# J007017_RGB_IR.net
KiCad netlist of a schematic drawn in EAGLE
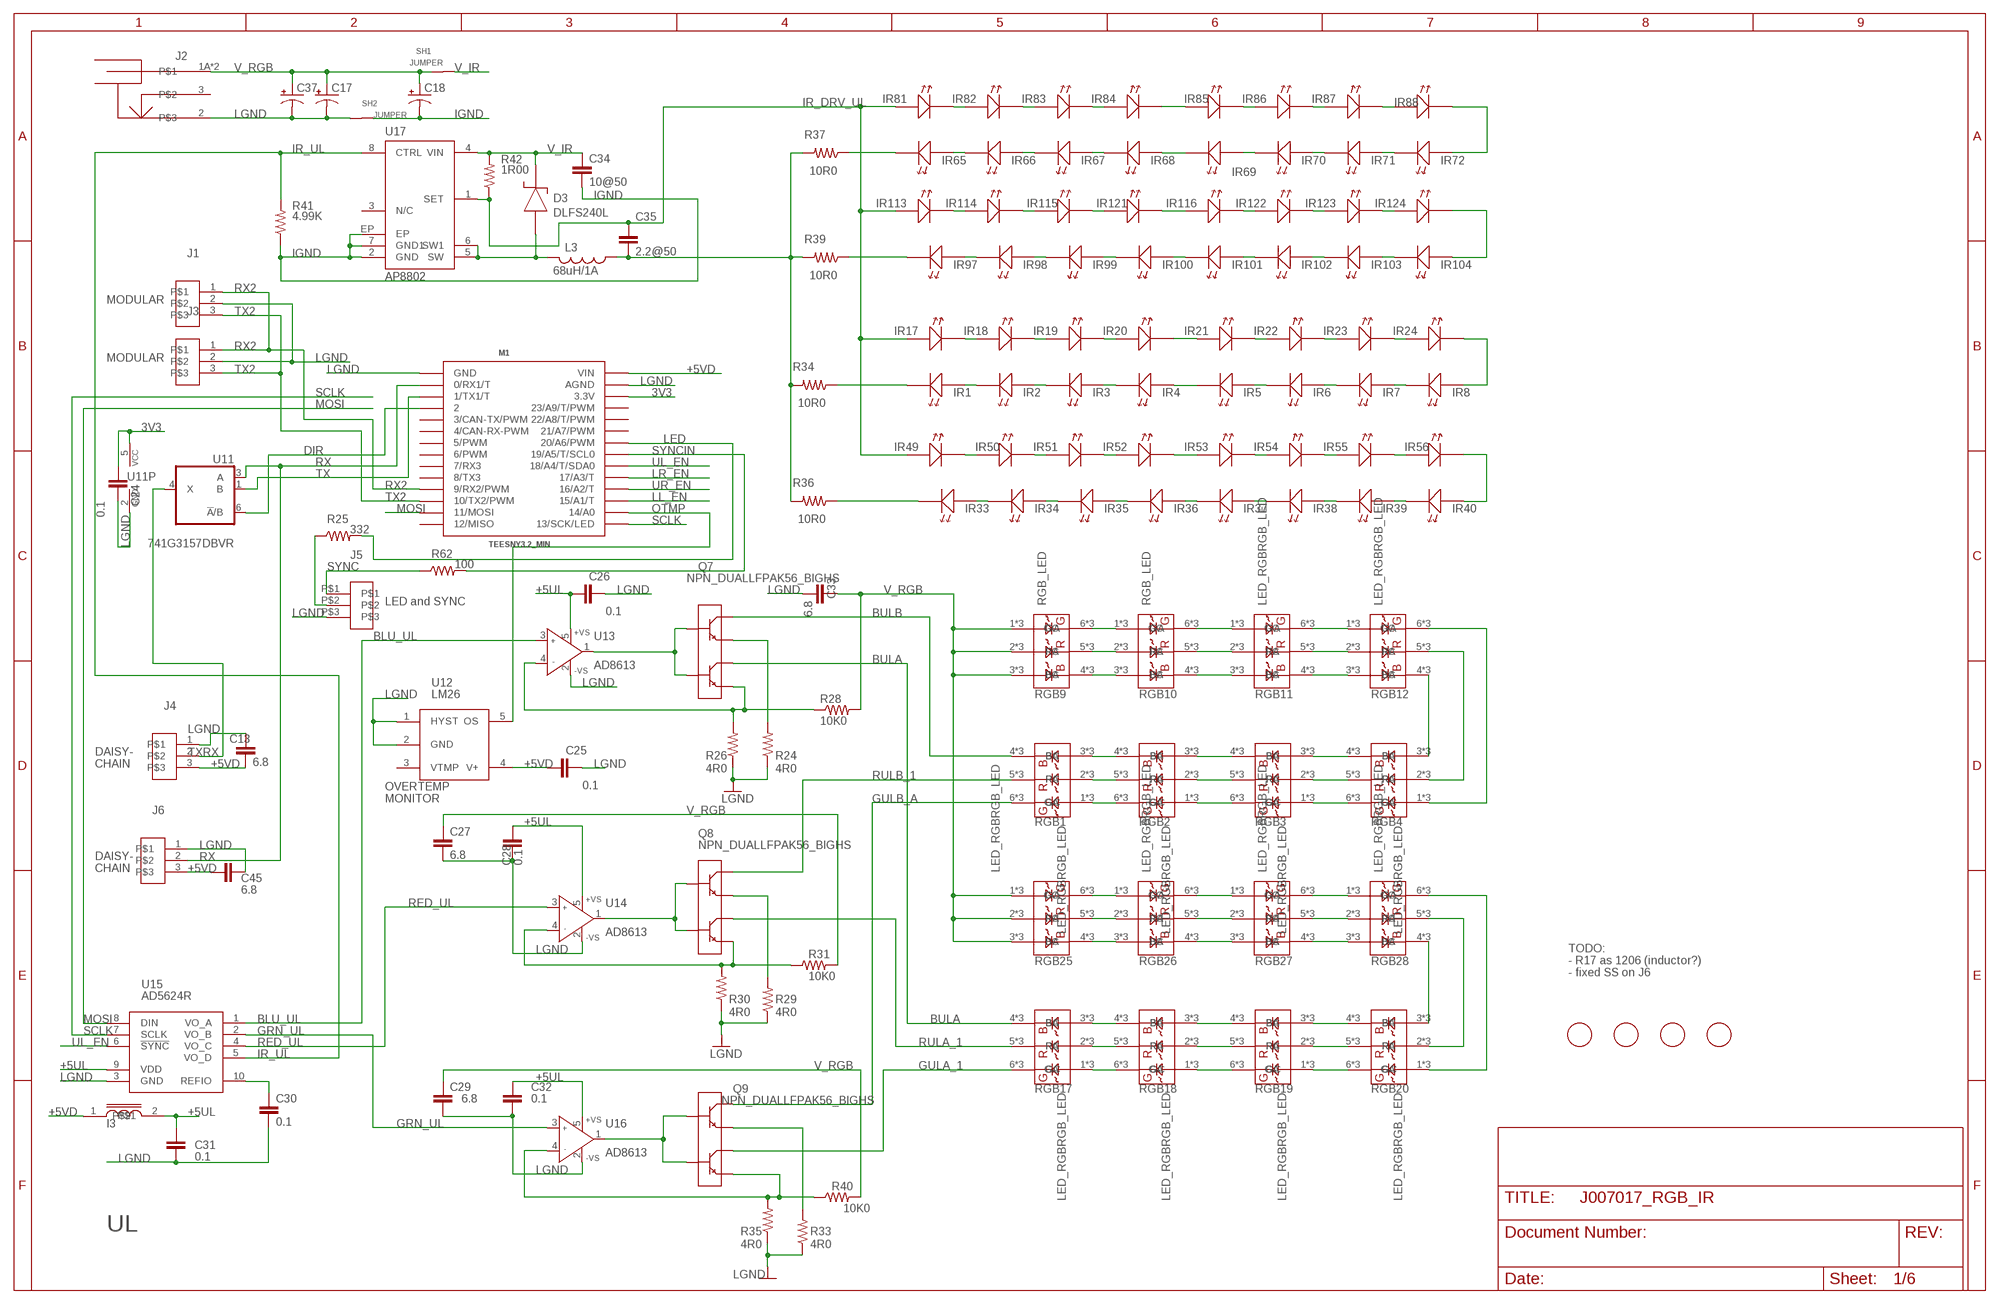
[diagram p0: schematic, sheet 1]
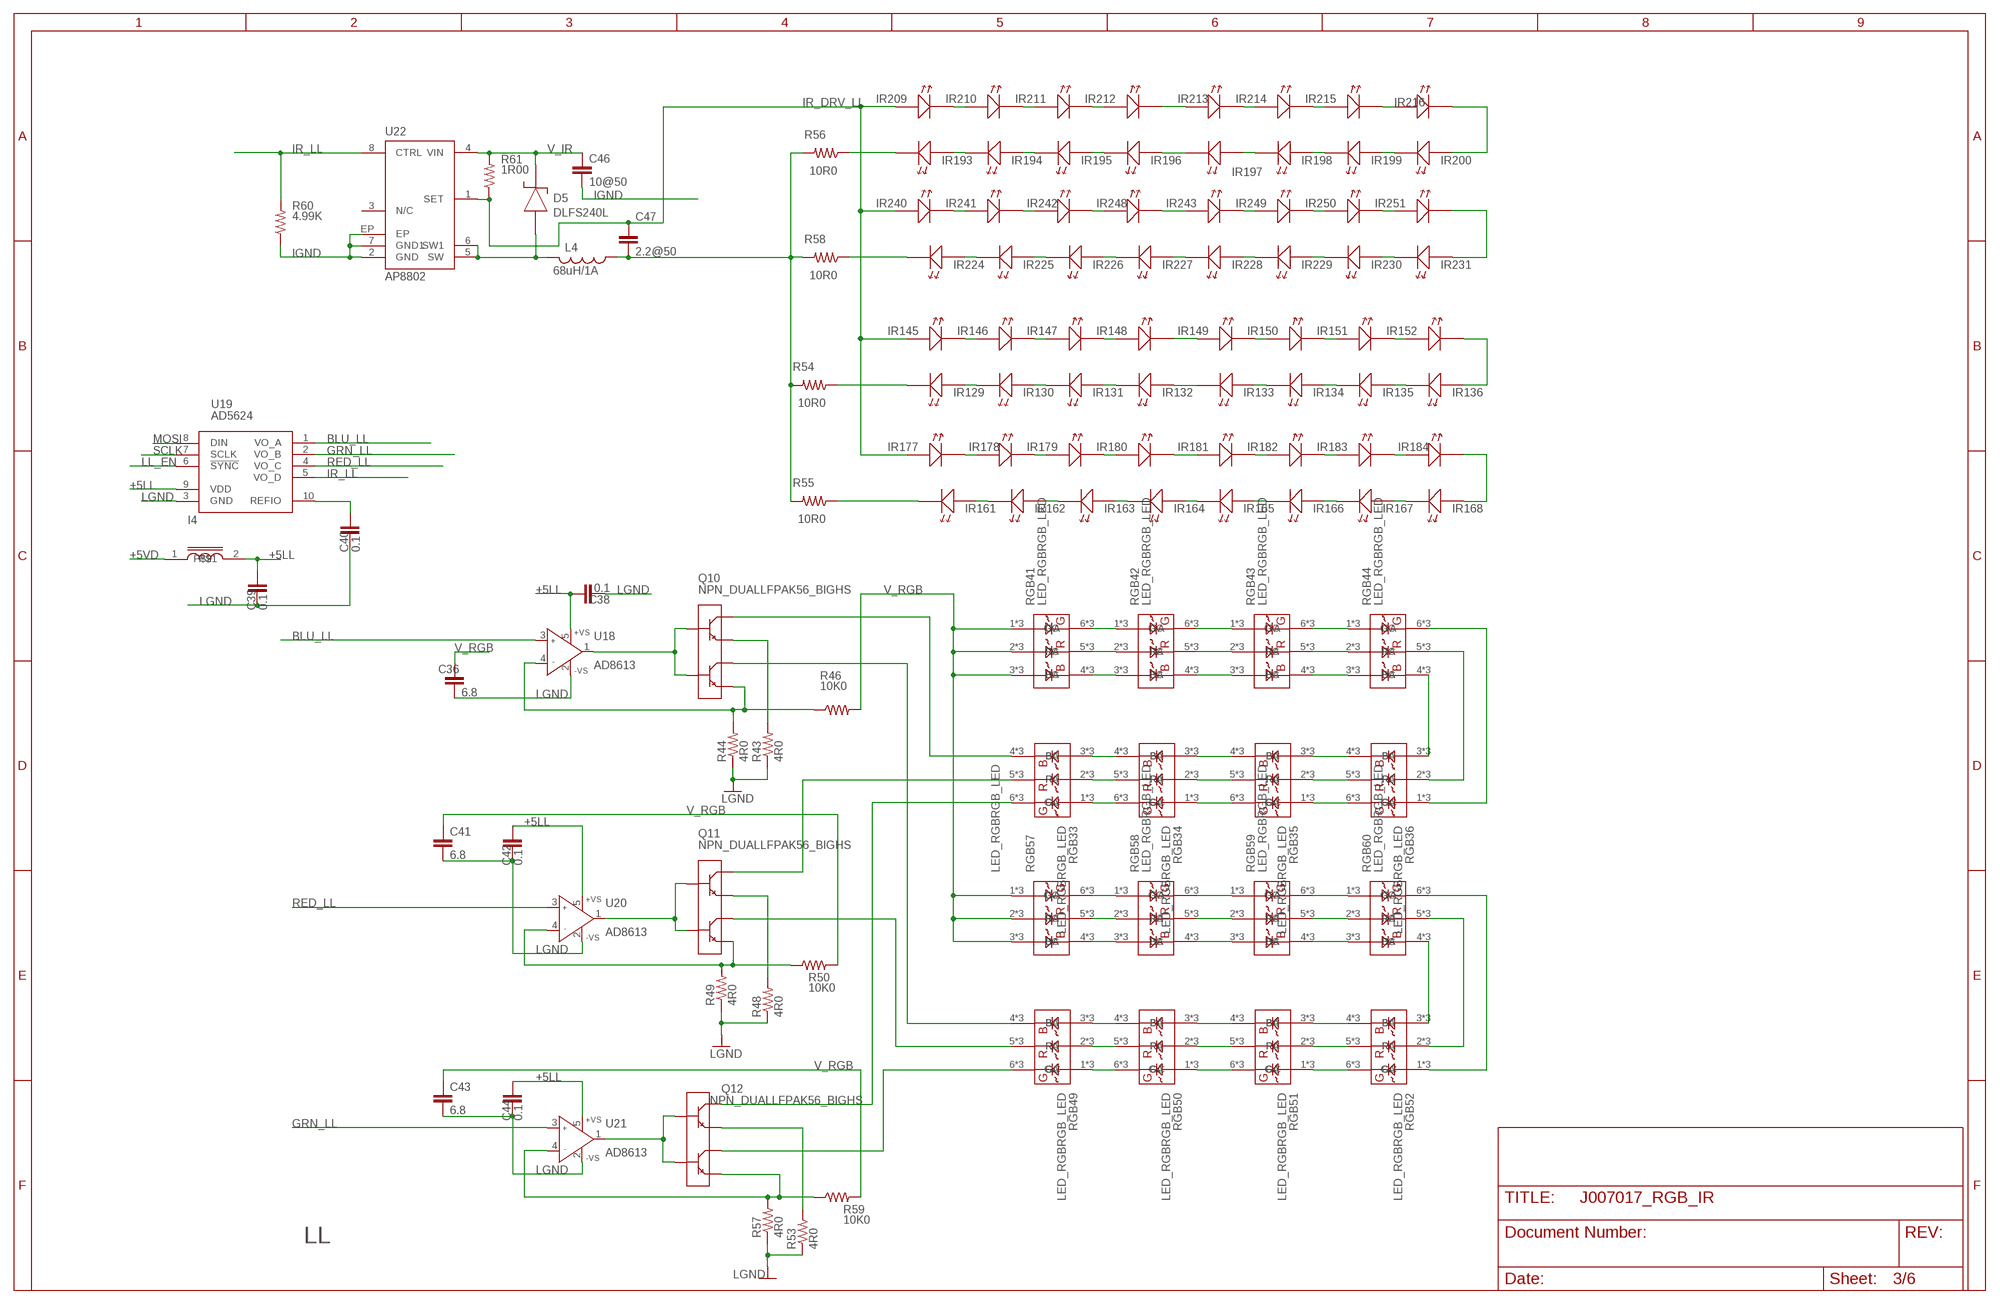
[diagram p1: schematic, sheet 3]
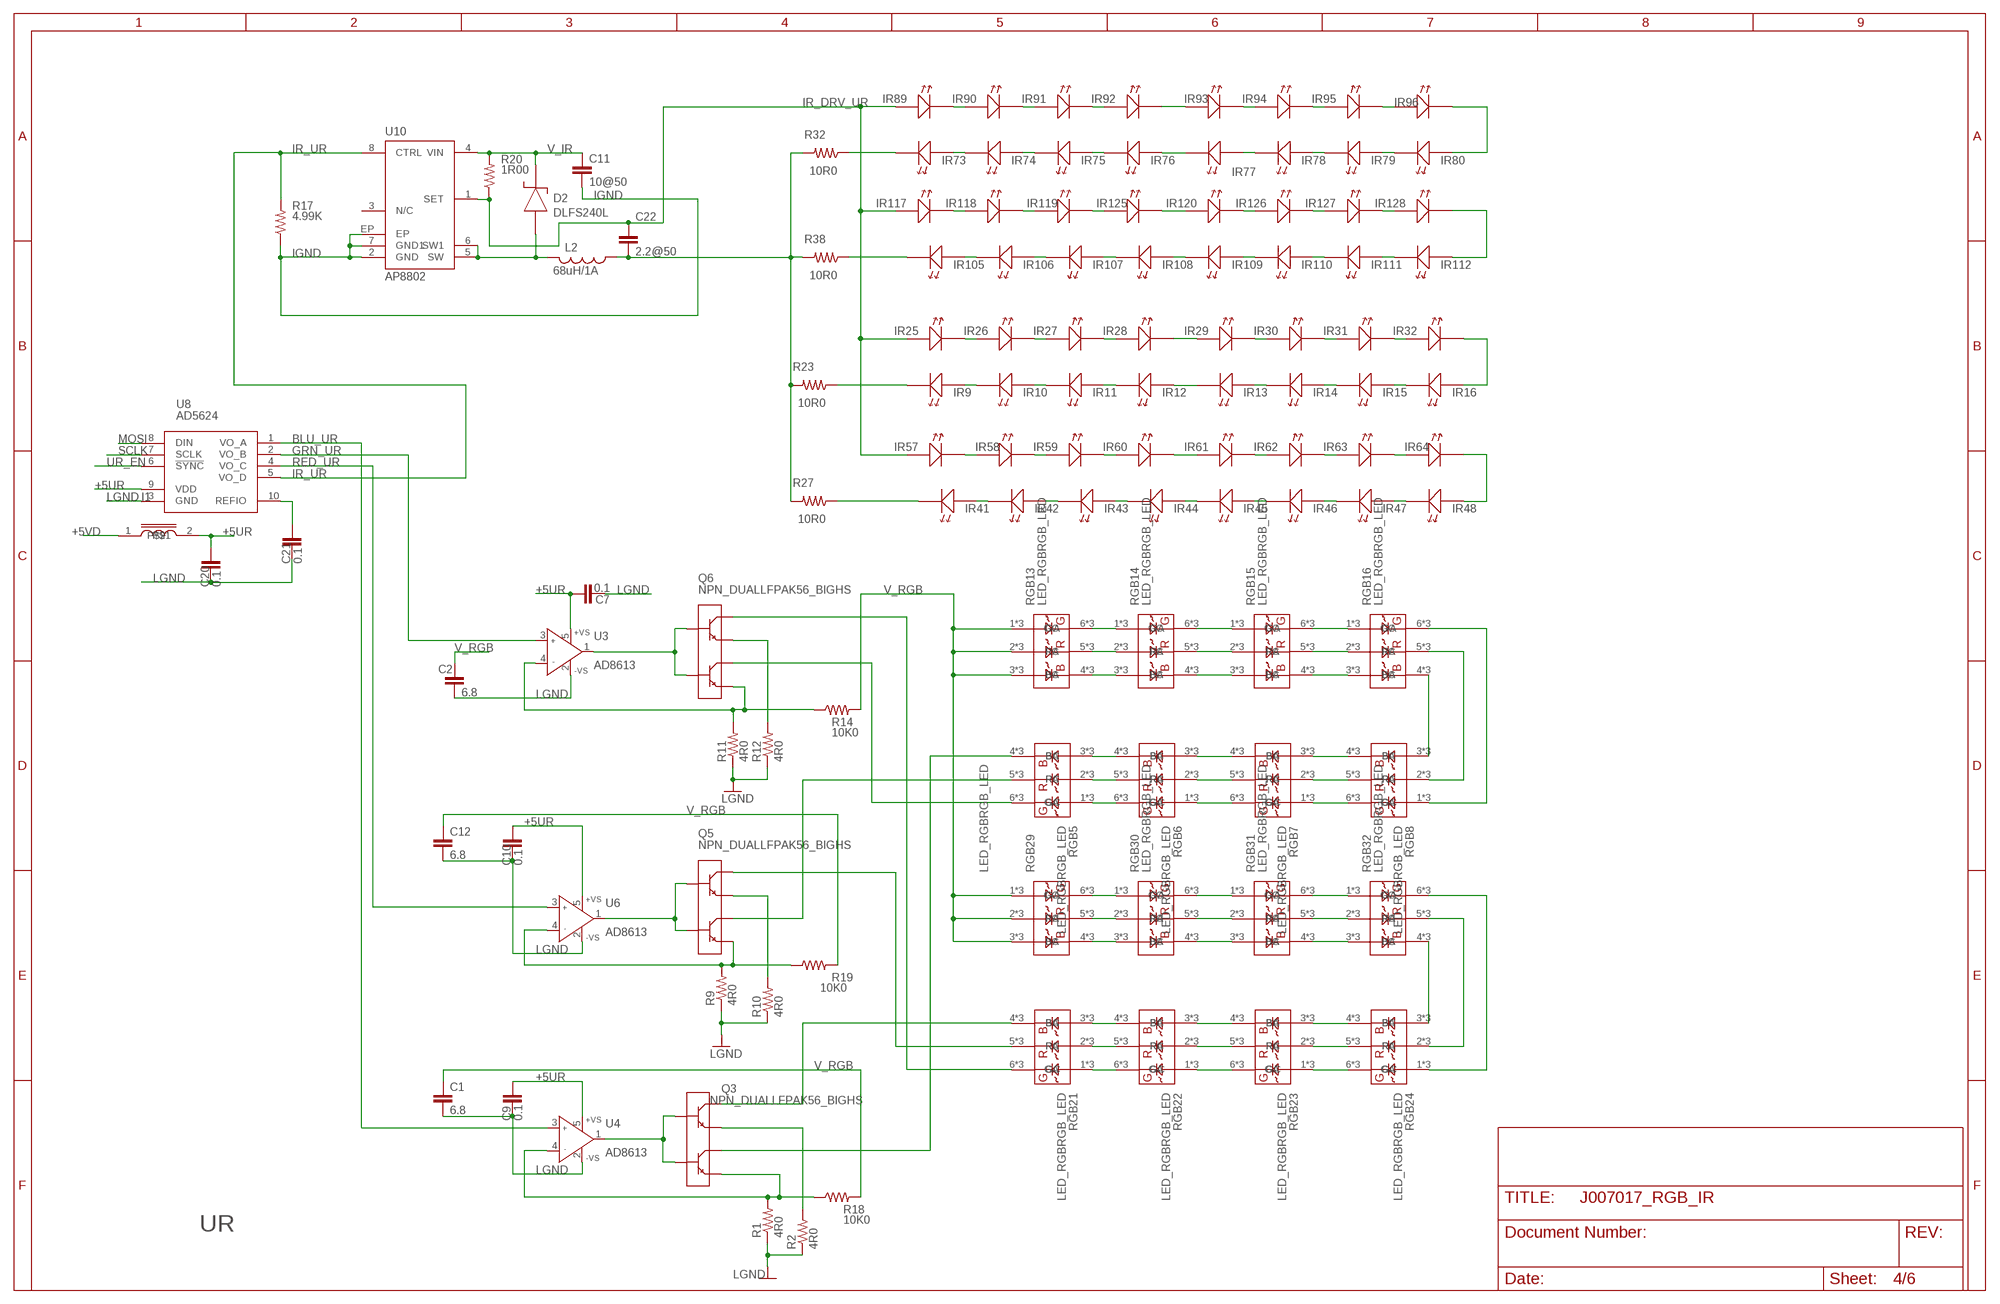
[diagram p2: schematic, sheet 4]
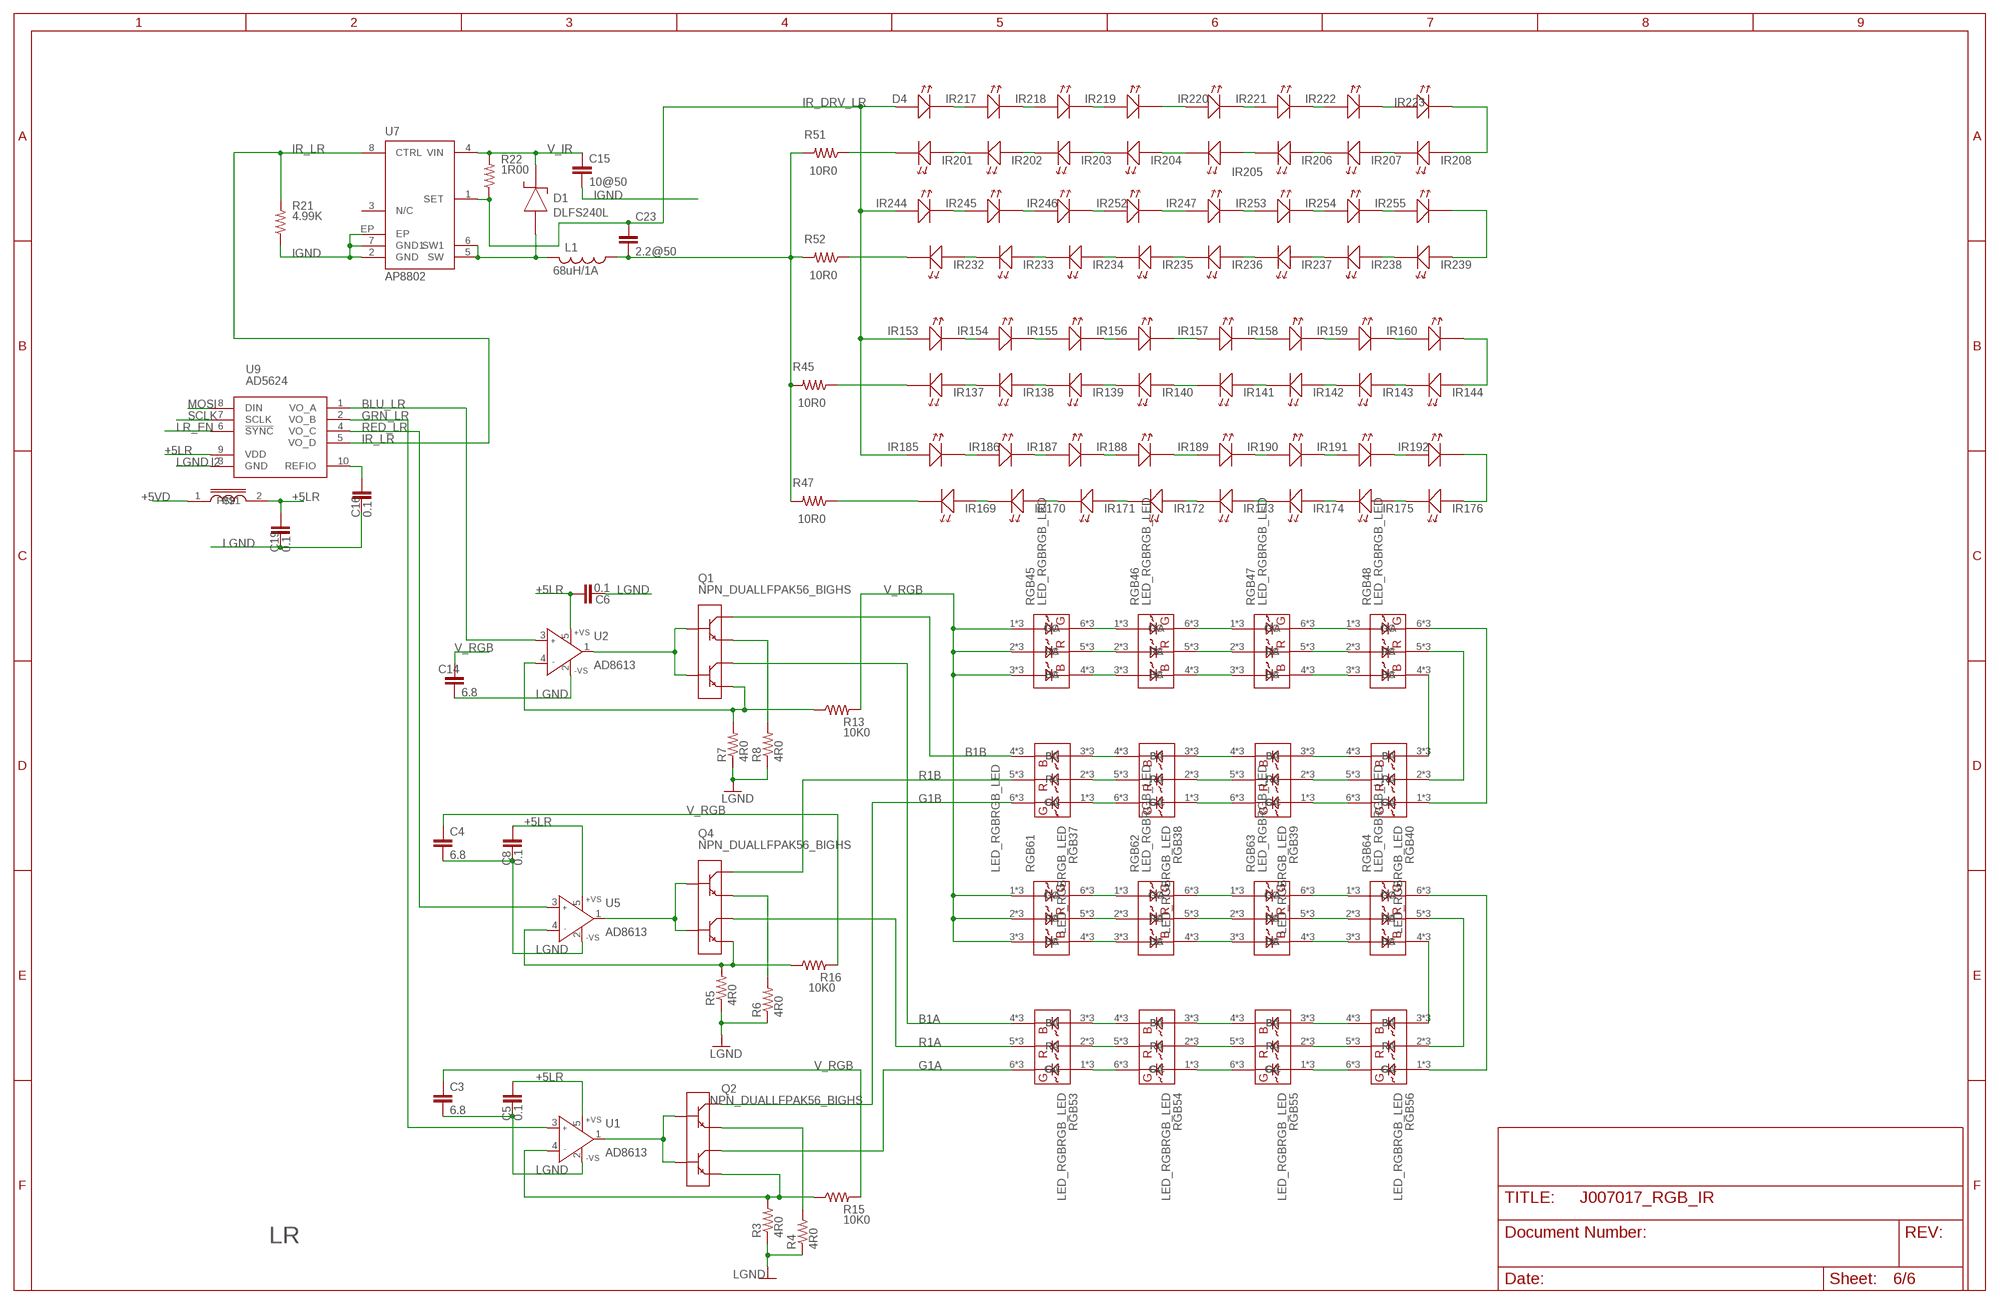
[diagram p3: schematic, sheet 6]

(export (version "E")
  (design (tool "Eeschema 10.0.6"))
  (components
    (comp (ref "C3")
      (value "6.8")
      (footprint "eagle-import:1210S")
      (libsource (lib "eagle-import") (part "CAPS1210S"))
    )
    (comp (ref "C4")
      (value "6.8")
      (footprint "eagle-import:1210S")
      (libsource (lib "eagle-import") (part "CAPS1210S"))
    )
    (comp (ref "C5")
      (value "0.1")
      (footprint "eagle-import:0603S")
      (libsource (lib "eagle-import") (part "CAPS0603S"))
    )
    (comp (ref "C6")
      (value "0.1")
      (footprint "eagle-import:0603S")
      (libsource (lib "eagle-import") (part "CAPS0603S"))
    )
    (comp (ref "C8")
      (value "0.1")
      (footprint "eagle-import:0603S")
      (libsource (lib "eagle-import") (part "CAPS0603S"))
    )
    (comp (ref "C14")
      (value "6.8")
      (footprint "eagle-import:1210S")
      (libsource (lib "eagle-import") (part "CAPS1210S"))
    )
    (comp (ref "C15")
      (value "10@50")
      (footprint "eagle-import:1210S")
      (libsource (lib "eagle-import") (part "CAPS1210S"))
    )
    (comp (ref "C16")
      (value "0.1")
      (footprint "eagle-import:0603S")
      (libsource (lib "eagle-import") (part "CAPS0603S"))
    )
    (comp (ref "C19")
      (value "0.1")
      (footprint "eagle-import:0603S")
      (libsource (lib "eagle-import") (part "CAPS0603S"))
    )
    (comp (ref "C23")
      (value "2.2@50")
      (footprint "eagle-import:1206S")
      (libsource (lib "eagle-import") (part "CAPS1206S"))
    )
    (comp (ref "D1")
      (value "DLFS240L")
      (footprint "eagle-import:PWRDI-123")
      (libsource (lib "eagle-import") (part "DIODE_SCHOTTKYPWRDI-123"))
    )
    (comp (ref "D4")
      (value "LEDLED_SFH4050_HEAT")
      (footprint "eagle-import:LED_SFH4050_HEAT")
      (libsource (lib "eagle-import") (part "LEDLED_SFH4050_HEAT"))
    )
    (comp (ref "I2")
      (value "INDUCTOR0805S")
      (footprint "eagle-import:0805S")
      (libsource (lib "eagle-import") (part "INDUCTOR0805S"))
    )
    (comp (ref "IR137")
      (value "LEDLED_SFH4050")
      (footprint "eagle-import:LED_SFH4050")
      (libsource (lib "eagle-import") (part "LEDLED_SFH4050"))
    )
    (comp (ref "IR138")
      (value "LEDLED_SFH4050_HEAT")
      (footprint "eagle-import:LED_SFH4050_HEAT")
      (libsource (lib "eagle-import") (part "LEDLED_SFH4050_HEAT"))
    )
    (comp (ref "IR139")
      (value "LEDLED_SFH4050_HEAT")
      (footprint "eagle-import:LED_SFH4050_HEAT")
      (libsource (lib "eagle-import") (part "LEDLED_SFH4050_HEAT"))
    )
    (comp (ref "IR140")
      (value "LEDLED_SFH4050_HEAT")
      (footprint "eagle-import:LED_SFH4050_HEAT")
      (libsource (lib "eagle-import") (part "LEDLED_SFH4050_HEAT"))
    )
    (comp (ref "IR141")
      (value "LEDLED_SFH4050_HEAT")
      (footprint "eagle-import:LED_SFH4050_HEAT")
      (libsource (lib "eagle-import") (part "LEDLED_SFH4050_HEAT"))
    )
    (comp (ref "IR142")
      (value "LEDLED_SFH4050_HEAT")
      (footprint "eagle-import:LED_SFH4050_HEAT")
      (libsource (lib "eagle-import") (part "LEDLED_SFH4050_HEAT"))
    )
    (comp (ref "IR143")
      (value "LEDLED_SFH4050_HEAT")
      (footprint "eagle-import:LED_SFH4050_HEAT")
      (libsource (lib "eagle-import") (part "LEDLED_SFH4050_HEAT"))
    )
    (comp (ref "IR144")
      (value "LEDLED_SFH4050_HEAT")
      (footprint "eagle-import:LED_SFH4050_HEAT")
      (libsource (lib "eagle-import") (part "LEDLED_SFH4050_HEAT"))
    )
    (comp (ref "IR153")
      (value "LEDLED_SFH4050_HEAT")
      (footprint "eagle-import:LED_SFH4050_HEAT")
      (libsource (lib "eagle-import") (part "LEDLED_SFH4050_HEAT"))
    )
    (comp (ref "IR154")
      (value "LEDLED_SFH4050_A")
      (footprint "eagle-import:LED_SFH4045_HEAT_A")
      (libsource (lib "eagle-import") (part "LEDLED_SFH4050_A"))
    )
    (comp (ref "IR155")
      (value "LEDLED_SFH4050_HEAT")
      (footprint "eagle-import:LED_SFH4050_HEAT")
      (libsource (lib "eagle-import") (part "LEDLED_SFH4050_HEAT"))
    )
    (comp (ref "IR156")
      (value "LEDLED_SFH4050_HEAT")
      (footprint "eagle-import:LED_SFH4050_HEAT")
      (libsource (lib "eagle-import") (part "LEDLED_SFH4050_HEAT"))
    )
    (comp (ref "IR157")
      (value "LEDLED_SFH4050_HEAT")
      (footprint "eagle-import:LED_SFH4050_HEAT")
      (libsource (lib "eagle-import") (part "LEDLED_SFH4050_HEAT"))
    )
    (comp (ref "IR158")
      (value "LEDLED_SFH4050_HEAT")
      (footprint "eagle-import:LED_SFH4050_HEAT")
      (libsource (lib "eagle-import") (part "LEDLED_SFH4050_HEAT"))
    )
    (comp (ref "IR159")
      (value "LEDLED_SFH4050_HEAT")
      (footprint "eagle-import:LED_SFH4050_HEAT")
      (libsource (lib "eagle-import") (part "LEDLED_SFH4050_HEAT"))
    )
    (comp (ref "IR160")
      (value "LEDLED_SFH4050_HEAT")
      (footprint "eagle-import:LED_SFH4050_HEAT")
      (libsource (lib "eagle-import") (part "LEDLED_SFH4050_HEAT"))
    )
    (comp (ref "IR169")
      (value "LEDLED_SFH4050_HEAT")
      (footprint "eagle-import:LED_SFH4050_HEAT")
      (libsource (lib "eagle-import") (part "LEDLED_SFH4050_HEAT"))
    )
    (comp (ref "IR170")
      (value "LEDLED_SFH4050_HEAT")
      (footprint "eagle-import:LED_SFH4050_HEAT")
      (libsource (lib "eagle-import") (part "LEDLED_SFH4050_HEAT"))
    )
    (comp (ref "IR171")
      (value "LEDLED_SFH4050_HEAT")
      (footprint "eagle-import:LED_SFH4050_HEAT")
      (libsource (lib "eagle-import") (part "LEDLED_SFH4050_HEAT"))
    )
    (comp (ref "IR172")
      (value "LEDLED_SFH4050_HEAT")
      (footprint "eagle-import:LED_SFH4050_HEAT")
      (libsource (lib "eagle-import") (part "LEDLED_SFH4050_HEAT"))
    )
    (comp (ref "IR173")
      (value "LEDLED_SFH4050_HEAT")
      (footprint "eagle-import:LED_SFH4050_HEAT")
      (libsource (lib "eagle-import") (part "LEDLED_SFH4050_HEAT"))
    )
    (comp (ref "IR174")
      (value "LEDLED_SFH4050_HEAT")
      (footprint "eagle-import:LED_SFH4050_HEAT")
      (libsource (lib "eagle-import") (part "LEDLED_SFH4050_HEAT"))
    )
    (comp (ref "IR175")
      (value "LEDLED_SFH4050_HEAT")
      (footprint "eagle-import:LED_SFH4050_HEAT")
      (libsource (lib "eagle-import") (part "LEDLED_SFH4050_HEAT"))
    )
    (comp (ref "IR176")
      (value "LEDLED_SFH4050_HEAT")
      (footprint "eagle-import:LED_SFH4050_HEAT")
      (libsource (lib "eagle-import") (part "LEDLED_SFH4050_HEAT"))
    )
    (comp (ref "IR185")
      (value "LEDLED_SFH4050_HEAT")
      (footprint "eagle-import:LED_SFH4050_HEAT")
      (libsource (lib "eagle-import") (part "LEDLED_SFH4050_HEAT"))
    )
    (comp (ref "IR186")
      (value "LEDLED_SFH4050_HEAT")
      (footprint "eagle-import:LED_SFH4050_HEAT")
      (libsource (lib "eagle-import") (part "LEDLED_SFH4050_HEAT"))
    )
    (comp (ref "IR187")
      (value "LEDLED_SFH4050_HEAT")
      (footprint "eagle-import:LED_SFH4050_HEAT")
      (libsource (lib "eagle-import") (part "LEDLED_SFH4050_HEAT"))
    )
    (comp (ref "IR188")
      (value "LEDLED_SFH4050_HEAT")
      (footprint "eagle-import:LED_SFH4050_HEAT")
      (libsource (lib "eagle-import") (part "LEDLED_SFH4050_HEAT"))
    )
    (comp (ref "IR189")
      (value "LEDLED_SFH4050_HEAT")
      (footprint "eagle-import:LED_SFH4050_HEAT")
      (libsource (lib "eagle-import") (part "LEDLED_SFH4050_HEAT"))
    )
    (comp (ref "IR190")
      (value "LEDLED_SFH4050_HEAT")
      (footprint "eagle-import:LED_SFH4050_HEAT")
      (libsource (lib "eagle-import") (part "LEDLED_SFH4050_HEAT"))
    )
    (comp (ref "IR191")
      (value "LEDLED_SFH4050_HEAT")
      (footprint "eagle-import:LED_SFH4050_HEAT")
      (libsource (lib "eagle-import") (part "LEDLED_SFH4050_HEAT"))
    )
    (comp (ref "IR192")
      (value "LEDLED_SFH4050_HEAT")
      (footprint "eagle-import:LED_SFH4050_HEAT")
      (libsource (lib "eagle-import") (part "LEDLED_SFH4050_HEAT"))
    )
    (comp (ref "IR201")
      (value "LEDLED_SFH4050_HEAT")
      (footprint "eagle-import:LED_SFH4050_HEAT")
      (libsource (lib "eagle-import") (part "LEDLED_SFH4050_HEAT"))
    )
    (comp (ref "IR202")
      (value "LEDLED_SFH4050_HEAT")
      (footprint "eagle-import:LED_SFH4050_HEAT")
      (libsource (lib "eagle-import") (part "LEDLED_SFH4050_HEAT"))
    )
    (comp (ref "IR203")
      (value "LEDLED_SFH4050_HEAT")
      (footprint "eagle-import:LED_SFH4050_HEAT")
      (libsource (lib "eagle-import") (part "LEDLED_SFH4050_HEAT"))
    )
    (comp (ref "IR204")
      (value "LEDLED_SFH4050_HEAT")
      (footprint "eagle-import:LED_SFH4050_HEAT")
      (libsource (lib "eagle-import") (part "LEDLED_SFH4050_HEAT"))
    )
    (comp (ref "IR205")
      (value "LEDLED_SFH4050_HEAT")
      (footprint "eagle-import:LED_SFH4050_HEAT")
      (libsource (lib "eagle-import") (part "LEDLED_SFH4050_HEAT"))
    )
    (comp (ref "IR206")
      (value "LEDLED_SFH4050_HEAT")
      (footprint "eagle-import:LED_SFH4050_HEAT")
      (libsource (lib "eagle-import") (part "LEDLED_SFH4050_HEAT"))
    )
    (comp (ref "IR207")
      (value "LEDLED_SFH4050_HEAT")
      (footprint "eagle-import:LED_SFH4050_HEAT")
      (libsource (lib "eagle-import") (part "LEDLED_SFH4050_HEAT"))
    )
    (comp (ref "IR208")
      (value "LEDLED_SFH4050_HEAT")
      (footprint "eagle-import:LED_SFH4050_HEAT")
      (libsource (lib "eagle-import") (part "LEDLED_SFH4050_HEAT"))
    )
    (comp (ref "IR217")
      (value "LEDLED_SFH4050_HEAT")
      (footprint "eagle-import:LED_SFH4050_HEAT")
      (libsource (lib "eagle-import") (part "LEDLED_SFH4050_HEAT"))
    )
    (comp (ref "IR218")
      (value "LEDLED_SFH4050_HEAT")
      (footprint "eagle-import:LED_SFH4050_HEAT")
      (libsource (lib "eagle-import") (part "LEDLED_SFH4050_HEAT"))
    )
    (comp (ref "IR219")
      (value "LEDLED_SFH4050_HEAT")
      (footprint "eagle-import:LED_SFH4050_HEAT")
      (libsource (lib "eagle-import") (part "LEDLED_SFH4050_HEAT"))
    )
    (comp (ref "IR220")
      (value "LEDLED_SFH4050_HEAT")
      (footprint "eagle-import:LED_SFH4050_HEAT")
      (libsource (lib "eagle-import") (part "LEDLED_SFH4050_HEAT"))
    )
    (comp (ref "IR221")
      (value "LEDLED_SFH4050_HEAT")
      (footprint "eagle-import:LED_SFH4050_HEAT")
      (libsource (lib "eagle-import") (part "LEDLED_SFH4050_HEAT"))
    )
    (comp (ref "IR222")
      (value "LEDLED_SFH4050_HEAT")
      (footprint "eagle-import:LED_SFH4050_HEAT")
      (libsource (lib "eagle-import") (part "LEDLED_SFH4050_HEAT"))
    )
    (comp (ref "IR223")
      (value "LEDLED_SFH4050_HEAT")
      (footprint "eagle-import:LED_SFH4050_HEAT")
      (libsource (lib "eagle-import") (part "LEDLED_SFH4050_HEAT"))
    )
    (comp (ref "IR232")
      (value "LEDLED_SFH4050_HEAT")
      (footprint "eagle-import:LED_SFH4050_HEAT")
      (libsource (lib "eagle-import") (part "LEDLED_SFH4050_HEAT"))
    )
    (comp (ref "IR233")
      (value "LEDLED_SFH4050_HEAT")
      (footprint "eagle-import:LED_SFH4050_HEAT")
      (libsource (lib "eagle-import") (part "LEDLED_SFH4050_HEAT"))
    )
    (comp (ref "IR234")
      (value "LEDLED_SFH4050_HEAT")
      (footprint "eagle-import:LED_SFH4050_HEAT")
      (libsource (lib "eagle-import") (part "LEDLED_SFH4050_HEAT"))
    )
    (comp (ref "IR235")
      (value "LEDLED_SFH4050_HEAT")
      (footprint "eagle-import:LED_SFH4050_HEAT")
      (libsource (lib "eagle-import") (part "LEDLED_SFH4050_HEAT"))
    )
    (comp (ref "IR236")
      (value "LEDLED_SFH4050_HEAT")
      (footprint "eagle-import:LED_SFH4050_HEAT")
      (libsource (lib "eagle-import") (part "LEDLED_SFH4050_HEAT"))
    )
    (comp (ref "IR237")
      (value "LEDLED_SFH4050_HEAT")
      (footprint "eagle-import:LED_SFH4050_HEAT")
      (libsource (lib "eagle-import") (part "LEDLED_SFH4050_HEAT"))
    )
    (comp (ref "IR238")
      (value "LEDLED_SFH4050_HEAT")
      (footprint "eagle-import:LED_SFH4050_HEAT")
      (libsource (lib "eagle-import") (part "LEDLED_SFH4050_HEAT"))
    )
    (comp (ref "IR239")
      (value "LEDLED_SFH4050_HEAT")
      (footprint "eagle-import:LED_SFH4050_HEAT")
      (libsource (lib "eagle-import") (part "LEDLED_SFH4050_HEAT"))
    )
    (comp (ref "IR244")
      (value "LEDLED_SFH4050_HEAT")
      (footprint "eagle-import:LED_SFH4050_HEAT")
      (libsource (lib "eagle-import") (part "LEDLED_SFH4050_HEAT"))
    )
    (comp (ref "IR245")
      (value "LEDLED_SFH4050_HEAT")
      (footprint "eagle-import:LED_SFH4050_HEAT")
      (libsource (lib "eagle-import") (part "LEDLED_SFH4050_HEAT"))
    )
    (comp (ref "IR246")
      (value "LEDLED_SFH4050_HEAT")
      (footprint "eagle-import:LED_SFH4050_HEAT")
      (libsource (lib "eagle-import") (part "LEDLED_SFH4050_HEAT"))
    )
    (comp (ref "IR247")
      (value "LEDLED_SFH4050_HEAT")
      (footprint "eagle-import:LED_SFH4050_HEAT")
      (libsource (lib "eagle-import") (part "LEDLED_SFH4050_HEAT"))
    )
    (comp (ref "IR252")
      (value "LEDLED_SFH4050_HEAT")
      (footprint "eagle-import:LED_SFH4050_HEAT")
      (libsource (lib "eagle-import") (part "LEDLED_SFH4050_HEAT"))
    )
    (comp (ref "IR253")
      (value "LEDLED_SFH4050_HEAT")
      (footprint "eagle-import:LED_SFH4050_HEAT")
      (libsource (lib "eagle-import") (part "LEDLED_SFH4050_HEAT"))
    )
    (comp (ref "IR254")
      (value "LEDLED_SFH4050_HEAT")
      (footprint "eagle-import:LED_SFH4050_HEAT")
      (libsource (lib "eagle-import") (part "LEDLED_SFH4050_HEAT"))
    )
    (comp (ref "IR255")
      (value "LEDLED_SFH4050")
      (footprint "eagle-import:LED_SFH4050")
      (libsource (lib "eagle-import") (part "LEDLED_SFH4050"))
    )
    (comp (ref "L1")
      (value "68uH/1A")
      (footprint "eagle-import:SRU8043")
      (libsource (lib "eagle-import") (part "INDUCTOR_SMSRU8043"))
    )
    (comp (ref "Q1")
      (value "NPN_DUALLFPAK56_BIGHS")
      (footprint "eagle-import:LFPAK56_HS2")
      (libsource (lib "eagle-import") (part "NPN_DUALLFPAK56_BIGHS"))
    )
    (comp (ref "Q2")
      (value "NPN_DUALLFPAK56_BIGHS")
      (footprint "eagle-import:LFPAK56_HS2")
      (libsource (lib "eagle-import") (part "NPN_DUALLFPAK56_BIGHS"))
    )
    (comp (ref "Q4")
      (value "NPN_DUALLFPAK56_BIGHS")
      (footprint "eagle-import:LFPAK56_HS2")
      (libsource (lib "eagle-import") (part "NPN_DUALLFPAK56_BIGHS"))
    )
    (comp (ref "R3")
      (value "4R0")
      (footprint "eagle-import:1812")
      (libsource (lib "eagle-import") (part "RESISTOR-POWER1812"))
    )
    (comp (ref "R4")
      (value "4R0")
      (footprint "eagle-import:1812")
      (libsource (lib "eagle-import") (part "RESISTOR-POWER1812"))
    )
    (comp (ref "R5")
      (value "4R0")
      (footprint "eagle-import:1812")
      (libsource (lib "eagle-import") (part "RESISTOR-POWER1812"))
    )
    (comp (ref "R6")
      (value "4R0")
      (footprint "eagle-import:1812")
      (libsource (lib "eagle-import") (part "RESISTOR-POWER1812"))
    )
    (comp (ref "R7")
      (value "4R0")
      (footprint "eagle-import:1812")
      (libsource (lib "eagle-import") (part "RESISTOR-POWER1812"))
    )
    (comp (ref "R8")
      (value "4R0")
      (footprint "eagle-import:1812")
      (libsource (lib "eagle-import") (part "RESISTOR-POWER1812"))
    )
    (comp (ref "R13")
      (value "10K0")
      (footprint "eagle-import:1206S")
      (libsource (lib "eagle-import") (part "RESISTOR_SM1206S"))
    )
    (comp (ref "R15")
      (value "10K0")
      (footprint "eagle-import:1206S")
      (libsource (lib "eagle-import") (part "RESISTOR_SM1206S"))
    )
    (comp (ref "R16")
      (value "10K0")
      (footprint "eagle-import:1206S")
      (libsource (lib "eagle-import") (part "RESISTOR_SM1206S"))
    )
    (comp (ref "R21")
      (value "4.99K")
      (footprint "eagle-import:0805S")
      (libsource (lib "eagle-import") (part "RESISTOR_SM0805S"))
    )
    (comp (ref "R22")
      (value "1R00")
      (footprint "eagle-import:1206S")
      (libsource (lib "eagle-import") (part "RESISTOR_SM1206S"))
    )
    (comp (ref "R45")
      (value "10R0")
      (footprint "eagle-import:1206S")
      (libsource (lib "eagle-import") (part "RESISTOR_SM1206S"))
    )
    (comp (ref "R47")
      (value "10R0")
      (footprint "eagle-import:1206S")
      (libsource (lib "eagle-import") (part "RESISTOR_SM1206S"))
    )
    (comp (ref "R51")
      (value "10R0")
      (footprint "eagle-import:1206S")
      (libsource (lib "eagle-import") (part "RESISTOR_SM1206S"))
    )
    (comp (ref "R52")
      (value "10R0")
      (footprint "eagle-import:1206S")
      (libsource (lib "eagle-import") (part "RESISTOR_SM1206S"))
    )
    (comp (ref "RGB37")
      (value "LED_RGBRGB_LED")
      (footprint "eagle-import:OVSPRGB_HS_FIXED")
      (libsource (lib "eagle-import") (part "LED_RGBRGB_LED"))
    )
    (comp (ref "RGB38")
      (value "LED_RGBRGB_LED")
      (footprint "eagle-import:OVSPRGB_HS_FIXED")
      (libsource (lib "eagle-import") (part "LED_RGBRGB_LED"))
    )
    (comp (ref "RGB39")
      (value "LED_RGBRGB_LED")
      (footprint "eagle-import:OVSPRGB_HS_FIXED")
      (libsource (lib "eagle-import") (part "LED_RGBRGB_LED"))
    )
    (comp (ref "RGB40")
      (value "LED_RGBRGB_LED")
      (footprint "eagle-import:OVSPRGB_HS_FIXED")
      (libsource (lib "eagle-import") (part "LED_RGBRGB_LED"))
    )
    (comp (ref "RGB45")
      (value "LED_RGBRGB_LED")
      (footprint "eagle-import:OVSPRGB_HS_FIXED")
      (libsource (lib "eagle-import") (part "LED_RGBRGB_LED"))
    )
    (comp (ref "RGB46")
      (value "LED_RGBRGB_LED")
      (footprint "eagle-import:OVSPRGB_HS_FIXED")
      (libsource (lib "eagle-import") (part "LED_RGBRGB_LED"))
    )
    (comp (ref "RGB47")
      (value "LED_RGBRGB_LED")
      (footprint "eagle-import:OVSPRGB_HS_FIXED")
      (libsource (lib "eagle-import") (part "LED_RGBRGB_LED"))
    )
    (comp (ref "RGB48")
      (value "LED_RGBRGB_LED")
      (footprint "eagle-import:OVSPRGB_HS_FIXED")
      (libsource (lib "eagle-import") (part "LED_RGBRGB_LED"))
    )
    (comp (ref "RGB53")
      (value "LED_RGBRGB_LED")
      (footprint "eagle-import:OVSPRGB_HS_FIXED")
      (libsource (lib "eagle-import") (part "LED_RGBRGB_LED"))
    )
    (comp (ref "RGB54")
      (value "LED_RGBRGB_LED")
      (footprint "eagle-import:OVSPRGB_HS_FIXED")
      (libsource (lib "eagle-import") (part "LED_RGBRGB_LED"))
    )
    (comp (ref "RGB55")
      (value "LED_RGBRGB_LED")
      (footprint "eagle-import:OVSPRGB_HS_FIXED")
      (libsource (lib "eagle-import") (part "LED_RGBRGB_LED"))
    )
    (comp (ref "RGB56")
      (value "LED_RGBRGB_LED")
      (footprint "eagle-import:OVSPRGB_HS_FIXED")
      (libsource (lib "eagle-import") (part "LED_RGBRGB_LED"))
    )
    (comp (ref "RGB61")
      (value "LED_RGBRGB_LED")
      (footprint "eagle-import:OVSPRGB_HS_FIXED")
      (libsource (lib "eagle-import") (part "LED_RGBRGB_LED"))
    )
    (comp (ref "RGB62")
      (value "LED_RGBRGB_LED")
      (footprint "eagle-import:OVSPRGB_HS_FIXED")
      (libsource (lib "eagle-import") (part "LED_RGBRGB_LED"))
    )
    (comp (ref "RGB63")
      (value "LED_RGBRGB_LED")
      (footprint "eagle-import:OVSPRGB_HS_FIXED")
      (libsource (lib "eagle-import") (part "LED_RGBRGB_LED"))
    )
    (comp (ref "RGB64")
      (value "LED_RGBRGB_LED")
      (footprint "eagle-import:OVSPRGB_HS_FIXED")
      (libsource (lib "eagle-import") (part "LED_RGBRGB_LED"))
    )
    (comp (ref "U1")
      (value "AD8613")
      (footprint "eagle-import:SOT23-5")
      (fields (field (name "MF") "ALTERA CORPORATION") (field (name "MPN") "AD8065ARTZ-REEL7"))
      (libsource (lib "eagle-import") (part "AD8065RT"))
    )
    (comp (ref "U2")
      (value "AD8613")
      (footprint "eagle-import:SOT23-5")
      (fields (field (name "MF") "ALTERA CORPORATION") (field (name "MPN") "AD8065ARTZ-REEL7"))
      (libsource (lib "eagle-import") (part "AD8065RT"))
    )
    (comp (ref "U5")
      (value "AD8613")
      (footprint "eagle-import:SOT23-5")
      (fields (field (name "MF") "ALTERA CORPORATION") (field (name "MPN") "AD8065ARTZ-REEL7"))
      (libsource (lib "eagle-import") (part "AD8065RT"))
    )
    (comp (ref "U7")
      (value "AP8802")
      (footprint "eagle-import:SOIC8-EP")
      (libsource (lib "eagle-import") (part "AP8802"))
    )
    (comp (ref "U9")
      (value "AD5624")
      (footprint "eagle-import:MSOP10")
      (libsource (lib "eagle-import") (part "AD56X4R"))
    )
    (comp (ref "$$U$1")
      (value "FIDUCIAL")
      (footprint "eagle-import:FIDUCIAL_1MM")
      (libsource (lib "eagle-import") (part "FIDUCIAL"))
    )
    (comp (ref "$$U$2")
      (value "FIDUCIAL")
      (footprint "eagle-import:FIDUCIAL_1MM")
      (libsource (lib "eagle-import") (part "FIDUCIAL"))
    )
    (comp (ref "$$U$3")
      (value "FIDUCIAL")
      (footprint "eagle-import:FIDUCIAL_1MM")
      (libsource (lib "eagle-import") (part "FIDUCIAL"))
    )
    (comp (ref "C13")
      (value "6.8")
      (footprint "eagle-import:1210S")
      (libsource (lib "eagle-import") (part "CAPS1210S"))
    )
    (comp (ref "C17")
      (value "CPOL-US153CLV-0810")
      (footprint "eagle-import:153CLV-0810")
      (libsource (lib "eagle-import") (part "CPOL-US153CLV-0810"))
    )
    (comp (ref "C18")
      (value "CPOL-US153CLV-0810")
      (footprint "eagle-import:153CLV-0810")
      (libsource (lib "eagle-import") (part "CPOL-US153CLV-0810"))
    )
    (comp (ref "C24")
      (value "0.1")
      (footprint "eagle-import:0603S")
      (libsource (lib "eagle-import") (part "CAPS0603S"))
    )
    (comp (ref "C25")
      (value "0.1")
      (footprint "eagle-import:0603S")
      (libsource (lib "eagle-import") (part "CAPS0603S"))
    )
    (comp (ref "C26")
      (value "0.1")
      (footprint "eagle-import:0603S")
      (libsource (lib "eagle-import") (part "CAPS0603S"))
    )
    (comp (ref "C27")
      (value "6.8")
      (footprint "eagle-import:1210S")
      (libsource (lib "eagle-import") (part "CAPS1210S"))
    )
    (comp (ref "C28")
      (value "0.1")
      (footprint "eagle-import:0603S")
      (libsource (lib "eagle-import") (part "CAPS0603S"))
    )
    (comp (ref "C29")
      (value "6.8")
      (footprint "eagle-import:1210S")
      (libsource (lib "eagle-import") (part "CAPS1210S"))
    )
    (comp (ref "C30")
      (value "0.1")
      (footprint "eagle-import:0603S")
      (libsource (lib "eagle-import") (part "CAPS0603S"))
    )
    (comp (ref "C31")
      (value "0.1")
      (footprint "eagle-import:0603S")
      (libsource (lib "eagle-import") (part "CAPS0603S"))
    )
    (comp (ref "C32")
      (value "0.1")
      (footprint "eagle-import:0603S")
      (libsource (lib "eagle-import") (part "CAPS0603S"))
    )
    (comp (ref "C33")
      (value "6.8")
      (footprint "eagle-import:1210S")
      (libsource (lib "eagle-import") (part "CAPS1210S"))
    )
    (comp (ref "C34")
      (value "10@50")
      (footprint "eagle-import:1210S")
      (libsource (lib "eagle-import") (part "CAPS1210S"))
    )
    (comp (ref "C35")
      (value "2.2@50")
      (footprint "eagle-import:1206S")
      (libsource (lib "eagle-import") (part "CAPS1206S"))
    )
    (comp (ref "C37")
      (value "CPOL-US153CLV-0810")
      (footprint "eagle-import:153CLV-0810")
      (libsource (lib "eagle-import") (part "CPOL-US153CLV-0810"))
    )
    (comp (ref "C45")
      (value "6.8")
      (footprint "eagle-import:1210S")
      (libsource (lib "eagle-import") (part "CAPS1210S"))
    )
    (comp (ref "D3")
      (value "DLFS240L")
      (footprint "eagle-import:PWRDI-123")
      (libsource (lib "eagle-import") (part "DIODE_SCHOTTKYPWRDI-123"))
    )
    (comp (ref "I3")
      (value "INDUCTOR0805S")
      (footprint "eagle-import:0805S")
      (libsource (lib "eagle-import") (part "INDUCTOR0805S"))
    )
    (comp (ref "IR1")
      (value "LEDLED_SFH4050_A")
      (footprint "eagle-import:LED_SFH4045_HEAT_A")
      (libsource (lib "eagle-import") (part "LEDLED_SFH4050_A"))
    )
    (comp (ref "IR2")
      (value "LEDLED_SFH4050_HEAT")
      (footprint "eagle-import:LED_SFH4050_HEAT")
      (libsource (lib "eagle-import") (part "LEDLED_SFH4050_HEAT"))
    )
    (comp (ref "IR3")
      (value "LEDLED_SFH4050_HEAT")
      (footprint "eagle-import:LED_SFH4050_HEAT")
      (libsource (lib "eagle-import") (part "LEDLED_SFH4050_HEAT"))
    )
    (comp (ref "IR4")
      (value "LEDLED_SFH4050_HEAT")
      (footprint "eagle-import:LED_SFH4050_HEAT")
      (libsource (lib "eagle-import") (part "LEDLED_SFH4050_HEAT"))
    )
    (comp (ref "IR5")
      (value "LEDLED_SFH4050_HEAT")
      (footprint "eagle-import:LED_SFH4050_HEAT")
      (libsource (lib "eagle-import") (part "LEDLED_SFH4050_HEAT"))
    )
    (comp (ref "IR6")
      (value "LEDLED_SFH4050_HEAT")
      (footprint "eagle-import:LED_SFH4050_HEAT")
      (libsource (lib "eagle-import") (part "LEDLED_SFH4050_HEAT"))
    )
    (comp (ref "IR7")
      (value "LEDLED_SFH4050_HEAT")
      (footprint "eagle-import:LED_SFH4050_HEAT")
      (libsource (lib "eagle-import") (part "LEDLED_SFH4050_HEAT"))
    )
    (comp (ref "IR8")
      (value "LEDLED_SFH4050_HEAT")
      (footprint "eagle-import:LED_SFH4050_HEAT")
      (libsource (lib "eagle-import") (part "LEDLED_SFH4050_HEAT"))
    )
    (comp (ref "IR17")
      (value "LEDLED_SFH4050_HEAT")
      (footprint "eagle-import:LED_SFH4050_HEAT")
      (libsource (lib "eagle-import") (part "LEDLED_SFH4050_HEAT"))
    )
    (comp (ref "IR18")
      (value "LEDLED_SFH4050_HEAT")
      (footprint "eagle-import:LED_SFH4050_HEAT")
      (libsource (lib "eagle-import") (part "LEDLED_SFH4050_HEAT"))
    )
    (comp (ref "IR19")
      (value "LEDLED_SFH4050_HEAT")
      (footprint "eagle-import:LED_SFH4050_HEAT")
      (libsource (lib "eagle-import") (part "LEDLED_SFH4050_HEAT"))
    )
    (comp (ref "IR20")
      (value "LEDLED_SFH4050_HEAT")
      (footprint "eagle-import:LED_SFH4050_HEAT")
      (libsource (lib "eagle-import") (part "LEDLED_SFH4050_HEAT"))
    )
    (comp (ref "IR21")
      (value "LEDLED_SFH4050_HEAT")
      (footprint "eagle-import:LED_SFH4050_HEAT")
      (libsource (lib "eagle-import") (part "LEDLED_SFH4050_HEAT"))
    )
    (comp (ref "IR22")
      (value "LEDLED_SFH4050_HEAT")
      (footprint "eagle-import:LED_SFH4050_HEAT")
      (libsource (lib "eagle-import") (part "LEDLED_SFH4050_HEAT"))
    )
    (comp (ref "IR23")
      (value "LEDLED_SFH4050_HEAT")
      (footprint "eagle-import:LED_SFH4050_HEAT")
      (libsource (lib "eagle-import") (part "LEDLED_SFH4050_HEAT"))
    )
    (comp (ref "IR24")
      (value "LEDLED_SFH4050_HEAT")
      (footprint "eagle-import:LED_SFH4050_HEAT")
      (libsource (lib "eagle-import") (part "LEDLED_SFH4050_HEAT"))
    )
    (comp (ref "IR33")
      (value "LEDLED_SFH4050_HEAT")
      (footprint "eagle-import:LED_SFH4050_HEAT")
      (libsource (lib "eagle-import") (part "LEDLED_SFH4050_HEAT"))
    )
    (comp (ref "IR34")
      (value "LEDLED_SFH4050_HEAT")
      (footprint "eagle-import:LED_SFH4050_HEAT")
      (libsource (lib "eagle-import") (part "LEDLED_SFH4050_HEAT"))
    )
    (comp (ref "IR35")
      (value "LEDLED_SFH4050_HEAT")
      (footprint "eagle-import:LED_SFH4050_HEAT")
      (libsource (lib "eagle-import") (part "LEDLED_SFH4050_HEAT"))
    )
    (comp (ref "IR36")
      (value "LEDLED_SFH4050_HEAT")
      (footprint "eagle-import:LED_SFH4050_HEAT")
      (libsource (lib "eagle-import") (part "LEDLED_SFH4050_HEAT"))
    )
    (comp (ref "IR37")
      (value "LEDLED_SFH4050_HEAT")
      (footprint "eagle-import:LED_SFH4050_HEAT")
      (libsource (lib "eagle-import") (part "LEDLED_SFH4050_HEAT"))
    )
    (comp (ref "IR38")
      (value "LEDLED_SFH4050_HEAT")
      (footprint "eagle-import:LED_SFH4050_HEAT")
      (libsource (lib "eagle-import") (part "LEDLED_SFH4050_HEAT"))
    )
    (comp (ref "IR39")
      (value "LEDLED_SFH4050_HEAT")
      (footprint "eagle-import:LED_SFH4050_HEAT")
      (libsource (lib "eagle-import") (part "LEDLED_SFH4050_HEAT"))
    )
    (comp (ref "IR40")
      (value "LEDLED_SFH4050_HEAT")
      (footprint "eagle-import:LED_SFH4050_HEAT")
      (libsource (lib "eagle-import") (part "LEDLED_SFH4050_HEAT"))
    )
    (comp (ref "IR49")
      (value "LEDLED_SFH4050_HEAT")
      (footprint "eagle-import:LED_SFH4050_HEAT")
      (libsource (lib "eagle-import") (part "LEDLED_SFH4050_HEAT"))
    )
    (comp (ref "IR50")
      (value "LEDLED_SFH4050_HEAT")
      (footprint "eagle-import:LED_SFH4050_HEAT")
      (libsource (lib "eagle-import") (part "LEDLED_SFH4050_HEAT"))
    )
    (comp (ref "IR51")
      (value "LEDLED_SFH4050_HEAT")
      (footprint "eagle-import:LED_SFH4050_HEAT")
      (libsource (lib "eagle-import") (part "LEDLED_SFH4050_HEAT"))
    )
    (comp (ref "IR52")
      (value "LEDLED_SFH4050_HEAT")
      (footprint "eagle-import:LED_SFH4050_HEAT")
      (libsource (lib "eagle-import") (part "LEDLED_SFH4050_HEAT"))
    )
    (comp (ref "IR53")
      (value "LEDLED_SFH4050_HEAT")
      (footprint "eagle-import:LED_SFH4050_HEAT")
      (libsource (lib "eagle-import") (part "LEDLED_SFH4050_HEAT"))
    )
    (comp (ref "IR54")
      (value "LEDLED_SFH4050_HEAT")
      (footprint "eagle-import:LED_SFH4050_HEAT")
      (libsource (lib "eagle-import") (part "LEDLED_SFH4050_HEAT"))
    )
    (comp (ref "IR55")
      (value "LEDLED_SFH4050_HEAT")
      (footprint "eagle-import:LED_SFH4050_HEAT")
      (libsource (lib "eagle-import") (part "LEDLED_SFH4050_HEAT"))
    )
    (comp (ref "IR56")
      (value "LEDLED_SFH4050_HEAT")
      (footprint "eagle-import:LED_SFH4050_HEAT")
      (libsource (lib "eagle-import") (part "LEDLED_SFH4050_HEAT"))
    )
    (comp (ref "IR65")
      (value "LEDLED_SFH4050_HEAT")
      (footprint "eagle-import:LED_SFH4050_HEAT")
      (libsource (lib "eagle-import") (part "LEDLED_SFH4050_HEAT"))
    )
    (comp (ref "IR66")
      (value "LEDLED_SFH4050_HEAT")
      (footprint "eagle-import:LED_SFH4050_HEAT")
      (libsource (lib "eagle-import") (part "LEDLED_SFH4050_HEAT"))
    )
    (comp (ref "IR67")
      (value "LEDLED_SFH4050_HEAT")
      (footprint "eagle-import:LED_SFH4050_HEAT")
      (libsource (lib "eagle-import") (part "LEDLED_SFH4050_HEAT"))
    )
    (comp (ref "IR68")
      (value "LEDLED_SFH4050_HEAT")
      (footprint "eagle-import:LED_SFH4050_HEAT")
      (libsource (lib "eagle-import") (part "LEDLED_SFH4050_HEAT"))
    )
    (comp (ref "IR69")
      (value "LEDLED_SFH4050_HEAT")
      (footprint "eagle-import:LED_SFH4050_HEAT")
      (libsource (lib "eagle-import") (part "LEDLED_SFH4050_HEAT"))
    )
    (comp (ref "IR70")
      (value "LEDLED_SFH4050_HEAT")
      (footprint "eagle-import:LED_SFH4050_HEAT")
      (libsource (lib "eagle-import") (part "LEDLED_SFH4050_HEAT"))
    )
    (comp (ref "IR71")
      (value "LEDLED_SFH4050_HEAT")
      (footprint "eagle-import:LED_SFH4050_HEAT")
      (libsource (lib "eagle-import") (part "LEDLED_SFH4050_HEAT"))
    )
    (comp (ref "IR72")
      (value "LEDLED_SFH4050_HEAT")
      (footprint "eagle-import:LED_SFH4050_HEAT")
      (libsource (lib "eagle-import") (part "LEDLED_SFH4050_HEAT"))
    )
    (comp (ref "IR81")
      (value "LEDLED_SFH4050_HEAT")
      (footprint "eagle-import:LED_SFH4050_HEAT")
      (libsource (lib "eagle-import") (part "LEDLED_SFH4050_HEAT"))
    )
    (comp (ref "IR82")
      (value "LEDLED_SFH4050_HEAT")
      (footprint "eagle-import:LED_SFH4050_HEAT")
      (libsource (lib "eagle-import") (part "LEDLED_SFH4050_HEAT"))
    )
    (comp (ref "IR83")
      (value "LEDLED_SFH4050_HEAT")
      (footprint "eagle-import:LED_SFH4050_HEAT")
      (libsource (lib "eagle-import") (part "LEDLED_SFH4050_HEAT"))
    )
    (comp (ref "IR84")
      (value "LEDLED_SFH4050_HEAT")
      (footprint "eagle-import:LED_SFH4050_HEAT")
      (libsource (lib "eagle-import") (part "LEDLED_SFH4050_HEAT"))
    )
    (comp (ref "IR85")
      (value "LEDLED_SFH4050_HEAT")
      (footprint "eagle-import:LED_SFH4050_HEAT")
      (libsource (lib "eagle-import") (part "LEDLED_SFH4050_HEAT"))
    )
    (comp (ref "IR86")
      (value "LEDLED_SFH4050_HEAT")
      (footprint "eagle-import:LED_SFH4050_HEAT")
      (libsource (lib "eagle-import") (part "LEDLED_SFH4050_HEAT"))
    )
    (comp (ref "IR87")
      (value "LEDLED_SFH4050_HEAT")
      (footprint "eagle-import:LED_SFH4050_HEAT")
      (libsource (lib "eagle-import") (part "LEDLED_SFH4050_HEAT"))
    )
    (comp (ref "IR88")
      (value "LEDLED_SFH4050_HEAT")
      (footprint "eagle-import:LED_SFH4050_HEAT")
      (libsource (lib "eagle-import") (part "LEDLED_SFH4050_HEAT"))
    )
    (comp (ref "IR97")
      (value "LEDLED_SFH4050_HEAT")
      (footprint "eagle-import:LED_SFH4050_HEAT")
      (libsource (lib "eagle-import") (part "LEDLED_SFH4050_HEAT"))
    )
    (comp (ref "IR98")
      (value "LEDLED_SFH4050_HEAT")
      (footprint "eagle-import:LED_SFH4050_HEAT")
      (libsource (lib "eagle-import") (part "LEDLED_SFH4050_HEAT"))
    )
    (comp (ref "IR99")
      (value "LEDLED_SFH4050_HEAT")
      (footprint "eagle-import:LED_SFH4050_HEAT")
      (libsource (lib "eagle-import") (part "LEDLED_SFH4050_HEAT"))
    )
    (comp (ref "IR100")
      (value "LEDLED_SFH4050_HEAT")
      (footprint "eagle-import:LED_SFH4050_HEAT")
      (libsource (lib "eagle-import") (part "LEDLED_SFH4050_HEAT"))
    )
    (comp (ref "IR101")
      (value "LEDLED_SFH4050_HEAT")
      (footprint "eagle-import:LED_SFH4050_HEAT")
      (libsource (lib "eagle-import") (part "LEDLED_SFH4050_HEAT"))
    )
    (comp (ref "IR102")
      (value "LEDLED_SFH4050_HEAT")
      (footprint "eagle-import:LED_SFH4050_HEAT")
      (libsource (lib "eagle-import") (part "LEDLED_SFH4050_HEAT"))
    )
    (comp (ref "IR103")
      (value "LEDLED_SFH4050_HEAT")
      (footprint "eagle-import:LED_SFH4050_HEAT")
      (libsource (lib "eagle-import") (part "LEDLED_SFH4050_HEAT"))
    )
    (comp (ref "IR104")
      (value "LEDLED_SFH4050_HEAT")
      (footprint "eagle-import:LED_SFH4050_HEAT")
      (libsource (lib "eagle-import") (part "LEDLED_SFH4050_HEAT"))
    )
    (comp (ref "IR113")
      (value "LEDLED_SFH4050_HEAT")
      (footprint "eagle-import:LED_SFH4050_HEAT")
      (libsource (lib "eagle-import") (part "LEDLED_SFH4050_HEAT"))
    )
    (comp (ref "IR114")
      (value "LEDLED_SFH4050_HEAT")
      (footprint "eagle-import:LED_SFH4050_HEAT")
      (libsource (lib "eagle-import") (part "LEDLED_SFH4050_HEAT"))
    )
    (comp (ref "IR115")
      (value "LEDLED_SFH4050_HEAT")
      (footprint "eagle-import:LED_SFH4050_HEAT")
      (libsource (lib "eagle-import") (part "LEDLED_SFH4050_HEAT"))
    )
    (comp (ref "IR116")
      (value "LEDLED_SFH4050_HEAT")
      (footprint "eagle-import:LED_SFH4050_HEAT")
      (libsource (lib "eagle-import") (part "LEDLED_SFH4050_HEAT"))
    )
    (comp (ref "IR121")
      (value "LEDLED_SFH4050_HEAT")
      (footprint "eagle-import:LED_SFH4050_HEAT")
      (libsource (lib "eagle-import") (part "LEDLED_SFH4050_HEAT"))
    )
    (comp (ref "IR122")
      (value "LEDLED_SFH4050_HEAT")
      (footprint "eagle-import:LED_SFH4050_HEAT")
      (libsource (lib "eagle-import") (part "LEDLED_SFH4050_HEAT"))
    )
    (comp (ref "IR123")
      (value "LEDLED_SFH4050_HEAT")
      (footprint "eagle-import:LED_SFH4050_HEAT")
      (libsource (lib "eagle-import") (part "LEDLED_SFH4050_HEAT"))
    )
    (comp (ref "IR124")
      (value "LEDLED_SFH4050")
      (footprint "eagle-import:LED_SFH4050")
      (libsource (lib "eagle-import") (part "LEDLED_SFH4050"))
    )
    (comp (ref "J1")
      (value "CON3AMP-3-SM-RA-X")
      (footprint "eagle-import:AMP-3-SM-RA-X")
      (libsource (lib "eagle-import") (part "CON3AMP-3-SM-RA-X"))
    )
    (comp (ref "J2")
      (value "POWER_JACK_SHUNTPJ-002")
      (footprint "eagle-import:PJ-002")
      (libsource (lib "eagle-import") (part "POWER_JACK_SHUNTPJ-002"))
    )
    (comp (ref "J3")
      (value "CON3AMP_3_SM")
      (footprint "eagle-import:AMP_3_SM")
      (libsource (lib "eagle-import") (part "CON3AMP_3_SM"))
    )
    (comp (ref "J4")
      (value "CON3TE-3-SM-V")
      (footprint "eagle-import:TE_3_SM-V")
      (libsource (lib "eagle-import") (part "STEVES_HOME_CON3TE-3-SM-V"))
    )
    (comp (ref "J5")
      (value "CON3DF13-3-V-SM")
      (footprint "eagle-import:DF13_3_V_SM")
      (libsource (lib "eagle-import") (part "CON3DF13-3-V-SM"))
    )
    (comp (ref "J6")
      (value "CON3TE-3-SM-V")
      (footprint "eagle-import:TE_3_SM-V")
      (libsource (lib "eagle-import") (part "STEVES_HOME_CON3TE-3-SM-V"))
    )
    (comp (ref "L3")
      (value "68uH/1A")
      (footprint "eagle-import:SRU8043")
      (libsource (lib "eagle-import") (part "INDUCTOR_SMSRU8043"))
    )
    (comp (ref "M1")
      (value "TEESNY3.2_MIN")
      (footprint "eagle-import:TEENSY3.2_MIN_SM")
      (libsource (lib "eagle-import") (part "TEESNY3.2_MIN"))
    )
    (comp (ref "Q7")
      (value "NPN_DUALLFPAK56_BIGHS")
      (footprint "eagle-import:LFPAK56_HS2")
      (libsource (lib "eagle-import") (part "NPN_DUALLFPAK56_BIGHS"))
    )
    (comp (ref "Q8")
      (value "NPN_DUALLFPAK56_BIGHS")
      (footprint "eagle-import:LFPAK56_HS2")
      (libsource (lib "eagle-import") (part "NPN_DUALLFPAK56_BIGHS"))
    )
    (comp (ref "Q9")
      (value "NPN_DUALLFPAK56_BIGHS")
      (footprint "eagle-import:LFPAK56_HS2")
      (libsource (lib "eagle-import") (part "NPN_DUALLFPAK56_BIGHS"))
    )
    (comp (ref "R24")
      (value "4R0")
      (footprint "eagle-import:1812")
      (libsource (lib "eagle-import") (part "RESISTOR-POWER1812"))
    )
    (comp (ref "R25")
      (value "332")
      (footprint "eagle-import:0805S")
      (libsource (lib "eagle-import") (part "RESISTOR_SM0805S"))
    )
    (comp (ref "R26")
      (value "4R0")
      (footprint "eagle-import:1812")
      (libsource (lib "eagle-import") (part "RESISTOR-POWER1812"))
    )
    (comp (ref "R28")
      (value "10K0")
      (footprint "eagle-import:1206S")
      (libsource (lib "eagle-import") (part "RESISTOR_SM1206S"))
    )
    (comp (ref "R29")
      (value "4R0")
      (footprint "eagle-import:1812")
      (libsource (lib "eagle-import") (part "RESISTOR-POWER1812"))
    )
    (comp (ref "R30")
      (value "4R0")
      (footprint "eagle-import:1812")
      (libsource (lib "eagle-import") (part "RESISTOR-POWER1812"))
    )
    (comp (ref "R31")
      (value "10K0")
      (footprint "eagle-import:1206S")
      (libsource (lib "eagle-import") (part "RESISTOR_SM1206S"))
    )
    (comp (ref "R33")
      (value "4R0")
      (footprint "eagle-import:1812")
      (libsource (lib "eagle-import") (part "RESISTOR-POWER1812"))
    )
    (comp (ref "R34")
      (value "10R0")
      (footprint "eagle-import:1206S")
      (libsource (lib "eagle-import") (part "RESISTOR_SM1206S"))
    )
    (comp (ref "R35")
      (value "4R0")
      (footprint "eagle-import:1812")
      (libsource (lib "eagle-import") (part "RESISTOR-POWER1812"))
    )
    (comp (ref "R36")
      (value "10R0")
      (footprint "eagle-import:1206S")
      (libsource (lib "eagle-import") (part "RESISTOR_SM1206S"))
    )
    (comp (ref "R37")
      (value "10R0")
      (footprint "eagle-import:1206S")
      (libsource (lib "eagle-import") (part "RESISTOR_SM1206S"))
    )
    (comp (ref "R39")
      (value "10R0")
      (footprint "eagle-import:1206S")
      (libsource (lib "eagle-import") (part "RESISTOR_SM1206S"))
    )
    (comp (ref "R40")
      (value "10K0")
      (footprint "eagle-import:1206S")
      (libsource (lib "eagle-import") (part "RESISTOR_SM1206S"))
    )
    (comp (ref "R41")
      (value "4.99K")
      (footprint "eagle-import:0805S")
      (libsource (lib "eagle-import") (part "RESISTOR_SM0805S"))
    )
    (comp (ref "R42")
      (value "1R00")
      (footprint "eagle-import:1206S")
      (libsource (lib "eagle-import") (part "RESISTOR_SM1206S"))
    )
    (comp (ref "R62")
      (value "100")
      (footprint "eagle-import:0805S")
      (libsource (lib "eagle-import") (part "RESISTOR_SM0805S"))
    )
    (comp (ref "RGB1")
      (value "LED_RGBRGB_LED")
      (footprint "eagle-import:OVSPRGB_HS_FIXED")
      (libsource (lib "eagle-import") (part "LED_RGBRGB_LED"))
    )
    (comp (ref "RGB2")
      (value "LED_RGBRGB_LED")
      (footprint "eagle-import:OVSPRGB_HS_FIXED")
      (libsource (lib "eagle-import") (part "LED_RGBRGB_LED"))
    )
    (comp (ref "RGB3")
      (value "LED_RGBRGB_LED")
      (footprint "eagle-import:OVSPRGB_HS_FIXED")
      (libsource (lib "eagle-import") (part "LED_RGBRGB_LED"))
    )
    (comp (ref "RGB4")
      (value "LED_RGBRGB_LED")
      (footprint "eagle-import:OVSPRGB_HS_FIXED")
      (libsource (lib "eagle-import") (part "LED_RGBRGB_LED"))
    )
    (comp (ref "RGB9")
      (value "RGB_LED")
      (footprint "eagle-import:OVSPRGB_HS_FIXED")
      (libsource (lib "eagle-import") (part "LED_RGBRGB_LED"))
    )
    (comp (ref "RGB10")
      (value "RGB_LED")
      (footprint "eagle-import:OVSPRGB_HS_FIXED")
      (libsource (lib "eagle-import") (part "LED_RGBRGB_LED"))
    )
    (comp (ref "RGB11")
      (value "LED_RGBRGB_LED")
      (footprint "eagle-import:OVSPRGB_HS_FIXED")
      (libsource (lib "eagle-import") (part "LED_RGBRGB_LED"))
    )
    (comp (ref "RGB12")
      (value "LED_RGBRGB_LED")
      (footprint "eagle-import:OVSPRGB_HS_FIXED")
      (libsource (lib "eagle-import") (part "LED_RGBRGB_LED"))
    )
    (comp (ref "RGB17")
      (value "LED_RGBRGB_LED")
      (footprint "eagle-import:OVSPRGB_HS_FIXED")
      (libsource (lib "eagle-import") (part "LED_RGBRGB_LED"))
    )
    (comp (ref "RGB18")
      (value "LED_RGBRGB_LED")
      (footprint "eagle-import:OVSPRGB_HS_FIXED")
      (libsource (lib "eagle-import") (part "LED_RGBRGB_LED"))
    )
    (comp (ref "RGB19")
      (value "LED_RGBRGB_LED")
      (footprint "eagle-import:OVSPRGB_HS_FIXED")
      (libsource (lib "eagle-import") (part "LED_RGBRGB_LED"))
    )
    (comp (ref "RGB20")
      (value "LED_RGBRGB_LED")
      (footprint "eagle-import:OVSPRGB_HS_FIXED")
      (libsource (lib "eagle-import") (part "LED_RGBRGB_LED"))
    )
    (comp (ref "RGB25")
      (value "LED_RGBRGB_LED")
      (footprint "eagle-import:OVSPRGB_HS_FIXED")
      (libsource (lib "eagle-import") (part "LED_RGBRGB_LED"))
    )
    (comp (ref "RGB26")
      (value "LED_RGBRGB_LED")
      (footprint "eagle-import:OVSPRGB_HS_FIXED")
      (libsource (lib "eagle-import") (part "LED_RGBRGB_LED"))
    )
    (comp (ref "RGB27")
      (value "LED_RGBRGB_LED")
      (footprint "eagle-import:OVSPRGB_HS_FIXED")
      (libsource (lib "eagle-import") (part "LED_RGBRGB_LED"))
    )
    (comp (ref "RGB28")
      (value "LED_RGBRGB_LED")
      (footprint "eagle-import:OVSPRGB_HS_FIXED")
      (libsource (lib "eagle-import") (part "LED_RGBRGB_LED"))
    )
    (comp (ref "SH1")
      (value "JUMPER")
      (footprint "eagle-import:JUMPER")
      (libsource (lib "eagle-import") (part "JUMPER"))
    )
    (comp (ref "SH2")
      (value "JUMPER")
      (footprint "eagle-import:JUMPER")
      (libsource (lib "eagle-import") (part "JUMPER"))
    )
    (comp (ref "U$2")
      (value "FIDUCIAL")
      (footprint "eagle-import:FIDUCIAL_1MM")
      (libsource (lib "eagle-import") (part "FIDUCIAL"))
    )
    (comp (ref "U11")
      (value "741G3157DBVR")
      (footprint "eagle-import:DBV_R-PDSO-G6")
      (libsource (lib "eagle-import") (part "741G3157DBVR"))
    )
    (comp (ref "U12")
      (value "LM26")
      (footprint "eagle-import:SOT23-5")
      (libsource (lib "eagle-import") (part "LM26"))
    )
    (comp (ref "U13")
      (value "AD8613")
      (footprint "eagle-import:SOT23-5")
      (fields (field (name "MF") "ALTERA CORPORATION") (field (name "MPN") "AD8065ARTZ-REEL7"))
      (libsource (lib "eagle-import") (part "AD8065RT"))
    )
    (comp (ref "U14")
      (value "AD8613")
      (footprint "eagle-import:SOT23-5")
      (fields (field (name "MF") "ALTERA CORPORATION") (field (name "MPN") "AD8065ARTZ-REEL7"))
      (libsource (lib "eagle-import") (part "AD8065RT"))
    )
    (comp (ref "U15")
      (value "AD5624R")
      (footprint "eagle-import:MSOP10")
      (libsource (lib "eagle-import") (part "AD56X4R"))
    )
    (comp (ref "U16")
      (value "AD8613")
      (footprint "eagle-import:SOT23-5")
      (fields (field (name "MF") "ALTERA CORPORATION") (field (name "MPN") "AD8065ARTZ-REEL7"))
      (libsource (lib "eagle-import") (part "AD8065RT"))
    )
    (comp (ref "U17")
      (value "AP8802")
      (footprint "eagle-import:SOIC8-EP")
      (libsource (lib "eagle-import") (part "AP8802"))
    )
    (comp (ref "C36")
      (value "6.8")
      (footprint "eagle-import:1210S")
      (libsource (lib "eagle-import") (part "CAPS1210S"))
    )
    (comp (ref "C38")
      (value "0.1")
      (footprint "eagle-import:0603S")
      (libsource (lib "eagle-import") (part "CAPS0603S"))
    )
    (comp (ref "C39")
      (value "0.1")
      (footprint "eagle-import:0603S")
      (libsource (lib "eagle-import") (part "CAPS0603S"))
    )
    (comp (ref "C40")
      (value "0.1")
      (footprint "eagle-import:0603S")
      (libsource (lib "eagle-import") (part "CAPS0603S"))
    )
    (comp (ref "C41")
      (value "6.8")
      (footprint "eagle-import:1210S")
      (libsource (lib "eagle-import") (part "CAPS1210S"))
    )
    (comp (ref "C42")
      (value "0.1")
      (footprint "eagle-import:0603S")
      (libsource (lib "eagle-import") (part "CAPS0603S"))
    )
    (comp (ref "C43")
      (value "6.8")
      (footprint "eagle-import:1210S")
      (libsource (lib "eagle-import") (part "CAPS1210S"))
    )
    (comp (ref "C44")
      (value "0.1")
      (footprint "eagle-import:0603S")
      (libsource (lib "eagle-import") (part "CAPS0603S"))
    )
    (comp (ref "C46")
      (value "10@50")
      (footprint "eagle-import:1210S")
      (libsource (lib "eagle-import") (part "CAPS1210S"))
    )
    (comp (ref "C47")
      (value "2.2@50")
      (footprint "eagle-import:1206S")
      (libsource (lib "eagle-import") (part "CAPS1206S"))
    )
    (comp (ref "D5")
      (value "DLFS240L")
      (footprint "eagle-import:PWRDI-123")
      (libsource (lib "eagle-import") (part "DIODE_SCHOTTKYPWRDI-123"))
    )
    (comp (ref "I4")
      (value "INDUCTOR0805S")
      (footprint "eagle-import:0805S")
      (libsource (lib "eagle-import") (part "INDUCTOR0805S"))
    )
    (comp (ref "IR129")
      (value "LEDLED_SFH4050_A")
      (footprint "eagle-import:LED_SFH4045_HEAT_A")
      (libsource (lib "eagle-import") (part "LEDLED_SFH4050_A"))
    )
    (comp (ref "IR130")
      (value "LEDLED_SFH4050_HEAT")
      (footprint "eagle-import:LED_SFH4050_HEAT")
      (libsource (lib "eagle-import") (part "LEDLED_SFH4050_HEAT"))
    )
    (comp (ref "IR131")
      (value "LEDLED_SFH4050_HEAT")
      (footprint "eagle-import:LED_SFH4050_HEAT")
      (libsource (lib "eagle-import") (part "LEDLED_SFH4050_HEAT"))
    )
    (comp (ref "IR132")
      (value "LEDLED_SFH4050_HEAT")
      (footprint "eagle-import:LED_SFH4050_HEAT")
      (libsource (lib "eagle-import") (part "LEDLED_SFH4050_HEAT"))
    )
    (comp (ref "IR133")
      (value "LEDLED_SFH4050_HEAT")
      (footprint "eagle-import:LED_SFH4050_HEAT")
      (libsource (lib "eagle-import") (part "LEDLED_SFH4050_HEAT"))
    )
    (comp (ref "IR134")
      (value "LEDLED_SFH4050_HEAT")
      (footprint "eagle-import:LED_SFH4050_HEAT")
      (libsource (lib "eagle-import") (part "LEDLED_SFH4050_HEAT"))
    )
    (comp (ref "IR135")
      (value "LEDLED_SFH4050_HEAT")
      (footprint "eagle-import:LED_SFH4050_HEAT")
      (libsource (lib "eagle-import") (part "LEDLED_SFH4050_HEAT"))
    )
    (comp (ref "IR136")
      (value "LEDLED_SFH4050")
      (footprint "eagle-import:LED_SFH4050")
      (libsource (lib "eagle-import") (part "LEDLED_SFH4050"))
    )
    (comp (ref "IR145")
      (value "LEDLED_SFH4050_HEAT")
      (footprint "eagle-import:LED_SFH4050_HEAT")
      (libsource (lib "eagle-import") (part "LEDLED_SFH4050_HEAT"))
    )
    (comp (ref "IR146")
      (value "LEDLED_SFH4050_HEAT")
      (footprint "eagle-import:LED_SFH4050_HEAT")
      (libsource (lib "eagle-import") (part "LEDLED_SFH4050_HEAT"))
    )
    (comp (ref "IR147")
      (value "LEDLED_SFH4050_HEAT")
      (footprint "eagle-import:LED_SFH4050_HEAT")
      (libsource (lib "eagle-import") (part "LEDLED_SFH4050_HEAT"))
    )
    (comp (ref "IR148")
      (value "LEDLED_SFH4050_HEAT")
      (footprint "eagle-import:LED_SFH4050_HEAT")
      (libsource (lib "eagle-import") (part "LEDLED_SFH4050_HEAT"))
    )
    (comp (ref "IR149")
      (value "LEDLED_SFH4050_HEAT")
      (footprint "eagle-import:LED_SFH4050_HEAT")
      (libsource (lib "eagle-import") (part "LEDLED_SFH4050_HEAT"))
    )
    (comp (ref "IR150")
      (value "LEDLED_SFH4050_HEAT")
      (footprint "eagle-import:LED_SFH4050_HEAT")
      (libsource (lib "eagle-import") (part "LEDLED_SFH4050_HEAT"))
    )
    (comp (ref "IR151")
      (value "LEDLED_SFH4050_HEAT")
      (footprint "eagle-import:LED_SFH4050_HEAT")
      (libsource (lib "eagle-import") (part "LEDLED_SFH4050_HEAT"))
    )
    (comp (ref "IR152")
      (value "LEDLED_SFH4050_HEAT")
      (footprint "eagle-import:LED_SFH4050_HEAT")
      (libsource (lib "eagle-import") (part "LEDLED_SFH4050_HEAT"))
    )
    (comp (ref "IR161")
      (value "LEDLED_SFH4050_HEAT")
      (footprint "eagle-import:LED_SFH4050_HEAT")
      (libsource (lib "eagle-import") (part "LEDLED_SFH4050_HEAT"))
    )
    (comp (ref "IR162")
      (value "LEDLED_SFH4050_HEAT")
      (footprint "eagle-import:LED_SFH4050_HEAT")
      (libsource (lib "eagle-import") (part "LEDLED_SFH4050_HEAT"))
    )
    (comp (ref "IR163")
      (value "LEDLED_SFH4050_HEAT")
      (footprint "eagle-import:LED_SFH4050_HEAT")
      (libsource (lib "eagle-import") (part "LEDLED_SFH4050_HEAT"))
    )
    (comp (ref "IR164")
      (value "LEDLED_SFH4050_HEAT")
      (footprint "eagle-import:LED_SFH4050_HEAT")
      (libsource (lib "eagle-import") (part "LEDLED_SFH4050_HEAT"))
    )
    (comp (ref "IR165")
      (value "LEDLED_SFH4050_HEAT")
      (footprint "eagle-import:LED_SFH4050_HEAT")
      (libsource (lib "eagle-import") (part "LEDLED_SFH4050_HEAT"))
    )
    (comp (ref "IR166")
      (value "LEDLED_SFH4050_HEAT")
      (footprint "eagle-import:LED_SFH4050_HEAT")
      (libsource (lib "eagle-import") (part "LEDLED_SFH4050_HEAT"))
    )
    (comp (ref "IR167")
      (value "LEDLED_SFH4050_HEAT")
      (footprint "eagle-import:LED_SFH4050_HEAT")
      (libsource (lib "eagle-import") (part "LEDLED_SFH4050_HEAT"))
    )
    (comp (ref "IR168")
      (value "LEDLED_SFH4050_HEAT")
      (footprint "eagle-import:LED_SFH4050_HEAT")
      (libsource (lib "eagle-import") (part "LEDLED_SFH4050_HEAT"))
    )
    (comp (ref "IR177")
      (value "LEDLED_SFH4050_HEAT")
      (footprint "eagle-import:LED_SFH4050_HEAT")
      (libsource (lib "eagle-import") (part "LEDLED_SFH4050_HEAT"))
    )
    (comp (ref "IR178")
      (value "LEDLED_SFH4050_HEAT")
      (footprint "eagle-import:LED_SFH4050_HEAT")
      (libsource (lib "eagle-import") (part "LEDLED_SFH4050_HEAT"))
    )
    (comp (ref "IR179")
      (value "LEDLED_SFH4050_HEAT")
      (footprint "eagle-import:LED_SFH4050_HEAT")
      (libsource (lib "eagle-import") (part "LEDLED_SFH4050_HEAT"))
    )
    (comp (ref "IR180")
      (value "LEDLED_SFH4050_HEAT")
      (footprint "eagle-import:LED_SFH4050_HEAT")
      (libsource (lib "eagle-import") (part "LEDLED_SFH4050_HEAT"))
    )
    (comp (ref "IR181")
      (value "LEDLED_SFH4050_HEAT")
      (footprint "eagle-import:LED_SFH4050_HEAT")
      (libsource (lib "eagle-import") (part "LEDLED_SFH4050_HEAT"))
    )
    (comp (ref "IR182")
      (value "LEDLED_SFH4050_HEAT")
      (footprint "eagle-import:LED_SFH4050_HEAT")
      (libsource (lib "eagle-import") (part "LEDLED_SFH4050_HEAT"))
    )
    (comp (ref "IR183")
      (value "LEDLED_SFH4050_HEAT")
      (footprint "eagle-import:LED_SFH4050_HEAT")
      (libsource (lib "eagle-import") (part "LEDLED_SFH4050_HEAT"))
    )
    (comp (ref "IR184")
      (value "LEDLED_SFH4050_HEAT")
      (footprint "eagle-import:LED_SFH4050_HEAT")
      (libsource (lib "eagle-import") (part "LEDLED_SFH4050_HEAT"))
    )
    (comp (ref "IR193")
      (value "LEDLED_SFH4050_HEAT")
      (footprint "eagle-import:LED_SFH4050_HEAT")
      (libsource (lib "eagle-import") (part "LEDLED_SFH4050_HEAT"))
    )
    (comp (ref "IR194")
      (value "LEDLED_SFH4050_HEAT")
      (footprint "eagle-import:LED_SFH4050_HEAT")
      (libsource (lib "eagle-import") (part "LEDLED_SFH4050_HEAT"))
    )
    (comp (ref "IR195")
      (value "LEDLED_SFH4050_HEAT")
      (footprint "eagle-import:LED_SFH4050_HEAT")
      (libsource (lib "eagle-import") (part "LEDLED_SFH4050_HEAT"))
    )
    (comp (ref "IR196")
      (value "LEDLED_SFH4050_HEAT")
      (footprint "eagle-import:LED_SFH4050_HEAT")
      (libsource (lib "eagle-import") (part "LEDLED_SFH4050_HEAT"))
    )
    (comp (ref "IR197")
      (value "LEDLED_SFH4050_HEAT")
      (footprint "eagle-import:LED_SFH4050_HEAT")
      (libsource (lib "eagle-import") (part "LEDLED_SFH4050_HEAT"))
    )
    (comp (ref "IR198")
      (value "LEDLED_SFH4050_HEAT")
      (footprint "eagle-import:LED_SFH4050_HEAT")
      (libsource (lib "eagle-import") (part "LEDLED_SFH4050_HEAT"))
    )
    (comp (ref "IR199")
      (value "LEDLED_SFH4050_HEAT")
      (footprint "eagle-import:LED_SFH4050_HEAT")
      (libsource (lib "eagle-import") (part "LEDLED_SFH4050_HEAT"))
    )
    (comp (ref "IR200")
      (value "LEDLED_SFH4050_HEAT")
      (footprint "eagle-import:LED_SFH4050_HEAT")
      (libsource (lib "eagle-import") (part "LEDLED_SFH4050_HEAT"))
    )
    (comp (ref "IR209")
      (value "LEDLED_SFH4050_HEAT")
      (footprint "eagle-import:LED_SFH4050_HEAT")
      (libsource (lib "eagle-import") (part "LEDLED_SFH4050_HEAT"))
    )
    (comp (ref "IR210")
      (value "LEDLED_SFH4050_HEAT")
      (footprint "eagle-import:LED_SFH4050_HEAT")
      (libsource (lib "eagle-import") (part "LEDLED_SFH4050_HEAT"))
    )
    (comp (ref "IR211")
      (value "LEDLED_SFH4050_HEAT")
      (footprint "eagle-import:LED_SFH4050_HEAT")
      (libsource (lib "eagle-import") (part "LEDLED_SFH4050_HEAT"))
    )
    (comp (ref "IR212")
      (value "LEDLED_SFH4050_HEAT")
      (footprint "eagle-import:LED_SFH4050_HEAT")
      (libsource (lib "eagle-import") (part "LEDLED_SFH4050_HEAT"))
    )
    (comp (ref "IR213")
      (value "LEDLED_SFH4050_HEAT")
      (footprint "eagle-import:LED_SFH4050_HEAT")
      (libsource (lib "eagle-import") (part "LEDLED_SFH4050_HEAT"))
    )
    (comp (ref "IR214")
      (value "LEDLED_SFH4050_HEAT")
      (footprint "eagle-import:LED_SFH4050_HEAT")
      (libsource (lib "eagle-import") (part "LEDLED_SFH4050_HEAT"))
    )
    (comp (ref "IR215")
      (value "LEDLED_SFH4050_HEAT")
      (footprint "eagle-import:LED_SFH4050_HEAT")
      (libsource (lib "eagle-import") (part "LEDLED_SFH4050_HEAT"))
    )
    (comp (ref "IR216")
      (value "LEDLED_SFH4050_HEAT")
      (footprint "eagle-import:LED_SFH4050_HEAT")
      (libsource (lib "eagle-import") (part "LEDLED_SFH4050_HEAT"))
    )
    (comp (ref "IR224")
      (value "LEDLED_SFH4050_HEAT")
      (footprint "eagle-import:LED_SFH4050_HEAT")
      (libsource (lib "eagle-import") (part "LEDLED_SFH4050_HEAT"))
    )
    (comp (ref "IR225")
      (value "LEDLED_SFH4050_HEAT")
      (footprint "eagle-import:LED_SFH4050_HEAT")
      (libsource (lib "eagle-import") (part "LEDLED_SFH4050_HEAT"))
    )
    (comp (ref "IR226")
      (value "LEDLED_SFH4050_HEAT")
      (footprint "eagle-import:LED_SFH4050_HEAT")
      (libsource (lib "eagle-import") (part "LEDLED_SFH4050_HEAT"))
    )
    (comp (ref "IR227")
      (value "LEDLED_SFH4050_HEAT")
      (footprint "eagle-import:LED_SFH4050_HEAT")
      (libsource (lib "eagle-import") (part "LEDLED_SFH4050_HEAT"))
    )
    (comp (ref "IR228")
      (value "LEDLED_SFH4050_HEAT")
      (footprint "eagle-import:LED_SFH4050_HEAT")
      (libsource (lib "eagle-import") (part "LEDLED_SFH4050_HEAT"))
    )
    (comp (ref "IR229")
      (value "LEDLED_SFH4050_HEAT")
      (footprint "eagle-import:LED_SFH4050_HEAT")
      (libsource (lib "eagle-import") (part "LEDLED_SFH4050_HEAT"))
    )
    (comp (ref "IR230")
      (value "LEDLED_SFH4050_HEAT")
      (footprint "eagle-import:LED_SFH4050_HEAT")
      (libsource (lib "eagle-import") (part "LEDLED_SFH4050_HEAT"))
    )
    (comp (ref "IR231")
      (value "LEDLED_SFH4050_HEAT")
      (footprint "eagle-import:LED_SFH4050_HEAT")
      (libsource (lib "eagle-import") (part "LEDLED_SFH4050_HEAT"))
    )
    (comp (ref "IR240")
      (value "LEDLED_SFH4050_HEAT")
      (footprint "eagle-import:LED_SFH4050_HEAT")
      (libsource (lib "eagle-import") (part "LEDLED_SFH4050_HEAT"))
    )
    (comp (ref "IR241")
      (value "LEDLED_SFH4050_HEAT")
      (footprint "eagle-import:LED_SFH4050_HEAT")
      (libsource (lib "eagle-import") (part "LEDLED_SFH4050_HEAT"))
    )
    (comp (ref "IR242")
      (value "LEDLED_SFH4050_HEAT")
      (footprint "eagle-import:LED_SFH4050_HEAT")
      (libsource (lib "eagle-import") (part "LEDLED_SFH4050_HEAT"))
    )
    (comp (ref "IR243")
      (value "LEDLED_SFH4050_HEAT")
      (footprint "eagle-import:LED_SFH4050_HEAT")
      (libsource (lib "eagle-import") (part "LEDLED_SFH4050_HEAT"))
    )
    (comp (ref "IR248")
      (value "LEDLED_SFH4050_HEAT")
      (footprint "eagle-import:LED_SFH4050_HEAT")
      (libsource (lib "eagle-import") (part "LEDLED_SFH4050_HEAT"))
    )
    (comp (ref "IR249")
      (value "LEDLED_SFH4050_HEAT")
      (footprint "eagle-import:LED_SFH4050_HEAT")
      (libsource (lib "eagle-import") (part "LEDLED_SFH4050_HEAT"))
    )
    (comp (ref "IR250")
      (value "LEDLED_SFH4050_HEAT")
      (footprint "eagle-import:LED_SFH4050_HEAT")
      (libsource (lib "eagle-import") (part "LEDLED_SFH4050_HEAT"))
    )
    (comp (ref "IR251")
      (value "LEDLED_SFH4050")
      (footprint "eagle-import:LED_SFH4050")
      (libsource (lib "eagle-import") (part "LEDLED_SFH4050"))
    )
    (comp (ref "L4")
      (value "68uH/1A")
      (footprint "eagle-import:SRU8043")
      (libsource (lib "eagle-import") (part "INDUCTOR_SMSRU8043"))
    )
    (comp (ref "Q10")
      (value "NPN_DUALLFPAK56_BIGHS")
      (footprint "eagle-import:LFPAK56_HS2")
      (libsource (lib "eagle-import") (part "NPN_DUALLFPAK56_BIGHS"))
    )
    (comp (ref "Q11")
      (value "NPN_DUALLFPAK56_BIGHS")
      (footprint "eagle-import:LFPAK56_HS2")
      (libsource (lib "eagle-import") (part "NPN_DUALLFPAK56_BIGHS"))
    )
    (comp (ref "Q12")
      (value "NPN_DUALLFPAK56_BIGHS")
      (footprint "eagle-import:LFPAK56_HS2")
      (libsource (lib "eagle-import") (part "NPN_DUALLFPAK56_BIGHS"))
    )
    (comp (ref "R43")
      (value "4R0")
      (footprint "eagle-import:1812")
      (libsource (lib "eagle-import") (part "RESISTOR-POWER1812"))
    )
    (comp (ref "R44")
      (value "4R0")
      (footprint "eagle-import:1812")
      (libsource (lib "eagle-import") (part "RESISTOR-POWER1812"))
    )
    (comp (ref "R46")
      (value "10K0")
      (footprint "eagle-import:1206S")
      (libsource (lib "eagle-import") (part "RESISTOR_SM1206S"))
    )
    (comp (ref "R48")
      (value "4R0")
      (footprint "eagle-import:1812")
      (libsource (lib "eagle-import") (part "RESISTOR-POWER1812"))
    )
    (comp (ref "R49")
      (value "4R0")
      (footprint "eagle-import:1812")
      (libsource (lib "eagle-import") (part "RESISTOR-POWER1812"))
    )
    (comp (ref "R50")
      (value "10K0")
      (footprint "eagle-import:1206S")
      (libsource (lib "eagle-import") (part "RESISTOR_SM1206S"))
    )
    (comp (ref "R53")
      (value "4R0")
      (footprint "eagle-import:1812")
      (libsource (lib "eagle-import") (part "RESISTOR-POWER1812"))
    )
    (comp (ref "R54")
      (value "10R0")
      (footprint "eagle-import:1206S")
      (libsource (lib "eagle-import") (part "RESISTOR_SM1206S"))
    )
    (comp (ref "R55")
      (value "10R0")
      (footprint "eagle-import:1206S")
      (libsource (lib "eagle-import") (part "RESISTOR_SM1206S"))
    )
    (comp (ref "R56")
      (value "10R0")
      (footprint "eagle-import:1206S")
      (libsource (lib "eagle-import") (part "RESISTOR_SM1206S"))
    )
    (comp (ref "R57")
      (value "4R0")
      (footprint "eagle-import:1812")
      (libsource (lib "eagle-import") (part "RESISTOR-POWER1812"))
    )
    (comp (ref "R58")
      (value "10R0")
      (footprint "eagle-import:1206S")
      (libsource (lib "eagle-import") (part "RESISTOR_SM1206S"))
    )
    (comp (ref "R59")
      (value "10K0")
      (footprint "eagle-import:1206S")
      (libsource (lib "eagle-import") (part "RESISTOR_SM1206S"))
    )
    (comp (ref "R60")
      (value "4.99K")
      (footprint "eagle-import:0805S")
      (libsource (lib "eagle-import") (part "RESISTOR_SM0805S"))
    )
    (comp (ref "R61")
      (value "1R00")
      (footprint "eagle-import:1206S")
      (libsource (lib "eagle-import") (part "RESISTOR_SM1206S"))
    )
    (comp (ref "RGB33")
      (value "LED_RGBRGB_LED")
      (footprint "eagle-import:OVSPRGB_HS_FIXED")
      (libsource (lib "eagle-import") (part "LED_RGBRGB_LED"))
    )
    (comp (ref "RGB34")
      (value "LED_RGBRGB_LED")
      (footprint "eagle-import:OVSPRGB_HS_FIXED")
      (libsource (lib "eagle-import") (part "LED_RGBRGB_LED"))
    )
    (comp (ref "RGB35")
      (value "LED_RGBRGB_LED")
      (footprint "eagle-import:OVSPRGB_HS_FIXED")
      (libsource (lib "eagle-import") (part "LED_RGBRGB_LED"))
    )
    (comp (ref "RGB36")
      (value "LED_RGBRGB_LED")
      (footprint "eagle-import:OVSPRGB_HS_FIXED")
      (libsource (lib "eagle-import") (part "LED_RGBRGB_LED"))
    )
    (comp (ref "RGB41")
      (value "LED_RGBRGB_LED")
      (footprint "eagle-import:OVSPRGB_HS_FIXED")
      (libsource (lib "eagle-import") (part "LED_RGBRGB_LED"))
    )
    (comp (ref "RGB42")
      (value "LED_RGBRGB_LED")
      (footprint "eagle-import:OVSPRGB_HS_FIXED")
      (libsource (lib "eagle-import") (part "LED_RGBRGB_LED"))
    )
    (comp (ref "RGB43")
      (value "LED_RGBRGB_LED")
      (footprint "eagle-import:OVSPRGB_HS_FIXED")
      (libsource (lib "eagle-import") (part "LED_RGBRGB_LED"))
    )
    (comp (ref "RGB44")
      (value "LED_RGBRGB_LED")
      (footprint "eagle-import:OVSPRGB_HS_FIXED")
      (libsource (lib "eagle-import") (part "LED_RGBRGB_LED"))
    )
    (comp (ref "RGB49")
      (value "LED_RGBRGB_LED")
      (footprint "eagle-import:OVSPRGB_HS_FIXED")
      (libsource (lib "eagle-import") (part "LED_RGBRGB_LED"))
    )
    (comp (ref "RGB50")
      (value "LED_RGBRGB_LED")
      (footprint "eagle-import:OVSPRGB_HS_FIXED")
      (libsource (lib "eagle-import") (part "LED_RGBRGB_LED"))
    )
    (comp (ref "RGB51")
      (value "LED_RGBRGB_LED")
      (footprint "eagle-import:OVSPRGB_HS_FIXED")
      (libsource (lib "eagle-import") (part "LED_RGBRGB_LED"))
    )
    (comp (ref "RGB52")
      (value "LED_RGBRGB_LED")
      (footprint "eagle-import:OVSPRGB_HS_FIXED")
      (libsource (lib "eagle-import") (part "LED_RGBRGB_LED"))
    )
    (comp (ref "RGB57")
      (value "LED_RGBRGB_LED")
      (footprint "eagle-import:OVSPRGB_HS_FIXED")
      (libsource (lib "eagle-import") (part "LED_RGBRGB_LED"))
    )
    (comp (ref "RGB58")
      (value "LED_RGBRGB_LED")
      (footprint "eagle-import:OVSPRGB_HS_FIXED")
      (libsource (lib "eagle-import") (part "LED_RGBRGB_LED"))
    )
    (comp (ref "RGB59")
      (value "LED_RGBRGB_LED")
      (footprint "eagle-import:OVSPRGB_HS_FIXED")
      (libsource (lib "eagle-import") (part "LED_RGBRGB_LED"))
    )
    (comp (ref "RGB60")
      (value "LED_RGBRGB_LED")
      (footprint "eagle-import:OVSPRGB_HS_FIXED")
      (libsource (lib "eagle-import") (part "LED_RGBRGB_LED"))
    )
    (comp (ref "U18")
      (value "AD8613")
      (footprint "eagle-import:SOT23-5")
      (fields (field (name "MF") "ALTERA CORPORATION") (field (name "MPN") "AD8065ARTZ-REEL7"))
      (libsource (lib "eagle-import") (part "AD8065RT"))
    )
    (comp (ref "U19")
      (value "AD5624")
      (footprint "eagle-import:MSOP10")
      (libsource (lib "eagle-import") (part "AD56X4R"))
    )
    (comp (ref "U20")
      (value "AD8613")
      (footprint "eagle-import:SOT23-5")
      (fields (field (name "MF") "ALTERA CORPORATION") (field (name "MPN") "AD8065ARTZ-REEL7"))
      (libsource (lib "eagle-import") (part "AD8065RT"))
    )
    (comp (ref "U21")
      (value "AD8613")
      (footprint "eagle-import:SOT23-5")
      (fields (field (name "MF") "ALTERA CORPORATION") (field (name "MPN") "AD8065ARTZ-REEL7"))
      (libsource (lib "eagle-import") (part "AD8065RT"))
    )
    (comp (ref "U22")
      (value "AP8802")
      (footprint "eagle-import:SOIC8-EP")
      (libsource (lib "eagle-import") (part "AP8802"))
    )
    (comp (ref "C1")
      (value "6.8")
      (footprint "eagle-import:1210S")
      (libsource (lib "eagle-import") (part "CAPS1210S"))
    )
    (comp (ref "C2")
      (value "6.8")
      (footprint "eagle-import:1210S")
      (libsource (lib "eagle-import") (part "CAPS1210S"))
    )
    (comp (ref "C7")
      (value "0.1")
      (footprint "eagle-import:0603S")
      (libsource (lib "eagle-import") (part "CAPS0603S"))
    )
    (comp (ref "C9")
      (value "0.1")
      (footprint "eagle-import:0603S")
      (libsource (lib "eagle-import") (part "CAPS0603S"))
    )
    (comp (ref "C10")
      (value "0.1")
      (footprint "eagle-import:0603S")
      (libsource (lib "eagle-import") (part "CAPS0603S"))
    )
    (comp (ref "C11")
      (value "10@50")
      (footprint "eagle-import:1210S")
      (libsource (lib "eagle-import") (part "CAPS1210S"))
    )
    (comp (ref "C12")
      (value "6.8")
      (footprint "eagle-import:1210S")
      (libsource (lib "eagle-import") (part "CAPS1210S"))
    )
    (comp (ref "C20")
      (value "0.1")
      (footprint "eagle-import:0603S")
      (libsource (lib "eagle-import") (part "CAPS0603S"))
    )
    (comp (ref "C21")
      (value "0.1")
      (footprint "eagle-import:0603S")
      (libsource (lib "eagle-import") (part "CAPS0603S"))
    )
    (comp (ref "C22")
      (value "2.2@50")
      (footprint "eagle-import:1206S")
      (libsource (lib "eagle-import") (part "CAPS1206S"))
    )
    (comp (ref "D2")
      (value "DLFS240L")
      (footprint "eagle-import:PWRDI-123")
      (libsource (lib "eagle-import") (part "DIODE_SCHOTTKYPWRDI-123"))
    )
    (comp (ref "I1")
      (value "INDUCTOR0805S")
      (footprint "eagle-import:0805S")
      (libsource (lib "eagle-import") (part "INDUCTOR0805S"))
    )
    (comp (ref "IR9")
      (value "LEDLED_SFH4050_HEAT")
      (footprint "eagle-import:LED_SFH4050_HEAT")
      (libsource (lib "eagle-import") (part "LEDLED_SFH4050_HEAT"))
    )
    (comp (ref "IR10")
      (value "LEDLED_SFH4050_HEAT")
      (footprint "eagle-import:LED_SFH4050_HEAT")
      (libsource (lib "eagle-import") (part "LEDLED_SFH4050_HEAT"))
    )
    (comp (ref "IR11")
      (value "LEDLED_SFH4050_HEAT")
      (footprint "eagle-import:LED_SFH4050_HEAT")
      (libsource (lib "eagle-import") (part "LEDLED_SFH4050_HEAT"))
    )
    (comp (ref "IR12")
      (value "LEDLED_SFH4050_HEAT")
      (footprint "eagle-import:LED_SFH4050_HEAT")
      (libsource (lib "eagle-import") (part "LEDLED_SFH4050_HEAT"))
    )
    (comp (ref "IR13")
      (value "LEDLED_SFH4050_HEAT")
      (footprint "eagle-import:LED_SFH4050_HEAT")
      (libsource (lib "eagle-import") (part "LEDLED_SFH4050_HEAT"))
    )
    (comp (ref "IR14")
      (value "LEDLED_SFH4050_HEAT")
      (footprint "eagle-import:LED_SFH4050_HEAT")
      (libsource (lib "eagle-import") (part "LEDLED_SFH4050_HEAT"))
    )
    (comp (ref "IR15")
      (value "LEDLED_SFH4050_HEAT")
      (footprint "eagle-import:LED_SFH4050_HEAT")
      (libsource (lib "eagle-import") (part "LEDLED_SFH4050_HEAT"))
    )
    (comp (ref "IR16")
      (value "LEDLED_SFH4050_HEAT")
      (footprint "eagle-import:LED_SFH4050_HEAT")
      (libsource (lib "eagle-import") (part "LEDLED_SFH4050_HEAT"))
    )
    (comp (ref "IR25")
      (value "LEDLED_SFH4050_HEAT")
      (footprint "eagle-import:LED_SFH4050_HEAT")
      (libsource (lib "eagle-import") (part "LEDLED_SFH4050_HEAT"))
    )
    (comp (ref "IR26")
      (value "LEDLED_SFH4050_HEAT")
      (footprint "eagle-import:LED_SFH4050_HEAT")
      (libsource (lib "eagle-import") (part "LEDLED_SFH4050_HEAT"))
    )
    (comp (ref "IR27")
      (value "LEDLED_SFH4050_HEAT")
      (footprint "eagle-import:LED_SFH4050_HEAT")
      (libsource (lib "eagle-import") (part "LEDLED_SFH4050_HEAT"))
    )
    (comp (ref "IR28")
      (value "LEDLED_SFH4050_HEAT")
      (footprint "eagle-import:LED_SFH4050_HEAT")
      (libsource (lib "eagle-import") (part "LEDLED_SFH4050_HEAT"))
    )
    (comp (ref "IR29")
      (value "LEDLED_SFH4050_HEAT")
      (footprint "eagle-import:LED_SFH4050_HEAT")
      (libsource (lib "eagle-import") (part "LEDLED_SFH4050_HEAT"))
    )
    (comp (ref "IR30")
      (value "LEDLED_SFH4050_HEAT")
      (footprint "eagle-import:LED_SFH4050_HEAT")
      (libsource (lib "eagle-import") (part "LEDLED_SFH4050_HEAT"))
    )
    (comp (ref "IR31")
      (value "LEDLED_SFH4050_HEAT")
      (footprint "eagle-import:LED_SFH4050_HEAT")
      (libsource (lib "eagle-import") (part "LEDLED_SFH4050_HEAT"))
    )
    (comp (ref "IR32")
      (value "LEDLED_SFH4050_HEAT")
      (footprint "eagle-import:LED_SFH4050_HEAT")
      (libsource (lib "eagle-import") (part "LEDLED_SFH4050_HEAT"))
    )
    (comp (ref "IR41")
      (value "LEDLED_SFH4050_HEAT")
      (footprint "eagle-import:LED_SFH4050_HEAT")
      (libsource (lib "eagle-import") (part "LEDLED_SFH4050_HEAT"))
    )
    (comp (ref "IR42")
      (value "LEDLED_SFH4050_HEAT")
      (footprint "eagle-import:LED_SFH4050_HEAT")
      (libsource (lib "eagle-import") (part "LEDLED_SFH4050_HEAT"))
    )
    (comp (ref "IR43")
      (value "LEDLED_SFH4050_HEAT")
      (footprint "eagle-import:LED_SFH4050_HEAT")
      (libsource (lib "eagle-import") (part "LEDLED_SFH4050_HEAT"))
    )
    (comp (ref "IR44")
      (value "LEDLED_SFH4050_HEAT")
      (footprint "eagle-import:LED_SFH4050_HEAT")
      (libsource (lib "eagle-import") (part "LEDLED_SFH4050_HEAT"))
    )
    (comp (ref "IR45")
      (value "LEDLED_SFH4050_HEAT")
      (footprint "eagle-import:LED_SFH4050_HEAT")
      (libsource (lib "eagle-import") (part "LEDLED_SFH4050_HEAT"))
    )
    (comp (ref "IR46")
      (value "LEDLED_SFH4050_HEAT")
      (footprint "eagle-import:LED_SFH4050_HEAT")
      (libsource (lib "eagle-import") (part "LEDLED_SFH4050_HEAT"))
    )
    (comp (ref "IR47")
      (value "LEDLED_SFH4050_HEAT")
      (footprint "eagle-import:LED_SFH4050_HEAT")
      (libsource (lib "eagle-import") (part "LEDLED_SFH4050_HEAT"))
    )
    (comp (ref "IR48")
      (value "LEDLED_SFH4050_HEAT")
      (footprint "eagle-import:LED_SFH4050_HEAT")
      (libsource (lib "eagle-import") (part "LEDLED_SFH4050_HEAT"))
    )
    (comp (ref "IR57")
      (value "LEDLED_SFH4050_HEAT")
      (footprint "eagle-import:LED_SFH4050_HEAT")
      (libsource (lib "eagle-import") (part "LEDLED_SFH4050_HEAT"))
    )
    (comp (ref "IR58")
      (value "LEDLED_SFH4050_HEAT")
      (footprint "eagle-import:LED_SFH4050_HEAT")
      (libsource (lib "eagle-import") (part "LEDLED_SFH4050_HEAT"))
    )
    (comp (ref "IR59")
      (value "LEDLED_SFH4050_HEAT")
      (footprint "eagle-import:LED_SFH4050_HEAT")
      (libsource (lib "eagle-import") (part "LEDLED_SFH4050_HEAT"))
    )
    (comp (ref "IR60")
      (value "LEDLED_SFH4050_HEAT")
      (footprint "eagle-import:LED_SFH4050_HEAT")
      (libsource (lib "eagle-import") (part "LEDLED_SFH4050_HEAT"))
    )
    (comp (ref "IR61")
      (value "LEDLED_SFH4050_HEAT")
      (footprint "eagle-import:LED_SFH4050_HEAT")
      (libsource (lib "eagle-import") (part "LEDLED_SFH4050_HEAT"))
    )
    (comp (ref "IR62")
      (value "LEDLED_SFH4050_HEAT")
      (footprint "eagle-import:LED_SFH4050_HEAT")
      (libsource (lib "eagle-import") (part "LEDLED_SFH4050_HEAT"))
    )
    (comp (ref "IR63")
      (value "LEDLED_SFH4050_HEAT")
      (footprint "eagle-import:LED_SFH4050_HEAT")
      (libsource (lib "eagle-import") (part "LEDLED_SFH4050_HEAT"))
    )
    (comp (ref "IR64")
      (value "LEDLED_SFH4050_HEAT")
      (footprint "eagle-import:LED_SFH4050_HEAT")
      (libsource (lib "eagle-import") (part "LEDLED_SFH4050_HEAT"))
    )
    (comp (ref "IR73")
      (value "LEDLED_SFH4050_HEAT")
      (footprint "eagle-import:LED_SFH4050_HEAT")
      (libsource (lib "eagle-import") (part "LEDLED_SFH4050_HEAT"))
    )
    (comp (ref "IR74")
      (value "LEDLED_SFH4050_HEAT")
      (footprint "eagle-import:LED_SFH4050_HEAT")
      (libsource (lib "eagle-import") (part "LEDLED_SFH4050_HEAT"))
    )
    (comp (ref "IR75")
      (value "LEDLED_SFH4050_HEAT")
      (footprint "eagle-import:LED_SFH4050_HEAT")
      (libsource (lib "eagle-import") (part "LEDLED_SFH4050_HEAT"))
    )
    (comp (ref "IR76")
      (value "LEDLED_SFH4050_HEAT")
      (footprint "eagle-import:LED_SFH4050_HEAT")
      (libsource (lib "eagle-import") (part "LEDLED_SFH4050_HEAT"))
    )
    (comp (ref "IR77")
      (value "LEDLED_SFH4050_HEAT")
      (footprint "eagle-import:LED_SFH4050_HEAT")
      (libsource (lib "eagle-import") (part "LEDLED_SFH4050_HEAT"))
    )
    (comp (ref "IR78")
      (value "LEDLED_SFH4050_HEAT")
      (footprint "eagle-import:LED_SFH4050_HEAT")
      (libsource (lib "eagle-import") (part "LEDLED_SFH4050_HEAT"))
    )
    (comp (ref "IR79")
      (value "LEDLED_SFH4050_HEAT")
      (footprint "eagle-import:LED_SFH4050_HEAT")
      (libsource (lib "eagle-import") (part "LEDLED_SFH4050_HEAT"))
    )
    (comp (ref "IR80")
      (value "LEDLED_SFH4050_HEAT")
      (footprint "eagle-import:LED_SFH4050_HEAT")
      (libsource (lib "eagle-import") (part "LEDLED_SFH4050_HEAT"))
    )
    (comp (ref "IR89")
      (value "LEDLED_SFH4050_HEAT")
      (footprint "eagle-import:LED_SFH4050_HEAT")
      (libsource (lib "eagle-import") (part "LEDLED_SFH4050_HEAT"))
    )
    (comp (ref "IR90")
      (value "LEDLED_SFH4050_HEAT")
      (footprint "eagle-import:LED_SFH4050_HEAT")
      (libsource (lib "eagle-import") (part "LEDLED_SFH4050_HEAT"))
    )
    (comp (ref "IR91")
      (value "LEDLED_SFH4050_HEAT")
      (footprint "eagle-import:LED_SFH4050_HEAT")
      (libsource (lib "eagle-import") (part "LEDLED_SFH4050_HEAT"))
    )
    (comp (ref "IR92")
      (value "LEDLED_SFH4050_HEAT")
      (footprint "eagle-import:LED_SFH4050_HEAT")
      (libsource (lib "eagle-import") (part "LEDLED_SFH4050_HEAT"))
    )
    (comp (ref "IR93")
      (value "LEDLED_SFH4050_HEAT")
      (footprint "eagle-import:LED_SFH4050_HEAT")
      (libsource (lib "eagle-import") (part "LEDLED_SFH4050_HEAT"))
    )
    (comp (ref "IR94")
      (value "LEDLED_SFH4050_HEAT")
      (footprint "eagle-import:LED_SFH4050_HEAT")
      (libsource (lib "eagle-import") (part "LEDLED_SFH4050_HEAT"))
    )
    (comp (ref "IR95")
      (value "LEDLED_SFH4050_HEAT")
      (footprint "eagle-import:LED_SFH4050_HEAT")
      (libsource (lib "eagle-import") (part "LEDLED_SFH4050_HEAT"))
    )
    (comp (ref "IR96")
      (value "LEDLED_SFH4050_HEAT")
      (footprint "eagle-import:LED_SFH4050_HEAT")
      (libsource (lib "eagle-import") (part "LEDLED_SFH4050_HEAT"))
    )
    (comp (ref "IR105")
      (value "LEDLED_SFH4050_HEAT")
      (footprint "eagle-import:LED_SFH4050_HEAT")
      (libsource (lib "eagle-import") (part "LEDLED_SFH4050_HEAT"))
    )
    (comp (ref "IR106")
      (value "LEDLED_SFH4050_C")
      (footprint "eagle-import:LED_SFH4050_HEAT_C")
      (libsource (lib "eagle-import") (part "LEDLED_SFH4050_C"))
    )
    (comp (ref "IR107")
      (value "LEDLED_SFH4050_HEAT")
      (footprint "eagle-import:LED_SFH4050_HEAT")
      (libsource (lib "eagle-import") (part "LEDLED_SFH4050_HEAT"))
    )
    (comp (ref "IR108")
      (value "LEDLED_SFH4050_HEAT")
      (footprint "eagle-import:LED_SFH4050_HEAT")
      (libsource (lib "eagle-import") (part "LEDLED_SFH4050_HEAT"))
    )
    (comp (ref "IR109")
      (value "LEDLED_SFH4050_HEAT")
      (footprint "eagle-import:LED_SFH4050_HEAT")
      (libsource (lib "eagle-import") (part "LEDLED_SFH4050_HEAT"))
    )
    (comp (ref "IR110")
      (value "LEDLED_SFH4050_HEAT")
      (footprint "eagle-import:LED_SFH4050_HEAT")
      (libsource (lib "eagle-import") (part "LEDLED_SFH4050_HEAT"))
    )
    (comp (ref "IR111")
      (value "LEDLED_SFH4050_HEAT")
      (footprint "eagle-import:LED_SFH4050_HEAT")
      (libsource (lib "eagle-import") (part "LEDLED_SFH4050_HEAT"))
    )
    (comp (ref "IR112")
      (value "LEDLED_SFH4050_HEAT")
      (footprint "eagle-import:LED_SFH4050_HEAT")
      (libsource (lib "eagle-import") (part "LEDLED_SFH4050_HEAT"))
    )
    (comp (ref "IR117")
      (value "LEDLED_SFH4050")
      (footprint "eagle-import:LED_SFH4050")
      (libsource (lib "eagle-import") (part "LEDLED_SFH4050"))
    )
    (comp (ref "IR118")
      (value "LEDLED_SFH4050_HEAT")
      (footprint "eagle-import:LED_SFH4050_HEAT")
      (libsource (lib "eagle-import") (part "LEDLED_SFH4050_HEAT"))
    )
    (comp (ref "IR119")
      (value "LEDLED_SFH4050_HEAT")
      (footprint "eagle-import:LED_SFH4050_HEAT")
      (libsource (lib "eagle-import") (part "LEDLED_SFH4050_HEAT"))
    )
    (comp (ref "IR120")
      (value "LEDLED_SFH4050_HEAT")
      (footprint "eagle-import:LED_SFH4050_HEAT")
      (libsource (lib "eagle-import") (part "LEDLED_SFH4050_HEAT"))
    )
    (comp (ref "IR125")
      (value "LEDLED_SFH4050_HEAT")
      (footprint "eagle-import:LED_SFH4050_HEAT")
      (libsource (lib "eagle-import") (part "LEDLED_SFH4050_HEAT"))
    )
    (comp (ref "IR126")
      (value "LEDLED_SFH4050_HEAT")
      (footprint "eagle-import:LED_SFH4050_HEAT")
      (libsource (lib "eagle-import") (part "LEDLED_SFH4050_HEAT"))
    )
    (comp (ref "IR127")
      (value "LEDLED_SFH4050_HEAT")
      (footprint "eagle-import:LED_SFH4050_HEAT")
      (libsource (lib "eagle-import") (part "LEDLED_SFH4050_HEAT"))
    )
    (comp (ref "IR128")
      (value "LEDLED_SFH4050")
      (footprint "eagle-import:LED_SFH4050")
      (libsource (lib "eagle-import") (part "LEDLED_SFH4050"))
    )
    (comp (ref "L2")
      (value "68uH/1A")
      (footprint "eagle-import:SRU8043")
      (libsource (lib "eagle-import") (part "INDUCTOR_SMSRU8043"))
    )
    (comp (ref "Q3")
      (value "NPN_DUALLFPAK56_BIGHS")
      (footprint "eagle-import:LFPAK56_HS2")
      (libsource (lib "eagle-import") (part "NPN_DUALLFPAK56_BIGHS"))
    )
    (comp (ref "Q5")
      (value "NPN_DUALLFPAK56_BIGHS")
      (footprint "eagle-import:LFPAK56_HS2")
      (libsource (lib "eagle-import") (part "NPN_DUALLFPAK56_BIGHS"))
    )
    (comp (ref "Q6")
      (value "NPN_DUALLFPAK56_BIGHS")
      (footprint "eagle-import:LFPAK56_HS2")
      (libsource (lib "eagle-import") (part "NPN_DUALLFPAK56_BIGHS"))
    )
    (comp (ref "R1")
      (value "4R0")
      (footprint "eagle-import:1812")
      (libsource (lib "eagle-import") (part "RESISTOR-POWER1812"))
    )
    (comp (ref "R2")
      (value "4R0")
      (footprint "eagle-import:1812")
      (libsource (lib "eagle-import") (part "RESISTOR-POWER1812"))
    )
    (comp (ref "R9")
      (value "4R0")
      (footprint "eagle-import:1812")
      (libsource (lib "eagle-import") (part "RESISTOR-POWER1812"))
    )
    (comp (ref "R10")
      (value "4R0")
      (footprint "eagle-import:1812")
      (libsource (lib "eagle-import") (part "RESISTOR-POWER1812"))
    )
    (comp (ref "R11")
      (value "4R0")
      (footprint "eagle-import:1812")
      (libsource (lib "eagle-import") (part "RESISTOR-POWER1812"))
    )
    (comp (ref "R12")
      (value "4R0")
      (footprint "eagle-import:1812")
      (libsource (lib "eagle-import") (part "RESISTOR-POWER1812"))
    )
    (comp (ref "R14")
      (value "10K0")
      (footprint "eagle-import:1206S")
      (libsource (lib "eagle-import") (part "RESISTOR_SM1206S"))
    )
    (comp (ref "R17")
      (value "4.99K")
      (footprint "eagle-import:0805S")
      (libsource (lib "eagle-import") (part "RESISTOR_SM0805S"))
    )
    (comp (ref "R18")
      (value "10K0")
      (footprint "eagle-import:1206S")
      (libsource (lib "eagle-import") (part "RESISTOR_SM1206S"))
    )
    (comp (ref "R19")
      (value "10K0")
      (footprint "eagle-import:1206S")
      (libsource (lib "eagle-import") (part "RESISTOR_SM1206S"))
    )
    (comp (ref "R20")
      (value "1R00")
      (footprint "eagle-import:1206S")
      (libsource (lib "eagle-import") (part "RESISTOR_SM1206S"))
    )
    (comp (ref "R23")
      (value "10R0")
      (footprint "eagle-import:1206S")
      (libsource (lib "eagle-import") (part "RESISTOR_SM1206S"))
    )
    (comp (ref "R27")
      (value "10R0")
      (footprint "eagle-import:1206S")
      (libsource (lib "eagle-import") (part "RESISTOR_SM1206S"))
    )
    (comp (ref "R32")
      (value "10R0")
      (footprint "eagle-import:1206S")
      (libsource (lib "eagle-import") (part "RESISTOR_SM1206S"))
    )
    (comp (ref "R38")
      (value "10R0")
      (footprint "eagle-import:1206S")
      (libsource (lib "eagle-import") (part "RESISTOR_SM1206S"))
    )
    (comp (ref "RGB5")
      (value "LED_RGBRGB_LED")
      (footprint "eagle-import:OVSPRGB_HS_FIXED")
      (libsource (lib "eagle-import") (part "LED_RGBRGB_LED"))
    )
    (comp (ref "RGB6")
      (value "LED_RGBRGB_LED")
      (footprint "eagle-import:OVSPRGB_HS_FIXED")
      (libsource (lib "eagle-import") (part "LED_RGBRGB_LED"))
    )
    (comp (ref "RGB7")
      (value "LED_RGBRGB_LED")
      (footprint "eagle-import:OVSPRGB_HS_FIXED")
      (libsource (lib "eagle-import") (part "LED_RGBRGB_LED"))
    )
    (comp (ref "RGB8")
      (value "LED_RGBRGB_LED")
      (footprint "eagle-import:OVSPRGB_HS_FIXED")
      (libsource (lib "eagle-import") (part "LED_RGBRGB_LED"))
    )
    (comp (ref "RGB13")
      (value "LED_RGBRGB_LED")
      (footprint "eagle-import:OVSPRGB_HS_FIXED")
      (libsource (lib "eagle-import") (part "LED_RGBRGB_LED"))
    )
    (comp (ref "RGB14")
      (value "LED_RGBRGB_LED")
      (footprint "eagle-import:OVSPRGB_HS_FIXED")
      (libsource (lib "eagle-import") (part "LED_RGBRGB_LED"))
    )
    (comp (ref "RGB15")
      (value "LED_RGBRGB_LED")
      (footprint "eagle-import:OVSPRGB_HS_FIXED")
      (libsource (lib "eagle-import") (part "LED_RGBRGB_LED"))
    )
    (comp (ref "RGB16")
      (value "LED_RGBRGB_LED")
      (footprint "eagle-import:OVSPRGB_HS_FIXED")
      (libsource (lib "eagle-import") (part "LED_RGBRGB_LED"))
    )
    (comp (ref "RGB21")
      (value "LED_RGBRGB_LED")
      (footprint "eagle-import:OVSPRGB_HS_FIXED")
      (libsource (lib "eagle-import") (part "LED_RGBRGB_LED"))
    )
    (comp (ref "RGB22")
      (value "LED_RGBRGB_LED")
      (footprint "eagle-import:OVSPRGB_HS_FIXED")
      (libsource (lib "eagle-import") (part "LED_RGBRGB_LED"))
    )
    (comp (ref "RGB23")
      (value "LED_RGBRGB_LED")
      (footprint "eagle-import:OVSPRGB_HS_FIXED")
      (libsource (lib "eagle-import") (part "LED_RGBRGB_LED"))
    )
    (comp (ref "RGB24")
      (value "LED_RGBRGB_LED")
      (footprint "eagle-import:OVSPRGB_HS_FIXED")
      (libsource (lib "eagle-import") (part "LED_RGBRGB_LED"))
    )
    (comp (ref "RGB29")
      (value "LED_RGBRGB_LED")
      (footprint "eagle-import:OVSPRGB_HS_FIXED")
      (libsource (lib "eagle-import") (part "LED_RGBRGB_LED"))
    )
    (comp (ref "RGB30")
      (value "LED_RGBRGB_LED")
      (footprint "eagle-import:OVSPRGB_HS_FIXED")
      (libsource (lib "eagle-import") (part "LED_RGBRGB_LED"))
    )
    (comp (ref "RGB31")
      (value "LED_RGBRGB_LED")
      (footprint "eagle-import:OVSPRGB_HS_FIXED")
      (libsource (lib "eagle-import") (part "LED_RGBRGB_LED"))
    )
    (comp (ref "RGB32")
      (value "LED_RGBRGB_LED")
      (footprint "eagle-import:OVSPRGB_HS_FIXED")
      (libsource (lib "eagle-import") (part "LED_RGBRGB_LED"))
    )
    (comp (ref "U3")
      (value "AD8613")
      (footprint "eagle-import:SOT23-5")
      (fields (field (name "MF") "ALTERA CORPORATION") (field (name "MPN") "AD8065ARTZ-REEL7"))
      (libsource (lib "eagle-import") (part "AD8065RT"))
    )
    (comp (ref "U4")
      (value "AD8613")
      (footprint "eagle-import:SOT23-5")
      (fields (field (name "MF") "ALTERA CORPORATION") (field (name "MPN") "AD8065ARTZ-REEL7"))
      (libsource (lib "eagle-import") (part "AD8065RT"))
    )
    (comp (ref "U6")
      (value "AD8613")
      (footprint "eagle-import:SOT23-5")
      (fields (field (name "MF") "ALTERA CORPORATION") (field (name "MPN") "AD8065ARTZ-REEL7"))
      (libsource (lib "eagle-import") (part "AD8065RT"))
    )
    (comp (ref "U8")
      (value "AD5624")
      (footprint "eagle-import:MSOP10")
      (libsource (lib "eagle-import") (part "AD56X4R"))
    )
    (comp (ref "U10")
      (value "AP8802")
      (footprint "eagle-import:SOIC8-EP")
      (libsource (lib "eagle-import") (part "AP8802"))
    )
  )
  (nets
    (net (code "1") (name "+5LL") (class "Default")
      (node (ref "C38") (pin "1") (pinfunction "1_1") (pintype "passive"))
      (node (ref "C39") (pin "1") (pinfunction "1_1") (pintype "passive"))
      (node (ref "C42") (pin "1") (pinfunction "1_1") (pintype "passive"))
      (node (ref "C44") (pin "1") (pinfunction "1_1") (pintype "passive"))
      (node (ref "I4") (pin "2") (pinfunction "P$2_2") (pintype "bidirectional"))
      (node (ref "U18") (pin "5") (pinfunction "+VS_5") (pintype "input"))
      (node (ref "U19") (pin "9") (pinfunction "VDD_9") (pintype "bidirectional"))
      (node (ref "U20") (pin "5") (pinfunction "+VS_5") (pintype "input"))
      (node (ref "U21") (pin "5") (pinfunction "+VS_5") (pintype "input"))
    )
    (net (code "2") (name "+5LR") (class "Default")
      (node (ref "C19") (pin "1") (pinfunction "1_1") (pintype "passive"))
      (node (ref "C5") (pin "1") (pinfunction "1_1") (pintype "passive"))
      (node (ref "C6") (pin "1") (pinfunction "1_1") (pintype "passive"))
      (node (ref "C8") (pin "1") (pinfunction "1_1") (pintype "passive"))
      (node (ref "I2") (pin "2") (pinfunction "P$2_2") (pintype "bidirectional"))
      (node (ref "U1") (pin "5") (pinfunction "+VS_5") (pintype "input"))
      (node (ref "U2") (pin "5") (pinfunction "+VS_5") (pintype "input"))
      (node (ref "U5") (pin "5") (pinfunction "+VS_5") (pintype "input"))
      (node (ref "U9") (pin "9") (pinfunction "VDD_9") (pintype "bidirectional"))
    )
    (net (code "3") (name "+5UL") (class "Default")
      (node (ref "C26") (pin "1") (pinfunction "1_1") (pintype "passive"))
      (node (ref "C28") (pin "1") (pinfunction "1_1") (pintype "passive"))
      (node (ref "C31") (pin "1") (pinfunction "1_1") (pintype "passive"))
      (node (ref "C32") (pin "1") (pinfunction "1_1") (pintype "passive"))
      (node (ref "I3") (pin "2") (pinfunction "P$2_2") (pintype "bidirectional"))
      (node (ref "U13") (pin "5") (pinfunction "+VS_5") (pintype "input"))
      (node (ref "U14") (pin "5") (pinfunction "+VS_5") (pintype "input"))
      (node (ref "U15") (pin "9") (pinfunction "VDD_9") (pintype "bidirectional"))
      (node (ref "U16") (pin "5") (pinfunction "+VS_5") (pintype "input"))
    )
    (net (code "4") (name "+5UR") (class "Default")
      (node (ref "C10") (pin "1") (pinfunction "1_1") (pintype "passive"))
      (node (ref "C20") (pin "1") (pinfunction "1_1") (pintype "passive"))
      (node (ref "C7") (pin "1") (pinfunction "1_1") (pintype "passive"))
      (node (ref "C9") (pin "1") (pinfunction "1_1") (pintype "passive"))
      (node (ref "I1") (pin "2") (pinfunction "P$2_2") (pintype "bidirectional"))
      (node (ref "U3") (pin "5") (pinfunction "+VS_5") (pintype "input"))
      (node (ref "U4") (pin "5") (pinfunction "+VS_5") (pintype "input"))
      (node (ref "U6") (pin "5") (pinfunction "+VS_5") (pintype "input"))
      (node (ref "U8") (pin "9") (pinfunction "VDD_9") (pintype "bidirectional"))
    )
    (net (code "5") (name "+5VD") (class "Default")
      (node (ref "C13") (pin "2") (pinfunction "2_2") (pintype "passive"))
      (node (ref "C25") (pin "1") (pinfunction "1_1") (pintype "passive"))
      (node (ref "C45") (pin "1") (pinfunction "1_1") (pintype "passive"))
      (node (ref "I1") (pin "1") (pinfunction "P$1_1") (pintype "bidirectional"))
      (node (ref "I2") (pin "1") (pinfunction "P$1_1") (pintype "bidirectional"))
      (node (ref "I3") (pin "1") (pinfunction "P$1_1") (pintype "bidirectional"))
      (node (ref "I4") (pin "1") (pinfunction "P$1_1") (pintype "bidirectional"))
      (node (ref "J4") (pin "3") (pinfunction "P$3_3") (pintype "bidirectional"))
      (node (ref "J6") (pin "3") (pinfunction "P$3_3") (pintype "bidirectional"))
      (node (ref "M1") (pin "28") (pinfunction "VIN_28") (pintype "power_in"))
      (node (ref "U12") (pin "4") (pinfunction "V+_4") (pintype "bidirectional"))
    )
    (net (code "6") (name "3V3") (class "Default")
      (node (ref "C24") (pin "1") (pinfunction "1_1") (pintype "passive"))
      (node (ref "M1") (pin "26") (pinfunction "3.3V_26") (pintype "power_in"))
      (node (ref "U11") (pin "5") (pinfunction "VCC_5") (pintype "power_in"))
    )
    (net (code "7") (name "B1A") (class "Default")
      (node (ref "Q1") (pin "5") (pinfunction "C2_5") (pintype "bidirectional"))
      (node (ref "Q1") (pin "56") (pinfunction "C2_56") (pintype "bidirectional"))
      (node (ref "Q1") (pin "56A") (pinfunction "C2_56A") (pintype "bidirectional"))
      (node (ref "Q1") (pin "56B") (pinfunction "C2_56B") (pintype "bidirectional"))
      (node (ref "Q1") (pin "5A") (pinfunction "C2_5A") (pintype "bidirectional"))
      (node (ref "Q1") (pin "5A1") (pinfunction "C2_5A1") (pintype "bidirectional"))
      (node (ref "Q1") (pin "5B") (pinfunction "C2_5B") (pintype "bidirectional"))
      (node (ref "Q1") (pin "5C") (pinfunction "C2_5C") (pintype "bidirectional"))
      (node (ref "Q1") (pin "5C1") (pinfunction "C2_5C1") (pintype "bidirectional"))
      (node (ref "Q1") (pin "5C2") (pinfunction "C2_5C2") (pintype "bidirectional"))
      (node (ref "Q1") (pin "6") (pinfunction "C2_6") (pintype "bidirectional"))
      (node (ref "RGB53") (pin "4") (pinfunction "BC_4") (pintype "bidirectional"))
      (node (ref "RGB53") (pin "4A") (pinfunction "BC_4A") (pintype "bidirectional"))
      (node (ref "RGB53") (pin "4B") (pinfunction "BC_4B") (pintype "bidirectional"))
    )
    (net (code "8") (name "B1B") (class "Default")
      (node (ref "Q1") (pin "7") (pinfunction "C1_7") (pintype "bidirectional"))
      (node (ref "Q1") (pin "78") (pinfunction "C1_78") (pintype "bidirectional"))
      (node (ref "Q1") (pin "78A") (pinfunction "C1_78A") (pintype "bidirectional"))
      (node (ref "Q1") (pin "78B") (pinfunction "C1_78B") (pintype "bidirectional"))
      (node (ref "Q1") (pin "8") (pinfunction "C1_8") (pintype "bidirectional"))
      (node (ref "Q1") (pin "8A") (pinfunction "C1_8A") (pintype "bidirectional"))
      (node (ref "Q1") (pin "8B") (pinfunction "C1_8B") (pintype "bidirectional"))
      (node (ref "Q1") (pin "8C") (pinfunction "C1_8C") (pintype "bidirectional"))
      (node (ref "Q1") (pin "8C1") (pinfunction "C1_8C1") (pintype "bidirectional"))
      (node (ref "Q1") (pin "8C2") (pinfunction "C1_8C2") (pintype "bidirectional"))
      (node (ref "Q1") (pin "8C3") (pinfunction "C1_8C3") (pintype "bidirectional"))
      (node (ref "RGB37") (pin "4") (pinfunction "BC_4") (pintype "bidirectional"))
      (node (ref "RGB37") (pin "4A") (pinfunction "BC_4A") (pintype "bidirectional"))
      (node (ref "RGB37") (pin "4B") (pinfunction "BC_4B") (pintype "bidirectional"))
    )
    (net (code "9") (name "BLU_LL") (class "Default")
      (node (ref "U18") (pin "3") (pinfunction "IN+_3") (pintype "input"))
      (node (ref "U19") (pin "1") (pinfunction "VO_A_1") (pintype "bidirectional"))
    )
    (net (code "10") (name "BLU_LR") (class "Default")
      (node (ref "U2") (pin "3") (pinfunction "IN+_3") (pintype "input"))
      (node (ref "U9") (pin "1") (pinfunction "VO_A_1") (pintype "bidirectional"))
    )
    (net (code "11") (name "BLU_UL") (class "Default")
      (node (ref "U13") (pin "3") (pinfunction "IN+_3") (pintype "input"))
      (node (ref "U15") (pin "1") (pinfunction "VO_A_1") (pintype "bidirectional"))
    )
    (net (code "12") (name "BLU_UR") (class "Default")
      (node (ref "U4") (pin "3") (pinfunction "IN+_3") (pintype "input"))
      (node (ref "U8") (pin "1") (pinfunction "VO_A_1") (pintype "bidirectional"))
    )
    (net (code "13") (name "BULA") (class "Default")
      (node (ref "Q7") (pin "5") (pinfunction "C2_5") (pintype "bidirectional"))
      (node (ref "Q7") (pin "56") (pinfunction "C2_56") (pintype "bidirectional"))
      (node (ref "Q7") (pin "56A") (pinfunction "C2_56A") (pintype "bidirectional"))
      (node (ref "Q7") (pin "56B") (pinfunction "C2_56B") (pintype "bidirectional"))
      (node (ref "Q7") (pin "5A") (pinfunction "C2_5A") (pintype "bidirectional"))
      (node (ref "Q7") (pin "5A1") (pinfunction "C2_5A1") (pintype "bidirectional"))
      (node (ref "Q7") (pin "5B") (pinfunction "C2_5B") (pintype "bidirectional"))
      (node (ref "Q7") (pin "5C") (pinfunction "C2_5C") (pintype "bidirectional"))
      (node (ref "Q7") (pin "5C1") (pinfunction "C2_5C1") (pintype "bidirectional"))
      (node (ref "Q7") (pin "5C2") (pinfunction "C2_5C2") (pintype "bidirectional"))
      (node (ref "Q7") (pin "6") (pinfunction "C2_6") (pintype "bidirectional"))
      (node (ref "RGB17") (pin "4") (pinfunction "BC_4") (pintype "bidirectional"))
      (node (ref "RGB17") (pin "4A") (pinfunction "BC_4A") (pintype "bidirectional"))
      (node (ref "RGB17") (pin "4B") (pinfunction "BC_4B") (pintype "bidirectional"))
    )
    (net (code "14") (name "BULB") (class "Default")
      (node (ref "Q7") (pin "7") (pinfunction "C1_7") (pintype "bidirectional"))
      (node (ref "Q7") (pin "78") (pinfunction "C1_78") (pintype "bidirectional"))
      (node (ref "Q7") (pin "78A") (pinfunction "C1_78A") (pintype "bidirectional"))
      (node (ref "Q7") (pin "78B") (pinfunction "C1_78B") (pintype "bidirectional"))
      (node (ref "Q7") (pin "8") (pinfunction "C1_8") (pintype "bidirectional"))
      (node (ref "Q7") (pin "8A") (pinfunction "C1_8A") (pintype "bidirectional"))
      (node (ref "Q7") (pin "8B") (pinfunction "C1_8B") (pintype "bidirectional"))
      (node (ref "Q7") (pin "8C") (pinfunction "C1_8C") (pintype "bidirectional"))
      (node (ref "Q7") (pin "8C1") (pinfunction "C1_8C1") (pintype "bidirectional"))
      (node (ref "Q7") (pin "8C2") (pinfunction "C1_8C2") (pintype "bidirectional"))
      (node (ref "Q7") (pin "8C3") (pinfunction "C1_8C3") (pintype "bidirectional"))
      (node (ref "RGB1") (pin "4") (pinfunction "BC_4") (pintype "bidirectional"))
      (node (ref "RGB1") (pin "4A") (pinfunction "BC_4A") (pintype "bidirectional"))
      (node (ref "RGB1") (pin "4B") (pinfunction "BC_4B") (pintype "bidirectional"))
    )
    (net (code "15") (name "DIR") (class "Default")
      (node (ref "M1") (pin "4") (pinfunction "2_4") (pintype "bidirectional"))
      (node (ref "U11") (pin "6") (pinfunction "~{A}/B_6") (pintype "input"))
    )
    (net (code "16") (name "G1A") (class "Default")
      (node (ref "Q2") (pin "5") (pinfunction "C2_5") (pintype "bidirectional"))
      (node (ref "Q2") (pin "56") (pinfunction "C2_56") (pintype "bidirectional"))
      (node (ref "Q2") (pin "56A") (pinfunction "C2_56A") (pintype "bidirectional"))
      (node (ref "Q2") (pin "56B") (pinfunction "C2_56B") (pintype "bidirectional"))
      (node (ref "Q2") (pin "5A") (pinfunction "C2_5A") (pintype "bidirectional"))
      (node (ref "Q2") (pin "5A1") (pinfunction "C2_5A1") (pintype "bidirectional"))
      (node (ref "Q2") (pin "5B") (pinfunction "C2_5B") (pintype "bidirectional"))
      (node (ref "Q2") (pin "5C") (pinfunction "C2_5C") (pintype "bidirectional"))
      (node (ref "Q2") (pin "5C1") (pinfunction "C2_5C1") (pintype "bidirectional"))
      (node (ref "Q2") (pin "5C2") (pinfunction "C2_5C2") (pintype "bidirectional"))
      (node (ref "Q2") (pin "6") (pinfunction "C2_6") (pintype "bidirectional"))
      (node (ref "RGB53") (pin "6") (pinfunction "GC_6") (pintype "bidirectional"))
      (node (ref "RGB53") (pin "6A") (pinfunction "GC_6A") (pintype "bidirectional"))
      (node (ref "RGB53") (pin "6B") (pinfunction "GC_6B") (pintype "bidirectional"))
    )
    (net (code "17") (name "G1B") (class "Default")
      (node (ref "Q2") (pin "7") (pinfunction "C1_7") (pintype "bidirectional"))
      (node (ref "Q2") (pin "78") (pinfunction "C1_78") (pintype "bidirectional"))
      (node (ref "Q2") (pin "78A") (pinfunction "C1_78A") (pintype "bidirectional"))
      (node (ref "Q2") (pin "78B") (pinfunction "C1_78B") (pintype "bidirectional"))
      (node (ref "Q2") (pin "8") (pinfunction "C1_8") (pintype "bidirectional"))
      (node (ref "Q2") (pin "8A") (pinfunction "C1_8A") (pintype "bidirectional"))
      (node (ref "Q2") (pin "8B") (pinfunction "C1_8B") (pintype "bidirectional"))
      (node (ref "Q2") (pin "8C") (pinfunction "C1_8C") (pintype "bidirectional"))
      (node (ref "Q2") (pin "8C1") (pinfunction "C1_8C1") (pintype "bidirectional"))
      (node (ref "Q2") (pin "8C2") (pinfunction "C1_8C2") (pintype "bidirectional"))
      (node (ref "Q2") (pin "8C3") (pinfunction "C1_8C3") (pintype "bidirectional"))
      (node (ref "RGB37") (pin "6") (pinfunction "GC_6") (pintype "bidirectional"))
      (node (ref "RGB37") (pin "6A") (pinfunction "GC_6A") (pintype "bidirectional"))
      (node (ref "RGB37") (pin "6B") (pinfunction "GC_6B") (pintype "bidirectional"))
    )
    (net (code "18") (name "GRN_LL") (class "Default")
      (node (ref "U19") (pin "2") (pinfunction "VO_B_2") (pintype "bidirectional"))
      (node (ref "U21") (pin "3") (pinfunction "IN+_3") (pintype "input"))
    )
    (net (code "19") (name "GRN_LR") (class "Default")
      (node (ref "U1") (pin "3") (pinfunction "IN+_3") (pintype "input"))
      (node (ref "U9") (pin "2") (pinfunction "VO_B_2") (pintype "bidirectional"))
    )
    (net (code "20") (name "GRN_UL") (class "Default")
      (node (ref "U15") (pin "2") (pinfunction "VO_B_2") (pintype "bidirectional"))
      (node (ref "U16") (pin "3") (pinfunction "IN+_3") (pintype "input"))
    )
    (net (code "21") (name "GRN_UR") (class "Default")
      (node (ref "U3") (pin "3") (pinfunction "IN+_3") (pintype "input"))
      (node (ref "U8") (pin "2") (pinfunction "VO_B_2") (pintype "bidirectional"))
    )
    (net (code "22") (name "GULA_1") (class "Default")
      (node (ref "Q9") (pin "5") (pinfunction "C2_5") (pintype "bidirectional"))
      (node (ref "Q9") (pin "56") (pinfunction "C2_56") (pintype "bidirectional"))
      (node (ref "Q9") (pin "56A") (pinfunction "C2_56A") (pintype "bidirectional"))
      (node (ref "Q9") (pin "56B") (pinfunction "C2_56B") (pintype "bidirectional"))
      (node (ref "Q9") (pin "5A") (pinfunction "C2_5A") (pintype "bidirectional"))
      (node (ref "Q9") (pin "5A1") (pinfunction "C2_5A1") (pintype "bidirectional"))
      (node (ref "Q9") (pin "5B") (pinfunction "C2_5B") (pintype "bidirectional"))
      (node (ref "Q9") (pin "5C") (pinfunction "C2_5C") (pintype "bidirectional"))
      (node (ref "Q9") (pin "5C1") (pinfunction "C2_5C1") (pintype "bidirectional"))
      (node (ref "Q9") (pin "5C2") (pinfunction "C2_5C2") (pintype "bidirectional"))
      (node (ref "Q9") (pin "6") (pinfunction "C2_6") (pintype "bidirectional"))
      (node (ref "RGB17") (pin "6") (pinfunction "GC_6") (pintype "bidirectional"))
      (node (ref "RGB17") (pin "6A") (pinfunction "GC_6A") (pintype "bidirectional"))
      (node (ref "RGB17") (pin "6B") (pinfunction "GC_6B") (pintype "bidirectional"))
    )
    (net (code "23") (name "GULB_A") (class "Default")
      (node (ref "Q9") (pin "7") (pinfunction "C1_7") (pintype "bidirectional"))
      (node (ref "Q9") (pin "78") (pinfunction "C1_78") (pintype "bidirectional"))
      (node (ref "Q9") (pin "78A") (pinfunction "C1_78A") (pintype "bidirectional"))
      (node (ref "Q9") (pin "78B") (pinfunction "C1_78B") (pintype "bidirectional"))
      (node (ref "Q9") (pin "8") (pinfunction "C1_8") (pintype "bidirectional"))
      (node (ref "Q9") (pin "8A") (pinfunction "C1_8A") (pintype "bidirectional"))
      (node (ref "Q9") (pin "8B") (pinfunction "C1_8B") (pintype "bidirectional"))
      (node (ref "Q9") (pin "8C") (pinfunction "C1_8C") (pintype "bidirectional"))
      (node (ref "Q9") (pin "8C1") (pinfunction "C1_8C1") (pintype "bidirectional"))
      (node (ref "Q9") (pin "8C2") (pinfunction "C1_8C2") (pintype "bidirectional"))
      (node (ref "Q9") (pin "8C3") (pinfunction "C1_8C3") (pintype "bidirectional"))
      (node (ref "RGB1") (pin "6") (pinfunction "GC_6") (pintype "bidirectional"))
      (node (ref "RGB1") (pin "6A") (pinfunction "GC_6A") (pintype "bidirectional"))
      (node (ref "RGB1") (pin "6B") (pinfunction "GC_6B") (pintype "bidirectional"))
    )
    (net (code "24") (name "IGND") (class "Default")
      (node (ref "C11") (pin "2") (pinfunction "2_2") (pintype "passive"))
      (node (ref "C15") (pin "2") (pinfunction "2_2") (pintype "passive"))
      (node (ref "C18") (pin "-") (pinfunction "-_-") (pintype "passive"))
      (node (ref "C34") (pin "2") (pinfunction "2_2") (pintype "passive"))
      (node (ref "C46") (pin "2") (pinfunction "2_2") (pintype "passive"))
      (node (ref "R17") (pin "1") (pinfunction "1_1") (pintype "passive"))
      (node (ref "R21") (pin "1") (pinfunction "1_1") (pintype "passive"))
      (node (ref "R41") (pin "1") (pinfunction "1_1") (pintype "passive"))
      (node (ref "R60") (pin "1") (pinfunction "1_1") (pintype "passive"))
      (node (ref "SH2") (pin "2") (pinfunction "2_2") (pintype "bidirectional"))
      (node (ref "U10") (pin "2") (pinfunction "GND_2") (pintype "bidirectional"))
      (node (ref "U10") (pin "7") (pinfunction "GND1_7") (pintype "bidirectional"))
      (node (ref "U10") (pin "EP") (pinfunction "EP_EP") (pintype "bidirectional"))
      (node (ref "U17") (pin "2") (pinfunction "GND_2") (pintype "bidirectional"))
      (node (ref "U17") (pin "7") (pinfunction "GND1_7") (pintype "bidirectional"))
      (node (ref "U17") (pin "EP") (pinfunction "EP_EP") (pintype "bidirectional"))
      (node (ref "U22") (pin "2") (pinfunction "GND_2") (pintype "bidirectional"))
      (node (ref "U22") (pin "7") (pinfunction "GND1_7") (pintype "bidirectional"))
      (node (ref "U22") (pin "EP") (pinfunction "EP_EP") (pintype "bidirectional"))
      (node (ref "U7") (pin "2") (pinfunction "GND_2") (pintype "bidirectional"))
      (node (ref "U7") (pin "7") (pinfunction "GND1_7") (pintype "bidirectional"))
      (node (ref "U7") (pin "EP") (pinfunction "EP_EP") (pintype "bidirectional"))
    )
    (net (code "25") (name "IR_DRV_LL") (class "Default")
      (node (ref "C47") (pin "1") (pinfunction "1_1") (pintype "passive"))
      (node (ref "IR145") (pin "A") (pinfunction "A_A") (pintype "bidirectional"))
      (node (ref "IR145") (pin "A1") (pinfunction "A_A1") (pintype "bidirectional"))
      (node (ref "IR177") (pin "A") (pinfunction "A_A") (pintype "bidirectional"))
      (node (ref "IR177") (pin "A1") (pinfunction "A_A1") (pintype "bidirectional"))
      (node (ref "IR209") (pin "A") (pinfunction "A_A") (pintype "bidirectional"))
      (node (ref "IR209") (pin "A1") (pinfunction "A_A1") (pintype "bidirectional"))
      (node (ref "IR240") (pin "A") (pinfunction "A_A") (pintype "bidirectional"))
      (node (ref "IR240") (pin "A1") (pinfunction "A_A1") (pintype "bidirectional"))
      (node (ref "R61") (pin "1") (pinfunction "1_1") (pintype "passive"))
      (node (ref "U22") (pin "1") (pinfunction "SET_1") (pintype "bidirectional"))
    )
    (net (code "26") (name "IR_DRV_LR") (class "Default")
      (node (ref "C23") (pin "1") (pinfunction "1_1") (pintype "passive"))
      (node (ref "D4") (pin "A") (pinfunction "A_A") (pintype "bidirectional"))
      (node (ref "D4") (pin "A1") (pinfunction "A_A1") (pintype "bidirectional"))
      (node (ref "IR153") (pin "A") (pinfunction "A_A") (pintype "bidirectional"))
      (node (ref "IR153") (pin "A1") (pinfunction "A_A1") (pintype "bidirectional"))
      (node (ref "IR185") (pin "A") (pinfunction "A_A") (pintype "bidirectional"))
      (node (ref "IR185") (pin "A1") (pinfunction "A_A1") (pintype "bidirectional"))
      (node (ref "IR244") (pin "A") (pinfunction "A_A") (pintype "bidirectional"))
      (node (ref "IR244") (pin "A1") (pinfunction "A_A1") (pintype "bidirectional"))
      (node (ref "R22") (pin "1") (pinfunction "1_1") (pintype "passive"))
      (node (ref "U7") (pin "1") (pinfunction "SET_1") (pintype "bidirectional"))
    )
    (net (code "27") (name "IR_DRV_UL") (class "Default")
      (node (ref "C35") (pin "1") (pinfunction "1_1") (pintype "passive"))
      (node (ref "IR113") (pin "A") (pinfunction "A_A") (pintype "bidirectional"))
      (node (ref "IR113") (pin "A1") (pinfunction "A_A1") (pintype "bidirectional"))
      (node (ref "IR17") (pin "A") (pinfunction "A_A") (pintype "bidirectional"))
      (node (ref "IR17") (pin "A1") (pinfunction "A_A1") (pintype "bidirectional"))
      (node (ref "IR49") (pin "A") (pinfunction "A_A") (pintype "bidirectional"))
      (node (ref "IR49") (pin "A1") (pinfunction "A_A1") (pintype "bidirectional"))
      (node (ref "IR81") (pin "A") (pinfunction "A_A") (pintype "bidirectional"))
      (node (ref "IR81") (pin "A1") (pinfunction "A_A1") (pintype "bidirectional"))
      (node (ref "R42") (pin "1") (pinfunction "1_1") (pintype "passive"))
      (node (ref "U17") (pin "1") (pinfunction "SET_1") (pintype "bidirectional"))
    )
    (net (code "28") (name "IR_DRV_UR") (class "Default")
      (node (ref "C22") (pin "1") (pinfunction "1_1") (pintype "passive"))
      (node (ref "IR117") (pin "A") (pinfunction "A_A") (pintype "bidirectional"))
      (node (ref "IR25") (pin "A") (pinfunction "A_A") (pintype "bidirectional"))
      (node (ref "IR25") (pin "A1") (pinfunction "A_A1") (pintype "bidirectional"))
      (node (ref "IR57") (pin "A") (pinfunction "A_A") (pintype "bidirectional"))
      (node (ref "IR57") (pin "A1") (pinfunction "A_A1") (pintype "bidirectional"))
      (node (ref "IR89") (pin "A") (pinfunction "A_A") (pintype "bidirectional"))
      (node (ref "IR89") (pin "A1") (pinfunction "A_A1") (pintype "bidirectional"))
      (node (ref "R20") (pin "1") (pinfunction "1_1") (pintype "passive"))
      (node (ref "U10") (pin "1") (pinfunction "SET_1") (pintype "bidirectional"))
    )
    (net (code "29") (name "IR_LL") (class "Default")
      (node (ref "R60") (pin "2") (pinfunction "2_2") (pintype "passive"))
      (node (ref "U19") (pin "5") (pinfunction "VO_D_5") (pintype "bidirectional"))
      (node (ref "U22") (pin "8") (pinfunction "CTRL_8") (pintype "bidirectional"))
    )
    (net (code "30") (name "IR_LR") (class "Default")
      (node (ref "R21") (pin "2") (pinfunction "2_2") (pintype "passive"))
      (node (ref "U7") (pin "8") (pinfunction "CTRL_8") (pintype "bidirectional"))
      (node (ref "U9") (pin "5") (pinfunction "VO_D_5") (pintype "bidirectional"))
    )
    (net (code "31") (name "IR_UL") (class "Default")
      (node (ref "R41") (pin "2") (pinfunction "2_2") (pintype "passive"))
      (node (ref "U15") (pin "5") (pinfunction "VO_D_5") (pintype "bidirectional"))
      (node (ref "U17") (pin "8") (pinfunction "CTRL_8") (pintype "bidirectional"))
    )
    (net (code "32") (name "IR_UR") (class "Default")
      (node (ref "R17") (pin "2") (pinfunction "2_2") (pintype "passive"))
      (node (ref "U10") (pin "8") (pinfunction "CTRL_8") (pintype "bidirectional"))
      (node (ref "U8") (pin "5") (pinfunction "VO_D_5") (pintype "bidirectional"))
    )
    (net (code "33") (name "LED") (class "Default")
      (node (ref "M1") (pin "22") (pinfunction "20/A6/PWM_22") (pintype "bidirectional"))
      (node (ref "R25") (pin "2") (pinfunction "2_2") (pintype "passive"))
    )
    (net (code "34") (name "LGND") (class "Default")
      (node (ref "C1") (pin "2") (pinfunction "2_2") (pintype "passive"))
      (node (ref "C10") (pin "2") (pinfunction "2_2") (pintype "passive"))
      (node (ref "C12") (pin "2") (pinfunction "2_2") (pintype "passive"))
      (node (ref "C13") (pin "1") (pinfunction "1_1") (pintype "passive"))
      (node (ref "C14") (pin "2") (pinfunction "2_2") (pintype "passive"))
      (node (ref "C16") (pin "2") (pinfunction "2_2") (pintype "passive"))
      (node (ref "C17") (pin "-") (pinfunction "-_-") (pintype "passive"))
      (node (ref "C19") (pin "2") (pinfunction "2_2") (pintype "passive"))
      (node (ref "C2") (pin "2") (pinfunction "2_2") (pintype "passive"))
      (node (ref "C20") (pin "2") (pinfunction "2_2") (pintype "passive"))
      (node (ref "C21") (pin "2") (pinfunction "2_2") (pintype "passive"))
      (node (ref "C24") (pin "2") (pinfunction "2_2") (pintype "passive"))
      (node (ref "C25") (pin "2") (pinfunction "2_2") (pintype "passive"))
      (node (ref "C26") (pin "2") (pinfunction "2_2") (pintype "passive"))
      (node (ref "C27") (pin "2") (pinfunction "2_2") (pintype "passive"))
      (node (ref "C28") (pin "2") (pinfunction "2_2") (pintype "passive"))
      (node (ref "C29") (pin "2") (pinfunction "2_2") (pintype "passive"))
      (node (ref "C3") (pin "2") (pinfunction "2_2") (pintype "passive"))
      (node (ref "C30") (pin "2") (pinfunction "2_2") (pintype "passive"))
      (node (ref "C31") (pin "2") (pinfunction "2_2") (pintype "passive"))
      (node (ref "C32") (pin "2") (pinfunction "2_2") (pintype "passive"))
      (node (ref "C33") (pin "2") (pinfunction "2_2") (pintype "passive"))
      (node (ref "C36") (pin "2") (pinfunction "2_2") (pintype "passive"))
      (node (ref "C37") (pin "-") (pinfunction "-_-") (pintype "passive"))
      (node (ref "C38") (pin "2") (pinfunction "2_2") (pintype "passive"))
      (node (ref "C39") (pin "2") (pinfunction "2_2") (pintype "passive"))
      (node (ref "C4") (pin "2") (pinfunction "2_2") (pintype "passive"))
      (node (ref "C40") (pin "2") (pinfunction "2_2") (pintype "passive"))
      (node (ref "C41") (pin "2") (pinfunction "2_2") (pintype "passive"))
      (node (ref "C42") (pin "2") (pinfunction "2_2") (pintype "passive"))
      (node (ref "C43") (pin "2") (pinfunction "2_2") (pintype "passive"))
      (node (ref "C44") (pin "2") (pinfunction "2_2") (pintype "passive"))
      (node (ref "C45") (pin "2") (pinfunction "2_2") (pintype "passive"))
      (node (ref "C5") (pin "2") (pinfunction "2_2") (pintype "passive"))
      (node (ref "C6") (pin "2") (pinfunction "2_2") (pintype "passive"))
      (node (ref "C7") (pin "2") (pinfunction "2_2") (pintype "passive"))
      (node (ref "C8") (pin "2") (pinfunction "2_2") (pintype "passive"))
      (node (ref "C9") (pin "2") (pinfunction "2_2") (pintype "passive"))
      (node (ref "J1") (pin "2") (pinfunction "P$2_2") (pintype "bidirectional"))
      (node (ref "J2") (pin "2") (pinfunction "P$3_2") (pintype "bidirectional"))
      (node (ref "J3") (pin "2") (pinfunction "P$2_2") (pintype "bidirectional"))
      (node (ref "J4") (pin "1") (pinfunction "P$1_1") (pintype "bidirectional"))
      (node (ref "J5") (pin "P$3") (pinfunction "P$3_P$3") (pintype "bidirectional"))
      (node (ref "J6") (pin "1") (pinfunction "P$1_1") (pintype "bidirectional"))
      (node (ref "M1") (pin "1") (pinfunction "GND_1") (pintype "power_in"))
      (node (ref "M1") (pin "27") (pinfunction "AGND_27") (pintype "power_in"))
      (node (ref "R1") (pin "1") (pinfunction "1_1") (pintype "passive"))
      (node (ref "R10") (pin "1") (pinfunction "1_1") (pintype "passive"))
      (node (ref "R11") (pin "1") (pinfunction "1_1") (pintype "passive"))
      (node (ref "R12") (pin "1") (pinfunction "1_1") (pintype "passive"))
      (node (ref "R2") (pin "1") (pinfunction "1_1") (pintype "passive"))
      (node (ref "R24") (pin "1") (pinfunction "1_1") (pintype "passive"))
      (node (ref "R26") (pin "1") (pinfunction "1_1") (pintype "passive"))
      (node (ref "R29") (pin "1") (pinfunction "1_1") (pintype "passive"))
      (node (ref "R3") (pin "1") (pinfunction "1_1") (pintype "passive"))
      (node (ref "R30") (pin "1") (pinfunction "1_1") (pintype "passive"))
      (node (ref "R33") (pin "1") (pinfunction "1_1") (pintype "passive"))
      (node (ref "R35") (pin "1") (pinfunction "1_1") (pintype "passive"))
      (node (ref "R4") (pin "1") (pinfunction "1_1") (pintype "passive"))
      (node (ref "R43") (pin "1") (pinfunction "1_1") (pintype "passive"))
      (node (ref "R44") (pin "1") (pinfunction "1_1") (pintype "passive"))
      (node (ref "R48") (pin "1") (pinfunction "1_1") (pintype "passive"))
      (node (ref "R49") (pin "1") (pinfunction "1_1") (pintype "passive"))
      (node (ref "R5") (pin "1") (pinfunction "1_1") (pintype "passive"))
      (node (ref "R53") (pin "1") (pinfunction "1_1") (pintype "passive"))
      (node (ref "R57") (pin "1") (pinfunction "1_1") (pintype "passive"))
      (node (ref "R6") (pin "1") (pinfunction "1_1") (pintype "passive"))
      (node (ref "R7") (pin "1") (pinfunction "1_1") (pintype "passive"))
      (node (ref "R8") (pin "1") (pinfunction "1_1") (pintype "passive"))
      (node (ref "R9") (pin "1") (pinfunction "1_1") (pintype "passive"))
      (node (ref "SH2") (pin "1") (pinfunction "1_1") (pintype "bidirectional"))
      (node (ref "U1") (pin "2") (pinfunction "-VS_2") (pintype "input"))
      (node (ref "U11") (pin "2") (pinfunction "GND_2") (pintype "power_in"))
      (node (ref "U12") (pin "1") (pinfunction "HYST_1") (pintype "bidirectional"))
      (node (ref "U12") (pin "2") (pinfunction "GND_2") (pintype "bidirectional"))
      (node (ref "U13") (pin "2") (pinfunction "-VS_2") (pintype "input"))
      (node (ref "U14") (pin "2") (pinfunction "-VS_2") (pintype "input"))
      (node (ref "U15") (pin "3") (pinfunction "GND_3") (pintype "bidirectional"))
      (node (ref "U16") (pin "2") (pinfunction "-VS_2") (pintype "input"))
      (node (ref "U18") (pin "2") (pinfunction "-VS_2") (pintype "input"))
      (node (ref "U19") (pin "3") (pinfunction "GND_3") (pintype "bidirectional"))
      (node (ref "U2") (pin "2") (pinfunction "-VS_2") (pintype "input"))
      (node (ref "U20") (pin "2") (pinfunction "-VS_2") (pintype "input"))
      (node (ref "U21") (pin "2") (pinfunction "-VS_2") (pintype "input"))
      (node (ref "U3") (pin "2") (pinfunction "-VS_2") (pintype "input"))
      (node (ref "U4") (pin "2") (pinfunction "-VS_2") (pintype "input"))
      (node (ref "U5") (pin "2") (pinfunction "-VS_2") (pintype "input"))
      (node (ref "U6") (pin "2") (pinfunction "-VS_2") (pintype "input"))
      (node (ref "U8") (pin "3") (pinfunction "GND_3") (pintype "bidirectional"))
      (node (ref "U9") (pin "3") (pinfunction "GND_3") (pintype "bidirectional"))
    )
    (net (code "35") (name "LL_EN") (class "Default")
      (node (ref "M1") (pin "17") (pinfunction "15/A1/T_17") (pintype "bidirectional"))
      (node (ref "U19") (pin "6") (pinfunction "~{SYNC}_6") (pintype "bidirectional"))
    )
    (net (code "36") (name "LR_EN") (class "Default")
      (node (ref "M1") (pin "19") (pinfunction "17/A3/T_19") (pintype "bidirectional"))
      (node (ref "U9") (pin "6") (pinfunction "~{SYNC}_6") (pintype "bidirectional"))
    )
    (net (code "37") (name "MOSI") (class "Default")
      (node (ref "M1") (pin "13") (pinfunction "11/MOSI_13") (pintype "bidirectional"))
      (node (ref "U15") (pin "8") (pinfunction "DIN_8") (pintype "bidirectional"))
      (node (ref "U19") (pin "8") (pinfunction "DIN_8") (pintype "bidirectional"))
      (node (ref "U8") (pin "8") (pinfunction "DIN_8") (pintype "bidirectional"))
      (node (ref "U9") (pin "8") (pinfunction "DIN_8") (pintype "bidirectional"))
    )
    (net (code "38") (name "Net-(C22-Pad2)") (class "Default")
      (node (ref "C22") (pin "2") (pinfunction "2_2") (pintype "passive"))
      (node (ref "L2") (pin "1") (pinfunction "1_1") (pintype "passive"))
      (node (ref "R23") (pin "2") (pinfunction "2_2") (pintype "passive"))
      (node (ref "R27") (pin "2") (pinfunction "2_2") (pintype "passive"))
      (node (ref "R32") (pin "2") (pinfunction "2_2") (pintype "passive"))
      (node (ref "R38") (pin "2") (pinfunction "2_2") (pintype "passive"))
    )
    (net (code "39") (name "Net-(C23-Pad2)") (class "Default")
      (node (ref "C23") (pin "2") (pinfunction "2_2") (pintype "passive"))
      (node (ref "L1") (pin "1") (pinfunction "1_1") (pintype "passive"))
      (node (ref "R45") (pin "2") (pinfunction "2_2") (pintype "passive"))
      (node (ref "R47") (pin "2") (pinfunction "2_2") (pintype "passive"))
      (node (ref "R51") (pin "2") (pinfunction "2_2") (pintype "passive"))
      (node (ref "R52") (pin "2") (pinfunction "2_2") (pintype "passive"))
    )
    (net (code "40") (name "Net-(C35-Pad2)") (class "Default")
      (node (ref "C35") (pin "2") (pinfunction "2_2") (pintype "passive"))
      (node (ref "L3") (pin "1") (pinfunction "1_1") (pintype "passive"))
      (node (ref "R34") (pin "2") (pinfunction "2_2") (pintype "passive"))
      (node (ref "R36") (pin "2") (pinfunction "2_2") (pintype "passive"))
      (node (ref "R37") (pin "2") (pinfunction "2_2") (pintype "passive"))
      (node (ref "R39") (pin "2") (pinfunction "2_2") (pintype "passive"))
    )
    (net (code "41") (name "Net-(C47-Pad2)") (class "Default")
      (node (ref "C47") (pin "2") (pinfunction "2_2") (pintype "passive"))
      (node (ref "L4") (pin "1") (pinfunction "1_1") (pintype "passive"))
      (node (ref "R54") (pin "2") (pinfunction "2_2") (pintype "passive"))
      (node (ref "R55") (pin "2") (pinfunction "2_2") (pintype "passive"))
      (node (ref "R56") (pin "2") (pinfunction "2_2") (pintype "passive"))
      (node (ref "R58") (pin "2") (pinfunction "2_2") (pintype "passive"))
    )
    (net (code "42") (name "Net-(D4-K-PadC)") (class "Default")
      (node (ref "D4") (pin "C") (pinfunction "K_C") (pintype "bidirectional"))
      (node (ref "D4") (pin "C1") (pinfunction "K_C1") (pintype "bidirectional"))
      (node (ref "IR217") (pin "A") (pinfunction "A_A") (pintype "bidirectional"))
      (node (ref "IR217") (pin "A1") (pinfunction "A_A1") (pintype "bidirectional"))
    )
    (net (code "43") (name "Net-(IR1-A-PadA1)") (class "Default")
      (node (ref "IR1") (pin "A") (pinfunction "A_A") (pintype "bidirectional"))
      (node (ref "IR1") (pin "A1") (pinfunction "A_A1") (pintype "bidirectional"))
      (node (ref "IR2") (pin "C") (pinfunction "K_C") (pintype "bidirectional"))
      (node (ref "IR2") (pin "C1") (pinfunction "K_C1") (pintype "bidirectional"))
    )
    (net (code "44") (name "Net-(IR1-K)") (class "Default")
      (node (ref "IR1") (pin "C") (pinfunction "K_C") (pintype "bidirectional"))
      (node (ref "R34") (pin "1") (pinfunction "1_1") (pintype "passive"))
    )
    (net (code "45") (name "Net-(IR2-A-PadA1)") (class "Default")
      (node (ref "IR2") (pin "A") (pinfunction "A_A") (pintype "bidirectional"))
      (node (ref "IR2") (pin "A1") (pinfunction "A_A1") (pintype "bidirectional"))
      (node (ref "IR3") (pin "C") (pinfunction "K_C") (pintype "bidirectional"))
      (node (ref "IR3") (pin "C1") (pinfunction "K_C1") (pintype "bidirectional"))
    )
    (net (code "46") (name "Net-(IR3-A-PadA1)") (class "Default")
      (node (ref "IR3") (pin "A") (pinfunction "A_A") (pintype "bidirectional"))
      (node (ref "IR3") (pin "A1") (pinfunction "A_A1") (pintype "bidirectional"))
      (node (ref "IR4") (pin "C") (pinfunction "K_C") (pintype "bidirectional"))
      (node (ref "IR4") (pin "C1") (pinfunction "K_C1") (pintype "bidirectional"))
    )
    (net (code "47") (name "Net-(IR4-A-PadA1)") (class "Default")
      (node (ref "IR4") (pin "A") (pinfunction "A_A") (pintype "bidirectional"))
      (node (ref "IR4") (pin "A1") (pinfunction "A_A1") (pintype "bidirectional"))
      (node (ref "IR5") (pin "C") (pinfunction "K_C") (pintype "bidirectional"))
      (node (ref "IR5") (pin "C1") (pinfunction "K_C1") (pintype "bidirectional"))
    )
    (net (code "48") (name "Net-(IR5-A-PadA1)") (class "Default")
      (node (ref "IR5") (pin "A") (pinfunction "A_A") (pintype "bidirectional"))
      (node (ref "IR5") (pin "A1") (pinfunction "A_A1") (pintype "bidirectional"))
      (node (ref "IR6") (pin "C") (pinfunction "K_C") (pintype "bidirectional"))
      (node (ref "IR6") (pin "C1") (pinfunction "K_C1") (pintype "bidirectional"))
    )
    (net (code "49") (name "Net-(IR6-A-PadA1)") (class "Default")
      (node (ref "IR6") (pin "A") (pinfunction "A_A") (pintype "bidirectional"))
      (node (ref "IR6") (pin "A1") (pinfunction "A_A1") (pintype "bidirectional"))
      (node (ref "IR7") (pin "C") (pinfunction "K_C") (pintype "bidirectional"))
      (node (ref "IR7") (pin "C1") (pinfunction "K_C1") (pintype "bidirectional"))
    )
    (net (code "50") (name "Net-(IR7-A-PadA1)") (class "Default")
      (node (ref "IR7") (pin "A") (pinfunction "A_A") (pintype "bidirectional"))
      (node (ref "IR7") (pin "A1") (pinfunction "A_A1") (pintype "bidirectional"))
      (node (ref "IR8") (pin "C") (pinfunction "K_C") (pintype "bidirectional"))
      (node (ref "IR8") (pin "C1") (pinfunction "K_C1") (pintype "bidirectional"))
    )
    (net (code "51") (name "Net-(IR9-K-PadC)") (class "Default")
      (node (ref "IR9") (pin "C") (pinfunction "K_C") (pintype "bidirectional"))
      (node (ref "IR9") (pin "C1") (pinfunction "K_C1") (pintype "bidirectional"))
      (node (ref "R23") (pin "1") (pinfunction "1_1") (pintype "passive"))
    )
    (net (code "52") (name "Net-(IR10-A-PadA1)") (class "Default")
      (node (ref "IR10") (pin "A") (pinfunction "A_A") (pintype "bidirectional"))
      (node (ref "IR10") (pin "A1") (pinfunction "A_A1") (pintype "bidirectional"))
      (node (ref "IR11") (pin "C") (pinfunction "K_C") (pintype "bidirectional"))
      (node (ref "IR11") (pin "C1") (pinfunction "K_C1") (pintype "bidirectional"))
    )
    (net (code "53") (name "Net-(IR10-K-PadC)") (class "Default")
      (node (ref "IR10") (pin "C") (pinfunction "K_C") (pintype "bidirectional"))
      (node (ref "IR10") (pin "C1") (pinfunction "K_C1") (pintype "bidirectional"))
      (node (ref "IR9") (pin "A") (pinfunction "A_A") (pintype "bidirectional"))
      (node (ref "IR9") (pin "A1") (pinfunction "A_A1") (pintype "bidirectional"))
    )
    (net (code "54") (name "Net-(IR11-A-PadA1)") (class "Default")
      (node (ref "IR11") (pin "A") (pinfunction "A_A") (pintype "bidirectional"))
      (node (ref "IR11") (pin "A1") (pinfunction "A_A1") (pintype "bidirectional"))
      (node (ref "IR12") (pin "C") (pinfunction "K_C") (pintype "bidirectional"))
      (node (ref "IR12") (pin "C1") (pinfunction "K_C1") (pintype "bidirectional"))
    )
    (net (code "55") (name "Net-(IR12-A-PadA1)") (class "Default")
      (node (ref "IR12") (pin "A") (pinfunction "A_A") (pintype "bidirectional"))
      (node (ref "IR12") (pin "A1") (pinfunction "A_A1") (pintype "bidirectional"))
      (node (ref "IR13") (pin "C") (pinfunction "K_C") (pintype "bidirectional"))
      (node (ref "IR13") (pin "C1") (pinfunction "K_C1") (pintype "bidirectional"))
    )
    (net (code "56") (name "Net-(IR13-A-PadA1)") (class "Default")
      (node (ref "IR13") (pin "A") (pinfunction "A_A") (pintype "bidirectional"))
      (node (ref "IR13") (pin "A1") (pinfunction "A_A1") (pintype "bidirectional"))
      (node (ref "IR14") (pin "C") (pinfunction "K_C") (pintype "bidirectional"))
      (node (ref "IR14") (pin "C1") (pinfunction "K_C1") (pintype "bidirectional"))
    )
    (net (code "57") (name "Net-(IR14-A-PadA1)") (class "Default")
      (node (ref "IR14") (pin "A") (pinfunction "A_A") (pintype "bidirectional"))
      (node (ref "IR14") (pin "A1") (pinfunction "A_A1") (pintype "bidirectional"))
      (node (ref "IR15") (pin "C") (pinfunction "K_C") (pintype "bidirectional"))
      (node (ref "IR15") (pin "C1") (pinfunction "K_C1") (pintype "bidirectional"))
    )
    (net (code "58") (name "Net-(IR15-A-PadA1)") (class "Default")
      (node (ref "IR15") (pin "A") (pinfunction "A_A") (pintype "bidirectional"))
      (node (ref "IR15") (pin "A1") (pinfunction "A_A1") (pintype "bidirectional"))
      (node (ref "IR16") (pin "C") (pinfunction "K_C") (pintype "bidirectional"))
      (node (ref "IR16") (pin "C1") (pinfunction "K_C1") (pintype "bidirectional"))
    )
    (net (code "59") (name "Net-(IR16-A-PadA1)") (class "Default")
      (node (ref "IR16") (pin "A") (pinfunction "A_A") (pintype "bidirectional"))
      (node (ref "IR16") (pin "A1") (pinfunction "A_A1") (pintype "bidirectional"))
      (node (ref "IR32") (pin "C") (pinfunction "K_C") (pintype "bidirectional"))
      (node (ref "IR32") (pin "C1") (pinfunction "K_C1") (pintype "bidirectional"))
    )
    (net (code "60") (name "Net-(IR17-K-PadC)") (class "Default")
      (node (ref "IR17") (pin "C") (pinfunction "K_C") (pintype "bidirectional"))
      (node (ref "IR17") (pin "C1") (pinfunction "K_C1") (pintype "bidirectional"))
      (node (ref "IR18") (pin "A") (pinfunction "A_A") (pintype "bidirectional"))
      (node (ref "IR18") (pin "A1") (pinfunction "A_A1") (pintype "bidirectional"))
    )
    (net (code "61") (name "Net-(IR18-K-PadC)") (class "Default")
      (node (ref "IR18") (pin "C") (pinfunction "K_C") (pintype "bidirectional"))
      (node (ref "IR18") (pin "C1") (pinfunction "K_C1") (pintype "bidirectional"))
      (node (ref "IR19") (pin "A") (pinfunction "A_A") (pintype "bidirectional"))
      (node (ref "IR19") (pin "A1") (pinfunction "A_A1") (pintype "bidirectional"))
    )
    (net (code "62") (name "Net-(IR19-K-PadC)") (class "Default")
      (node (ref "IR19") (pin "C") (pinfunction "K_C") (pintype "bidirectional"))
      (node (ref "IR19") (pin "C1") (pinfunction "K_C1") (pintype "bidirectional"))
      (node (ref "IR20") (pin "A") (pinfunction "A_A") (pintype "bidirectional"))
      (node (ref "IR20") (pin "A1") (pinfunction "A_A1") (pintype "bidirectional"))
    )
    (net (code "63") (name "Net-(IR20-K-PadC)") (class "Default")
      (node (ref "IR20") (pin "C") (pinfunction "K_C") (pintype "bidirectional"))
      (node (ref "IR20") (pin "C1") (pinfunction "K_C1") (pintype "bidirectional"))
      (node (ref "IR21") (pin "A") (pinfunction "A_A") (pintype "bidirectional"))
      (node (ref "IR21") (pin "A1") (pinfunction "A_A1") (pintype "bidirectional"))
    )
    (net (code "64") (name "Net-(IR21-K-PadC)") (class "Default")
      (node (ref "IR21") (pin "C") (pinfunction "K_C") (pintype "bidirectional"))
      (node (ref "IR21") (pin "C1") (pinfunction "K_C1") (pintype "bidirectional"))
      (node (ref "IR22") (pin "A") (pinfunction "A_A") (pintype "bidirectional"))
      (node (ref "IR22") (pin "A1") (pinfunction "A_A1") (pintype "bidirectional"))
    )
    (net (code "65") (name "Net-(IR22-K-PadC)") (class "Default")
      (node (ref "IR22") (pin "C") (pinfunction "K_C") (pintype "bidirectional"))
      (node (ref "IR22") (pin "C1") (pinfunction "K_C1") (pintype "bidirectional"))
      (node (ref "IR23") (pin "A") (pinfunction "A_A") (pintype "bidirectional"))
      (node (ref "IR23") (pin "A1") (pinfunction "A_A1") (pintype "bidirectional"))
    )
    (net (code "66") (name "Net-(IR23-K-PadC)") (class "Default")
      (node (ref "IR23") (pin "C") (pinfunction "K_C") (pintype "bidirectional"))
      (node (ref "IR23") (pin "C1") (pinfunction "K_C1") (pintype "bidirectional"))
      (node (ref "IR24") (pin "A") (pinfunction "A_A") (pintype "bidirectional"))
      (node (ref "IR24") (pin "A1") (pinfunction "A_A1") (pintype "bidirectional"))
    )
    (net (code "67") (name "Net-(IR24-K-PadC)") (class "Default")
      (node (ref "IR24") (pin "C") (pinfunction "K_C") (pintype "bidirectional"))
      (node (ref "IR24") (pin "C1") (pinfunction "K_C1") (pintype "bidirectional"))
      (node (ref "IR8") (pin "A") (pinfunction "A_A") (pintype "bidirectional"))
      (node (ref "IR8") (pin "A1") (pinfunction "A_A1") (pintype "bidirectional"))
    )
    (net (code "68") (name "Net-(IR25-K-PadC)") (class "Default")
      (node (ref "IR25") (pin "C") (pinfunction "K_C") (pintype "bidirectional"))
      (node (ref "IR25") (pin "C1") (pinfunction "K_C1") (pintype "bidirectional"))
      (node (ref "IR26") (pin "A") (pinfunction "A_A") (pintype "bidirectional"))
      (node (ref "IR26") (pin "A1") (pinfunction "A_A1") (pintype "bidirectional"))
    )
    (net (code "69") (name "Net-(IR26-K-PadC)") (class "Default")
      (node (ref "IR26") (pin "C") (pinfunction "K_C") (pintype "bidirectional"))
      (node (ref "IR26") (pin "C1") (pinfunction "K_C1") (pintype "bidirectional"))
      (node (ref "IR27") (pin "A") (pinfunction "A_A") (pintype "bidirectional"))
      (node (ref "IR27") (pin "A1") (pinfunction "A_A1") (pintype "bidirectional"))
    )
    (net (code "70") (name "Net-(IR27-K-PadC)") (class "Default")
      (node (ref "IR27") (pin "C") (pinfunction "K_C") (pintype "bidirectional"))
      (node (ref "IR27") (pin "C1") (pinfunction "K_C1") (pintype "bidirectional"))
      (node (ref "IR28") (pin "A") (pinfunction "A_A") (pintype "bidirectional"))
      (node (ref "IR28") (pin "A1") (pinfunction "A_A1") (pintype "bidirectional"))
    )
    (net (code "71") (name "Net-(IR28-K-PadC)") (class "Default")
      (node (ref "IR28") (pin "C") (pinfunction "K_C") (pintype "bidirectional"))
      (node (ref "IR28") (pin "C1") (pinfunction "K_C1") (pintype "bidirectional"))
      (node (ref "IR29") (pin "A") (pinfunction "A_A") (pintype "bidirectional"))
      (node (ref "IR29") (pin "A1") (pinfunction "A_A1") (pintype "bidirectional"))
    )
    (net (code "72") (name "Net-(IR29-K-PadC)") (class "Default")
      (node (ref "IR29") (pin "C") (pinfunction "K_C") (pintype "bidirectional"))
      (node (ref "IR29") (pin "C1") (pinfunction "K_C1") (pintype "bidirectional"))
      (node (ref "IR30") (pin "A") (pinfunction "A_A") (pintype "bidirectional"))
      (node (ref "IR30") (pin "A1") (pinfunction "A_A1") (pintype "bidirectional"))
    )
    (net (code "73") (name "Net-(IR30-K-PadC)") (class "Default")
      (node (ref "IR30") (pin "C") (pinfunction "K_C") (pintype "bidirectional"))
      (node (ref "IR30") (pin "C1") (pinfunction "K_C1") (pintype "bidirectional"))
      (node (ref "IR31") (pin "A") (pinfunction "A_A") (pintype "bidirectional"))
      (node (ref "IR31") (pin "A1") (pinfunction "A_A1") (pintype "bidirectional"))
    )
    (net (code "74") (name "Net-(IR31-K-PadC)") (class "Default")
      (node (ref "IR31") (pin "C") (pinfunction "K_C") (pintype "bidirectional"))
      (node (ref "IR31") (pin "C1") (pinfunction "K_C1") (pintype "bidirectional"))
      (node (ref "IR32") (pin "A") (pinfunction "A_A") (pintype "bidirectional"))
      (node (ref "IR32") (pin "A1") (pinfunction "A_A1") (pintype "bidirectional"))
    )
    (net (code "75") (name "Net-(IR33-A-PadA1)") (class "Default")
      (node (ref "IR33") (pin "A") (pinfunction "A_A") (pintype "bidirectional"))
      (node (ref "IR33") (pin "A1") (pinfunction "A_A1") (pintype "bidirectional"))
      (node (ref "IR34") (pin "C") (pinfunction "K_C") (pintype "bidirectional"))
      (node (ref "IR34") (pin "C1") (pinfunction "K_C1") (pintype "bidirectional"))
    )
    (net (code "76") (name "Net-(IR33-K-PadC)") (class "Default")
      (node (ref "IR33") (pin "C") (pinfunction "K_C") (pintype "bidirectional"))
      (node (ref "IR33") (pin "C1") (pinfunction "K_C1") (pintype "bidirectional"))
      (node (ref "R36") (pin "1") (pinfunction "1_1") (pintype "passive"))
    )
    (net (code "77") (name "Net-(IR34-A-PadA1)") (class "Default")
      (node (ref "IR34") (pin "A") (pinfunction "A_A") (pintype "bidirectional"))
      (node (ref "IR34") (pin "A1") (pinfunction "A_A1") (pintype "bidirectional"))
      (node (ref "IR35") (pin "C") (pinfunction "K_C") (pintype "bidirectional"))
      (node (ref "IR35") (pin "C1") (pinfunction "K_C1") (pintype "bidirectional"))
    )
    (net (code "78") (name "Net-(IR35-A-PadA1)") (class "Default")
      (node (ref "IR35") (pin "A") (pinfunction "A_A") (pintype "bidirectional"))
      (node (ref "IR35") (pin "A1") (pinfunction "A_A1") (pintype "bidirectional"))
      (node (ref "IR36") (pin "C") (pinfunction "K_C") (pintype "bidirectional"))
      (node (ref "IR36") (pin "C1") (pinfunction "K_C1") (pintype "bidirectional"))
    )
    (net (code "79") (name "Net-(IR36-A-PadA1)") (class "Default")
      (node (ref "IR36") (pin "A") (pinfunction "A_A") (pintype "bidirectional"))
      (node (ref "IR36") (pin "A1") (pinfunction "A_A1") (pintype "bidirectional"))
      (node (ref "IR37") (pin "C") (pinfunction "K_C") (pintype "bidirectional"))
      (node (ref "IR37") (pin "C1") (pinfunction "K_C1") (pintype "bidirectional"))
    )
    (net (code "80") (name "Net-(IR37-A-PadA1)") (class "Default")
      (node (ref "IR37") (pin "A") (pinfunction "A_A") (pintype "bidirectional"))
      (node (ref "IR37") (pin "A1") (pinfunction "A_A1") (pintype "bidirectional"))
      (node (ref "IR38") (pin "C") (pinfunction "K_C") (pintype "bidirectional"))
      (node (ref "IR38") (pin "C1") (pinfunction "K_C1") (pintype "bidirectional"))
    )
    (net (code "81") (name "Net-(IR38-A-PadA1)") (class "Default")
      (node (ref "IR38") (pin "A") (pinfunction "A_A") (pintype "bidirectional"))
      (node (ref "IR38") (pin "A1") (pinfunction "A_A1") (pintype "bidirectional"))
      (node (ref "IR39") (pin "C") (pinfunction "K_C") (pintype "bidirectional"))
      (node (ref "IR39") (pin "C1") (pinfunction "K_C1") (pintype "bidirectional"))
    )
    (net (code "82") (name "Net-(IR39-A-PadA1)") (class "Default")
      (node (ref "IR39") (pin "A") (pinfunction "A_A") (pintype "bidirectional"))
      (node (ref "IR39") (pin "A1") (pinfunction "A_A1") (pintype "bidirectional"))
      (node (ref "IR40") (pin "C") (pinfunction "K_C") (pintype "bidirectional"))
      (node (ref "IR40") (pin "C1") (pinfunction "K_C1") (pintype "bidirectional"))
    )
    (net (code "83") (name "Net-(IR40-A-PadA1)") (class "Default")
      (node (ref "IR40") (pin "A") (pinfunction "A_A") (pintype "bidirectional"))
      (node (ref "IR40") (pin "A1") (pinfunction "A_A1") (pintype "bidirectional"))
      (node (ref "IR56") (pin "C") (pinfunction "K_C") (pintype "bidirectional"))
      (node (ref "IR56") (pin "C1") (pinfunction "K_C1") (pintype "bidirectional"))
    )
    (net (code "84") (name "Net-(IR41-A-PadA1)") (class "Default")
      (node (ref "IR41") (pin "A") (pinfunction "A_A") (pintype "bidirectional"))
      (node (ref "IR41") (pin "A1") (pinfunction "A_A1") (pintype "bidirectional"))
      (node (ref "IR42") (pin "C") (pinfunction "K_C") (pintype "bidirectional"))
      (node (ref "IR42") (pin "C1") (pinfunction "K_C1") (pintype "bidirectional"))
    )
    (net (code "85") (name "Net-(IR41-K-PadC)") (class "Default")
      (node (ref "IR41") (pin "C") (pinfunction "K_C") (pintype "bidirectional"))
      (node (ref "IR41") (pin "C1") (pinfunction "K_C1") (pintype "bidirectional"))
      (node (ref "R27") (pin "1") (pinfunction "1_1") (pintype "passive"))
    )
    (net (code "86") (name "Net-(IR42-A-PadA1)") (class "Default")
      (node (ref "IR42") (pin "A") (pinfunction "A_A") (pintype "bidirectional"))
      (node (ref "IR42") (pin "A1") (pinfunction "A_A1") (pintype "bidirectional"))
      (node (ref "IR43") (pin "C") (pinfunction "K_C") (pintype "bidirectional"))
      (node (ref "IR43") (pin "C1") (pinfunction "K_C1") (pintype "bidirectional"))
    )
    (net (code "87") (name "Net-(IR43-A-PadA1)") (class "Default")
      (node (ref "IR43") (pin "A") (pinfunction "A_A") (pintype "bidirectional"))
      (node (ref "IR43") (pin "A1") (pinfunction "A_A1") (pintype "bidirectional"))
      (node (ref "IR44") (pin "C") (pinfunction "K_C") (pintype "bidirectional"))
      (node (ref "IR44") (pin "C1") (pinfunction "K_C1") (pintype "bidirectional"))
    )
    (net (code "88") (name "Net-(IR44-A-PadA1)") (class "Default")
      (node (ref "IR44") (pin "A") (pinfunction "A_A") (pintype "bidirectional"))
      (node (ref "IR44") (pin "A1") (pinfunction "A_A1") (pintype "bidirectional"))
      (node (ref "IR45") (pin "C") (pinfunction "K_C") (pintype "bidirectional"))
      (node (ref "IR45") (pin "C1") (pinfunction "K_C1") (pintype "bidirectional"))
    )
    (net (code "89") (name "Net-(IR45-A-PadA1)") (class "Default")
      (node (ref "IR45") (pin "A") (pinfunction "A_A") (pintype "bidirectional"))
      (node (ref "IR45") (pin "A1") (pinfunction "A_A1") (pintype "bidirectional"))
      (node (ref "IR46") (pin "C") (pinfunction "K_C") (pintype "bidirectional"))
      (node (ref "IR46") (pin "C1") (pinfunction "K_C1") (pintype "bidirectional"))
    )
    (net (code "90") (name "Net-(IR46-A-PadA1)") (class "Default")
      (node (ref "IR46") (pin "A") (pinfunction "A_A") (pintype "bidirectional"))
      (node (ref "IR46") (pin "A1") (pinfunction "A_A1") (pintype "bidirectional"))
      (node (ref "IR47") (pin "C") (pinfunction "K_C") (pintype "bidirectional"))
      (node (ref "IR47") (pin "C1") (pinfunction "K_C1") (pintype "bidirectional"))
    )
    (net (code "91") (name "Net-(IR47-A-PadA1)") (class "Default")
      (node (ref "IR47") (pin "A") (pinfunction "A_A") (pintype "bidirectional"))
      (node (ref "IR47") (pin "A1") (pinfunction "A_A1") (pintype "bidirectional"))
      (node (ref "IR48") (pin "C") (pinfunction "K_C") (pintype "bidirectional"))
      (node (ref "IR48") (pin "C1") (pinfunction "K_C1") (pintype "bidirectional"))
    )
    (net (code "92") (name "Net-(IR48-A-PadA1)") (class "Default")
      (node (ref "IR48") (pin "A") (pinfunction "A_A") (pintype "bidirectional"))
      (node (ref "IR48") (pin "A1") (pinfunction "A_A1") (pintype "bidirectional"))
      (node (ref "IR64") (pin "C") (pinfunction "K_C") (pintype "bidirectional"))
      (node (ref "IR64") (pin "C1") (pinfunction "K_C1") (pintype "bidirectional"))
    )
    (net (code "93") (name "Net-(IR49-K-PadC)") (class "Default")
      (node (ref "IR49") (pin "C") (pinfunction "K_C") (pintype "bidirectional"))
      (node (ref "IR49") (pin "C1") (pinfunction "K_C1") (pintype "bidirectional"))
      (node (ref "IR50") (pin "A") (pinfunction "A_A") (pintype "bidirectional"))
      (node (ref "IR50") (pin "A1") (pinfunction "A_A1") (pintype "bidirectional"))
    )
    (net (code "94") (name "Net-(IR50-K-PadC)") (class "Default")
      (node (ref "IR50") (pin "C") (pinfunction "K_C") (pintype "bidirectional"))
      (node (ref "IR50") (pin "C1") (pinfunction "K_C1") (pintype "bidirectional"))
      (node (ref "IR51") (pin "A") (pinfunction "A_A") (pintype "bidirectional"))
      (node (ref "IR51") (pin "A1") (pinfunction "A_A1") (pintype "bidirectional"))
    )
    (net (code "95") (name "Net-(IR51-K-PadC)") (class "Default")
      (node (ref "IR51") (pin "C") (pinfunction "K_C") (pintype "bidirectional"))
      (node (ref "IR51") (pin "C1") (pinfunction "K_C1") (pintype "bidirectional"))
      (node (ref "IR52") (pin "A") (pinfunction "A_A") (pintype "bidirectional"))
      (node (ref "IR52") (pin "A1") (pinfunction "A_A1") (pintype "bidirectional"))
    )
    (net (code "96") (name "Net-(IR52-K-PadC)") (class "Default")
      (node (ref "IR52") (pin "C") (pinfunction "K_C") (pintype "bidirectional"))
      (node (ref "IR52") (pin "C1") (pinfunction "K_C1") (pintype "bidirectional"))
      (node (ref "IR53") (pin "A") (pinfunction "A_A") (pintype "bidirectional"))
      (node (ref "IR53") (pin "A1") (pinfunction "A_A1") (pintype "bidirectional"))
    )
    (net (code "97") (name "Net-(IR53-K-PadC)") (class "Default")
      (node (ref "IR53") (pin "C") (pinfunction "K_C") (pintype "bidirectional"))
      (node (ref "IR53") (pin "C1") (pinfunction "K_C1") (pintype "bidirectional"))
      (node (ref "IR54") (pin "A") (pinfunction "A_A") (pintype "bidirectional"))
      (node (ref "IR54") (pin "A1") (pinfunction "A_A1") (pintype "bidirectional"))
    )
    (net (code "98") (name "Net-(IR54-K-PadC)") (class "Default")
      (node (ref "IR54") (pin "C") (pinfunction "K_C") (pintype "bidirectional"))
      (node (ref "IR54") (pin "C1") (pinfunction "K_C1") (pintype "bidirectional"))
      (node (ref "IR55") (pin "A") (pinfunction "A_A") (pintype "bidirectional"))
      (node (ref "IR55") (pin "A1") (pinfunction "A_A1") (pintype "bidirectional"))
    )
    (net (code "99") (name "Net-(IR55-K-PadC)") (class "Default")
      (node (ref "IR55") (pin "C") (pinfunction "K_C") (pintype "bidirectional"))
      (node (ref "IR55") (pin "C1") (pinfunction "K_C1") (pintype "bidirectional"))
      (node (ref "IR56") (pin "A") (pinfunction "A_A") (pintype "bidirectional"))
      (node (ref "IR56") (pin "A1") (pinfunction "A_A1") (pintype "bidirectional"))
    )
    (net (code "100") (name "Net-(IR57-K-PadC)") (class "Default")
      (node (ref "IR57") (pin "C") (pinfunction "K_C") (pintype "bidirectional"))
      (node (ref "IR57") (pin "C1") (pinfunction "K_C1") (pintype "bidirectional"))
      (node (ref "IR58") (pin "A") (pinfunction "A_A") (pintype "bidirectional"))
      (node (ref "IR58") (pin "A1") (pinfunction "A_A1") (pintype "bidirectional"))
    )
    (net (code "101") (name "Net-(IR58-K-PadC)") (class "Default")
      (node (ref "IR58") (pin "C") (pinfunction "K_C") (pintype "bidirectional"))
      (node (ref "IR58") (pin "C1") (pinfunction "K_C1") (pintype "bidirectional"))
      (node (ref "IR59") (pin "A") (pinfunction "A_A") (pintype "bidirectional"))
      (node (ref "IR59") (pin "A1") (pinfunction "A_A1") (pintype "bidirectional"))
    )
    (net (code "102") (name "Net-(IR59-K-PadC)") (class "Default")
      (node (ref "IR59") (pin "C") (pinfunction "K_C") (pintype "bidirectional"))
      (node (ref "IR59") (pin "C1") (pinfunction "K_C1") (pintype "bidirectional"))
      (node (ref "IR60") (pin "A") (pinfunction "A_A") (pintype "bidirectional"))
      (node (ref "IR60") (pin "A1") (pinfunction "A_A1") (pintype "bidirectional"))
    )
    (net (code "103") (name "Net-(IR60-K-PadC)") (class "Default")
      (node (ref "IR60") (pin "C") (pinfunction "K_C") (pintype "bidirectional"))
      (node (ref "IR60") (pin "C1") (pinfunction "K_C1") (pintype "bidirectional"))
      (node (ref "IR61") (pin "A") (pinfunction "A_A") (pintype "bidirectional"))
      (node (ref "IR61") (pin "A1") (pinfunction "A_A1") (pintype "bidirectional"))
    )
    (net (code "104") (name "Net-(IR61-K-PadC)") (class "Default")
      (node (ref "IR61") (pin "C") (pinfunction "K_C") (pintype "bidirectional"))
      (node (ref "IR61") (pin "C1") (pinfunction "K_C1") (pintype "bidirectional"))
      (node (ref "IR62") (pin "A") (pinfunction "A_A") (pintype "bidirectional"))
      (node (ref "IR62") (pin "A1") (pinfunction "A_A1") (pintype "bidirectional"))
    )
    (net (code "105") (name "Net-(IR62-K-PadC)") (class "Default")
      (node (ref "IR62") (pin "C") (pinfunction "K_C") (pintype "bidirectional"))
      (node (ref "IR62") (pin "C1") (pinfunction "K_C1") (pintype "bidirectional"))
      (node (ref "IR63") (pin "A") (pinfunction "A_A") (pintype "bidirectional"))
      (node (ref "IR63") (pin "A1") (pinfunction "A_A1") (pintype "bidirectional"))
    )
    (net (code "106") (name "Net-(IR63-K-PadC)") (class "Default")
      (node (ref "IR63") (pin "C") (pinfunction "K_C") (pintype "bidirectional"))
      (node (ref "IR63") (pin "C1") (pinfunction "K_C1") (pintype "bidirectional"))
      (node (ref "IR64") (pin "A") (pinfunction "A_A") (pintype "bidirectional"))
      (node (ref "IR64") (pin "A1") (pinfunction "A_A1") (pintype "bidirectional"))
    )
    (net (code "107") (name "Net-(IR65-A-PadA1)") (class "Default")
      (node (ref "IR65") (pin "A") (pinfunction "A_A") (pintype "bidirectional"))
      (node (ref "IR65") (pin "A1") (pinfunction "A_A1") (pintype "bidirectional"))
      (node (ref "IR66") (pin "C") (pinfunction "K_C") (pintype "bidirectional"))
      (node (ref "IR66") (pin "C1") (pinfunction "K_C1") (pintype "bidirectional"))
    )
    (net (code "108") (name "Net-(IR65-K-PadC)") (class "Default")
      (node (ref "IR65") (pin "C") (pinfunction "K_C") (pintype "bidirectional"))
      (node (ref "IR65") (pin "C1") (pinfunction "K_C1") (pintype "bidirectional"))
      (node (ref "R37") (pin "1") (pinfunction "1_1") (pintype "passive"))
    )
    (net (code "109") (name "Net-(IR66-A-PadA1)") (class "Default")
      (node (ref "IR66") (pin "A") (pinfunction "A_A") (pintype "bidirectional"))
      (node (ref "IR66") (pin "A1") (pinfunction "A_A1") (pintype "bidirectional"))
      (node (ref "IR67") (pin "C") (pinfunction "K_C") (pintype "bidirectional"))
      (node (ref "IR67") (pin "C1") (pinfunction "K_C1") (pintype "bidirectional"))
    )
    (net (code "110") (name "Net-(IR67-A-PadA1)") (class "Default")
      (node (ref "IR67") (pin "A") (pinfunction "A_A") (pintype "bidirectional"))
      (node (ref "IR67") (pin "A1") (pinfunction "A_A1") (pintype "bidirectional"))
      (node (ref "IR68") (pin "C") (pinfunction "K_C") (pintype "bidirectional"))
      (node (ref "IR68") (pin "C1") (pinfunction "K_C1") (pintype "bidirectional"))
    )
    (net (code "111") (name "Net-(IR68-A-PadA1)") (class "Default")
      (node (ref "IR68") (pin "A") (pinfunction "A_A") (pintype "bidirectional"))
      (node (ref "IR68") (pin "A1") (pinfunction "A_A1") (pintype "bidirectional"))
      (node (ref "IR69") (pin "C") (pinfunction "K_C") (pintype "bidirectional"))
      (node (ref "IR69") (pin "C1") (pinfunction "K_C1") (pintype "bidirectional"))
    )
    (net (code "112") (name "Net-(IR69-A-PadA1)") (class "Default")
      (node (ref "IR69") (pin "A") (pinfunction "A_A") (pintype "bidirectional"))
      (node (ref "IR69") (pin "A1") (pinfunction "A_A1") (pintype "bidirectional"))
      (node (ref "IR70") (pin "C") (pinfunction "K_C") (pintype "bidirectional"))
      (node (ref "IR70") (pin "C1") (pinfunction "K_C1") (pintype "bidirectional"))
    )
    (net (code "113") (name "Net-(IR70-A-PadA1)") (class "Default")
      (node (ref "IR70") (pin "A") (pinfunction "A_A") (pintype "bidirectional"))
      (node (ref "IR70") (pin "A1") (pinfunction "A_A1") (pintype "bidirectional"))
      (node (ref "IR71") (pin "C") (pinfunction "K_C") (pintype "bidirectional"))
      (node (ref "IR71") (pin "C1") (pinfunction "K_C1") (pintype "bidirectional"))
    )
    (net (code "114") (name "Net-(IR71-A-PadA1)") (class "Default")
      (node (ref "IR71") (pin "A") (pinfunction "A_A") (pintype "bidirectional"))
      (node (ref "IR71") (pin "A1") (pinfunction "A_A1") (pintype "bidirectional"))
      (node (ref "IR72") (pin "C") (pinfunction "K_C") (pintype "bidirectional"))
      (node (ref "IR72") (pin "C1") (pinfunction "K_C1") (pintype "bidirectional"))
    )
    (net (code "115") (name "Net-(IR72-A-PadA1)") (class "Default")
      (node (ref "IR72") (pin "A") (pinfunction "A_A") (pintype "bidirectional"))
      (node (ref "IR72") (pin "A1") (pinfunction "A_A1") (pintype "bidirectional"))
      (node (ref "IR88") (pin "C") (pinfunction "K_C") (pintype "bidirectional"))
      (node (ref "IR88") (pin "C1") (pinfunction "K_C1") (pintype "bidirectional"))
    )
    (net (code "116") (name "Net-(IR73-A-PadA1)") (class "Default")
      (node (ref "IR73") (pin "A") (pinfunction "A_A") (pintype "bidirectional"))
      (node (ref "IR73") (pin "A1") (pinfunction "A_A1") (pintype "bidirectional"))
      (node (ref "IR74") (pin "C") (pinfunction "K_C") (pintype "bidirectional"))
      (node (ref "IR74") (pin "C1") (pinfunction "K_C1") (pintype "bidirectional"))
    )
    (net (code "117") (name "Net-(IR73-K-PadC)") (class "Default")
      (node (ref "IR73") (pin "C") (pinfunction "K_C") (pintype "bidirectional"))
      (node (ref "IR73") (pin "C1") (pinfunction "K_C1") (pintype "bidirectional"))
      (node (ref "R32") (pin "1") (pinfunction "1_1") (pintype "passive"))
    )
    (net (code "118") (name "Net-(IR74-A-PadA1)") (class "Default")
      (node (ref "IR74") (pin "A") (pinfunction "A_A") (pintype "bidirectional"))
      (node (ref "IR74") (pin "A1") (pinfunction "A_A1") (pintype "bidirectional"))
      (node (ref "IR75") (pin "C") (pinfunction "K_C") (pintype "bidirectional"))
      (node (ref "IR75") (pin "C1") (pinfunction "K_C1") (pintype "bidirectional"))
    )
    (net (code "119") (name "Net-(IR75-A-PadA1)") (class "Default")
      (node (ref "IR75") (pin "A") (pinfunction "A_A") (pintype "bidirectional"))
      (node (ref "IR75") (pin "A1") (pinfunction "A_A1") (pintype "bidirectional"))
      (node (ref "IR76") (pin "C") (pinfunction "K_C") (pintype "bidirectional"))
      (node (ref "IR76") (pin "C1") (pinfunction "K_C1") (pintype "bidirectional"))
    )
    (net (code "120") (name "Net-(IR76-A-PadA1)") (class "Default")
      (node (ref "IR76") (pin "A") (pinfunction "A_A") (pintype "bidirectional"))
      (node (ref "IR76") (pin "A1") (pinfunction "A_A1") (pintype "bidirectional"))
      (node (ref "IR77") (pin "C") (pinfunction "K_C") (pintype "bidirectional"))
      (node (ref "IR77") (pin "C1") (pinfunction "K_C1") (pintype "bidirectional"))
    )
    (net (code "121") (name "Net-(IR77-A-PadA1)") (class "Default")
      (node (ref "IR77") (pin "A") (pinfunction "A_A") (pintype "bidirectional"))
      (node (ref "IR77") (pin "A1") (pinfunction "A_A1") (pintype "bidirectional"))
      (node (ref "IR78") (pin "C") (pinfunction "K_C") (pintype "bidirectional"))
      (node (ref "IR78") (pin "C1") (pinfunction "K_C1") (pintype "bidirectional"))
    )
    (net (code "122") (name "Net-(IR78-A-PadA1)") (class "Default")
      (node (ref "IR78") (pin "A") (pinfunction "A_A") (pintype "bidirectional"))
      (node (ref "IR78") (pin "A1") (pinfunction "A_A1") (pintype "bidirectional"))
      (node (ref "IR79") (pin "C") (pinfunction "K_C") (pintype "bidirectional"))
      (node (ref "IR79") (pin "C1") (pinfunction "K_C1") (pintype "bidirectional"))
    )
    (net (code "123") (name "Net-(IR79-A-PadA1)") (class "Default")
      (node (ref "IR79") (pin "A") (pinfunction "A_A") (pintype "bidirectional"))
      (node (ref "IR79") (pin "A1") (pinfunction "A_A1") (pintype "bidirectional"))
      (node (ref "IR80") (pin "C") (pinfunction "K_C") (pintype "bidirectional"))
      (node (ref "IR80") (pin "C1") (pinfunction "K_C1") (pintype "bidirectional"))
    )
    (net (code "124") (name "Net-(IR80-A-PadA1)") (class "Default")
      (node (ref "IR80") (pin "A") (pinfunction "A_A") (pintype "bidirectional"))
      (node (ref "IR80") (pin "A1") (pinfunction "A_A1") (pintype "bidirectional"))
      (node (ref "IR96") (pin "C") (pinfunction "K_C") (pintype "bidirectional"))
      (node (ref "IR96") (pin "C1") (pinfunction "K_C1") (pintype "bidirectional"))
    )
    (net (code "125") (name "Net-(IR81-K-PadC)") (class "Default")
      (node (ref "IR81") (pin "C") (pinfunction "K_C") (pintype "bidirectional"))
      (node (ref "IR81") (pin "C1") (pinfunction "K_C1") (pintype "bidirectional"))
      (node (ref "IR82") (pin "A") (pinfunction "A_A") (pintype "bidirectional"))
      (node (ref "IR82") (pin "A1") (pinfunction "A_A1") (pintype "bidirectional"))
    )
    (net (code "126") (name "Net-(IR82-K-PadC)") (class "Default")
      (node (ref "IR82") (pin "C") (pinfunction "K_C") (pintype "bidirectional"))
      (node (ref "IR82") (pin "C1") (pinfunction "K_C1") (pintype "bidirectional"))
      (node (ref "IR83") (pin "A") (pinfunction "A_A") (pintype "bidirectional"))
      (node (ref "IR83") (pin "A1") (pinfunction "A_A1") (pintype "bidirectional"))
    )
    (net (code "127") (name "Net-(IR83-K-PadC)") (class "Default")
      (node (ref "IR83") (pin "C") (pinfunction "K_C") (pintype "bidirectional"))
      (node (ref "IR83") (pin "C1") (pinfunction "K_C1") (pintype "bidirectional"))
      (node (ref "IR84") (pin "A") (pinfunction "A_A") (pintype "bidirectional"))
      (node (ref "IR84") (pin "A1") (pinfunction "A_A1") (pintype "bidirectional"))
    )
    (net (code "128") (name "Net-(IR84-K-PadC)") (class "Default")
      (node (ref "IR84") (pin "C") (pinfunction "K_C") (pintype "bidirectional"))
      (node (ref "IR84") (pin "C1") (pinfunction "K_C1") (pintype "bidirectional"))
      (node (ref "IR85") (pin "A") (pinfunction "A_A") (pintype "bidirectional"))
      (node (ref "IR85") (pin "A1") (pinfunction "A_A1") (pintype "bidirectional"))
    )
    (net (code "129") (name "Net-(IR85-K-PadC)") (class "Default")
      (node (ref "IR85") (pin "C") (pinfunction "K_C") (pintype "bidirectional"))
      (node (ref "IR85") (pin "C1") (pinfunction "K_C1") (pintype "bidirectional"))
      (node (ref "IR86") (pin "A") (pinfunction "A_A") (pintype "bidirectional"))
      (node (ref "IR86") (pin "A1") (pinfunction "A_A1") (pintype "bidirectional"))
    )
    (net (code "130") (name "Net-(IR86-K-PadC)") (class "Default")
      (node (ref "IR86") (pin "C") (pinfunction "K_C") (pintype "bidirectional"))
      (node (ref "IR86") (pin "C1") (pinfunction "K_C1") (pintype "bidirectional"))
      (node (ref "IR87") (pin "A") (pinfunction "A_A") (pintype "bidirectional"))
      (node (ref "IR87") (pin "A1") (pinfunction "A_A1") (pintype "bidirectional"))
    )
    (net (code "131") (name "Net-(IR87-K-PadC)") (class "Default")
      (node (ref "IR87") (pin "C") (pinfunction "K_C") (pintype "bidirectional"))
      (node (ref "IR87") (pin "C1") (pinfunction "K_C1") (pintype "bidirectional"))
      (node (ref "IR88") (pin "A") (pinfunction "A_A") (pintype "bidirectional"))
      (node (ref "IR88") (pin "A1") (pinfunction "A_A1") (pintype "bidirectional"))
    )
    (net (code "132") (name "Net-(IR89-K-PadC)") (class "Default")
      (node (ref "IR89") (pin "C") (pinfunction "K_C") (pintype "bidirectional"))
      (node (ref "IR89") (pin "C1") (pinfunction "K_C1") (pintype "bidirectional"))
      (node (ref "IR90") (pin "A") (pinfunction "A_A") (pintype "bidirectional"))
      (node (ref "IR90") (pin "A1") (pinfunction "A_A1") (pintype "bidirectional"))
    )
    (net (code "133") (name "Net-(IR90-K-PadC)") (class "Default")
      (node (ref "IR90") (pin "C") (pinfunction "K_C") (pintype "bidirectional"))
      (node (ref "IR90") (pin "C1") (pinfunction "K_C1") (pintype "bidirectional"))
      (node (ref "IR91") (pin "A") (pinfunction "A_A") (pintype "bidirectional"))
      (node (ref "IR91") (pin "A1") (pinfunction "A_A1") (pintype "bidirectional"))
    )
    (net (code "134") (name "Net-(IR91-K-PadC)") (class "Default")
      (node (ref "IR91") (pin "C") (pinfunction "K_C") (pintype "bidirectional"))
      (node (ref "IR91") (pin "C1") (pinfunction "K_C1") (pintype "bidirectional"))
      (node (ref "IR92") (pin "A") (pinfunction "A_A") (pintype "bidirectional"))
      (node (ref "IR92") (pin "A1") (pinfunction "A_A1") (pintype "bidirectional"))
    )
    (net (code "135") (name "Net-(IR92-K-PadC)") (class "Default")
      (node (ref "IR92") (pin "C") (pinfunction "K_C") (pintype "bidirectional"))
      (node (ref "IR92") (pin "C1") (pinfunction "K_C1") (pintype "bidirectional"))
      (node (ref "IR93") (pin "A") (pinfunction "A_A") (pintype "bidirectional"))
      (node (ref "IR93") (pin "A1") (pinfunction "A_A1") (pintype "bidirectional"))
    )
    (net (code "136") (name "Net-(IR93-K-PadC)") (class "Default")
      (node (ref "IR93") (pin "C") (pinfunction "K_C") (pintype "bidirectional"))
      (node (ref "IR93") (pin "C1") (pinfunction "K_C1") (pintype "bidirectional"))
      (node (ref "IR94") (pin "A") (pinfunction "A_A") (pintype "bidirectional"))
      (node (ref "IR94") (pin "A1") (pinfunction "A_A1") (pintype "bidirectional"))
    )
    (net (code "137") (name "Net-(IR94-K-PadC)") (class "Default")
      (node (ref "IR94") (pin "C") (pinfunction "K_C") (pintype "bidirectional"))
      (node (ref "IR94") (pin "C1") (pinfunction "K_C1") (pintype "bidirectional"))
      (node (ref "IR95") (pin "A") (pinfunction "A_A") (pintype "bidirectional"))
      (node (ref "IR95") (pin "A1") (pinfunction "A_A1") (pintype "bidirectional"))
    )
    (net (code "138") (name "Net-(IR95-K-PadC)") (class "Default")
      (node (ref "IR95") (pin "C") (pinfunction "K_C") (pintype "bidirectional"))
      (node (ref "IR95") (pin "C1") (pinfunction "K_C1") (pintype "bidirectional"))
      (node (ref "IR96") (pin "A") (pinfunction "A_A") (pintype "bidirectional"))
      (node (ref "IR96") (pin "A1") (pinfunction "A_A1") (pintype "bidirectional"))
    )
    (net (code "139") (name "Net-(IR97-A-PadA1)") (class "Default")
      (node (ref "IR97") (pin "A") (pinfunction "A_A") (pintype "bidirectional"))
      (node (ref "IR97") (pin "A1") (pinfunction "A_A1") (pintype "bidirectional"))
      (node (ref "IR98") (pin "C") (pinfunction "K_C") (pintype "bidirectional"))
      (node (ref "IR98") (pin "C1") (pinfunction "K_C1") (pintype "bidirectional"))
    )
    (net (code "140") (name "Net-(IR97-K-PadC)") (class "Default")
      (node (ref "IR97") (pin "C") (pinfunction "K_C") (pintype "bidirectional"))
      (node (ref "IR97") (pin "C1") (pinfunction "K_C1") (pintype "bidirectional"))
      (node (ref "R39") (pin "1") (pinfunction "1_1") (pintype "passive"))
    )
    (net (code "141") (name "Net-(IR98-A-PadA1)") (class "Default")
      (node (ref "IR98") (pin "A") (pinfunction "A_A") (pintype "bidirectional"))
      (node (ref "IR98") (pin "A1") (pinfunction "A_A1") (pintype "bidirectional"))
      (node (ref "IR99") (pin "C") (pinfunction "K_C") (pintype "bidirectional"))
      (node (ref "IR99") (pin "C1") (pinfunction "K_C1") (pintype "bidirectional"))
    )
    (net (code "142") (name "Net-(IR100-A-PadA1)") (class "Default")
      (node (ref "IR100") (pin "A") (pinfunction "A_A") (pintype "bidirectional"))
      (node (ref "IR100") (pin "A1") (pinfunction "A_A1") (pintype "bidirectional"))
      (node (ref "IR101") (pin "C") (pinfunction "K_C") (pintype "bidirectional"))
      (node (ref "IR101") (pin "C1") (pinfunction "K_C1") (pintype "bidirectional"))
    )
    (net (code "143") (name "Net-(IR100-K-PadC)") (class "Default")
      (node (ref "IR100") (pin "C") (pinfunction "K_C") (pintype "bidirectional"))
      (node (ref "IR100") (pin "C1") (pinfunction "K_C1") (pintype "bidirectional"))
      (node (ref "IR99") (pin "A") (pinfunction "A_A") (pintype "bidirectional"))
      (node (ref "IR99") (pin "A1") (pinfunction "A_A1") (pintype "bidirectional"))
    )
    (net (code "144") (name "Net-(IR101-A-PadA1)") (class "Default")
      (node (ref "IR101") (pin "A") (pinfunction "A_A") (pintype "bidirectional"))
      (node (ref "IR101") (pin "A1") (pinfunction "A_A1") (pintype "bidirectional"))
      (node (ref "IR102") (pin "C") (pinfunction "K_C") (pintype "bidirectional"))
      (node (ref "IR102") (pin "C1") (pinfunction "K_C1") (pintype "bidirectional"))
    )
    (net (code "145") (name "Net-(IR102-A-PadA1)") (class "Default")
      (node (ref "IR102") (pin "A") (pinfunction "A_A") (pintype "bidirectional"))
      (node (ref "IR102") (pin "A1") (pinfunction "A_A1") (pintype "bidirectional"))
      (node (ref "IR103") (pin "C") (pinfunction "K_C") (pintype "bidirectional"))
      (node (ref "IR103") (pin "C1") (pinfunction "K_C1") (pintype "bidirectional"))
    )
    (net (code "146") (name "Net-(IR103-A-PadA1)") (class "Default")
      (node (ref "IR103") (pin "A") (pinfunction "A_A") (pintype "bidirectional"))
      (node (ref "IR103") (pin "A1") (pinfunction "A_A1") (pintype "bidirectional"))
      (node (ref "IR104") (pin "C") (pinfunction "K_C") (pintype "bidirectional"))
      (node (ref "IR104") (pin "C1") (pinfunction "K_C1") (pintype "bidirectional"))
    )
    (net (code "147") (name "Net-(IR105-A-PadA1)") (class "Default")
      (node (ref "IR105") (pin "A") (pinfunction "A_A") (pintype "bidirectional"))
      (node (ref "IR105") (pin "A1") (pinfunction "A_A1") (pintype "bidirectional"))
      (node (ref "IR106") (pin "C") (pinfunction "K_C") (pintype "bidirectional"))
      (node (ref "IR106") (pin "C1") (pinfunction "K_C1") (pintype "bidirectional"))
    )
    (net (code "148") (name "Net-(IR105-K-PadC)") (class "Default")
      (node (ref "IR105") (pin "C") (pinfunction "K_C") (pintype "bidirectional"))
      (node (ref "IR105") (pin "C1") (pinfunction "K_C1") (pintype "bidirectional"))
      (node (ref "R38") (pin "1") (pinfunction "1_1") (pintype "passive"))
    )
    (net (code "149") (name "Net-(IR106-PadA)") (class "Default")
      (node (ref "IR106") (pin "A") (pinfunction "A_A") (pintype "bidirectional"))
      (node (ref "IR107") (pin "C") (pinfunction "K_C") (pintype "bidirectional"))
      (node (ref "IR107") (pin "C1") (pinfunction "K_C1") (pintype "bidirectional"))
    )
    (net (code "150") (name "Net-(IR107-A-PadA1)") (class "Default")
      (node (ref "IR107") (pin "A") (pinfunction "A_A") (pintype "bidirectional"))
      (node (ref "IR107") (pin "A1") (pinfunction "A_A1") (pintype "bidirectional"))
      (node (ref "IR108") (pin "C") (pinfunction "K_C") (pintype "bidirectional"))
      (node (ref "IR108") (pin "C1") (pinfunction "K_C1") (pintype "bidirectional"))
    )
    (net (code "151") (name "Net-(IR108-A-PadA1)") (class "Default")
      (node (ref "IR108") (pin "A") (pinfunction "A_A") (pintype "bidirectional"))
      (node (ref "IR108") (pin "A1") (pinfunction "A_A1") (pintype "bidirectional"))
      (node (ref "IR109") (pin "C") (pinfunction "K_C") (pintype "bidirectional"))
      (node (ref "IR109") (pin "C1") (pinfunction "K_C1") (pintype "bidirectional"))
    )
    (net (code "152") (name "Net-(IR109-A-PadA1)") (class "Default")
      (node (ref "IR109") (pin "A") (pinfunction "A_A") (pintype "bidirectional"))
      (node (ref "IR109") (pin "A1") (pinfunction "A_A1") (pintype "bidirectional"))
      (node (ref "IR110") (pin "C") (pinfunction "K_C") (pintype "bidirectional"))
      (node (ref "IR110") (pin "C1") (pinfunction "K_C1") (pintype "bidirectional"))
    )
    (net (code "153") (name "Net-(IR110-A-PadA1)") (class "Default")
      (node (ref "IR110") (pin "A") (pinfunction "A_A") (pintype "bidirectional"))
      (node (ref "IR110") (pin "A1") (pinfunction "A_A1") (pintype "bidirectional"))
      (node (ref "IR111") (pin "C") (pinfunction "K_C") (pintype "bidirectional"))
      (node (ref "IR111") (pin "C1") (pinfunction "K_C1") (pintype "bidirectional"))
    )
    (net (code "154") (name "Net-(IR111-A-PadA1)") (class "Default")
      (node (ref "IR111") (pin "A") (pinfunction "A_A") (pintype "bidirectional"))
      (node (ref "IR111") (pin "A1") (pinfunction "A_A1") (pintype "bidirectional"))
      (node (ref "IR112") (pin "C") (pinfunction "K_C") (pintype "bidirectional"))
      (node (ref "IR112") (pin "C1") (pinfunction "K_C1") (pintype "bidirectional"))
    )
    (net (code "155") (name "Net-(IR113-K-PadC)") (class "Default")
      (node (ref "IR113") (pin "C") (pinfunction "K_C") (pintype "bidirectional"))
      (node (ref "IR113") (pin "C1") (pinfunction "K_C1") (pintype "bidirectional"))
      (node (ref "IR114") (pin "A") (pinfunction "A_A") (pintype "bidirectional"))
      (node (ref "IR114") (pin "A1") (pinfunction "A_A1") (pintype "bidirectional"))
    )
    (net (code "156") (name "Net-(IR114-K-PadC)") (class "Default")
      (node (ref "IR114") (pin "C") (pinfunction "K_C") (pintype "bidirectional"))
      (node (ref "IR114") (pin "C1") (pinfunction "K_C1") (pintype "bidirectional"))
      (node (ref "IR115") (pin "A") (pinfunction "A_A") (pintype "bidirectional"))
      (node (ref "IR115") (pin "A1") (pinfunction "A_A1") (pintype "bidirectional"))
    )
    (net (code "157") (name "Net-(IR115-K-PadC)") (class "Default")
      (node (ref "IR115") (pin "C") (pinfunction "K_C") (pintype "bidirectional"))
      (node (ref "IR115") (pin "C1") (pinfunction "K_C1") (pintype "bidirectional"))
      (node (ref "IR121") (pin "A") (pinfunction "A_A") (pintype "bidirectional"))
      (node (ref "IR121") (pin "A1") (pinfunction "A_A1") (pintype "bidirectional"))
    )
    (net (code "158") (name "Net-(IR116-A-PadA1)") (class "Default")
      (node (ref "IR116") (pin "A") (pinfunction "A_A") (pintype "bidirectional"))
      (node (ref "IR116") (pin "A1") (pinfunction "A_A1") (pintype "bidirectional"))
      (node (ref "IR121") (pin "C") (pinfunction "K_C") (pintype "bidirectional"))
      (node (ref "IR121") (pin "C1") (pinfunction "K_C1") (pintype "bidirectional"))
    )
    (net (code "159") (name "Net-(IR116-K-PadC)") (class "Default")
      (node (ref "IR116") (pin "C") (pinfunction "K_C") (pintype "bidirectional"))
      (node (ref "IR116") (pin "C1") (pinfunction "K_C1") (pintype "bidirectional"))
      (node (ref "IR122") (pin "A") (pinfunction "A_A") (pintype "bidirectional"))
      (node (ref "IR122") (pin "A1") (pinfunction "A_A1") (pintype "bidirectional"))
    )
    (net (code "160") (name "Net-(IR117-K)") (class "Default")
      (node (ref "IR117") (pin "C") (pinfunction "K_C") (pintype "bidirectional"))
      (node (ref "IR118") (pin "A") (pinfunction "A_A") (pintype "bidirectional"))
      (node (ref "IR118") (pin "A1") (pinfunction "A_A1") (pintype "bidirectional"))
    )
    (net (code "161") (name "Net-(IR118-K-PadC)") (class "Default")
      (node (ref "IR118") (pin "C") (pinfunction "K_C") (pintype "bidirectional"))
      (node (ref "IR118") (pin "C1") (pinfunction "K_C1") (pintype "bidirectional"))
      (node (ref "IR119") (pin "A") (pinfunction "A_A") (pintype "bidirectional"))
      (node (ref "IR119") (pin "A1") (pinfunction "A_A1") (pintype "bidirectional"))
    )
    (net (code "162") (name "Net-(IR119-K-PadC)") (class "Default")
      (node (ref "IR119") (pin "C") (pinfunction "K_C") (pintype "bidirectional"))
      (node (ref "IR119") (pin "C1") (pinfunction "K_C1") (pintype "bidirectional"))
      (node (ref "IR125") (pin "A") (pinfunction "A_A") (pintype "bidirectional"))
      (node (ref "IR125") (pin "A1") (pinfunction "A_A1") (pintype "bidirectional"))
    )
    (net (code "163") (name "Net-(IR120-A-PadA1)") (class "Default")
      (node (ref "IR120") (pin "A") (pinfunction "A_A") (pintype "bidirectional"))
      (node (ref "IR120") (pin "A1") (pinfunction "A_A1") (pintype "bidirectional"))
      (node (ref "IR125") (pin "C") (pinfunction "K_C") (pintype "bidirectional"))
      (node (ref "IR125") (pin "C1") (pinfunction "K_C1") (pintype "bidirectional"))
    )
    (net (code "164") (name "Net-(IR120-K-PadC)") (class "Default")
      (node (ref "IR120") (pin "C") (pinfunction "K_C") (pintype "bidirectional"))
      (node (ref "IR120") (pin "C1") (pinfunction "K_C1") (pintype "bidirectional"))
      (node (ref "IR126") (pin "A") (pinfunction "A_A") (pintype "bidirectional"))
      (node (ref "IR126") (pin "A1") (pinfunction "A_A1") (pintype "bidirectional"))
    )
    (net (code "165") (name "Net-(IR122-K-PadC)") (class "Default")
      (node (ref "IR122") (pin "C") (pinfunction "K_C") (pintype "bidirectional"))
      (node (ref "IR122") (pin "C1") (pinfunction "K_C1") (pintype "bidirectional"))
      (node (ref "IR123") (pin "A") (pinfunction "A_A") (pintype "bidirectional"))
      (node (ref "IR123") (pin "A1") (pinfunction "A_A1") (pintype "bidirectional"))
    )
    (net (code "166") (name "Net-(IR123-K-PadC)") (class "Default")
      (node (ref "IR123") (pin "C") (pinfunction "K_C") (pintype "bidirectional"))
      (node (ref "IR123") (pin "C1") (pinfunction "K_C1") (pintype "bidirectional"))
      (node (ref "IR124") (pin "A") (pinfunction "A_A") (pintype "bidirectional"))
    )
    (net (code "167") (name "Net-(IR124-K)") (class "Default")
      (node (ref "IR104") (pin "A") (pinfunction "A_A") (pintype "bidirectional"))
      (node (ref "IR104") (pin "A1") (pinfunction "A_A1") (pintype "bidirectional"))
      (node (ref "IR124") (pin "C") (pinfunction "K_C") (pintype "bidirectional"))
    )
    (net (code "168") (name "Net-(IR126-K-PadC)") (class "Default")
      (node (ref "IR126") (pin "C") (pinfunction "K_C") (pintype "bidirectional"))
      (node (ref "IR126") (pin "C1") (pinfunction "K_C1") (pintype "bidirectional"))
      (node (ref "IR127") (pin "A") (pinfunction "A_A") (pintype "bidirectional"))
      (node (ref "IR127") (pin "A1") (pinfunction "A_A1") (pintype "bidirectional"))
    )
    (net (code "169") (name "Net-(IR127-K-PadC)") (class "Default")
      (node (ref "IR127") (pin "C") (pinfunction "K_C") (pintype "bidirectional"))
      (node (ref "IR127") (pin "C1") (pinfunction "K_C1") (pintype "bidirectional"))
      (node (ref "IR128") (pin "A") (pinfunction "A_A") (pintype "bidirectional"))
    )
    (net (code "170") (name "Net-(IR128-K)") (class "Default")
      (node (ref "IR112") (pin "A") (pinfunction "A_A") (pintype "bidirectional"))
      (node (ref "IR112") (pin "A1") (pinfunction "A_A1") (pintype "bidirectional"))
      (node (ref "IR128") (pin "C") (pinfunction "K_C") (pintype "bidirectional"))
    )
    (net (code "171") (name "Net-(IR129-A-PadA1)") (class "Default")
      (node (ref "IR129") (pin "A") (pinfunction "A_A") (pintype "bidirectional"))
      (node (ref "IR129") (pin "A1") (pinfunction "A_A1") (pintype "bidirectional"))
      (node (ref "IR130") (pin "C") (pinfunction "K_C") (pintype "bidirectional"))
      (node (ref "IR130") (pin "C1") (pinfunction "K_C1") (pintype "bidirectional"))
    )
    (net (code "172") (name "Net-(IR129-K)") (class "Default")
      (node (ref "IR129") (pin "C") (pinfunction "K_C") (pintype "bidirectional"))
      (node (ref "R54") (pin "1") (pinfunction "1_1") (pintype "passive"))
    )
    (net (code "173") (name "Net-(IR130-A-PadA1)") (class "Default")
      (node (ref "IR130") (pin "A") (pinfunction "A_A") (pintype "bidirectional"))
      (node (ref "IR130") (pin "A1") (pinfunction "A_A1") (pintype "bidirectional"))
      (node (ref "IR131") (pin "C") (pinfunction "K_C") (pintype "bidirectional"))
      (node (ref "IR131") (pin "C1") (pinfunction "K_C1") (pintype "bidirectional"))
    )
    (net (code "174") (name "Net-(IR131-A-PadA1)") (class "Default")
      (node (ref "IR131") (pin "A") (pinfunction "A_A") (pintype "bidirectional"))
      (node (ref "IR131") (pin "A1") (pinfunction "A_A1") (pintype "bidirectional"))
      (node (ref "IR132") (pin "C") (pinfunction "K_C") (pintype "bidirectional"))
      (node (ref "IR132") (pin "C1") (pinfunction "K_C1") (pintype "bidirectional"))
    )
    (net (code "175") (name "Net-(IR132-A-PadA1)") (class "Default")
      (node (ref "IR132") (pin "A") (pinfunction "A_A") (pintype "bidirectional"))
      (node (ref "IR132") (pin "A1") (pinfunction "A_A1") (pintype "bidirectional"))
      (node (ref "IR133") (pin "C") (pinfunction "K_C") (pintype "bidirectional"))
      (node (ref "IR133") (pin "C1") (pinfunction "K_C1") (pintype "bidirectional"))
    )
    (net (code "176") (name "Net-(IR133-A-PadA1)") (class "Default")
      (node (ref "IR133") (pin "A") (pinfunction "A_A") (pintype "bidirectional"))
      (node (ref "IR133") (pin "A1") (pinfunction "A_A1") (pintype "bidirectional"))
      (node (ref "IR134") (pin "C") (pinfunction "K_C") (pintype "bidirectional"))
      (node (ref "IR134") (pin "C1") (pinfunction "K_C1") (pintype "bidirectional"))
    )
    (net (code "177") (name "Net-(IR134-A-PadA1)") (class "Default")
      (node (ref "IR134") (pin "A") (pinfunction "A_A") (pintype "bidirectional"))
      (node (ref "IR134") (pin "A1") (pinfunction "A_A1") (pintype "bidirectional"))
      (node (ref "IR135") (pin "C") (pinfunction "K_C") (pintype "bidirectional"))
      (node (ref "IR135") (pin "C1") (pinfunction "K_C1") (pintype "bidirectional"))
    )
    (net (code "178") (name "Net-(IR136-K)") (class "Default")
      (node (ref "IR135") (pin "A") (pinfunction "A_A") (pintype "bidirectional"))
      (node (ref "IR135") (pin "A1") (pinfunction "A_A1") (pintype "bidirectional"))
      (node (ref "IR136") (pin "C") (pinfunction "K_C") (pintype "bidirectional"))
    )
    (net (code "179") (name "Net-(IR136-PadA)") (class "Default")
      (node (ref "IR136") (pin "A") (pinfunction "A_A") (pintype "bidirectional"))
      (node (ref "IR152") (pin "C") (pinfunction "K_C") (pintype "bidirectional"))
      (node (ref "IR152") (pin "C1") (pinfunction "K_C1") (pintype "bidirectional"))
    )
    (net (code "180") (name "Net-(IR137-K)") (class "Default")
      (node (ref "IR137") (pin "C") (pinfunction "K_C") (pintype "bidirectional"))
      (node (ref "R45") (pin "1") (pinfunction "1_1") (pintype "passive"))
    )
    (net (code "181") (name "Net-(IR137-PadA)") (class "Default")
      (node (ref "IR137") (pin "A") (pinfunction "A_A") (pintype "bidirectional"))
      (node (ref "IR138") (pin "C") (pinfunction "K_C") (pintype "bidirectional"))
      (node (ref "IR138") (pin "C1") (pinfunction "K_C1") (pintype "bidirectional"))
    )
    (net (code "182") (name "Net-(IR138-A-PadA1)") (class "Default")
      (node (ref "IR138") (pin "A") (pinfunction "A_A") (pintype "bidirectional"))
      (node (ref "IR138") (pin "A1") (pinfunction "A_A1") (pintype "bidirectional"))
      (node (ref "IR139") (pin "C") (pinfunction "K_C") (pintype "bidirectional"))
      (node (ref "IR139") (pin "C1") (pinfunction "K_C1") (pintype "bidirectional"))
    )
    (net (code "183") (name "Net-(IR139-A-PadA1)") (class "Default")
      (node (ref "IR139") (pin "A") (pinfunction "A_A") (pintype "bidirectional"))
      (node (ref "IR139") (pin "A1") (pinfunction "A_A1") (pintype "bidirectional"))
      (node (ref "IR140") (pin "C") (pinfunction "K_C") (pintype "bidirectional"))
      (node (ref "IR140") (pin "C1") (pinfunction "K_C1") (pintype "bidirectional"))
    )
    (net (code "184") (name "Net-(IR140-A-PadA1)") (class "Default")
      (node (ref "IR140") (pin "A") (pinfunction "A_A") (pintype "bidirectional"))
      (node (ref "IR140") (pin "A1") (pinfunction "A_A1") (pintype "bidirectional"))
      (node (ref "IR141") (pin "C") (pinfunction "K_C") (pintype "bidirectional"))
      (node (ref "IR141") (pin "C1") (pinfunction "K_C1") (pintype "bidirectional"))
    )
    (net (code "185") (name "Net-(IR141-A-PadA1)") (class "Default")
      (node (ref "IR141") (pin "A") (pinfunction "A_A") (pintype "bidirectional"))
      (node (ref "IR141") (pin "A1") (pinfunction "A_A1") (pintype "bidirectional"))
      (node (ref "IR142") (pin "C") (pinfunction "K_C") (pintype "bidirectional"))
      (node (ref "IR142") (pin "C1") (pinfunction "K_C1") (pintype "bidirectional"))
    )
    (net (code "186") (name "Net-(IR142-A-PadA1)") (class "Default")
      (node (ref "IR142") (pin "A") (pinfunction "A_A") (pintype "bidirectional"))
      (node (ref "IR142") (pin "A1") (pinfunction "A_A1") (pintype "bidirectional"))
      (node (ref "IR143") (pin "C") (pinfunction "K_C") (pintype "bidirectional"))
      (node (ref "IR143") (pin "C1") (pinfunction "K_C1") (pintype "bidirectional"))
    )
    (net (code "187") (name "Net-(IR143-A-PadA1)") (class "Default")
      (node (ref "IR143") (pin "A") (pinfunction "A_A") (pintype "bidirectional"))
      (node (ref "IR143") (pin "A1") (pinfunction "A_A1") (pintype "bidirectional"))
      (node (ref "IR144") (pin "C") (pinfunction "K_C") (pintype "bidirectional"))
      (node (ref "IR144") (pin "C1") (pinfunction "K_C1") (pintype "bidirectional"))
    )
    (net (code "188") (name "Net-(IR144-A-PadA1)") (class "Default")
      (node (ref "IR144") (pin "A") (pinfunction "A_A") (pintype "bidirectional"))
      (node (ref "IR144") (pin "A1") (pinfunction "A_A1") (pintype "bidirectional"))
      (node (ref "IR160") (pin "C") (pinfunction "K_C") (pintype "bidirectional"))
      (node (ref "IR160") (pin "C1") (pinfunction "K_C1") (pintype "bidirectional"))
    )
    (net (code "189") (name "Net-(IR145-K-PadC)") (class "Default")
      (node (ref "IR145") (pin "C") (pinfunction "K_C") (pintype "bidirectional"))
      (node (ref "IR145") (pin "C1") (pinfunction "K_C1") (pintype "bidirectional"))
      (node (ref "IR146") (pin "A") (pinfunction "A_A") (pintype "bidirectional"))
      (node (ref "IR146") (pin "A1") (pinfunction "A_A1") (pintype "bidirectional"))
    )
    (net (code "190") (name "Net-(IR146-K-PadC)") (class "Default")
      (node (ref "IR146") (pin "C") (pinfunction "K_C") (pintype "bidirectional"))
      (node (ref "IR146") (pin "C1") (pinfunction "K_C1") (pintype "bidirectional"))
      (node (ref "IR147") (pin "A") (pinfunction "A_A") (pintype "bidirectional"))
      (node (ref "IR147") (pin "A1") (pinfunction "A_A1") (pintype "bidirectional"))
    )
    (net (code "191") (name "Net-(IR147-K-PadC)") (class "Default")
      (node (ref "IR147") (pin "C") (pinfunction "K_C") (pintype "bidirectional"))
      (node (ref "IR147") (pin "C1") (pinfunction "K_C1") (pintype "bidirectional"))
      (node (ref "IR148") (pin "A") (pinfunction "A_A") (pintype "bidirectional"))
      (node (ref "IR148") (pin "A1") (pinfunction "A_A1") (pintype "bidirectional"))
    )
    (net (code "192") (name "Net-(IR148-K-PadC)") (class "Default")
      (node (ref "IR148") (pin "C") (pinfunction "K_C") (pintype "bidirectional"))
      (node (ref "IR148") (pin "C1") (pinfunction "K_C1") (pintype "bidirectional"))
      (node (ref "IR149") (pin "A") (pinfunction "A_A") (pintype "bidirectional"))
      (node (ref "IR149") (pin "A1") (pinfunction "A_A1") (pintype "bidirectional"))
    )
    (net (code "193") (name "Net-(IR149-K-PadC)") (class "Default")
      (node (ref "IR149") (pin "C") (pinfunction "K_C") (pintype "bidirectional"))
      (node (ref "IR149") (pin "C1") (pinfunction "K_C1") (pintype "bidirectional"))
      (node (ref "IR150") (pin "A") (pinfunction "A_A") (pintype "bidirectional"))
      (node (ref "IR150") (pin "A1") (pinfunction "A_A1") (pintype "bidirectional"))
    )
    (net (code "194") (name "Net-(IR150-K-PadC)") (class "Default")
      (node (ref "IR150") (pin "C") (pinfunction "K_C") (pintype "bidirectional"))
      (node (ref "IR150") (pin "C1") (pinfunction "K_C1") (pintype "bidirectional"))
      (node (ref "IR151") (pin "A") (pinfunction "A_A") (pintype "bidirectional"))
      (node (ref "IR151") (pin "A1") (pinfunction "A_A1") (pintype "bidirectional"))
    )
    (net (code "195") (name "Net-(IR151-K-PadC)") (class "Default")
      (node (ref "IR151") (pin "C") (pinfunction "K_C") (pintype "bidirectional"))
      (node (ref "IR151") (pin "C1") (pinfunction "K_C1") (pintype "bidirectional"))
      (node (ref "IR152") (pin "A") (pinfunction "A_A") (pintype "bidirectional"))
      (node (ref "IR152") (pin "A1") (pinfunction "A_A1") (pintype "bidirectional"))
    )
    (net (code "196") (name "Net-(IR153-K-PadC)") (class "Default")
      (node (ref "IR153") (pin "C") (pinfunction "K_C") (pintype "bidirectional"))
      (node (ref "IR153") (pin "C1") (pinfunction "K_C1") (pintype "bidirectional"))
      (node (ref "IR154") (pin "A") (pinfunction "A_A") (pintype "bidirectional"))
      (node (ref "IR154") (pin "A1") (pinfunction "A_A1") (pintype "bidirectional"))
    )
    (net (code "197") (name "Net-(IR154-K)") (class "Default")
      (node (ref "IR154") (pin "C") (pinfunction "K_C") (pintype "bidirectional"))
      (node (ref "IR155") (pin "A") (pinfunction "A_A") (pintype "bidirectional"))
      (node (ref "IR155") (pin "A1") (pinfunction "A_A1") (pintype "bidirectional"))
    )
    (net (code "198") (name "Net-(IR155-K-PadC)") (class "Default")
      (node (ref "IR155") (pin "C") (pinfunction "K_C") (pintype "bidirectional"))
      (node (ref "IR155") (pin "C1") (pinfunction "K_C1") (pintype "bidirectional"))
      (node (ref "IR156") (pin "A") (pinfunction "A_A") (pintype "bidirectional"))
      (node (ref "IR156") (pin "A1") (pinfunction "A_A1") (pintype "bidirectional"))
    )
    (net (code "199") (name "Net-(IR156-K-PadC)") (class "Default")
      (node (ref "IR156") (pin "C") (pinfunction "K_C") (pintype "bidirectional"))
      (node (ref "IR156") (pin "C1") (pinfunction "K_C1") (pintype "bidirectional"))
      (node (ref "IR157") (pin "A") (pinfunction "A_A") (pintype "bidirectional"))
      (node (ref "IR157") (pin "A1") (pinfunction "A_A1") (pintype "bidirectional"))
    )
    (net (code "200") (name "Net-(IR157-K-PadC)") (class "Default")
      (node (ref "IR157") (pin "C") (pinfunction "K_C") (pintype "bidirectional"))
      (node (ref "IR157") (pin "C1") (pinfunction "K_C1") (pintype "bidirectional"))
      (node (ref "IR158") (pin "A") (pinfunction "A_A") (pintype "bidirectional"))
      (node (ref "IR158") (pin "A1") (pinfunction "A_A1") (pintype "bidirectional"))
    )
    (net (code "201") (name "Net-(IR158-K-PadC)") (class "Default")
      (node (ref "IR158") (pin "C") (pinfunction "K_C") (pintype "bidirectional"))
      (node (ref "IR158") (pin "C1") (pinfunction "K_C1") (pintype "bidirectional"))
      (node (ref "IR159") (pin "A") (pinfunction "A_A") (pintype "bidirectional"))
      (node (ref "IR159") (pin "A1") (pinfunction "A_A1") (pintype "bidirectional"))
    )
    (net (code "202") (name "Net-(IR159-K-PadC)") (class "Default")
      (node (ref "IR159") (pin "C") (pinfunction "K_C") (pintype "bidirectional"))
      (node (ref "IR159") (pin "C1") (pinfunction "K_C1") (pintype "bidirectional"))
      (node (ref "IR160") (pin "A") (pinfunction "A_A") (pintype "bidirectional"))
      (node (ref "IR160") (pin "A1") (pinfunction "A_A1") (pintype "bidirectional"))
    )
    (net (code "203") (name "Net-(IR161-A-PadA1)") (class "Default")
      (node (ref "IR161") (pin "A") (pinfunction "A_A") (pintype "bidirectional"))
      (node (ref "IR161") (pin "A1") (pinfunction "A_A1") (pintype "bidirectional"))
      (node (ref "IR162") (pin "C") (pinfunction "K_C") (pintype "bidirectional"))
      (node (ref "IR162") (pin "C1") (pinfunction "K_C1") (pintype "bidirectional"))
    )
    (net (code "204") (name "Net-(IR161-K-PadC)") (class "Default")
      (node (ref "IR161") (pin "C") (pinfunction "K_C") (pintype "bidirectional"))
      (node (ref "IR161") (pin "C1") (pinfunction "K_C1") (pintype "bidirectional"))
      (node (ref "R55") (pin "1") (pinfunction "1_1") (pintype "passive"))
    )
    (net (code "205") (name "Net-(IR162-A-PadA1)") (class "Default")
      (node (ref "IR162") (pin "A") (pinfunction "A_A") (pintype "bidirectional"))
      (node (ref "IR162") (pin "A1") (pinfunction "A_A1") (pintype "bidirectional"))
      (node (ref "IR163") (pin "C") (pinfunction "K_C") (pintype "bidirectional"))
      (node (ref "IR163") (pin "C1") (pinfunction "K_C1") (pintype "bidirectional"))
    )
    (net (code "206") (name "Net-(IR163-A-PadA1)") (class "Default")
      (node (ref "IR163") (pin "A") (pinfunction "A_A") (pintype "bidirectional"))
      (node (ref "IR163") (pin "A1") (pinfunction "A_A1") (pintype "bidirectional"))
      (node (ref "IR164") (pin "C") (pinfunction "K_C") (pintype "bidirectional"))
      (node (ref "IR164") (pin "C1") (pinfunction "K_C1") (pintype "bidirectional"))
    )
    (net (code "207") (name "Net-(IR164-A-PadA1)") (class "Default")
      (node (ref "IR164") (pin "A") (pinfunction "A_A") (pintype "bidirectional"))
      (node (ref "IR164") (pin "A1") (pinfunction "A_A1") (pintype "bidirectional"))
      (node (ref "IR165") (pin "C") (pinfunction "K_C") (pintype "bidirectional"))
      (node (ref "IR165") (pin "C1") (pinfunction "K_C1") (pintype "bidirectional"))
    )
    (net (code "208") (name "Net-(IR165-A-PadA1)") (class "Default")
      (node (ref "IR165") (pin "A") (pinfunction "A_A") (pintype "bidirectional"))
      (node (ref "IR165") (pin "A1") (pinfunction "A_A1") (pintype "bidirectional"))
      (node (ref "IR166") (pin "C") (pinfunction "K_C") (pintype "bidirectional"))
      (node (ref "IR166") (pin "C1") (pinfunction "K_C1") (pintype "bidirectional"))
    )
    (net (code "209") (name "Net-(IR166-A-PadA1)") (class "Default")
      (node (ref "IR166") (pin "A") (pinfunction "A_A") (pintype "bidirectional"))
      (node (ref "IR166") (pin "A1") (pinfunction "A_A1") (pintype "bidirectional"))
      (node (ref "IR167") (pin "C") (pinfunction "K_C") (pintype "bidirectional"))
      (node (ref "IR167") (pin "C1") (pinfunction "K_C1") (pintype "bidirectional"))
    )
    (net (code "210") (name "Net-(IR167-A-PadA1)") (class "Default")
      (node (ref "IR167") (pin "A") (pinfunction "A_A") (pintype "bidirectional"))
      (node (ref "IR167") (pin "A1") (pinfunction "A_A1") (pintype "bidirectional"))
      (node (ref "IR168") (pin "C") (pinfunction "K_C") (pintype "bidirectional"))
      (node (ref "IR168") (pin "C1") (pinfunction "K_C1") (pintype "bidirectional"))
    )
    (net (code "211") (name "Net-(IR168-A-PadA1)") (class "Default")
      (node (ref "IR168") (pin "A") (pinfunction "A_A") (pintype "bidirectional"))
      (node (ref "IR168") (pin "A1") (pinfunction "A_A1") (pintype "bidirectional"))
      (node (ref "IR184") (pin "C") (pinfunction "K_C") (pintype "bidirectional"))
      (node (ref "IR184") (pin "C1") (pinfunction "K_C1") (pintype "bidirectional"))
    )
    (net (code "212") (name "Net-(IR169-A-PadA1)") (class "Default")
      (node (ref "IR169") (pin "A") (pinfunction "A_A") (pintype "bidirectional"))
      (node (ref "IR169") (pin "A1") (pinfunction "A_A1") (pintype "bidirectional"))
      (node (ref "IR170") (pin "C") (pinfunction "K_C") (pintype "bidirectional"))
      (node (ref "IR170") (pin "C1") (pinfunction "K_C1") (pintype "bidirectional"))
    )
    (net (code "213") (name "Net-(IR169-K-PadC)") (class "Default")
      (node (ref "IR169") (pin "C") (pinfunction "K_C") (pintype "bidirectional"))
      (node (ref "IR169") (pin "C1") (pinfunction "K_C1") (pintype "bidirectional"))
      (node (ref "R47") (pin "1") (pinfunction "1_1") (pintype "passive"))
    )
    (net (code "214") (name "Net-(IR170-A-PadA1)") (class "Default")
      (node (ref "IR170") (pin "A") (pinfunction "A_A") (pintype "bidirectional"))
      (node (ref "IR170") (pin "A1") (pinfunction "A_A1") (pintype "bidirectional"))
      (node (ref "IR171") (pin "C") (pinfunction "K_C") (pintype "bidirectional"))
      (node (ref "IR171") (pin "C1") (pinfunction "K_C1") (pintype "bidirectional"))
    )
    (net (code "215") (name "Net-(IR171-A-PadA1)") (class "Default")
      (node (ref "IR171") (pin "A") (pinfunction "A_A") (pintype "bidirectional"))
      (node (ref "IR171") (pin "A1") (pinfunction "A_A1") (pintype "bidirectional"))
      (node (ref "IR172") (pin "C") (pinfunction "K_C") (pintype "bidirectional"))
      (node (ref "IR172") (pin "C1") (pinfunction "K_C1") (pintype "bidirectional"))
    )
    (net (code "216") (name "Net-(IR172-A-PadA1)") (class "Default")
      (node (ref "IR172") (pin "A") (pinfunction "A_A") (pintype "bidirectional"))
      (node (ref "IR172") (pin "A1") (pinfunction "A_A1") (pintype "bidirectional"))
      (node (ref "IR173") (pin "C") (pinfunction "K_C") (pintype "bidirectional"))
      (node (ref "IR173") (pin "C1") (pinfunction "K_C1") (pintype "bidirectional"))
    )
    (net (code "217") (name "Net-(IR173-A-PadA1)") (class "Default")
      (node (ref "IR173") (pin "A") (pinfunction "A_A") (pintype "bidirectional"))
      (node (ref "IR173") (pin "A1") (pinfunction "A_A1") (pintype "bidirectional"))
      (node (ref "IR174") (pin "C") (pinfunction "K_C") (pintype "bidirectional"))
      (node (ref "IR174") (pin "C1") (pinfunction "K_C1") (pintype "bidirectional"))
    )
    (net (code "218") (name "Net-(IR174-A-PadA1)") (class "Default")
      (node (ref "IR174") (pin "A") (pinfunction "A_A") (pintype "bidirectional"))
      (node (ref "IR174") (pin "A1") (pinfunction "A_A1") (pintype "bidirectional"))
      (node (ref "IR175") (pin "C") (pinfunction "K_C") (pintype "bidirectional"))
      (node (ref "IR175") (pin "C1") (pinfunction "K_C1") (pintype "bidirectional"))
    )
    (net (code "219") (name "Net-(IR175-A-PadA1)") (class "Default")
      (node (ref "IR175") (pin "A") (pinfunction "A_A") (pintype "bidirectional"))
      (node (ref "IR175") (pin "A1") (pinfunction "A_A1") (pintype "bidirectional"))
      (node (ref "IR176") (pin "C") (pinfunction "K_C") (pintype "bidirectional"))
      (node (ref "IR176") (pin "C1") (pinfunction "K_C1") (pintype "bidirectional"))
    )
    (net (code "220") (name "Net-(IR176-A-PadA1)") (class "Default")
      (node (ref "IR176") (pin "A") (pinfunction "A_A") (pintype "bidirectional"))
      (node (ref "IR176") (pin "A1") (pinfunction "A_A1") (pintype "bidirectional"))
      (node (ref "IR192") (pin "C") (pinfunction "K_C") (pintype "bidirectional"))
      (node (ref "IR192") (pin "C1") (pinfunction "K_C1") (pintype "bidirectional"))
    )
    (net (code "221") (name "Net-(IR177-K-PadC)") (class "Default")
      (node (ref "IR177") (pin "C") (pinfunction "K_C") (pintype "bidirectional"))
      (node (ref "IR177") (pin "C1") (pinfunction "K_C1") (pintype "bidirectional"))
      (node (ref "IR178") (pin "A") (pinfunction "A_A") (pintype "bidirectional"))
      (node (ref "IR178") (pin "A1") (pinfunction "A_A1") (pintype "bidirectional"))
    )
    (net (code "222") (name "Net-(IR178-K-PadC)") (class "Default")
      (node (ref "IR178") (pin "C") (pinfunction "K_C") (pintype "bidirectional"))
      (node (ref "IR178") (pin "C1") (pinfunction "K_C1") (pintype "bidirectional"))
      (node (ref "IR179") (pin "A") (pinfunction "A_A") (pintype "bidirectional"))
      (node (ref "IR179") (pin "A1") (pinfunction "A_A1") (pintype "bidirectional"))
    )
    (net (code "223") (name "Net-(IR179-K-PadC)") (class "Default")
      (node (ref "IR179") (pin "C") (pinfunction "K_C") (pintype "bidirectional"))
      (node (ref "IR179") (pin "C1") (pinfunction "K_C1") (pintype "bidirectional"))
      (node (ref "IR180") (pin "A") (pinfunction "A_A") (pintype "bidirectional"))
      (node (ref "IR180") (pin "A1") (pinfunction "A_A1") (pintype "bidirectional"))
    )
    (net (code "224") (name "Net-(IR180-K-PadC)") (class "Default")
      (node (ref "IR180") (pin "C") (pinfunction "K_C") (pintype "bidirectional"))
      (node (ref "IR180") (pin "C1") (pinfunction "K_C1") (pintype "bidirectional"))
      (node (ref "IR181") (pin "A") (pinfunction "A_A") (pintype "bidirectional"))
      (node (ref "IR181") (pin "A1") (pinfunction "A_A1") (pintype "bidirectional"))
    )
    (net (code "225") (name "Net-(IR181-K-PadC)") (class "Default")
      (node (ref "IR181") (pin "C") (pinfunction "K_C") (pintype "bidirectional"))
      (node (ref "IR181") (pin "C1") (pinfunction "K_C1") (pintype "bidirectional"))
      (node (ref "IR182") (pin "A") (pinfunction "A_A") (pintype "bidirectional"))
      (node (ref "IR182") (pin "A1") (pinfunction "A_A1") (pintype "bidirectional"))
    )
    (net (code "226") (name "Net-(IR182-K-PadC)") (class "Default")
      (node (ref "IR182") (pin "C") (pinfunction "K_C") (pintype "bidirectional"))
      (node (ref "IR182") (pin "C1") (pinfunction "K_C1") (pintype "bidirectional"))
      (node (ref "IR183") (pin "A") (pinfunction "A_A") (pintype "bidirectional"))
      (node (ref "IR183") (pin "A1") (pinfunction "A_A1") (pintype "bidirectional"))
    )
    (net (code "227") (name "Net-(IR183-K-PadC)") (class "Default")
      (node (ref "IR183") (pin "C") (pinfunction "K_C") (pintype "bidirectional"))
      (node (ref "IR183") (pin "C1") (pinfunction "K_C1") (pintype "bidirectional"))
      (node (ref "IR184") (pin "A") (pinfunction "A_A") (pintype "bidirectional"))
      (node (ref "IR184") (pin "A1") (pinfunction "A_A1") (pintype "bidirectional"))
    )
    (net (code "228") (name "Net-(IR185-K-PadC)") (class "Default")
      (node (ref "IR185") (pin "C") (pinfunction "K_C") (pintype "bidirectional"))
      (node (ref "IR185") (pin "C1") (pinfunction "K_C1") (pintype "bidirectional"))
      (node (ref "IR186") (pin "A") (pinfunction "A_A") (pintype "bidirectional"))
      (node (ref "IR186") (pin "A1") (pinfunction "A_A1") (pintype "bidirectional"))
    )
    (net (code "229") (name "Net-(IR186-K-PadC)") (class "Default")
      (node (ref "IR186") (pin "C") (pinfunction "K_C") (pintype "bidirectional"))
      (node (ref "IR186") (pin "C1") (pinfunction "K_C1") (pintype "bidirectional"))
      (node (ref "IR187") (pin "A") (pinfunction "A_A") (pintype "bidirectional"))
      (node (ref "IR187") (pin "A1") (pinfunction "A_A1") (pintype "bidirectional"))
    )
    (net (code "230") (name "Net-(IR187-K-PadC)") (class "Default")
      (node (ref "IR187") (pin "C") (pinfunction "K_C") (pintype "bidirectional"))
      (node (ref "IR187") (pin "C1") (pinfunction "K_C1") (pintype "bidirectional"))
      (node (ref "IR188") (pin "A") (pinfunction "A_A") (pintype "bidirectional"))
      (node (ref "IR188") (pin "A1") (pinfunction "A_A1") (pintype "bidirectional"))
    )
    (net (code "231") (name "Net-(IR188-K-PadC)") (class "Default")
      (node (ref "IR188") (pin "C") (pinfunction "K_C") (pintype "bidirectional"))
      (node (ref "IR188") (pin "C1") (pinfunction "K_C1") (pintype "bidirectional"))
      (node (ref "IR189") (pin "A") (pinfunction "A_A") (pintype "bidirectional"))
      (node (ref "IR189") (pin "A1") (pinfunction "A_A1") (pintype "bidirectional"))
    )
    (net (code "232") (name "Net-(IR189-K-PadC)") (class "Default")
      (node (ref "IR189") (pin "C") (pinfunction "K_C") (pintype "bidirectional"))
      (node (ref "IR189") (pin "C1") (pinfunction "K_C1") (pintype "bidirectional"))
      (node (ref "IR190") (pin "A") (pinfunction "A_A") (pintype "bidirectional"))
      (node (ref "IR190") (pin "A1") (pinfunction "A_A1") (pintype "bidirectional"))
    )
    (net (code "233") (name "Net-(IR190-K-PadC)") (class "Default")
      (node (ref "IR190") (pin "C") (pinfunction "K_C") (pintype "bidirectional"))
      (node (ref "IR190") (pin "C1") (pinfunction "K_C1") (pintype "bidirectional"))
      (node (ref "IR191") (pin "A") (pinfunction "A_A") (pintype "bidirectional"))
      (node (ref "IR191") (pin "A1") (pinfunction "A_A1") (pintype "bidirectional"))
    )
    (net (code "234") (name "Net-(IR191-K-PadC)") (class "Default")
      (node (ref "IR191") (pin "C") (pinfunction "K_C") (pintype "bidirectional"))
      (node (ref "IR191") (pin "C1") (pinfunction "K_C1") (pintype "bidirectional"))
      (node (ref "IR192") (pin "A") (pinfunction "A_A") (pintype "bidirectional"))
      (node (ref "IR192") (pin "A1") (pinfunction "A_A1") (pintype "bidirectional"))
    )
    (net (code "235") (name "Net-(IR193-A-PadA1)") (class "Default")
      (node (ref "IR193") (pin "A") (pinfunction "A_A") (pintype "bidirectional"))
      (node (ref "IR193") (pin "A1") (pinfunction "A_A1") (pintype "bidirectional"))
      (node (ref "IR194") (pin "C") (pinfunction "K_C") (pintype "bidirectional"))
      (node (ref "IR194") (pin "C1") (pinfunction "K_C1") (pintype "bidirectional"))
    )
    (net (code "236") (name "Net-(IR193-K-PadC)") (class "Default")
      (node (ref "IR193") (pin "C") (pinfunction "K_C") (pintype "bidirectional"))
      (node (ref "IR193") (pin "C1") (pinfunction "K_C1") (pintype "bidirectional"))
      (node (ref "R56") (pin "1") (pinfunction "1_1") (pintype "passive"))
    )
    (net (code "237") (name "Net-(IR194-A-PadA1)") (class "Default")
      (node (ref "IR194") (pin "A") (pinfunction "A_A") (pintype "bidirectional"))
      (node (ref "IR194") (pin "A1") (pinfunction "A_A1") (pintype "bidirectional"))
      (node (ref "IR195") (pin "C") (pinfunction "K_C") (pintype "bidirectional"))
      (node (ref "IR195") (pin "C1") (pinfunction "K_C1") (pintype "bidirectional"))
    )
    (net (code "238") (name "Net-(IR195-A-PadA1)") (class "Default")
      (node (ref "IR195") (pin "A") (pinfunction "A_A") (pintype "bidirectional"))
      (node (ref "IR195") (pin "A1") (pinfunction "A_A1") (pintype "bidirectional"))
      (node (ref "IR196") (pin "C") (pinfunction "K_C") (pintype "bidirectional"))
      (node (ref "IR196") (pin "C1") (pinfunction "K_C1") (pintype "bidirectional"))
    )
    (net (code "239") (name "Net-(IR196-A-PadA1)") (class "Default")
      (node (ref "IR196") (pin "A") (pinfunction "A_A") (pintype "bidirectional"))
      (node (ref "IR196") (pin "A1") (pinfunction "A_A1") (pintype "bidirectional"))
      (node (ref "IR197") (pin "C") (pinfunction "K_C") (pintype "bidirectional"))
      (node (ref "IR197") (pin "C1") (pinfunction "K_C1") (pintype "bidirectional"))
    )
    (net (code "240") (name "Net-(IR197-A-PadA1)") (class "Default")
      (node (ref "IR197") (pin "A") (pinfunction "A_A") (pintype "bidirectional"))
      (node (ref "IR197") (pin "A1") (pinfunction "A_A1") (pintype "bidirectional"))
      (node (ref "IR198") (pin "C") (pinfunction "K_C") (pintype "bidirectional"))
      (node (ref "IR198") (pin "C1") (pinfunction "K_C1") (pintype "bidirectional"))
    )
    (net (code "241") (name "Net-(IR198-A-PadA1)") (class "Default")
      (node (ref "IR198") (pin "A") (pinfunction "A_A") (pintype "bidirectional"))
      (node (ref "IR198") (pin "A1") (pinfunction "A_A1") (pintype "bidirectional"))
      (node (ref "IR199") (pin "C") (pinfunction "K_C") (pintype "bidirectional"))
      (node (ref "IR199") (pin "C1") (pinfunction "K_C1") (pintype "bidirectional"))
    )
    (net (code "242") (name "Net-(IR199-A-PadA1)") (class "Default")
      (node (ref "IR199") (pin "A") (pinfunction "A_A") (pintype "bidirectional"))
      (node (ref "IR199") (pin "A1") (pinfunction "A_A1") (pintype "bidirectional"))
      (node (ref "IR200") (pin "C") (pinfunction "K_C") (pintype "bidirectional"))
      (node (ref "IR200") (pin "C1") (pinfunction "K_C1") (pintype "bidirectional"))
    )
    (net (code "243") (name "Net-(IR200-A-PadA1)") (class "Default")
      (node (ref "IR200") (pin "A") (pinfunction "A_A") (pintype "bidirectional"))
      (node (ref "IR200") (pin "A1") (pinfunction "A_A1") (pintype "bidirectional"))
      (node (ref "IR216") (pin "C") (pinfunction "K_C") (pintype "bidirectional"))
      (node (ref "IR216") (pin "C1") (pinfunction "K_C1") (pintype "bidirectional"))
    )
    (net (code "244") (name "Net-(IR201-A-PadA1)") (class "Default")
      (node (ref "IR201") (pin "A") (pinfunction "A_A") (pintype "bidirectional"))
      (node (ref "IR201") (pin "A1") (pinfunction "A_A1") (pintype "bidirectional"))
      (node (ref "IR202") (pin "C") (pinfunction "K_C") (pintype "bidirectional"))
      (node (ref "IR202") (pin "C1") (pinfunction "K_C1") (pintype "bidirectional"))
    )
    (net (code "245") (name "Net-(IR201-K-PadC)") (class "Default")
      (node (ref "IR201") (pin "C") (pinfunction "K_C") (pintype "bidirectional"))
      (node (ref "IR201") (pin "C1") (pinfunction "K_C1") (pintype "bidirectional"))
      (node (ref "R51") (pin "1") (pinfunction "1_1") (pintype "passive"))
    )
    (net (code "246") (name "Net-(IR202-A-PadA1)") (class "Default")
      (node (ref "IR202") (pin "A") (pinfunction "A_A") (pintype "bidirectional"))
      (node (ref "IR202") (pin "A1") (pinfunction "A_A1") (pintype "bidirectional"))
      (node (ref "IR203") (pin "C") (pinfunction "K_C") (pintype "bidirectional"))
      (node (ref "IR203") (pin "C1") (pinfunction "K_C1") (pintype "bidirectional"))
    )
    (net (code "247") (name "Net-(IR203-A-PadA1)") (class "Default")
      (node (ref "IR203") (pin "A") (pinfunction "A_A") (pintype "bidirectional"))
      (node (ref "IR203") (pin "A1") (pinfunction "A_A1") (pintype "bidirectional"))
      (node (ref "IR204") (pin "C") (pinfunction "K_C") (pintype "bidirectional"))
      (node (ref "IR204") (pin "C1") (pinfunction "K_C1") (pintype "bidirectional"))
    )
    (net (code "248") (name "Net-(IR204-A-PadA1)") (class "Default")
      (node (ref "IR204") (pin "A") (pinfunction "A_A") (pintype "bidirectional"))
      (node (ref "IR204") (pin "A1") (pinfunction "A_A1") (pintype "bidirectional"))
      (node (ref "IR205") (pin "C") (pinfunction "K_C") (pintype "bidirectional"))
      (node (ref "IR205") (pin "C1") (pinfunction "K_C1") (pintype "bidirectional"))
    )
    (net (code "249") (name "Net-(IR205-A-PadA1)") (class "Default")
      (node (ref "IR205") (pin "A") (pinfunction "A_A") (pintype "bidirectional"))
      (node (ref "IR205") (pin "A1") (pinfunction "A_A1") (pintype "bidirectional"))
      (node (ref "IR206") (pin "C") (pinfunction "K_C") (pintype "bidirectional"))
      (node (ref "IR206") (pin "C1") (pinfunction "K_C1") (pintype "bidirectional"))
    )
    (net (code "250") (name "Net-(IR206-A-PadA1)") (class "Default")
      (node (ref "IR206") (pin "A") (pinfunction "A_A") (pintype "bidirectional"))
      (node (ref "IR206") (pin "A1") (pinfunction "A_A1") (pintype "bidirectional"))
      (node (ref "IR207") (pin "C") (pinfunction "K_C") (pintype "bidirectional"))
      (node (ref "IR207") (pin "C1") (pinfunction "K_C1") (pintype "bidirectional"))
    )
    (net (code "251") (name "Net-(IR207-A-PadA1)") (class "Default")
      (node (ref "IR207") (pin "A") (pinfunction "A_A") (pintype "bidirectional"))
      (node (ref "IR207") (pin "A1") (pinfunction "A_A1") (pintype "bidirectional"))
      (node (ref "IR208") (pin "C") (pinfunction "K_C") (pintype "bidirectional"))
      (node (ref "IR208") (pin "C1") (pinfunction "K_C1") (pintype "bidirectional"))
    )
    (net (code "252") (name "Net-(IR208-A-PadA1)") (class "Default")
      (node (ref "IR208") (pin "A") (pinfunction "A_A") (pintype "bidirectional"))
      (node (ref "IR208") (pin "A1") (pinfunction "A_A1") (pintype "bidirectional"))
      (node (ref "IR223") (pin "C") (pinfunction "K_C") (pintype "bidirectional"))
      (node (ref "IR223") (pin "C1") (pinfunction "K_C1") (pintype "bidirectional"))
    )
    (net (code "253") (name "Net-(IR209-K-PadC)") (class "Default")
      (node (ref "IR209") (pin "C") (pinfunction "K_C") (pintype "bidirectional"))
      (node (ref "IR209") (pin "C1") (pinfunction "K_C1") (pintype "bidirectional"))
      (node (ref "IR210") (pin "A") (pinfunction "A_A") (pintype "bidirectional"))
      (node (ref "IR210") (pin "A1") (pinfunction "A_A1") (pintype "bidirectional"))
    )
    (net (code "254") (name "Net-(IR210-K-PadC)") (class "Default")
      (node (ref "IR210") (pin "C") (pinfunction "K_C") (pintype "bidirectional"))
      (node (ref "IR210") (pin "C1") (pinfunction "K_C1") (pintype "bidirectional"))
      (node (ref "IR211") (pin "A") (pinfunction "A_A") (pintype "bidirectional"))
      (node (ref "IR211") (pin "A1") (pinfunction "A_A1") (pintype "bidirectional"))
    )
    (net (code "255") (name "Net-(IR211-K-PadC)") (class "Default")
      (node (ref "IR211") (pin "C") (pinfunction "K_C") (pintype "bidirectional"))
      (node (ref "IR211") (pin "C1") (pinfunction "K_C1") (pintype "bidirectional"))
      (node (ref "IR212") (pin "A") (pinfunction "A_A") (pintype "bidirectional"))
      (node (ref "IR212") (pin "A1") (pinfunction "A_A1") (pintype "bidirectional"))
    )
    (net (code "256") (name "Net-(IR212-K-PadC)") (class "Default")
      (node (ref "IR212") (pin "C") (pinfunction "K_C") (pintype "bidirectional"))
      (node (ref "IR212") (pin "C1") (pinfunction "K_C1") (pintype "bidirectional"))
      (node (ref "IR213") (pin "A") (pinfunction "A_A") (pintype "bidirectional"))
      (node (ref "IR213") (pin "A1") (pinfunction "A_A1") (pintype "bidirectional"))
    )
    (net (code "257") (name "Net-(IR213-K-PadC)") (class "Default")
      (node (ref "IR213") (pin "C") (pinfunction "K_C") (pintype "bidirectional"))
      (node (ref "IR213") (pin "C1") (pinfunction "K_C1") (pintype "bidirectional"))
      (node (ref "IR214") (pin "A") (pinfunction "A_A") (pintype "bidirectional"))
      (node (ref "IR214") (pin "A1") (pinfunction "A_A1") (pintype "bidirectional"))
    )
    (net (code "258") (name "Net-(IR214-K-PadC)") (class "Default")
      (node (ref "IR214") (pin "C") (pinfunction "K_C") (pintype "bidirectional"))
      (node (ref "IR214") (pin "C1") (pinfunction "K_C1") (pintype "bidirectional"))
      (node (ref "IR215") (pin "A") (pinfunction "A_A") (pintype "bidirectional"))
      (node (ref "IR215") (pin "A1") (pinfunction "A_A1") (pintype "bidirectional"))
    )
    (net (code "259") (name "Net-(IR215-K-PadC)") (class "Default")
      (node (ref "IR215") (pin "C") (pinfunction "K_C") (pintype "bidirectional"))
      (node (ref "IR215") (pin "C1") (pinfunction "K_C1") (pintype "bidirectional"))
      (node (ref "IR216") (pin "A") (pinfunction "A_A") (pintype "bidirectional"))
      (node (ref "IR216") (pin "A1") (pinfunction "A_A1") (pintype "bidirectional"))
    )
    (net (code "260") (name "Net-(IR217-K-PadC)") (class "Default")
      (node (ref "IR217") (pin "C") (pinfunction "K_C") (pintype "bidirectional"))
      (node (ref "IR217") (pin "C1") (pinfunction "K_C1") (pintype "bidirectional"))
      (node (ref "IR218") (pin "A") (pinfunction "A_A") (pintype "bidirectional"))
      (node (ref "IR218") (pin "A1") (pinfunction "A_A1") (pintype "bidirectional"))
    )
    (net (code "261") (name "Net-(IR218-K-PadC)") (class "Default")
      (node (ref "IR218") (pin "C") (pinfunction "K_C") (pintype "bidirectional"))
      (node (ref "IR218") (pin "C1") (pinfunction "K_C1") (pintype "bidirectional"))
      (node (ref "IR219") (pin "A") (pinfunction "A_A") (pintype "bidirectional"))
      (node (ref "IR219") (pin "A1") (pinfunction "A_A1") (pintype "bidirectional"))
    )
    (net (code "262") (name "Net-(IR219-K-PadC)") (class "Default")
      (node (ref "IR219") (pin "C") (pinfunction "K_C") (pintype "bidirectional"))
      (node (ref "IR219") (pin "C1") (pinfunction "K_C1") (pintype "bidirectional"))
      (node (ref "IR220") (pin "A") (pinfunction "A_A") (pintype "bidirectional"))
      (node (ref "IR220") (pin "A1") (pinfunction "A_A1") (pintype "bidirectional"))
    )
    (net (code "263") (name "Net-(IR220-K-PadC)") (class "Default")
      (node (ref "IR220") (pin "C") (pinfunction "K_C") (pintype "bidirectional"))
      (node (ref "IR220") (pin "C1") (pinfunction "K_C1") (pintype "bidirectional"))
      (node (ref "IR221") (pin "A") (pinfunction "A_A") (pintype "bidirectional"))
      (node (ref "IR221") (pin "A1") (pinfunction "A_A1") (pintype "bidirectional"))
    )
    (net (code "264") (name "Net-(IR221-K-PadC)") (class "Default")
      (node (ref "IR221") (pin "C") (pinfunction "K_C") (pintype "bidirectional"))
      (node (ref "IR221") (pin "C1") (pinfunction "K_C1") (pintype "bidirectional"))
      (node (ref "IR222") (pin "A") (pinfunction "A_A") (pintype "bidirectional"))
      (node (ref "IR222") (pin "A1") (pinfunction "A_A1") (pintype "bidirectional"))
    )
    (net (code "265") (name "Net-(IR222-K-PadC)") (class "Default")
      (node (ref "IR222") (pin "C") (pinfunction "K_C") (pintype "bidirectional"))
      (node (ref "IR222") (pin "C1") (pinfunction "K_C1") (pintype "bidirectional"))
      (node (ref "IR223") (pin "A") (pinfunction "A_A") (pintype "bidirectional"))
      (node (ref "IR223") (pin "A1") (pinfunction "A_A1") (pintype "bidirectional"))
    )
    (net (code "266") (name "Net-(IR224-A-PadA1)") (class "Default")
      (node (ref "IR224") (pin "A") (pinfunction "A_A") (pintype "bidirectional"))
      (node (ref "IR224") (pin "A1") (pinfunction "A_A1") (pintype "bidirectional"))
      (node (ref "IR225") (pin "C") (pinfunction "K_C") (pintype "bidirectional"))
      (node (ref "IR225") (pin "C1") (pinfunction "K_C1") (pintype "bidirectional"))
    )
    (net (code "267") (name "Net-(IR224-K-PadC)") (class "Default")
      (node (ref "IR224") (pin "C") (pinfunction "K_C") (pintype "bidirectional"))
      (node (ref "IR224") (pin "C1") (pinfunction "K_C1") (pintype "bidirectional"))
      (node (ref "R58") (pin "1") (pinfunction "1_1") (pintype "passive"))
    )
    (net (code "268") (name "Net-(IR225-A-PadA1)") (class "Default")
      (node (ref "IR225") (pin "A") (pinfunction "A_A") (pintype "bidirectional"))
      (node (ref "IR225") (pin "A1") (pinfunction "A_A1") (pintype "bidirectional"))
      (node (ref "IR226") (pin "C") (pinfunction "K_C") (pintype "bidirectional"))
      (node (ref "IR226") (pin "C1") (pinfunction "K_C1") (pintype "bidirectional"))
    )
    (net (code "269") (name "Net-(IR226-A-PadA1)") (class "Default")
      (node (ref "IR226") (pin "A") (pinfunction "A_A") (pintype "bidirectional"))
      (node (ref "IR226") (pin "A1") (pinfunction "A_A1") (pintype "bidirectional"))
      (node (ref "IR227") (pin "C") (pinfunction "K_C") (pintype "bidirectional"))
      (node (ref "IR227") (pin "C1") (pinfunction "K_C1") (pintype "bidirectional"))
    )
    (net (code "270") (name "Net-(IR227-A-PadA1)") (class "Default")
      (node (ref "IR227") (pin "A") (pinfunction "A_A") (pintype "bidirectional"))
      (node (ref "IR227") (pin "A1") (pinfunction "A_A1") (pintype "bidirectional"))
      (node (ref "IR228") (pin "C") (pinfunction "K_C") (pintype "bidirectional"))
      (node (ref "IR228") (pin "C1") (pinfunction "K_C1") (pintype "bidirectional"))
    )
    (net (code "271") (name "Net-(IR228-A-PadA1)") (class "Default")
      (node (ref "IR228") (pin "A") (pinfunction "A_A") (pintype "bidirectional"))
      (node (ref "IR228") (pin "A1") (pinfunction "A_A1") (pintype "bidirectional"))
      (node (ref "IR229") (pin "C") (pinfunction "K_C") (pintype "bidirectional"))
      (node (ref "IR229") (pin "C1") (pinfunction "K_C1") (pintype "bidirectional"))
    )
    (net (code "272") (name "Net-(IR229-A-PadA1)") (class "Default")
      (node (ref "IR229") (pin "A") (pinfunction "A_A") (pintype "bidirectional"))
      (node (ref "IR229") (pin "A1") (pinfunction "A_A1") (pintype "bidirectional"))
      (node (ref "IR230") (pin "C") (pinfunction "K_C") (pintype "bidirectional"))
      (node (ref "IR230") (pin "C1") (pinfunction "K_C1") (pintype "bidirectional"))
    )
    (net (code "273") (name "Net-(IR230-A-PadA1)") (class "Default")
      (node (ref "IR230") (pin "A") (pinfunction "A_A") (pintype "bidirectional"))
      (node (ref "IR230") (pin "A1") (pinfunction "A_A1") (pintype "bidirectional"))
      (node (ref "IR231") (pin "C") (pinfunction "K_C") (pintype "bidirectional"))
      (node (ref "IR231") (pin "C1") (pinfunction "K_C1") (pintype "bidirectional"))
    )
    (net (code "274") (name "Net-(IR232-A-PadA1)") (class "Default")
      (node (ref "IR232") (pin "A") (pinfunction "A_A") (pintype "bidirectional"))
      (node (ref "IR232") (pin "A1") (pinfunction "A_A1") (pintype "bidirectional"))
      (node (ref "IR233") (pin "C") (pinfunction "K_C") (pintype "bidirectional"))
      (node (ref "IR233") (pin "C1") (pinfunction "K_C1") (pintype "bidirectional"))
    )
    (net (code "275") (name "Net-(IR232-K-PadC)") (class "Default")
      (node (ref "IR232") (pin "C") (pinfunction "K_C") (pintype "bidirectional"))
      (node (ref "IR232") (pin "C1") (pinfunction "K_C1") (pintype "bidirectional"))
      (node (ref "R52") (pin "1") (pinfunction "1_1") (pintype "passive"))
    )
    (net (code "276") (name "Net-(IR233-A-PadA1)") (class "Default")
      (node (ref "IR233") (pin "A") (pinfunction "A_A") (pintype "bidirectional"))
      (node (ref "IR233") (pin "A1") (pinfunction "A_A1") (pintype "bidirectional"))
      (node (ref "IR234") (pin "C") (pinfunction "K_C") (pintype "bidirectional"))
      (node (ref "IR234") (pin "C1") (pinfunction "K_C1") (pintype "bidirectional"))
    )
    (net (code "277") (name "Net-(IR234-A-PadA1)") (class "Default")
      (node (ref "IR234") (pin "A") (pinfunction "A_A") (pintype "bidirectional"))
      (node (ref "IR234") (pin "A1") (pinfunction "A_A1") (pintype "bidirectional"))
      (node (ref "IR235") (pin "C") (pinfunction "K_C") (pintype "bidirectional"))
      (node (ref "IR235") (pin "C1") (pinfunction "K_C1") (pintype "bidirectional"))
    )
    (net (code "278") (name "Net-(IR235-A-PadA1)") (class "Default")
      (node (ref "IR235") (pin "A") (pinfunction "A_A") (pintype "bidirectional"))
      (node (ref "IR235") (pin "A1") (pinfunction "A_A1") (pintype "bidirectional"))
      (node (ref "IR236") (pin "C") (pinfunction "K_C") (pintype "bidirectional"))
      (node (ref "IR236") (pin "C1") (pinfunction "K_C1") (pintype "bidirectional"))
    )
    (net (code "279") (name "Net-(IR236-A-PadA1)") (class "Default")
      (node (ref "IR236") (pin "A") (pinfunction "A_A") (pintype "bidirectional"))
      (node (ref "IR236") (pin "A1") (pinfunction "A_A1") (pintype "bidirectional"))
      (node (ref "IR237") (pin "C") (pinfunction "K_C") (pintype "bidirectional"))
      (node (ref "IR237") (pin "C1") (pinfunction "K_C1") (pintype "bidirectional"))
    )
    (net (code "280") (name "Net-(IR237-A-PadA1)") (class "Default")
      (node (ref "IR237") (pin "A") (pinfunction "A_A") (pintype "bidirectional"))
      (node (ref "IR237") (pin "A1") (pinfunction "A_A1") (pintype "bidirectional"))
      (node (ref "IR238") (pin "C") (pinfunction "K_C") (pintype "bidirectional"))
      (node (ref "IR238") (pin "C1") (pinfunction "K_C1") (pintype "bidirectional"))
    )
    (net (code "281") (name "Net-(IR238-A-PadA1)") (class "Default")
      (node (ref "IR238") (pin "A") (pinfunction "A_A") (pintype "bidirectional"))
      (node (ref "IR238") (pin "A1") (pinfunction "A_A1") (pintype "bidirectional"))
      (node (ref "IR239") (pin "C") (pinfunction "K_C") (pintype "bidirectional"))
      (node (ref "IR239") (pin "C1") (pinfunction "K_C1") (pintype "bidirectional"))
    )
    (net (code "282") (name "Net-(IR240-K-PadC)") (class "Default")
      (node (ref "IR240") (pin "C") (pinfunction "K_C") (pintype "bidirectional"))
      (node (ref "IR240") (pin "C1") (pinfunction "K_C1") (pintype "bidirectional"))
      (node (ref "IR241") (pin "A") (pinfunction "A_A") (pintype "bidirectional"))
      (node (ref "IR241") (pin "A1") (pinfunction "A_A1") (pintype "bidirectional"))
    )
    (net (code "283") (name "Net-(IR241-K-PadC)") (class "Default")
      (node (ref "IR241") (pin "C") (pinfunction "K_C") (pintype "bidirectional"))
      (node (ref "IR241") (pin "C1") (pinfunction "K_C1") (pintype "bidirectional"))
      (node (ref "IR242") (pin "A") (pinfunction "A_A") (pintype "bidirectional"))
      (node (ref "IR242") (pin "A1") (pinfunction "A_A1") (pintype "bidirectional"))
    )
    (net (code "284") (name "Net-(IR242-K-PadC)") (class "Default")
      (node (ref "IR242") (pin "C") (pinfunction "K_C") (pintype "bidirectional"))
      (node (ref "IR242") (pin "C1") (pinfunction "K_C1") (pintype "bidirectional"))
      (node (ref "IR248") (pin "A") (pinfunction "A_A") (pintype "bidirectional"))
      (node (ref "IR248") (pin "A1") (pinfunction "A_A1") (pintype "bidirectional"))
    )
    (net (code "285") (name "Net-(IR243-A-PadA1)") (class "Default")
      (node (ref "IR243") (pin "A") (pinfunction "A_A") (pintype "bidirectional"))
      (node (ref "IR243") (pin "A1") (pinfunction "A_A1") (pintype "bidirectional"))
      (node (ref "IR248") (pin "C") (pinfunction "K_C") (pintype "bidirectional"))
      (node (ref "IR248") (pin "C1") (pinfunction "K_C1") (pintype "bidirectional"))
    )
    (net (code "286") (name "Net-(IR243-K-PadC)") (class "Default")
      (node (ref "IR243") (pin "C") (pinfunction "K_C") (pintype "bidirectional"))
      (node (ref "IR243") (pin "C1") (pinfunction "K_C1") (pintype "bidirectional"))
      (node (ref "IR249") (pin "A") (pinfunction "A_A") (pintype "bidirectional"))
      (node (ref "IR249") (pin "A1") (pinfunction "A_A1") (pintype "bidirectional"))
    )
    (net (code "287") (name "Net-(IR244-K-PadC)") (class "Default")
      (node (ref "IR244") (pin "C") (pinfunction "K_C") (pintype "bidirectional"))
      (node (ref "IR244") (pin "C1") (pinfunction "K_C1") (pintype "bidirectional"))
      (node (ref "IR245") (pin "A") (pinfunction "A_A") (pintype "bidirectional"))
      (node (ref "IR245") (pin "A1") (pinfunction "A_A1") (pintype "bidirectional"))
    )
    (net (code "288") (name "Net-(IR245-K-PadC)") (class "Default")
      (node (ref "IR245") (pin "C") (pinfunction "K_C") (pintype "bidirectional"))
      (node (ref "IR245") (pin "C1") (pinfunction "K_C1") (pintype "bidirectional"))
      (node (ref "IR246") (pin "A") (pinfunction "A_A") (pintype "bidirectional"))
      (node (ref "IR246") (pin "A1") (pinfunction "A_A1") (pintype "bidirectional"))
    )
    (net (code "289") (name "Net-(IR246-K-PadC)") (class "Default")
      (node (ref "IR246") (pin "C") (pinfunction "K_C") (pintype "bidirectional"))
      (node (ref "IR246") (pin "C1") (pinfunction "K_C1") (pintype "bidirectional"))
      (node (ref "IR252") (pin "A") (pinfunction "A_A") (pintype "bidirectional"))
      (node (ref "IR252") (pin "A1") (pinfunction "A_A1") (pintype "bidirectional"))
    )
    (net (code "290") (name "Net-(IR247-A-PadA1)") (class "Default")
      (node (ref "IR247") (pin "A") (pinfunction "A_A") (pintype "bidirectional"))
      (node (ref "IR247") (pin "A1") (pinfunction "A_A1") (pintype "bidirectional"))
      (node (ref "IR252") (pin "C") (pinfunction "K_C") (pintype "bidirectional"))
      (node (ref "IR252") (pin "C1") (pinfunction "K_C1") (pintype "bidirectional"))
    )
    (net (code "291") (name "Net-(IR247-K-PadC)") (class "Default")
      (node (ref "IR247") (pin "C") (pinfunction "K_C") (pintype "bidirectional"))
      (node (ref "IR247") (pin "C1") (pinfunction "K_C1") (pintype "bidirectional"))
      (node (ref "IR253") (pin "A") (pinfunction "A_A") (pintype "bidirectional"))
      (node (ref "IR253") (pin "A1") (pinfunction "A_A1") (pintype "bidirectional"))
    )
    (net (code "292") (name "Net-(IR249-K-PadC)") (class "Default")
      (node (ref "IR249") (pin "C") (pinfunction "K_C") (pintype "bidirectional"))
      (node (ref "IR249") (pin "C1") (pinfunction "K_C1") (pintype "bidirectional"))
      (node (ref "IR250") (pin "A") (pinfunction "A_A") (pintype "bidirectional"))
      (node (ref "IR250") (pin "A1") (pinfunction "A_A1") (pintype "bidirectional"))
    )
    (net (code "293") (name "Net-(IR250-K-PadC)") (class "Default")
      (node (ref "IR250") (pin "C") (pinfunction "K_C") (pintype "bidirectional"))
      (node (ref "IR250") (pin "C1") (pinfunction "K_C1") (pintype "bidirectional"))
      (node (ref "IR251") (pin "A") (pinfunction "A_A") (pintype "bidirectional"))
    )
    (net (code "294") (name "Net-(IR251-K)") (class "Default")
      (node (ref "IR231") (pin "A") (pinfunction "A_A") (pintype "bidirectional"))
      (node (ref "IR231") (pin "A1") (pinfunction "A_A1") (pintype "bidirectional"))
      (node (ref "IR251") (pin "C") (pinfunction "K_C") (pintype "bidirectional"))
    )
    (net (code "295") (name "Net-(IR253-K-PadC)") (class "Default")
      (node (ref "IR253") (pin "C") (pinfunction "K_C") (pintype "bidirectional"))
      (node (ref "IR253") (pin "C1") (pinfunction "K_C1") (pintype "bidirectional"))
      (node (ref "IR254") (pin "A") (pinfunction "A_A") (pintype "bidirectional"))
      (node (ref "IR254") (pin "A1") (pinfunction "A_A1") (pintype "bidirectional"))
    )
    (net (code "296") (name "Net-(IR254-K-PadC)") (class "Default")
      (node (ref "IR254") (pin "C") (pinfunction "K_C") (pintype "bidirectional"))
      (node (ref "IR254") (pin "C1") (pinfunction "K_C1") (pintype "bidirectional"))
      (node (ref "IR255") (pin "A") (pinfunction "A_A") (pintype "bidirectional"))
    )
    (net (code "297") (name "Net-(IR255-K)") (class "Default")
      (node (ref "IR239") (pin "A") (pinfunction "A_A") (pintype "bidirectional"))
      (node (ref "IR239") (pin "A1") (pinfunction "A_A1") (pintype "bidirectional"))
      (node (ref "IR255") (pin "C") (pinfunction "K_C") (pintype "bidirectional"))
    )
    (net (code "298") (name "Net-(J5-PadP$2)") (class "Default")
      (node (ref "J5") (pin "P$2") (pinfunction "P$2_P$2") (pintype "bidirectional"))
      (node (ref "R25") (pin "1") (pinfunction "1_1") (pintype "passive"))
    )
    (net (code "299") (name "Net-(Q1-B1)") (class "Default")
      (node (ref "Q1") (pin "2") (pinfunction "B1_2") (pintype "bidirectional"))
      (node (ref "Q1") (pin "4") (pinfunction "B2_4") (pintype "bidirectional"))
      (node (ref "U2") (pin "1") (pinfunction "OUT_1") (pintype "output"))
    )
    (net (code "300") (name "Net-(Q1-E1)") (class "Default")
      (node (ref "Q1") (pin "1") (pinfunction "E1_1") (pintype "bidirectional"))
      (node (ref "R8") (pin "2") (pinfunction "2_2") (pintype "passive"))
    )
    (net (code "301") (name "Net-(Q1-E2)") (class "Default")
      (node (ref "Q1") (pin "3") (pinfunction "E2_3") (pintype "bidirectional"))
      (node (ref "R13") (pin "1") (pinfunction "1_1") (pintype "passive"))
      (node (ref "R7") (pin "2") (pinfunction "2_2") (pintype "passive"))
      (node (ref "U2") (pin "4") (pinfunction "IN-_4") (pintype "input"))
    )
    (net (code "302") (name "Net-(Q2-B1)") (class "Default")
      (node (ref "Q2") (pin "2") (pinfunction "B1_2") (pintype "bidirectional"))
      (node (ref "Q2") (pin "4") (pinfunction "B2_4") (pintype "bidirectional"))
      (node (ref "U1") (pin "1") (pinfunction "OUT_1") (pintype "output"))
    )
    (net (code "303") (name "Net-(Q2-E1)") (class "Default")
      (node (ref "Q2") (pin "1") (pinfunction "E1_1") (pintype "bidirectional"))
      (node (ref "R4") (pin "2") (pinfunction "2_2") (pintype "passive"))
    )
    (net (code "304") (name "Net-(Q2-E2)") (class "Default")
      (node (ref "Q2") (pin "3") (pinfunction "E2_3") (pintype "bidirectional"))
      (node (ref "R15") (pin "1") (pinfunction "1_1") (pintype "passive"))
      (node (ref "R3") (pin "2") (pinfunction "2_2") (pintype "passive"))
      (node (ref "U1") (pin "4") (pinfunction "IN-_4") (pintype "input"))
    )
    (net (code "305") (name "Net-(Q3-B1)") (class "Default")
      (node (ref "Q3") (pin "2") (pinfunction "B1_2") (pintype "bidirectional"))
      (node (ref "Q3") (pin "4") (pinfunction "B2_4") (pintype "bidirectional"))
      (node (ref "U4") (pin "1") (pinfunction "OUT_1") (pintype "output"))
    )
    (net (code "306") (name "Net-(Q3-C1-Pad7)") (class "Default")
      (node (ref "Q3") (pin "7") (pinfunction "C1_7") (pintype "bidirectional"))
      (node (ref "Q3") (pin "78") (pinfunction "C1_78") (pintype "bidirectional"))
      (node (ref "Q3") (pin "78A") (pinfunction "C1_78A") (pintype "bidirectional"))
      (node (ref "Q3") (pin "78B") (pinfunction "C1_78B") (pintype "bidirectional"))
      (node (ref "Q3") (pin "8") (pinfunction "C1_8") (pintype "bidirectional"))
      (node (ref "Q3") (pin "8A") (pinfunction "C1_8A") (pintype "bidirectional"))
      (node (ref "Q3") (pin "8B") (pinfunction "C1_8B") (pintype "bidirectional"))
      (node (ref "Q3") (pin "8C") (pinfunction "C1_8C") (pintype "bidirectional"))
      (node (ref "Q3") (pin "8C1") (pinfunction "C1_8C1") (pintype "bidirectional"))
      (node (ref "Q3") (pin "8C2") (pinfunction "C1_8C2") (pintype "bidirectional"))
      (node (ref "Q3") (pin "8C3") (pinfunction "C1_8C3") (pintype "bidirectional"))
      (node (ref "RGB21") (pin "4") (pinfunction "BC_4") (pintype "bidirectional"))
      (node (ref "RGB21") (pin "4A") (pinfunction "BC_4A") (pintype "bidirectional"))
      (node (ref "RGB21") (pin "4B") (pinfunction "BC_4B") (pintype "bidirectional"))
    )
    (net (code "307") (name "Net-(Q3-C2-Pad5)") (class "Default")
      (node (ref "Q3") (pin "5") (pinfunction "C2_5") (pintype "bidirectional"))
      (node (ref "Q3") (pin "56") (pinfunction "C2_56") (pintype "bidirectional"))
      (node (ref "Q3") (pin "56A") (pinfunction "C2_56A") (pintype "bidirectional"))
      (node (ref "Q3") (pin "56B") (pinfunction "C2_56B") (pintype "bidirectional"))
      (node (ref "Q3") (pin "5A") (pinfunction "C2_5A") (pintype "bidirectional"))
      (node (ref "Q3") (pin "5A1") (pinfunction "C2_5A1") (pintype "bidirectional"))
      (node (ref "Q3") (pin "5B") (pinfunction "C2_5B") (pintype "bidirectional"))
      (node (ref "Q3") (pin "5C") (pinfunction "C2_5C") (pintype "bidirectional"))
      (node (ref "Q3") (pin "5C1") (pinfunction "C2_5C1") (pintype "bidirectional"))
      (node (ref "Q3") (pin "5C2") (pinfunction "C2_5C2") (pintype "bidirectional"))
      (node (ref "Q3") (pin "6") (pinfunction "C2_6") (pintype "bidirectional"))
      (node (ref "RGB5") (pin "4") (pinfunction "BC_4") (pintype "bidirectional"))
      (node (ref "RGB5") (pin "4A") (pinfunction "BC_4A") (pintype "bidirectional"))
      (node (ref "RGB5") (pin "4B") (pinfunction "BC_4B") (pintype "bidirectional"))
    )
    (net (code "308") (name "Net-(Q3-E1)") (class "Default")
      (node (ref "Q3") (pin "1") (pinfunction "E1_1") (pintype "bidirectional"))
      (node (ref "R2") (pin "2") (pinfunction "2_2") (pintype "passive"))
    )
    (net (code "309") (name "Net-(Q3-E2)") (class "Default")
      (node (ref "Q3") (pin "3") (pinfunction "E2_3") (pintype "bidirectional"))
      (node (ref "R1") (pin "2") (pinfunction "2_2") (pintype "passive"))
      (node (ref "R18") (pin "1") (pinfunction "1_1") (pintype "passive"))
      (node (ref "U4") (pin "4") (pinfunction "IN-_4") (pintype "input"))
    )
    (net (code "310") (name "Net-(Q4-B1)") (class "Default")
      (node (ref "Q4") (pin "2") (pinfunction "B1_2") (pintype "bidirectional"))
      (node (ref "Q4") (pin "4") (pinfunction "B2_4") (pintype "bidirectional"))
      (node (ref "U5") (pin "1") (pinfunction "OUT_1") (pintype "output"))
    )
    (net (code "311") (name "Net-(Q4-E1)") (class "Default")
      (node (ref "Q4") (pin "1") (pinfunction "E1_1") (pintype "bidirectional"))
      (node (ref "R6") (pin "2") (pinfunction "2_2") (pintype "passive"))
    )
    (net (code "312") (name "Net-(Q4-E2)") (class "Default")
      (node (ref "Q4") (pin "3") (pinfunction "E2_3") (pintype "bidirectional"))
      (node (ref "R16") (pin "1") (pinfunction "1_1") (pintype "passive"))
      (node (ref "R5") (pin "2") (pinfunction "2_2") (pintype "passive"))
      (node (ref "U5") (pin "4") (pinfunction "IN-_4") (pintype "input"))
    )
    (net (code "313") (name "Net-(Q5-B1)") (class "Default")
      (node (ref "Q5") (pin "2") (pinfunction "B1_2") (pintype "bidirectional"))
      (node (ref "Q5") (pin "4") (pinfunction "B2_4") (pintype "bidirectional"))
      (node (ref "U6") (pin "1") (pinfunction "OUT_1") (pintype "output"))
    )
    (net (code "314") (name "Net-(Q5-C1-Pad7)") (class "Default")
      (node (ref "Q5") (pin "7") (pinfunction "C1_7") (pintype "bidirectional"))
      (node (ref "Q5") (pin "78") (pinfunction "C1_78") (pintype "bidirectional"))
      (node (ref "Q5") (pin "78A") (pinfunction "C1_78A") (pintype "bidirectional"))
      (node (ref "Q5") (pin "78B") (pinfunction "C1_78B") (pintype "bidirectional"))
      (node (ref "Q5") (pin "8") (pinfunction "C1_8") (pintype "bidirectional"))
      (node (ref "Q5") (pin "8A") (pinfunction "C1_8A") (pintype "bidirectional"))
      (node (ref "Q5") (pin "8B") (pinfunction "C1_8B") (pintype "bidirectional"))
      (node (ref "Q5") (pin "8C") (pinfunction "C1_8C") (pintype "bidirectional"))
      (node (ref "Q5") (pin "8C1") (pinfunction "C1_8C1") (pintype "bidirectional"))
      (node (ref "Q5") (pin "8C2") (pinfunction "C1_8C2") (pintype "bidirectional"))
      (node (ref "Q5") (pin "8C3") (pinfunction "C1_8C3") (pintype "bidirectional"))
      (node (ref "RGB21") (pin "5") (pinfunction "RC_5") (pintype "bidirectional"))
      (node (ref "RGB21") (pin "5A") (pinfunction "RC_5A") (pintype "bidirectional"))
      (node (ref "RGB21") (pin "5B") (pinfunction "RC_5B") (pintype "bidirectional"))
    )
    (net (code "315") (name "Net-(Q5-C2-Pad5)") (class "Default")
      (node (ref "Q5") (pin "5") (pinfunction "C2_5") (pintype "bidirectional"))
      (node (ref "Q5") (pin "56") (pinfunction "C2_56") (pintype "bidirectional"))
      (node (ref "Q5") (pin "56A") (pinfunction "C2_56A") (pintype "bidirectional"))
      (node (ref "Q5") (pin "56B") (pinfunction "C2_56B") (pintype "bidirectional"))
      (node (ref "Q5") (pin "5A") (pinfunction "C2_5A") (pintype "bidirectional"))
      (node (ref "Q5") (pin "5A1") (pinfunction "C2_5A1") (pintype "bidirectional"))
      (node (ref "Q5") (pin "5B") (pinfunction "C2_5B") (pintype "bidirectional"))
      (node (ref "Q5") (pin "5C") (pinfunction "C2_5C") (pintype "bidirectional"))
      (node (ref "Q5") (pin "5C1") (pinfunction "C2_5C1") (pintype "bidirectional"))
      (node (ref "Q5") (pin "5C2") (pinfunction "C2_5C2") (pintype "bidirectional"))
      (node (ref "Q5") (pin "6") (pinfunction "C2_6") (pintype "bidirectional"))
      (node (ref "RGB5") (pin "5") (pinfunction "RC_5") (pintype "bidirectional"))
      (node (ref "RGB5") (pin "5A") (pinfunction "RC_5A") (pintype "bidirectional"))
      (node (ref "RGB5") (pin "5B") (pinfunction "RC_5B") (pintype "bidirectional"))
    )
    (net (code "316") (name "Net-(Q5-E1)") (class "Default")
      (node (ref "Q5") (pin "1") (pinfunction "E1_1") (pintype "bidirectional"))
      (node (ref "R10") (pin "2") (pinfunction "2_2") (pintype "passive"))
    )
    (net (code "317") (name "Net-(Q5-E2)") (class "Default")
      (node (ref "Q5") (pin "3") (pinfunction "E2_3") (pintype "bidirectional"))
      (node (ref "R19") (pin "1") (pinfunction "1_1") (pintype "passive"))
      (node (ref "R9") (pin "2") (pinfunction "2_2") (pintype "passive"))
      (node (ref "U6") (pin "4") (pinfunction "IN-_4") (pintype "input"))
    )
    (net (code "318") (name "Net-(Q6-B1)") (class "Default")
      (node (ref "Q6") (pin "2") (pinfunction "B1_2") (pintype "bidirectional"))
      (node (ref "Q6") (pin "4") (pinfunction "B2_4") (pintype "bidirectional"))
      (node (ref "U3") (pin "1") (pinfunction "OUT_1") (pintype "output"))
    )
    (net (code "319") (name "Net-(Q6-C1-Pad7)") (class "Default")
      (node (ref "Q6") (pin "7") (pinfunction "C1_7") (pintype "bidirectional"))
      (node (ref "Q6") (pin "78") (pinfunction "C1_78") (pintype "bidirectional"))
      (node (ref "Q6") (pin "78A") (pinfunction "C1_78A") (pintype "bidirectional"))
      (node (ref "Q6") (pin "78B") (pinfunction "C1_78B") (pintype "bidirectional"))
      (node (ref "Q6") (pin "8") (pinfunction "C1_8") (pintype "bidirectional"))
      (node (ref "Q6") (pin "8A") (pinfunction "C1_8A") (pintype "bidirectional"))
      (node (ref "Q6") (pin "8B") (pinfunction "C1_8B") (pintype "bidirectional"))
      (node (ref "Q6") (pin "8C") (pinfunction "C1_8C") (pintype "bidirectional"))
      (node (ref "Q6") (pin "8C1") (pinfunction "C1_8C1") (pintype "bidirectional"))
      (node (ref "Q6") (pin "8C2") (pinfunction "C1_8C2") (pintype "bidirectional"))
      (node (ref "Q6") (pin "8C3") (pinfunction "C1_8C3") (pintype "bidirectional"))
      (node (ref "RGB21") (pin "6") (pinfunction "GC_6") (pintype "bidirectional"))
      (node (ref "RGB21") (pin "6A") (pinfunction "GC_6A") (pintype "bidirectional"))
      (node (ref "RGB21") (pin "6B") (pinfunction "GC_6B") (pintype "bidirectional"))
    )
    (net (code "320") (name "Net-(Q6-C2-Pad5)") (class "Default")
      (node (ref "Q6") (pin "5") (pinfunction "C2_5") (pintype "bidirectional"))
      (node (ref "Q6") (pin "56") (pinfunction "C2_56") (pintype "bidirectional"))
      (node (ref "Q6") (pin "56A") (pinfunction "C2_56A") (pintype "bidirectional"))
      (node (ref "Q6") (pin "56B") (pinfunction "C2_56B") (pintype "bidirectional"))
      (node (ref "Q6") (pin "5A") (pinfunction "C2_5A") (pintype "bidirectional"))
      (node (ref "Q6") (pin "5A1") (pinfunction "C2_5A1") (pintype "bidirectional"))
      (node (ref "Q6") (pin "5B") (pinfunction "C2_5B") (pintype "bidirectional"))
      (node (ref "Q6") (pin "5C") (pinfunction "C2_5C") (pintype "bidirectional"))
      (node (ref "Q6") (pin "5C1") (pinfunction "C2_5C1") (pintype "bidirectional"))
      (node (ref "Q6") (pin "5C2") (pinfunction "C2_5C2") (pintype "bidirectional"))
      (node (ref "Q6") (pin "6") (pinfunction "C2_6") (pintype "bidirectional"))
      (node (ref "RGB5") (pin "6") (pinfunction "GC_6") (pintype "bidirectional"))
      (node (ref "RGB5") (pin "6A") (pinfunction "GC_6A") (pintype "bidirectional"))
      (node (ref "RGB5") (pin "6B") (pinfunction "GC_6B") (pintype "bidirectional"))
    )
    (net (code "321") (name "Net-(Q6-E1)") (class "Default")
      (node (ref "Q6") (pin "1") (pinfunction "E1_1") (pintype "bidirectional"))
      (node (ref "R12") (pin "2") (pinfunction "2_2") (pintype "passive"))
    )
    (net (code "322") (name "Net-(Q6-E2)") (class "Default")
      (node (ref "Q6") (pin "3") (pinfunction "E2_3") (pintype "bidirectional"))
      (node (ref "R11") (pin "2") (pinfunction "2_2") (pintype "passive"))
      (node (ref "R14") (pin "1") (pinfunction "1_1") (pintype "passive"))
      (node (ref "U3") (pin "4") (pinfunction "IN-_4") (pintype "input"))
    )
    (net (code "323") (name "Net-(Q7-B1)") (class "Default")
      (node (ref "Q7") (pin "2") (pinfunction "B1_2") (pintype "bidirectional"))
      (node (ref "Q7") (pin "4") (pinfunction "B2_4") (pintype "bidirectional"))
      (node (ref "U13") (pin "1") (pinfunction "OUT_1") (pintype "output"))
    )
    (net (code "324") (name "Net-(Q7-E1)") (class "Default")
      (node (ref "Q7") (pin "1") (pinfunction "E1_1") (pintype "bidirectional"))
      (node (ref "R24") (pin "2") (pinfunction "2_2") (pintype "passive"))
    )
    (net (code "325") (name "Net-(Q7-E2)") (class "Default")
      (node (ref "Q7") (pin "3") (pinfunction "E2_3") (pintype "bidirectional"))
      (node (ref "R26") (pin "2") (pinfunction "2_2") (pintype "passive"))
      (node (ref "R28") (pin "1") (pinfunction "1_1") (pintype "passive"))
      (node (ref "U13") (pin "4") (pinfunction "IN-_4") (pintype "input"))
    )
    (net (code "326") (name "Net-(Q8-B1)") (class "Default")
      (node (ref "Q8") (pin "2") (pinfunction "B1_2") (pintype "bidirectional"))
      (node (ref "Q8") (pin "4") (pinfunction "B2_4") (pintype "bidirectional"))
      (node (ref "U14") (pin "1") (pinfunction "OUT_1") (pintype "output"))
    )
    (net (code "327") (name "Net-(Q8-E1)") (class "Default")
      (node (ref "Q8") (pin "1") (pinfunction "E1_1") (pintype "bidirectional"))
      (node (ref "R29") (pin "2") (pinfunction "2_2") (pintype "passive"))
    )
    (net (code "328") (name "Net-(Q8-E2)") (class "Default")
      (node (ref "Q8") (pin "3") (pinfunction "E2_3") (pintype "bidirectional"))
      (node (ref "R30") (pin "2") (pinfunction "2_2") (pintype "passive"))
      (node (ref "R31") (pin "1") (pinfunction "1_1") (pintype "passive"))
      (node (ref "U14") (pin "4") (pinfunction "IN-_4") (pintype "input"))
    )
    (net (code "329") (name "Net-(Q9-B1)") (class "Default")
      (node (ref "Q9") (pin "2") (pinfunction "B1_2") (pintype "bidirectional"))
      (node (ref "Q9") (pin "4") (pinfunction "B2_4") (pintype "bidirectional"))
      (node (ref "U16") (pin "1") (pinfunction "OUT_1") (pintype "output"))
    )
    (net (code "330") (name "Net-(Q9-E1)") (class "Default")
      (node (ref "Q9") (pin "1") (pinfunction "E1_1") (pintype "bidirectional"))
      (node (ref "R33") (pin "2") (pinfunction "2_2") (pintype "passive"))
    )
    (net (code "331") (name "Net-(Q9-E2)") (class "Default")
      (node (ref "Q9") (pin "3") (pinfunction "E2_3") (pintype "bidirectional"))
      (node (ref "R35") (pin "2") (pinfunction "2_2") (pintype "passive"))
      (node (ref "R40") (pin "1") (pinfunction "1_1") (pintype "passive"))
      (node (ref "U16") (pin "4") (pinfunction "IN-_4") (pintype "input"))
    )
    (net (code "332") (name "Net-(Q10-B1)") (class "Default")
      (node (ref "Q10") (pin "2") (pinfunction "B1_2") (pintype "bidirectional"))
      (node (ref "Q10") (pin "4") (pinfunction "B2_4") (pintype "bidirectional"))
      (node (ref "U18") (pin "1") (pinfunction "OUT_1") (pintype "output"))
    )
    (net (code "333") (name "Net-(Q10-C1-Pad7)") (class "Default")
      (node (ref "Q10") (pin "7") (pinfunction "C1_7") (pintype "bidirectional"))
      (node (ref "Q10") (pin "78") (pinfunction "C1_78") (pintype "bidirectional"))
      (node (ref "Q10") (pin "78A") (pinfunction "C1_78A") (pintype "bidirectional"))
      (node (ref "Q10") (pin "78B") (pinfunction "C1_78B") (pintype "bidirectional"))
      (node (ref "Q10") (pin "8") (pinfunction "C1_8") (pintype "bidirectional"))
      (node (ref "Q10") (pin "8A") (pinfunction "C1_8A") (pintype "bidirectional"))
      (node (ref "Q10") (pin "8B") (pinfunction "C1_8B") (pintype "bidirectional"))
      (node (ref "Q10") (pin "8C") (pinfunction "C1_8C") (pintype "bidirectional"))
      (node (ref "Q10") (pin "8C1") (pinfunction "C1_8C1") (pintype "bidirectional"))
      (node (ref "Q10") (pin "8C2") (pinfunction "C1_8C2") (pintype "bidirectional"))
      (node (ref "Q10") (pin "8C3") (pinfunction "C1_8C3") (pintype "bidirectional"))
      (node (ref "RGB33") (pin "4") (pinfunction "BC_4") (pintype "bidirectional"))
      (node (ref "RGB33") (pin "4A") (pinfunction "BC_4A") (pintype "bidirectional"))
      (node (ref "RGB33") (pin "4B") (pinfunction "BC_4B") (pintype "bidirectional"))
    )
    (net (code "334") (name "Net-(Q10-C2-Pad5)") (class "Default")
      (node (ref "Q10") (pin "5") (pinfunction "C2_5") (pintype "bidirectional"))
      (node (ref "Q10") (pin "56") (pinfunction "C2_56") (pintype "bidirectional"))
      (node (ref "Q10") (pin "56A") (pinfunction "C2_56A") (pintype "bidirectional"))
      (node (ref "Q10") (pin "56B") (pinfunction "C2_56B") (pintype "bidirectional"))
      (node (ref "Q10") (pin "5A") (pinfunction "C2_5A") (pintype "bidirectional"))
      (node (ref "Q10") (pin "5A1") (pinfunction "C2_5A1") (pintype "bidirectional"))
      (node (ref "Q10") (pin "5B") (pinfunction "C2_5B") (pintype "bidirectional"))
      (node (ref "Q10") (pin "5C") (pinfunction "C2_5C") (pintype "bidirectional"))
      (node (ref "Q10") (pin "5C1") (pinfunction "C2_5C1") (pintype "bidirectional"))
      (node (ref "Q10") (pin "5C2") (pinfunction "C2_5C2") (pintype "bidirectional"))
      (node (ref "Q10") (pin "6") (pinfunction "C2_6") (pintype "bidirectional"))
      (node (ref "RGB49") (pin "4") (pinfunction "BC_4") (pintype "bidirectional"))
      (node (ref "RGB49") (pin "4A") (pinfunction "BC_4A") (pintype "bidirectional"))
      (node (ref "RGB49") (pin "4B") (pinfunction "BC_4B") (pintype "bidirectional"))
    )
    (net (code "335") (name "Net-(Q10-E1)") (class "Default")
      (node (ref "Q10") (pin "1") (pinfunction "E1_1") (pintype "bidirectional"))
      (node (ref "R43") (pin "2") (pinfunction "2_2") (pintype "passive"))
    )
    (net (code "336") (name "Net-(Q10-E2)") (class "Default")
      (node (ref "Q10") (pin "3") (pinfunction "E2_3") (pintype "bidirectional"))
      (node (ref "R44") (pin "2") (pinfunction "2_2") (pintype "passive"))
      (node (ref "R46") (pin "1") (pinfunction "1_1") (pintype "passive"))
      (node (ref "U18") (pin "4") (pinfunction "IN-_4") (pintype "input"))
    )
    (net (code "337") (name "Net-(Q11-B1)") (class "Default")
      (node (ref "Q11") (pin "2") (pinfunction "B1_2") (pintype "bidirectional"))
      (node (ref "Q11") (pin "4") (pinfunction "B2_4") (pintype "bidirectional"))
      (node (ref "U20") (pin "1") (pinfunction "OUT_1") (pintype "output"))
    )
    (net (code "338") (name "Net-(Q11-C1-Pad7)") (class "Default")
      (node (ref "Q11") (pin "7") (pinfunction "C1_7") (pintype "bidirectional"))
      (node (ref "Q11") (pin "78") (pinfunction "C1_78") (pintype "bidirectional"))
      (node (ref "Q11") (pin "78A") (pinfunction "C1_78A") (pintype "bidirectional"))
      (node (ref "Q11") (pin "78B") (pinfunction "C1_78B") (pintype "bidirectional"))
      (node (ref "Q11") (pin "8") (pinfunction "C1_8") (pintype "bidirectional"))
      (node (ref "Q11") (pin "8A") (pinfunction "C1_8A") (pintype "bidirectional"))
      (node (ref "Q11") (pin "8B") (pinfunction "C1_8B") (pintype "bidirectional"))
      (node (ref "Q11") (pin "8C") (pinfunction "C1_8C") (pintype "bidirectional"))
      (node (ref "Q11") (pin "8C1") (pinfunction "C1_8C1") (pintype "bidirectional"))
      (node (ref "Q11") (pin "8C2") (pinfunction "C1_8C2") (pintype "bidirectional"))
      (node (ref "Q11") (pin "8C3") (pinfunction "C1_8C3") (pintype "bidirectional"))
      (node (ref "RGB33") (pin "5") (pinfunction "RC_5") (pintype "bidirectional"))
      (node (ref "RGB33") (pin "5A") (pinfunction "RC_5A") (pintype "bidirectional"))
      (node (ref "RGB33") (pin "5B") (pinfunction "RC_5B") (pintype "bidirectional"))
    )
    (net (code "339") (name "Net-(Q11-C2-Pad5)") (class "Default")
      (node (ref "Q11") (pin "5") (pinfunction "C2_5") (pintype "bidirectional"))
      (node (ref "Q11") (pin "56") (pinfunction "C2_56") (pintype "bidirectional"))
      (node (ref "Q11") (pin "56A") (pinfunction "C2_56A") (pintype "bidirectional"))
      (node (ref "Q11") (pin "56B") (pinfunction "C2_56B") (pintype "bidirectional"))
      (node (ref "Q11") (pin "5A") (pinfunction "C2_5A") (pintype "bidirectional"))
      (node (ref "Q11") (pin "5A1") (pinfunction "C2_5A1") (pintype "bidirectional"))
      (node (ref "Q11") (pin "5B") (pinfunction "C2_5B") (pintype "bidirectional"))
      (node (ref "Q11") (pin "5C") (pinfunction "C2_5C") (pintype "bidirectional"))
      (node (ref "Q11") (pin "5C1") (pinfunction "C2_5C1") (pintype "bidirectional"))
      (node (ref "Q11") (pin "5C2") (pinfunction "C2_5C2") (pintype "bidirectional"))
      (node (ref "Q11") (pin "6") (pinfunction "C2_6") (pintype "bidirectional"))
      (node (ref "RGB49") (pin "5") (pinfunction "RC_5") (pintype "bidirectional"))
      (node (ref "RGB49") (pin "5A") (pinfunction "RC_5A") (pintype "bidirectional"))
      (node (ref "RGB49") (pin "5B") (pinfunction "RC_5B") (pintype "bidirectional"))
    )
    (net (code "340") (name "Net-(Q11-E1)") (class "Default")
      (node (ref "Q11") (pin "1") (pinfunction "E1_1") (pintype "bidirectional"))
      (node (ref "R48") (pin "2") (pinfunction "2_2") (pintype "passive"))
    )
    (net (code "341") (name "Net-(Q11-E2)") (class "Default")
      (node (ref "Q11") (pin "3") (pinfunction "E2_3") (pintype "bidirectional"))
      (node (ref "R49") (pin "2") (pinfunction "2_2") (pintype "passive"))
      (node (ref "R50") (pin "1") (pinfunction "1_1") (pintype "passive"))
      (node (ref "U20") (pin "4") (pinfunction "IN-_4") (pintype "input"))
    )
    (net (code "342") (name "Net-(Q12-B1)") (class "Default")
      (node (ref "Q12") (pin "2") (pinfunction "B1_2") (pintype "bidirectional"))
      (node (ref "Q12") (pin "4") (pinfunction "B2_4") (pintype "bidirectional"))
      (node (ref "U21") (pin "1") (pinfunction "OUT_1") (pintype "output"))
    )
    (net (code "343") (name "Net-(Q12-C1-Pad7)") (class "Default")
      (node (ref "Q12") (pin "7") (pinfunction "C1_7") (pintype "bidirectional"))
      (node (ref "Q12") (pin "78") (pinfunction "C1_78") (pintype "bidirectional"))
      (node (ref "Q12") (pin "78A") (pinfunction "C1_78A") (pintype "bidirectional"))
      (node (ref "Q12") (pin "78B") (pinfunction "C1_78B") (pintype "bidirectional"))
      (node (ref "Q12") (pin "8") (pinfunction "C1_8") (pintype "bidirectional"))
      (node (ref "Q12") (pin "8A") (pinfunction "C1_8A") (pintype "bidirectional"))
      (node (ref "Q12") (pin "8B") (pinfunction "C1_8B") (pintype "bidirectional"))
      (node (ref "Q12") (pin "8C") (pinfunction "C1_8C") (pintype "bidirectional"))
      (node (ref "Q12") (pin "8C1") (pinfunction "C1_8C1") (pintype "bidirectional"))
      (node (ref "Q12") (pin "8C2") (pinfunction "C1_8C2") (pintype "bidirectional"))
      (node (ref "Q12") (pin "8C3") (pinfunction "C1_8C3") (pintype "bidirectional"))
      (node (ref "RGB33") (pin "6") (pinfunction "GC_6") (pintype "bidirectional"))
      (node (ref "RGB33") (pin "6A") (pinfunction "GC_6A") (pintype "bidirectional"))
      (node (ref "RGB33") (pin "6B") (pinfunction "GC_6B") (pintype "bidirectional"))
    )
    (net (code "344") (name "Net-(Q12-C2-Pad5)") (class "Default")
      (node (ref "Q12") (pin "5") (pinfunction "C2_5") (pintype "bidirectional"))
      (node (ref "Q12") (pin "56") (pinfunction "C2_56") (pintype "bidirectional"))
      (node (ref "Q12") (pin "56A") (pinfunction "C2_56A") (pintype "bidirectional"))
      (node (ref "Q12") (pin "56B") (pinfunction "C2_56B") (pintype "bidirectional"))
      (node (ref "Q12") (pin "5A") (pinfunction "C2_5A") (pintype "bidirectional"))
      (node (ref "Q12") (pin "5A1") (pinfunction "C2_5A1") (pintype "bidirectional"))
      (node (ref "Q12") (pin "5B") (pinfunction "C2_5B") (pintype "bidirectional"))
      (node (ref "Q12") (pin "5C") (pinfunction "C2_5C") (pintype "bidirectional"))
      (node (ref "Q12") (pin "5C1") (pinfunction "C2_5C1") (pintype "bidirectional"))
      (node (ref "Q12") (pin "5C2") (pinfunction "C2_5C2") (pintype "bidirectional"))
      (node (ref "Q12") (pin "6") (pinfunction "C2_6") (pintype "bidirectional"))
      (node (ref "RGB49") (pin "6") (pinfunction "GC_6") (pintype "bidirectional"))
      (node (ref "RGB49") (pin "6A") (pinfunction "GC_6A") (pintype "bidirectional"))
      (node (ref "RGB49") (pin "6B") (pinfunction "GC_6B") (pintype "bidirectional"))
    )
    (net (code "345") (name "Net-(Q12-E1)") (class "Default")
      (node (ref "Q12") (pin "1") (pinfunction "E1_1") (pintype "bidirectional"))
      (node (ref "R53") (pin "2") (pinfunction "2_2") (pintype "passive"))
    )
    (net (code "346") (name "Net-(Q12-E2)") (class "Default")
      (node (ref "Q12") (pin "3") (pinfunction "E2_3") (pintype "bidirectional"))
      (node (ref "R57") (pin "2") (pinfunction "2_2") (pintype "passive"))
      (node (ref "R59") (pin "1") (pinfunction "1_1") (pintype "passive"))
      (node (ref "U21") (pin "4") (pinfunction "IN-_4") (pintype "input"))
    )
    (net (code "347") (name "Net-(RGB1-BA-Pad3)") (class "Default")
      (node (ref "RGB1") (pin "3") (pinfunction "BA_3") (pintype "bidirectional"))
      (node (ref "RGB1") (pin "3A") (pinfunction "BA_3A") (pintype "bidirectional"))
      (node (ref "RGB1") (pin "3B") (pinfunction "BA_3B") (pintype "bidirectional"))
      (node (ref "RGB2") (pin "4") (pinfunction "BC_4") (pintype "bidirectional"))
      (node (ref "RGB2") (pin "4A") (pinfunction "BC_4A") (pintype "bidirectional"))
      (node (ref "RGB2") (pin "4B") (pinfunction "BC_4B") (pintype "bidirectional"))
    )
    (net (code "348") (name "Net-(RGB1-GA-Pad1)") (class "Default")
      (node (ref "RGB1") (pin "1") (pinfunction "GA_1") (pintype "bidirectional"))
      (node (ref "RGB1") (pin "1A") (pinfunction "GA_1A") (pintype "bidirectional"))
      (node (ref "RGB1") (pin "1B") (pinfunction "GA_1B") (pintype "bidirectional"))
      (node (ref "RGB2") (pin "6") (pinfunction "GC_6") (pintype "bidirectional"))
      (node (ref "RGB2") (pin "6A") (pinfunction "GC_6A") (pintype "bidirectional"))
      (node (ref "RGB2") (pin "6B") (pinfunction "GC_6B") (pintype "bidirectional"))
    )
    (net (code "349") (name "Net-(RGB1-RA-Pad2)") (class "Default")
      (node (ref "RGB1") (pin "2") (pinfunction "RA_2") (pintype "bidirectional"))
      (node (ref "RGB1") (pin "2A") (pinfunction "RA_2A") (pintype "bidirectional"))
      (node (ref "RGB1") (pin "2B") (pinfunction "RA_2B") (pintype "bidirectional"))
      (node (ref "RGB2") (pin "5") (pinfunction "RC_5") (pintype "bidirectional"))
      (node (ref "RGB2") (pin "5A") (pinfunction "RC_5A") (pintype "bidirectional"))
      (node (ref "RGB2") (pin "5B") (pinfunction "RC_5B") (pintype "bidirectional"))
    )
    (net (code "350") (name "Net-(RGB2-BA-Pad3)") (class "Default")
      (node (ref "RGB2") (pin "3") (pinfunction "BA_3") (pintype "bidirectional"))
      (node (ref "RGB2") (pin "3A") (pinfunction "BA_3A") (pintype "bidirectional"))
      (node (ref "RGB2") (pin "3B") (pinfunction "BA_3B") (pintype "bidirectional"))
      (node (ref "RGB3") (pin "4") (pinfunction "BC_4") (pintype "bidirectional"))
      (node (ref "RGB3") (pin "4A") (pinfunction "BC_4A") (pintype "bidirectional"))
      (node (ref "RGB3") (pin "4B") (pinfunction "BC_4B") (pintype "bidirectional"))
    )
    (net (code "351") (name "Net-(RGB2-GA-Pad1)") (class "Default")
      (node (ref "RGB2") (pin "1") (pinfunction "GA_1") (pintype "bidirectional"))
      (node (ref "RGB2") (pin "1A") (pinfunction "GA_1A") (pintype "bidirectional"))
      (node (ref "RGB2") (pin "1B") (pinfunction "GA_1B") (pintype "bidirectional"))
      (node (ref "RGB3") (pin "6") (pinfunction "GC_6") (pintype "bidirectional"))
      (node (ref "RGB3") (pin "6A") (pinfunction "GC_6A") (pintype "bidirectional"))
      (node (ref "RGB3") (pin "6B") (pinfunction "GC_6B") (pintype "bidirectional"))
    )
    (net (code "352") (name "Net-(RGB2-RA-Pad2)") (class "Default")
      (node (ref "RGB2") (pin "2") (pinfunction "RA_2") (pintype "bidirectional"))
      (node (ref "RGB2") (pin "2A") (pinfunction "RA_2A") (pintype "bidirectional"))
      (node (ref "RGB2") (pin "2B") (pinfunction "RA_2B") (pintype "bidirectional"))
      (node (ref "RGB3") (pin "5") (pinfunction "RC_5") (pintype "bidirectional"))
      (node (ref "RGB3") (pin "5A") (pinfunction "RC_5A") (pintype "bidirectional"))
      (node (ref "RGB3") (pin "5B") (pinfunction "RC_5B") (pintype "bidirectional"))
    )
    (net (code "353") (name "Net-(RGB3-BA-Pad3)") (class "Default")
      (node (ref "RGB3") (pin "3") (pinfunction "BA_3") (pintype "bidirectional"))
      (node (ref "RGB3") (pin "3A") (pinfunction "BA_3A") (pintype "bidirectional"))
      (node (ref "RGB3") (pin "3B") (pinfunction "BA_3B") (pintype "bidirectional"))
      (node (ref "RGB4") (pin "4") (pinfunction "BC_4") (pintype "bidirectional"))
      (node (ref "RGB4") (pin "4A") (pinfunction "BC_4A") (pintype "bidirectional"))
      (node (ref "RGB4") (pin "4B") (pinfunction "BC_4B") (pintype "bidirectional"))
    )
    (net (code "354") (name "Net-(RGB3-GA-Pad1)") (class "Default")
      (node (ref "RGB3") (pin "1") (pinfunction "GA_1") (pintype "bidirectional"))
      (node (ref "RGB3") (pin "1A") (pinfunction "GA_1A") (pintype "bidirectional"))
      (node (ref "RGB3") (pin "1B") (pinfunction "GA_1B") (pintype "bidirectional"))
      (node (ref "RGB4") (pin "6") (pinfunction "GC_6") (pintype "bidirectional"))
      (node (ref "RGB4") (pin "6A") (pinfunction "GC_6A") (pintype "bidirectional"))
      (node (ref "RGB4") (pin "6B") (pinfunction "GC_6B") (pintype "bidirectional"))
    )
    (net (code "355") (name "Net-(RGB3-RA-Pad2)") (class "Default")
      (node (ref "RGB3") (pin "2") (pinfunction "RA_2") (pintype "bidirectional"))
      (node (ref "RGB3") (pin "2A") (pinfunction "RA_2A") (pintype "bidirectional"))
      (node (ref "RGB3") (pin "2B") (pinfunction "RA_2B") (pintype "bidirectional"))
      (node (ref "RGB4") (pin "5") (pinfunction "RC_5") (pintype "bidirectional"))
      (node (ref "RGB4") (pin "5A") (pinfunction "RC_5A") (pintype "bidirectional"))
      (node (ref "RGB4") (pin "5B") (pinfunction "RC_5B") (pintype "bidirectional"))
    )
    (net (code "356") (name "Net-(RGB5-BA-Pad3)") (class "Default")
      (node (ref "RGB5") (pin "3") (pinfunction "BA_3") (pintype "bidirectional"))
      (node (ref "RGB5") (pin "3A") (pinfunction "BA_3A") (pintype "bidirectional"))
      (node (ref "RGB5") (pin "3B") (pinfunction "BA_3B") (pintype "bidirectional"))
      (node (ref "RGB6") (pin "4") (pinfunction "BC_4") (pintype "bidirectional"))
      (node (ref "RGB6") (pin "4A") (pinfunction "BC_4A") (pintype "bidirectional"))
      (node (ref "RGB6") (pin "4B") (pinfunction "BC_4B") (pintype "bidirectional"))
    )
    (net (code "357") (name "Net-(RGB5-GA-Pad1)") (class "Default")
      (node (ref "RGB5") (pin "1") (pinfunction "GA_1") (pintype "bidirectional"))
      (node (ref "RGB5") (pin "1A") (pinfunction "GA_1A") (pintype "bidirectional"))
      (node (ref "RGB5") (pin "1B") (pinfunction "GA_1B") (pintype "bidirectional"))
      (node (ref "RGB6") (pin "6") (pinfunction "GC_6") (pintype "bidirectional"))
      (node (ref "RGB6") (pin "6A") (pinfunction "GC_6A") (pintype "bidirectional"))
      (node (ref "RGB6") (pin "6B") (pinfunction "GC_6B") (pintype "bidirectional"))
    )
    (net (code "358") (name "Net-(RGB5-RA-Pad2)") (class "Default")
      (node (ref "RGB5") (pin "2") (pinfunction "RA_2") (pintype "bidirectional"))
      (node (ref "RGB5") (pin "2A") (pinfunction "RA_2A") (pintype "bidirectional"))
      (node (ref "RGB5") (pin "2B") (pinfunction "RA_2B") (pintype "bidirectional"))
      (node (ref "RGB6") (pin "5") (pinfunction "RC_5") (pintype "bidirectional"))
      (node (ref "RGB6") (pin "5A") (pinfunction "RC_5A") (pintype "bidirectional"))
      (node (ref "RGB6") (pin "5B") (pinfunction "RC_5B") (pintype "bidirectional"))
    )
    (net (code "359") (name "Net-(RGB6-BA-Pad3)") (class "Default")
      (node (ref "RGB6") (pin "3") (pinfunction "BA_3") (pintype "bidirectional"))
      (node (ref "RGB6") (pin "3A") (pinfunction "BA_3A") (pintype "bidirectional"))
      (node (ref "RGB6") (pin "3B") (pinfunction "BA_3B") (pintype "bidirectional"))
      (node (ref "RGB7") (pin "4") (pinfunction "BC_4") (pintype "bidirectional"))
      (node (ref "RGB7") (pin "4A") (pinfunction "BC_4A") (pintype "bidirectional"))
      (node (ref "RGB7") (pin "4B") (pinfunction "BC_4B") (pintype "bidirectional"))
    )
    (net (code "360") (name "Net-(RGB6-GA-Pad1)") (class "Default")
      (node (ref "RGB6") (pin "1") (pinfunction "GA_1") (pintype "bidirectional"))
      (node (ref "RGB6") (pin "1A") (pinfunction "GA_1A") (pintype "bidirectional"))
      (node (ref "RGB6") (pin "1B") (pinfunction "GA_1B") (pintype "bidirectional"))
      (node (ref "RGB7") (pin "6") (pinfunction "GC_6") (pintype "bidirectional"))
      (node (ref "RGB7") (pin "6A") (pinfunction "GC_6A") (pintype "bidirectional"))
      (node (ref "RGB7") (pin "6B") (pinfunction "GC_6B") (pintype "bidirectional"))
    )
    (net (code "361") (name "Net-(RGB6-RA-Pad2)") (class "Default")
      (node (ref "RGB6") (pin "2") (pinfunction "RA_2") (pintype "bidirectional"))
      (node (ref "RGB6") (pin "2A") (pinfunction "RA_2A") (pintype "bidirectional"))
      (node (ref "RGB6") (pin "2B") (pinfunction "RA_2B") (pintype "bidirectional"))
      (node (ref "RGB7") (pin "5") (pinfunction "RC_5") (pintype "bidirectional"))
      (node (ref "RGB7") (pin "5A") (pinfunction "RC_5A") (pintype "bidirectional"))
      (node (ref "RGB7") (pin "5B") (pinfunction "RC_5B") (pintype "bidirectional"))
    )
    (net (code "362") (name "Net-(RGB7-BA-Pad3)") (class "Default")
      (node (ref "RGB7") (pin "3") (pinfunction "BA_3") (pintype "bidirectional"))
      (node (ref "RGB7") (pin "3A") (pinfunction "BA_3A") (pintype "bidirectional"))
      (node (ref "RGB7") (pin "3B") (pinfunction "BA_3B") (pintype "bidirectional"))
      (node (ref "RGB8") (pin "4") (pinfunction "BC_4") (pintype "bidirectional"))
      (node (ref "RGB8") (pin "4A") (pinfunction "BC_4A") (pintype "bidirectional"))
      (node (ref "RGB8") (pin "4B") (pinfunction "BC_4B") (pintype "bidirectional"))
    )
    (net (code "363") (name "Net-(RGB7-GA-Pad1)") (class "Default")
      (node (ref "RGB7") (pin "1") (pinfunction "GA_1") (pintype "bidirectional"))
      (node (ref "RGB7") (pin "1A") (pinfunction "GA_1A") (pintype "bidirectional"))
      (node (ref "RGB7") (pin "1B") (pinfunction "GA_1B") (pintype "bidirectional"))
      (node (ref "RGB8") (pin "6") (pinfunction "GC_6") (pintype "bidirectional"))
      (node (ref "RGB8") (pin "6A") (pinfunction "GC_6A") (pintype "bidirectional"))
      (node (ref "RGB8") (pin "6B") (pinfunction "GC_6B") (pintype "bidirectional"))
    )
    (net (code "364") (name "Net-(RGB7-RA-Pad2)") (class "Default")
      (node (ref "RGB7") (pin "2") (pinfunction "RA_2") (pintype "bidirectional"))
      (node (ref "RGB7") (pin "2A") (pinfunction "RA_2A") (pintype "bidirectional"))
      (node (ref "RGB7") (pin "2B") (pinfunction "RA_2B") (pintype "bidirectional"))
      (node (ref "RGB8") (pin "5") (pinfunction "RC_5") (pintype "bidirectional"))
      (node (ref "RGB8") (pin "5A") (pinfunction "RC_5A") (pintype "bidirectional"))
      (node (ref "RGB8") (pin "5B") (pinfunction "RC_5B") (pintype "bidirectional"))
    )
    (net (code "365") (name "Net-(RGB10-BA-Pad3)") (class "Default")
      (node (ref "RGB10") (pin "3") (pinfunction "BA_3") (pintype "bidirectional"))
      (node (ref "RGB10") (pin "3A") (pinfunction "BA_3A") (pintype "bidirectional"))
      (node (ref "RGB10") (pin "3B") (pinfunction "BA_3B") (pintype "bidirectional"))
      (node (ref "RGB9") (pin "4") (pinfunction "BC_4") (pintype "bidirectional"))
      (node (ref "RGB9") (pin "4A") (pinfunction "BC_4A") (pintype "bidirectional"))
      (node (ref "RGB9") (pin "4B") (pinfunction "BC_4B") (pintype "bidirectional"))
    )
    (net (code "366") (name "Net-(RGB10-BC-Pad4)") (class "Default")
      (node (ref "RGB10") (pin "4") (pinfunction "BC_4") (pintype "bidirectional"))
      (node (ref "RGB10") (pin "4A") (pinfunction "BC_4A") (pintype "bidirectional"))
      (node (ref "RGB10") (pin "4B") (pinfunction "BC_4B") (pintype "bidirectional"))
      (node (ref "RGB11") (pin "3") (pinfunction "BA_3") (pintype "bidirectional"))
      (node (ref "RGB11") (pin "3A") (pinfunction "BA_3A") (pintype "bidirectional"))
      (node (ref "RGB11") (pin "3B") (pinfunction "BA_3B") (pintype "bidirectional"))
    )
    (net (code "367") (name "Net-(RGB10-GA-Pad1)") (class "Default")
      (node (ref "RGB10") (pin "1") (pinfunction "GA_1") (pintype "bidirectional"))
      (node (ref "RGB10") (pin "1A") (pinfunction "GA_1A") (pintype "bidirectional"))
      (node (ref "RGB10") (pin "1B") (pinfunction "GA_1B") (pintype "bidirectional"))
      (node (ref "RGB9") (pin "6") (pinfunction "GC_6") (pintype "bidirectional"))
      (node (ref "RGB9") (pin "6A") (pinfunction "GC_6A") (pintype "bidirectional"))
      (node (ref "RGB9") (pin "6B") (pinfunction "GC_6B") (pintype "bidirectional"))
    )
    (net (code "368") (name "Net-(RGB10-GC-Pad6)") (class "Default")
      (node (ref "RGB10") (pin "6") (pinfunction "GC_6") (pintype "bidirectional"))
      (node (ref "RGB10") (pin "6A") (pinfunction "GC_6A") (pintype "bidirectional"))
      (node (ref "RGB10") (pin "6B") (pinfunction "GC_6B") (pintype "bidirectional"))
      (node (ref "RGB11") (pin "1") (pinfunction "GA_1") (pintype "bidirectional"))
      (node (ref "RGB11") (pin "1A") (pinfunction "GA_1A") (pintype "bidirectional"))
      (node (ref "RGB11") (pin "1B") (pinfunction "GA_1B") (pintype "bidirectional"))
    )
    (net (code "369") (name "Net-(RGB10-RA-Pad2)") (class "Default")
      (node (ref "RGB10") (pin "2") (pinfunction "RA_2") (pintype "bidirectional"))
      (node (ref "RGB10") (pin "2A") (pinfunction "RA_2A") (pintype "bidirectional"))
      (node (ref "RGB10") (pin "2B") (pinfunction "RA_2B") (pintype "bidirectional"))
      (node (ref "RGB9") (pin "5") (pinfunction "RC_5") (pintype "bidirectional"))
      (node (ref "RGB9") (pin "5A") (pinfunction "RC_5A") (pintype "bidirectional"))
      (node (ref "RGB9") (pin "5B") (pinfunction "RC_5B") (pintype "bidirectional"))
    )
    (net (code "370") (name "Net-(RGB10-RC-Pad5)") (class "Default")
      (node (ref "RGB10") (pin "5") (pinfunction "RC_5") (pintype "bidirectional"))
      (node (ref "RGB10") (pin "5A") (pinfunction "RC_5A") (pintype "bidirectional"))
      (node (ref "RGB10") (pin "5B") (pinfunction "RC_5B") (pintype "bidirectional"))
      (node (ref "RGB11") (pin "2") (pinfunction "RA_2") (pintype "bidirectional"))
      (node (ref "RGB11") (pin "2A") (pinfunction "RA_2A") (pintype "bidirectional"))
      (node (ref "RGB11") (pin "2B") (pinfunction "RA_2B") (pintype "bidirectional"))
    )
    (net (code "371") (name "Net-(RGB11-BC-Pad4)") (class "Default")
      (node (ref "RGB11") (pin "4") (pinfunction "BC_4") (pintype "bidirectional"))
      (node (ref "RGB11") (pin "4A") (pinfunction "BC_4A") (pintype "bidirectional"))
      (node (ref "RGB11") (pin "4B") (pinfunction "BC_4B") (pintype "bidirectional"))
      (node (ref "RGB12") (pin "3") (pinfunction "BA_3") (pintype "bidirectional"))
      (node (ref "RGB12") (pin "3A") (pinfunction "BA_3A") (pintype "bidirectional"))
      (node (ref "RGB12") (pin "3B") (pinfunction "BA_3B") (pintype "bidirectional"))
    )
    (net (code "372") (name "Net-(RGB11-GC-Pad6)") (class "Default")
      (node (ref "RGB11") (pin "6") (pinfunction "GC_6") (pintype "bidirectional"))
      (node (ref "RGB11") (pin "6A") (pinfunction "GC_6A") (pintype "bidirectional"))
      (node (ref "RGB11") (pin "6B") (pinfunction "GC_6B") (pintype "bidirectional"))
      (node (ref "RGB12") (pin "1") (pinfunction "GA_1") (pintype "bidirectional"))
      (node (ref "RGB12") (pin "1A") (pinfunction "GA_1A") (pintype "bidirectional"))
      (node (ref "RGB12") (pin "1B") (pinfunction "GA_1B") (pintype "bidirectional"))
    )
    (net (code "373") (name "Net-(RGB11-RC-Pad5)") (class "Default")
      (node (ref "RGB11") (pin "5") (pinfunction "RC_5") (pintype "bidirectional"))
      (node (ref "RGB11") (pin "5A") (pinfunction "RC_5A") (pintype "bidirectional"))
      (node (ref "RGB11") (pin "5B") (pinfunction "RC_5B") (pintype "bidirectional"))
      (node (ref "RGB12") (pin "2") (pinfunction "RA_2") (pintype "bidirectional"))
      (node (ref "RGB12") (pin "2A") (pinfunction "RA_2A") (pintype "bidirectional"))
      (node (ref "RGB12") (pin "2B") (pinfunction "RA_2B") (pintype "bidirectional"))
    )
    (net (code "374") (name "Net-(RGB12-BC-Pad4)") (class "Default")
      (node (ref "RGB12") (pin "4") (pinfunction "BC_4") (pintype "bidirectional"))
      (node (ref "RGB12") (pin "4A") (pinfunction "BC_4A") (pintype "bidirectional"))
      (node (ref "RGB12") (pin "4B") (pinfunction "BC_4B") (pintype "bidirectional"))
      (node (ref "RGB4") (pin "3") (pinfunction "BA_3") (pintype "bidirectional"))
      (node (ref "RGB4") (pin "3A") (pinfunction "BA_3A") (pintype "bidirectional"))
      (node (ref "RGB4") (pin "3B") (pinfunction "BA_3B") (pintype "bidirectional"))
    )
    (net (code "375") (name "Net-(RGB12-GC-Pad6)") (class "Default")
      (node (ref "RGB12") (pin "6") (pinfunction "GC_6") (pintype "bidirectional"))
      (node (ref "RGB12") (pin "6A") (pinfunction "GC_6A") (pintype "bidirectional"))
      (node (ref "RGB12") (pin "6B") (pinfunction "GC_6B") (pintype "bidirectional"))
      (node (ref "RGB4") (pin "1") (pinfunction "GA_1") (pintype "bidirectional"))
      (node (ref "RGB4") (pin "1A") (pinfunction "GA_1A") (pintype "bidirectional"))
      (node (ref "RGB4") (pin "1B") (pinfunction "GA_1B") (pintype "bidirectional"))
    )
    (net (code "376") (name "Net-(RGB12-RC-Pad5)") (class "Default")
      (node (ref "RGB12") (pin "5") (pinfunction "RC_5") (pintype "bidirectional"))
      (node (ref "RGB12") (pin "5A") (pinfunction "RC_5A") (pintype "bidirectional"))
      (node (ref "RGB12") (pin "5B") (pinfunction "RC_5B") (pintype "bidirectional"))
      (node (ref "RGB4") (pin "2") (pinfunction "RA_2") (pintype "bidirectional"))
      (node (ref "RGB4") (pin "2A") (pinfunction "RA_2A") (pintype "bidirectional"))
      (node (ref "RGB4") (pin "2B") (pinfunction "RA_2B") (pintype "bidirectional"))
    )
    (net (code "377") (name "Net-(RGB13-BC-Pad4)") (class "Default")
      (node (ref "RGB13") (pin "4") (pinfunction "BC_4") (pintype "bidirectional"))
      (node (ref "RGB13") (pin "4A") (pinfunction "BC_4A") (pintype "bidirectional"))
      (node (ref "RGB13") (pin "4B") (pinfunction "BC_4B") (pintype "bidirectional"))
      (node (ref "RGB14") (pin "3") (pinfunction "BA_3") (pintype "bidirectional"))
      (node (ref "RGB14") (pin "3A") (pinfunction "BA_3A") (pintype "bidirectional"))
      (node (ref "RGB14") (pin "3B") (pinfunction "BA_3B") (pintype "bidirectional"))
    )
    (net (code "378") (name "Net-(RGB13-GC-Pad6)") (class "Default")
      (node (ref "RGB13") (pin "6") (pinfunction "GC_6") (pintype "bidirectional"))
      (node (ref "RGB13") (pin "6A") (pinfunction "GC_6A") (pintype "bidirectional"))
      (node (ref "RGB13") (pin "6B") (pinfunction "GC_6B") (pintype "bidirectional"))
      (node (ref "RGB14") (pin "1") (pinfunction "GA_1") (pintype "bidirectional"))
      (node (ref "RGB14") (pin "1A") (pinfunction "GA_1A") (pintype "bidirectional"))
      (node (ref "RGB14") (pin "1B") (pinfunction "GA_1B") (pintype "bidirectional"))
    )
    (net (code "379") (name "Net-(RGB13-RC-Pad5)") (class "Default")
      (node (ref "RGB13") (pin "5") (pinfunction "RC_5") (pintype "bidirectional"))
      (node (ref "RGB13") (pin "5A") (pinfunction "RC_5A") (pintype "bidirectional"))
      (node (ref "RGB13") (pin "5B") (pinfunction "RC_5B") (pintype "bidirectional"))
      (node (ref "RGB14") (pin "2") (pinfunction "RA_2") (pintype "bidirectional"))
      (node (ref "RGB14") (pin "2A") (pinfunction "RA_2A") (pintype "bidirectional"))
      (node (ref "RGB14") (pin "2B") (pinfunction "RA_2B") (pintype "bidirectional"))
    )
    (net (code "380") (name "Net-(RGB14-BC-Pad4)") (class "Default")
      (node (ref "RGB14") (pin "4") (pinfunction "BC_4") (pintype "bidirectional"))
      (node (ref "RGB14") (pin "4A") (pinfunction "BC_4A") (pintype "bidirectional"))
      (node (ref "RGB14") (pin "4B") (pinfunction "BC_4B") (pintype "bidirectional"))
      (node (ref "RGB15") (pin "3") (pinfunction "BA_3") (pintype "bidirectional"))
      (node (ref "RGB15") (pin "3A") (pinfunction "BA_3A") (pintype "bidirectional"))
      (node (ref "RGB15") (pin "3B") (pinfunction "BA_3B") (pintype "bidirectional"))
    )
    (net (code "381") (name "Net-(RGB14-GC-Pad6)") (class "Default")
      (node (ref "RGB14") (pin "6") (pinfunction "GC_6") (pintype "bidirectional"))
      (node (ref "RGB14") (pin "6A") (pinfunction "GC_6A") (pintype "bidirectional"))
      (node (ref "RGB14") (pin "6B") (pinfunction "GC_6B") (pintype "bidirectional"))
      (node (ref "RGB15") (pin "1") (pinfunction "GA_1") (pintype "bidirectional"))
      (node (ref "RGB15") (pin "1A") (pinfunction "GA_1A") (pintype "bidirectional"))
      (node (ref "RGB15") (pin "1B") (pinfunction "GA_1B") (pintype "bidirectional"))
    )
    (net (code "382") (name "Net-(RGB14-RC-Pad5)") (class "Default")
      (node (ref "RGB14") (pin "5") (pinfunction "RC_5") (pintype "bidirectional"))
      (node (ref "RGB14") (pin "5A") (pinfunction "RC_5A") (pintype "bidirectional"))
      (node (ref "RGB14") (pin "5B") (pinfunction "RC_5B") (pintype "bidirectional"))
      (node (ref "RGB15") (pin "2") (pinfunction "RA_2") (pintype "bidirectional"))
      (node (ref "RGB15") (pin "2A") (pinfunction "RA_2A") (pintype "bidirectional"))
      (node (ref "RGB15") (pin "2B") (pinfunction "RA_2B") (pintype "bidirectional"))
    )
    (net (code "383") (name "Net-(RGB15-BC-Pad4)") (class "Default")
      (node (ref "RGB15") (pin "4") (pinfunction "BC_4") (pintype "bidirectional"))
      (node (ref "RGB15") (pin "4A") (pinfunction "BC_4A") (pintype "bidirectional"))
      (node (ref "RGB15") (pin "4B") (pinfunction "BC_4B") (pintype "bidirectional"))
      (node (ref "RGB16") (pin "3") (pinfunction "BA_3") (pintype "bidirectional"))
      (node (ref "RGB16") (pin "3A") (pinfunction "BA_3A") (pintype "bidirectional"))
      (node (ref "RGB16") (pin "3B") (pinfunction "BA_3B") (pintype "bidirectional"))
    )
    (net (code "384") (name "Net-(RGB15-GC-Pad6)") (class "Default")
      (node (ref "RGB15") (pin "6") (pinfunction "GC_6") (pintype "bidirectional"))
      (node (ref "RGB15") (pin "6A") (pinfunction "GC_6A") (pintype "bidirectional"))
      (node (ref "RGB15") (pin "6B") (pinfunction "GC_6B") (pintype "bidirectional"))
      (node (ref "RGB16") (pin "1") (pinfunction "GA_1") (pintype "bidirectional"))
      (node (ref "RGB16") (pin "1A") (pinfunction "GA_1A") (pintype "bidirectional"))
      (node (ref "RGB16") (pin "1B") (pinfunction "GA_1B") (pintype "bidirectional"))
    )
    (net (code "385") (name "Net-(RGB15-RC-Pad5)") (class "Default")
      (node (ref "RGB15") (pin "5") (pinfunction "RC_5") (pintype "bidirectional"))
      (node (ref "RGB15") (pin "5A") (pinfunction "RC_5A") (pintype "bidirectional"))
      (node (ref "RGB15") (pin "5B") (pinfunction "RC_5B") (pintype "bidirectional"))
      (node (ref "RGB16") (pin "2") (pinfunction "RA_2") (pintype "bidirectional"))
      (node (ref "RGB16") (pin "2A") (pinfunction "RA_2A") (pintype "bidirectional"))
      (node (ref "RGB16") (pin "2B") (pinfunction "RA_2B") (pintype "bidirectional"))
    )
    (net (code "386") (name "Net-(RGB16-BC-Pad4)") (class "Default")
      (node (ref "RGB16") (pin "4") (pinfunction "BC_4") (pintype "bidirectional"))
      (node (ref "RGB16") (pin "4A") (pinfunction "BC_4A") (pintype "bidirectional"))
      (node (ref "RGB16") (pin "4B") (pinfunction "BC_4B") (pintype "bidirectional"))
      (node (ref "RGB8") (pin "3") (pinfunction "BA_3") (pintype "bidirectional"))
      (node (ref "RGB8") (pin "3A") (pinfunction "BA_3A") (pintype "bidirectional"))
      (node (ref "RGB8") (pin "3B") (pinfunction "BA_3B") (pintype "bidirectional"))
    )
    (net (code "387") (name "Net-(RGB16-GC-Pad6)") (class "Default")
      (node (ref "RGB16") (pin "6") (pinfunction "GC_6") (pintype "bidirectional"))
      (node (ref "RGB16") (pin "6A") (pinfunction "GC_6A") (pintype "bidirectional"))
      (node (ref "RGB16") (pin "6B") (pinfunction "GC_6B") (pintype "bidirectional"))
      (node (ref "RGB8") (pin "1") (pinfunction "GA_1") (pintype "bidirectional"))
      (node (ref "RGB8") (pin "1A") (pinfunction "GA_1A") (pintype "bidirectional"))
      (node (ref "RGB8") (pin "1B") (pinfunction "GA_1B") (pintype "bidirectional"))
    )
    (net (code "388") (name "Net-(RGB16-RC-Pad5)") (class "Default")
      (node (ref "RGB16") (pin "5") (pinfunction "RC_5") (pintype "bidirectional"))
      (node (ref "RGB16") (pin "5A") (pinfunction "RC_5A") (pintype "bidirectional"))
      (node (ref "RGB16") (pin "5B") (pinfunction "RC_5B") (pintype "bidirectional"))
      (node (ref "RGB8") (pin "2") (pinfunction "RA_2") (pintype "bidirectional"))
      (node (ref "RGB8") (pin "2A") (pinfunction "RA_2A") (pintype "bidirectional"))
      (node (ref "RGB8") (pin "2B") (pinfunction "RA_2B") (pintype "bidirectional"))
    )
    (net (code "389") (name "Net-(RGB17-BA-Pad3)") (class "Default")
      (node (ref "RGB17") (pin "3") (pinfunction "BA_3") (pintype "bidirectional"))
      (node (ref "RGB17") (pin "3A") (pinfunction "BA_3A") (pintype "bidirectional"))
      (node (ref "RGB17") (pin "3B") (pinfunction "BA_3B") (pintype "bidirectional"))
      (node (ref "RGB18") (pin "4") (pinfunction "BC_4") (pintype "bidirectional"))
      (node (ref "RGB18") (pin "4A") (pinfunction "BC_4A") (pintype "bidirectional"))
      (node (ref "RGB18") (pin "4B") (pinfunction "BC_4B") (pintype "bidirectional"))
    )
    (net (code "390") (name "Net-(RGB17-GA-Pad1)") (class "Default")
      (node (ref "RGB17") (pin "1") (pinfunction "GA_1") (pintype "bidirectional"))
      (node (ref "RGB17") (pin "1A") (pinfunction "GA_1A") (pintype "bidirectional"))
      (node (ref "RGB17") (pin "1B") (pinfunction "GA_1B") (pintype "bidirectional"))
      (node (ref "RGB18") (pin "6") (pinfunction "GC_6") (pintype "bidirectional"))
      (node (ref "RGB18") (pin "6A") (pinfunction "GC_6A") (pintype "bidirectional"))
      (node (ref "RGB18") (pin "6B") (pinfunction "GC_6B") (pintype "bidirectional"))
    )
    (net (code "391") (name "Net-(RGB17-RA-Pad2)") (class "Default")
      (node (ref "RGB17") (pin "2") (pinfunction "RA_2") (pintype "bidirectional"))
      (node (ref "RGB17") (pin "2A") (pinfunction "RA_2A") (pintype "bidirectional"))
      (node (ref "RGB17") (pin "2B") (pinfunction "RA_2B") (pintype "bidirectional"))
      (node (ref "RGB18") (pin "5") (pinfunction "RC_5") (pintype "bidirectional"))
      (node (ref "RGB18") (pin "5A") (pinfunction "RC_5A") (pintype "bidirectional"))
      (node (ref "RGB18") (pin "5B") (pinfunction "RC_5B") (pintype "bidirectional"))
    )
    (net (code "392") (name "Net-(RGB18-BA-Pad3)") (class "Default")
      (node (ref "RGB18") (pin "3") (pinfunction "BA_3") (pintype "bidirectional"))
      (node (ref "RGB18") (pin "3A") (pinfunction "BA_3A") (pintype "bidirectional"))
      (node (ref "RGB18") (pin "3B") (pinfunction "BA_3B") (pintype "bidirectional"))
      (node (ref "RGB19") (pin "4") (pinfunction "BC_4") (pintype "bidirectional"))
      (node (ref "RGB19") (pin "4A") (pinfunction "BC_4A") (pintype "bidirectional"))
      (node (ref "RGB19") (pin "4B") (pinfunction "BC_4B") (pintype "bidirectional"))
    )
    (net (code "393") (name "Net-(RGB18-GA-Pad1)") (class "Default")
      (node (ref "RGB18") (pin "1") (pinfunction "GA_1") (pintype "bidirectional"))
      (node (ref "RGB18") (pin "1A") (pinfunction "GA_1A") (pintype "bidirectional"))
      (node (ref "RGB18") (pin "1B") (pinfunction "GA_1B") (pintype "bidirectional"))
      (node (ref "RGB19") (pin "6") (pinfunction "GC_6") (pintype "bidirectional"))
      (node (ref "RGB19") (pin "6A") (pinfunction "GC_6A") (pintype "bidirectional"))
      (node (ref "RGB19") (pin "6B") (pinfunction "GC_6B") (pintype "bidirectional"))
    )
    (net (code "394") (name "Net-(RGB18-RA-Pad2)") (class "Default")
      (node (ref "RGB18") (pin "2") (pinfunction "RA_2") (pintype "bidirectional"))
      (node (ref "RGB18") (pin "2A") (pinfunction "RA_2A") (pintype "bidirectional"))
      (node (ref "RGB18") (pin "2B") (pinfunction "RA_2B") (pintype "bidirectional"))
      (node (ref "RGB19") (pin "5") (pinfunction "RC_5") (pintype "bidirectional"))
      (node (ref "RGB19") (pin "5A") (pinfunction "RC_5A") (pintype "bidirectional"))
      (node (ref "RGB19") (pin "5B") (pinfunction "RC_5B") (pintype "bidirectional"))
    )
    (net (code "395") (name "Net-(RGB19-BA-Pad3)") (class "Default")
      (node (ref "RGB19") (pin "3") (pinfunction "BA_3") (pintype "bidirectional"))
      (node (ref "RGB19") (pin "3A") (pinfunction "BA_3A") (pintype "bidirectional"))
      (node (ref "RGB19") (pin "3B") (pinfunction "BA_3B") (pintype "bidirectional"))
      (node (ref "RGB20") (pin "4") (pinfunction "BC_4") (pintype "bidirectional"))
      (node (ref "RGB20") (pin "4A") (pinfunction "BC_4A") (pintype "bidirectional"))
      (node (ref "RGB20") (pin "4B") (pinfunction "BC_4B") (pintype "bidirectional"))
    )
    (net (code "396") (name "Net-(RGB19-GA-Pad1)") (class "Default")
      (node (ref "RGB19") (pin "1") (pinfunction "GA_1") (pintype "bidirectional"))
      (node (ref "RGB19") (pin "1A") (pinfunction "GA_1A") (pintype "bidirectional"))
      (node (ref "RGB19") (pin "1B") (pinfunction "GA_1B") (pintype "bidirectional"))
      (node (ref "RGB20") (pin "6") (pinfunction "GC_6") (pintype "bidirectional"))
      (node (ref "RGB20") (pin "6A") (pinfunction "GC_6A") (pintype "bidirectional"))
      (node (ref "RGB20") (pin "6B") (pinfunction "GC_6B") (pintype "bidirectional"))
    )
    (net (code "397") (name "Net-(RGB19-RA-Pad2)") (class "Default")
      (node (ref "RGB19") (pin "2") (pinfunction "RA_2") (pintype "bidirectional"))
      (node (ref "RGB19") (pin "2A") (pinfunction "RA_2A") (pintype "bidirectional"))
      (node (ref "RGB19") (pin "2B") (pinfunction "RA_2B") (pintype "bidirectional"))
      (node (ref "RGB20") (pin "5") (pinfunction "RC_5") (pintype "bidirectional"))
      (node (ref "RGB20") (pin "5A") (pinfunction "RC_5A") (pintype "bidirectional"))
      (node (ref "RGB20") (pin "5B") (pinfunction "RC_5B") (pintype "bidirectional"))
    )
    (net (code "398") (name "Net-(RGB20-BA-Pad3)") (class "Default")
      (node (ref "RGB20") (pin "3") (pinfunction "BA_3") (pintype "bidirectional"))
      (node (ref "RGB20") (pin "3A") (pinfunction "BA_3A") (pintype "bidirectional"))
      (node (ref "RGB20") (pin "3B") (pinfunction "BA_3B") (pintype "bidirectional"))
      (node (ref "RGB28") (pin "4") (pinfunction "BC_4") (pintype "bidirectional"))
      (node (ref "RGB28") (pin "4A") (pinfunction "BC_4A") (pintype "bidirectional"))
      (node (ref "RGB28") (pin "4B") (pinfunction "BC_4B") (pintype "bidirectional"))
    )
    (net (code "399") (name "Net-(RGB20-GA-Pad1)") (class "Default")
      (node (ref "RGB20") (pin "1") (pinfunction "GA_1") (pintype "bidirectional"))
      (node (ref "RGB20") (pin "1A") (pinfunction "GA_1A") (pintype "bidirectional"))
      (node (ref "RGB20") (pin "1B") (pinfunction "GA_1B") (pintype "bidirectional"))
      (node (ref "RGB28") (pin "6") (pinfunction "GC_6") (pintype "bidirectional"))
      (node (ref "RGB28") (pin "6A") (pinfunction "GC_6A") (pintype "bidirectional"))
      (node (ref "RGB28") (pin "6B") (pinfunction "GC_6B") (pintype "bidirectional"))
    )
    (net (code "400") (name "Net-(RGB20-RA-Pad2)") (class "Default")
      (node (ref "RGB20") (pin "2") (pinfunction "RA_2") (pintype "bidirectional"))
      (node (ref "RGB20") (pin "2A") (pinfunction "RA_2A") (pintype "bidirectional"))
      (node (ref "RGB20") (pin "2B") (pinfunction "RA_2B") (pintype "bidirectional"))
      (node (ref "RGB28") (pin "5") (pinfunction "RC_5") (pintype "bidirectional"))
      (node (ref "RGB28") (pin "5A") (pinfunction "RC_5A") (pintype "bidirectional"))
      (node (ref "RGB28") (pin "5B") (pinfunction "RC_5B") (pintype "bidirectional"))
    )
    (net (code "401") (name "Net-(RGB21-BA-Pad3)") (class "Default")
      (node (ref "RGB21") (pin "3") (pinfunction "BA_3") (pintype "bidirectional"))
      (node (ref "RGB21") (pin "3A") (pinfunction "BA_3A") (pintype "bidirectional"))
      (node (ref "RGB21") (pin "3B") (pinfunction "BA_3B") (pintype "bidirectional"))
      (node (ref "RGB22") (pin "4") (pinfunction "BC_4") (pintype "bidirectional"))
      (node (ref "RGB22") (pin "4A") (pinfunction "BC_4A") (pintype "bidirectional"))
      (node (ref "RGB22") (pin "4B") (pinfunction "BC_4B") (pintype "bidirectional"))
    )
    (net (code "402") (name "Net-(RGB21-GA-Pad1)") (class "Default")
      (node (ref "RGB21") (pin "1") (pinfunction "GA_1") (pintype "bidirectional"))
      (node (ref "RGB21") (pin "1A") (pinfunction "GA_1A") (pintype "bidirectional"))
      (node (ref "RGB21") (pin "1B") (pinfunction "GA_1B") (pintype "bidirectional"))
      (node (ref "RGB22") (pin "6") (pinfunction "GC_6") (pintype "bidirectional"))
      (node (ref "RGB22") (pin "6A") (pinfunction "GC_6A") (pintype "bidirectional"))
      (node (ref "RGB22") (pin "6B") (pinfunction "GC_6B") (pintype "bidirectional"))
    )
    (net (code "403") (name "Net-(RGB21-RA-Pad2)") (class "Default")
      (node (ref "RGB21") (pin "2") (pinfunction "RA_2") (pintype "bidirectional"))
      (node (ref "RGB21") (pin "2A") (pinfunction "RA_2A") (pintype "bidirectional"))
      (node (ref "RGB21") (pin "2B") (pinfunction "RA_2B") (pintype "bidirectional"))
      (node (ref "RGB22") (pin "5") (pinfunction "RC_5") (pintype "bidirectional"))
      (node (ref "RGB22") (pin "5A") (pinfunction "RC_5A") (pintype "bidirectional"))
      (node (ref "RGB22") (pin "5B") (pinfunction "RC_5B") (pintype "bidirectional"))
    )
    (net (code "404") (name "Net-(RGB22-BA-Pad3)") (class "Default")
      (node (ref "RGB22") (pin "3") (pinfunction "BA_3") (pintype "bidirectional"))
      (node (ref "RGB22") (pin "3A") (pinfunction "BA_3A") (pintype "bidirectional"))
      (node (ref "RGB22") (pin "3B") (pinfunction "BA_3B") (pintype "bidirectional"))
      (node (ref "RGB23") (pin "4") (pinfunction "BC_4") (pintype "bidirectional"))
      (node (ref "RGB23") (pin "4A") (pinfunction "BC_4A") (pintype "bidirectional"))
      (node (ref "RGB23") (pin "4B") (pinfunction "BC_4B") (pintype "bidirectional"))
    )
    (net (code "405") (name "Net-(RGB22-GA-Pad1)") (class "Default")
      (node (ref "RGB22") (pin "1") (pinfunction "GA_1") (pintype "bidirectional"))
      (node (ref "RGB22") (pin "1A") (pinfunction "GA_1A") (pintype "bidirectional"))
      (node (ref "RGB22") (pin "1B") (pinfunction "GA_1B") (pintype "bidirectional"))
      (node (ref "RGB23") (pin "6") (pinfunction "GC_6") (pintype "bidirectional"))
      (node (ref "RGB23") (pin "6A") (pinfunction "GC_6A") (pintype "bidirectional"))
      (node (ref "RGB23") (pin "6B") (pinfunction "GC_6B") (pintype "bidirectional"))
    )
    (net (code "406") (name "Net-(RGB22-RA-Pad2)") (class "Default")
      (node (ref "RGB22") (pin "2") (pinfunction "RA_2") (pintype "bidirectional"))
      (node (ref "RGB22") (pin "2A") (pinfunction "RA_2A") (pintype "bidirectional"))
      (node (ref "RGB22") (pin "2B") (pinfunction "RA_2B") (pintype "bidirectional"))
      (node (ref "RGB23") (pin "5") (pinfunction "RC_5") (pintype "bidirectional"))
      (node (ref "RGB23") (pin "5A") (pinfunction "RC_5A") (pintype "bidirectional"))
      (node (ref "RGB23") (pin "5B") (pinfunction "RC_5B") (pintype "bidirectional"))
    )
    (net (code "407") (name "Net-(RGB23-BA-Pad3)") (class "Default")
      (node (ref "RGB23") (pin "3") (pinfunction "BA_3") (pintype "bidirectional"))
      (node (ref "RGB23") (pin "3A") (pinfunction "BA_3A") (pintype "bidirectional"))
      (node (ref "RGB23") (pin "3B") (pinfunction "BA_3B") (pintype "bidirectional"))
      (node (ref "RGB24") (pin "4") (pinfunction "BC_4") (pintype "bidirectional"))
      (node (ref "RGB24") (pin "4A") (pinfunction "BC_4A") (pintype "bidirectional"))
      (node (ref "RGB24") (pin "4B") (pinfunction "BC_4B") (pintype "bidirectional"))
    )
    (net (code "408") (name "Net-(RGB23-GA-Pad1)") (class "Default")
      (node (ref "RGB23") (pin "1") (pinfunction "GA_1") (pintype "bidirectional"))
      (node (ref "RGB23") (pin "1A") (pinfunction "GA_1A") (pintype "bidirectional"))
      (node (ref "RGB23") (pin "1B") (pinfunction "GA_1B") (pintype "bidirectional"))
      (node (ref "RGB24") (pin "6") (pinfunction "GC_6") (pintype "bidirectional"))
      (node (ref "RGB24") (pin "6A") (pinfunction "GC_6A") (pintype "bidirectional"))
      (node (ref "RGB24") (pin "6B") (pinfunction "GC_6B") (pintype "bidirectional"))
    )
    (net (code "409") (name "Net-(RGB23-RA-Pad2)") (class "Default")
      (node (ref "RGB23") (pin "2") (pinfunction "RA_2") (pintype "bidirectional"))
      (node (ref "RGB23") (pin "2A") (pinfunction "RA_2A") (pintype "bidirectional"))
      (node (ref "RGB23") (pin "2B") (pinfunction "RA_2B") (pintype "bidirectional"))
      (node (ref "RGB24") (pin "5") (pinfunction "RC_5") (pintype "bidirectional"))
      (node (ref "RGB24") (pin "5A") (pinfunction "RC_5A") (pintype "bidirectional"))
      (node (ref "RGB24") (pin "5B") (pinfunction "RC_5B") (pintype "bidirectional"))
    )
    (net (code "410") (name "Net-(RGB24-BA-Pad3)") (class "Default")
      (node (ref "RGB24") (pin "3") (pinfunction "BA_3") (pintype "bidirectional"))
      (node (ref "RGB24") (pin "3A") (pinfunction "BA_3A") (pintype "bidirectional"))
      (node (ref "RGB24") (pin "3B") (pinfunction "BA_3B") (pintype "bidirectional"))
      (node (ref "RGB32") (pin "4") (pinfunction "BC_4") (pintype "bidirectional"))
      (node (ref "RGB32") (pin "4A") (pinfunction "BC_4A") (pintype "bidirectional"))
      (node (ref "RGB32") (pin "4B") (pinfunction "BC_4B") (pintype "bidirectional"))
    )
    (net (code "411") (name "Net-(RGB24-GA-Pad1)") (class "Default")
      (node (ref "RGB24") (pin "1") (pinfunction "GA_1") (pintype "bidirectional"))
      (node (ref "RGB24") (pin "1A") (pinfunction "GA_1A") (pintype "bidirectional"))
      (node (ref "RGB24") (pin "1B") (pinfunction "GA_1B") (pintype "bidirectional"))
      (node (ref "RGB32") (pin "6") (pinfunction "GC_6") (pintype "bidirectional"))
      (node (ref "RGB32") (pin "6A") (pinfunction "GC_6A") (pintype "bidirectional"))
      (node (ref "RGB32") (pin "6B") (pinfunction "GC_6B") (pintype "bidirectional"))
    )
    (net (code "412") (name "Net-(RGB24-RA-Pad2)") (class "Default")
      (node (ref "RGB24") (pin "2") (pinfunction "RA_2") (pintype "bidirectional"))
      (node (ref "RGB24") (pin "2A") (pinfunction "RA_2A") (pintype "bidirectional"))
      (node (ref "RGB24") (pin "2B") (pinfunction "RA_2B") (pintype "bidirectional"))
      (node (ref "RGB32") (pin "5") (pinfunction "RC_5") (pintype "bidirectional"))
      (node (ref "RGB32") (pin "5A") (pinfunction "RC_5A") (pintype "bidirectional"))
      (node (ref "RGB32") (pin "5B") (pinfunction "RC_5B") (pintype "bidirectional"))
    )
    (net (code "413") (name "Net-(RGB25-BC-Pad4)") (class "Default")
      (node (ref "RGB25") (pin "4") (pinfunction "BC_4") (pintype "bidirectional"))
      (node (ref "RGB25") (pin "4A") (pinfunction "BC_4A") (pintype "bidirectional"))
      (node (ref "RGB25") (pin "4B") (pinfunction "BC_4B") (pintype "bidirectional"))
      (node (ref "RGB26") (pin "3") (pinfunction "BA_3") (pintype "bidirectional"))
      (node (ref "RGB26") (pin "3A") (pinfunction "BA_3A") (pintype "bidirectional"))
      (node (ref "RGB26") (pin "3B") (pinfunction "BA_3B") (pintype "bidirectional"))
    )
    (net (code "414") (name "Net-(RGB25-GC-Pad6)") (class "Default")
      (node (ref "RGB25") (pin "6") (pinfunction "GC_6") (pintype "bidirectional"))
      (node (ref "RGB25") (pin "6A") (pinfunction "GC_6A") (pintype "bidirectional"))
      (node (ref "RGB25") (pin "6B") (pinfunction "GC_6B") (pintype "bidirectional"))
      (node (ref "RGB26") (pin "1") (pinfunction "GA_1") (pintype "bidirectional"))
      (node (ref "RGB26") (pin "1A") (pinfunction "GA_1A") (pintype "bidirectional"))
      (node (ref "RGB26") (pin "1B") (pinfunction "GA_1B") (pintype "bidirectional"))
    )
    (net (code "415") (name "Net-(RGB25-RC-Pad5)") (class "Default")
      (node (ref "RGB25") (pin "5") (pinfunction "RC_5") (pintype "bidirectional"))
      (node (ref "RGB25") (pin "5A") (pinfunction "RC_5A") (pintype "bidirectional"))
      (node (ref "RGB25") (pin "5B") (pinfunction "RC_5B") (pintype "bidirectional"))
      (node (ref "RGB26") (pin "2") (pinfunction "RA_2") (pintype "bidirectional"))
      (node (ref "RGB26") (pin "2A") (pinfunction "RA_2A") (pintype "bidirectional"))
      (node (ref "RGB26") (pin "2B") (pinfunction "RA_2B") (pintype "bidirectional"))
    )
    (net (code "416") (name "Net-(RGB26-BC-Pad4)") (class "Default")
      (node (ref "RGB26") (pin "4") (pinfunction "BC_4") (pintype "bidirectional"))
      (node (ref "RGB26") (pin "4A") (pinfunction "BC_4A") (pintype "bidirectional"))
      (node (ref "RGB26") (pin "4B") (pinfunction "BC_4B") (pintype "bidirectional"))
      (node (ref "RGB27") (pin "3") (pinfunction "BA_3") (pintype "bidirectional"))
      (node (ref "RGB27") (pin "3A") (pinfunction "BA_3A") (pintype "bidirectional"))
      (node (ref "RGB27") (pin "3B") (pinfunction "BA_3B") (pintype "bidirectional"))
    )
    (net (code "417") (name "Net-(RGB26-GC-Pad6)") (class "Default")
      (node (ref "RGB26") (pin "6") (pinfunction "GC_6") (pintype "bidirectional"))
      (node (ref "RGB26") (pin "6A") (pinfunction "GC_6A") (pintype "bidirectional"))
      (node (ref "RGB26") (pin "6B") (pinfunction "GC_6B") (pintype "bidirectional"))
      (node (ref "RGB27") (pin "1") (pinfunction "GA_1") (pintype "bidirectional"))
      (node (ref "RGB27") (pin "1A") (pinfunction "GA_1A") (pintype "bidirectional"))
      (node (ref "RGB27") (pin "1B") (pinfunction "GA_1B") (pintype "bidirectional"))
    )
    (net (code "418") (name "Net-(RGB26-RC-Pad5)") (class "Default")
      (node (ref "RGB26") (pin "5") (pinfunction "RC_5") (pintype "bidirectional"))
      (node (ref "RGB26") (pin "5A") (pinfunction "RC_5A") (pintype "bidirectional"))
      (node (ref "RGB26") (pin "5B") (pinfunction "RC_5B") (pintype "bidirectional"))
      (node (ref "RGB27") (pin "2") (pinfunction "RA_2") (pintype "bidirectional"))
      (node (ref "RGB27") (pin "2A") (pinfunction "RA_2A") (pintype "bidirectional"))
      (node (ref "RGB27") (pin "2B") (pinfunction "RA_2B") (pintype "bidirectional"))
    )
    (net (code "419") (name "Net-(RGB27-BC-Pad4)") (class "Default")
      (node (ref "RGB27") (pin "4") (pinfunction "BC_4") (pintype "bidirectional"))
      (node (ref "RGB27") (pin "4A") (pinfunction "BC_4A") (pintype "bidirectional"))
      (node (ref "RGB27") (pin "4B") (pinfunction "BC_4B") (pintype "bidirectional"))
      (node (ref "RGB28") (pin "3") (pinfunction "BA_3") (pintype "bidirectional"))
      (node (ref "RGB28") (pin "3A") (pinfunction "BA_3A") (pintype "bidirectional"))
      (node (ref "RGB28") (pin "3B") (pinfunction "BA_3B") (pintype "bidirectional"))
    )
    (net (code "420") (name "Net-(RGB27-GC-Pad6)") (class "Default")
      (node (ref "RGB27") (pin "6") (pinfunction "GC_6") (pintype "bidirectional"))
      (node (ref "RGB27") (pin "6A") (pinfunction "GC_6A") (pintype "bidirectional"))
      (node (ref "RGB27") (pin "6B") (pinfunction "GC_6B") (pintype "bidirectional"))
      (node (ref "RGB28") (pin "1") (pinfunction "GA_1") (pintype "bidirectional"))
      (node (ref "RGB28") (pin "1A") (pinfunction "GA_1A") (pintype "bidirectional"))
      (node (ref "RGB28") (pin "1B") (pinfunction "GA_1B") (pintype "bidirectional"))
    )
    (net (code "421") (name "Net-(RGB27-RC-Pad5)") (class "Default")
      (node (ref "RGB27") (pin "5") (pinfunction "RC_5") (pintype "bidirectional"))
      (node (ref "RGB27") (pin "5A") (pinfunction "RC_5A") (pintype "bidirectional"))
      (node (ref "RGB27") (pin "5B") (pinfunction "RC_5B") (pintype "bidirectional"))
      (node (ref "RGB28") (pin "2") (pinfunction "RA_2") (pintype "bidirectional"))
      (node (ref "RGB28") (pin "2A") (pinfunction "RA_2A") (pintype "bidirectional"))
      (node (ref "RGB28") (pin "2B") (pinfunction "RA_2B") (pintype "bidirectional"))
    )
    (net (code "422") (name "Net-(RGB29-BC-Pad4)") (class "Default")
      (node (ref "RGB29") (pin "4") (pinfunction "BC_4") (pintype "bidirectional"))
      (node (ref "RGB29") (pin "4A") (pinfunction "BC_4A") (pintype "bidirectional"))
      (node (ref "RGB29") (pin "4B") (pinfunction "BC_4B") (pintype "bidirectional"))
      (node (ref "RGB30") (pin "3") (pinfunction "BA_3") (pintype "bidirectional"))
      (node (ref "RGB30") (pin "3A") (pinfunction "BA_3A") (pintype "bidirectional"))
      (node (ref "RGB30") (pin "3B") (pinfunction "BA_3B") (pintype "bidirectional"))
    )
    (net (code "423") (name "Net-(RGB29-GC-Pad6)") (class "Default")
      (node (ref "RGB29") (pin "6") (pinfunction "GC_6") (pintype "bidirectional"))
      (node (ref "RGB29") (pin "6A") (pinfunction "GC_6A") (pintype "bidirectional"))
      (node (ref "RGB29") (pin "6B") (pinfunction "GC_6B") (pintype "bidirectional"))
      (node (ref "RGB30") (pin "1") (pinfunction "GA_1") (pintype "bidirectional"))
      (node (ref "RGB30") (pin "1A") (pinfunction "GA_1A") (pintype "bidirectional"))
      (node (ref "RGB30") (pin "1B") (pinfunction "GA_1B") (pintype "bidirectional"))
    )
    (net (code "424") (name "Net-(RGB29-RC-Pad5)") (class "Default")
      (node (ref "RGB29") (pin "5") (pinfunction "RC_5") (pintype "bidirectional"))
      (node (ref "RGB29") (pin "5A") (pinfunction "RC_5A") (pintype "bidirectional"))
      (node (ref "RGB29") (pin "5B") (pinfunction "RC_5B") (pintype "bidirectional"))
      (node (ref "RGB30") (pin "2") (pinfunction "RA_2") (pintype "bidirectional"))
      (node (ref "RGB30") (pin "2A") (pinfunction "RA_2A") (pintype "bidirectional"))
      (node (ref "RGB30") (pin "2B") (pinfunction "RA_2B") (pintype "bidirectional"))
    )
    (net (code "425") (name "Net-(RGB30-BC-Pad4)") (class "Default")
      (node (ref "RGB30") (pin "4") (pinfunction "BC_4") (pintype "bidirectional"))
      (node (ref "RGB30") (pin "4A") (pinfunction "BC_4A") (pintype "bidirectional"))
      (node (ref "RGB30") (pin "4B") (pinfunction "BC_4B") (pintype "bidirectional"))
      (node (ref "RGB31") (pin "3") (pinfunction "BA_3") (pintype "bidirectional"))
      (node (ref "RGB31") (pin "3A") (pinfunction "BA_3A") (pintype "bidirectional"))
      (node (ref "RGB31") (pin "3B") (pinfunction "BA_3B") (pintype "bidirectional"))
    )
    (net (code "426") (name "Net-(RGB30-GC-Pad6)") (class "Default")
      (node (ref "RGB30") (pin "6") (pinfunction "GC_6") (pintype "bidirectional"))
      (node (ref "RGB30") (pin "6A") (pinfunction "GC_6A") (pintype "bidirectional"))
      (node (ref "RGB30") (pin "6B") (pinfunction "GC_6B") (pintype "bidirectional"))
      (node (ref "RGB31") (pin "1") (pinfunction "GA_1") (pintype "bidirectional"))
      (node (ref "RGB31") (pin "1A") (pinfunction "GA_1A") (pintype "bidirectional"))
      (node (ref "RGB31") (pin "1B") (pinfunction "GA_1B") (pintype "bidirectional"))
    )
    (net (code "427") (name "Net-(RGB30-RC-Pad5)") (class "Default")
      (node (ref "RGB30") (pin "5") (pinfunction "RC_5") (pintype "bidirectional"))
      (node (ref "RGB30") (pin "5A") (pinfunction "RC_5A") (pintype "bidirectional"))
      (node (ref "RGB30") (pin "5B") (pinfunction "RC_5B") (pintype "bidirectional"))
      (node (ref "RGB31") (pin "2") (pinfunction "RA_2") (pintype "bidirectional"))
      (node (ref "RGB31") (pin "2A") (pinfunction "RA_2A") (pintype "bidirectional"))
      (node (ref "RGB31") (pin "2B") (pinfunction "RA_2B") (pintype "bidirectional"))
    )
    (net (code "428") (name "Net-(RGB31-BC-Pad4)") (class "Default")
      (node (ref "RGB31") (pin "4") (pinfunction "BC_4") (pintype "bidirectional"))
      (node (ref "RGB31") (pin "4A") (pinfunction "BC_4A") (pintype "bidirectional"))
      (node (ref "RGB31") (pin "4B") (pinfunction "BC_4B") (pintype "bidirectional"))
      (node (ref "RGB32") (pin "3") (pinfunction "BA_3") (pintype "bidirectional"))
      (node (ref "RGB32") (pin "3A") (pinfunction "BA_3A") (pintype "bidirectional"))
      (node (ref "RGB32") (pin "3B") (pinfunction "BA_3B") (pintype "bidirectional"))
    )
    (net (code "429") (name "Net-(RGB31-GC-Pad6)") (class "Default")
      (node (ref "RGB31") (pin "6") (pinfunction "GC_6") (pintype "bidirectional"))
      (node (ref "RGB31") (pin "6A") (pinfunction "GC_6A") (pintype "bidirectional"))
      (node (ref "RGB31") (pin "6B") (pinfunction "GC_6B") (pintype "bidirectional"))
      (node (ref "RGB32") (pin "1") (pinfunction "GA_1") (pintype "bidirectional"))
      (node (ref "RGB32") (pin "1A") (pinfunction "GA_1A") (pintype "bidirectional"))
      (node (ref "RGB32") (pin "1B") (pinfunction "GA_1B") (pintype "bidirectional"))
    )
    (net (code "430") (name "Net-(RGB31-RC-Pad5)") (class "Default")
      (node (ref "RGB31") (pin "5") (pinfunction "RC_5") (pintype "bidirectional"))
      (node (ref "RGB31") (pin "5A") (pinfunction "RC_5A") (pintype "bidirectional"))
      (node (ref "RGB31") (pin "5B") (pinfunction "RC_5B") (pintype "bidirectional"))
      (node (ref "RGB32") (pin "2") (pinfunction "RA_2") (pintype "bidirectional"))
      (node (ref "RGB32") (pin "2A") (pinfunction "RA_2A") (pintype "bidirectional"))
      (node (ref "RGB32") (pin "2B") (pinfunction "RA_2B") (pintype "bidirectional"))
    )
    (net (code "431") (name "Net-(RGB33-BA-Pad3)") (class "Default")
      (node (ref "RGB33") (pin "3") (pinfunction "BA_3") (pintype "bidirectional"))
      (node (ref "RGB33") (pin "3A") (pinfunction "BA_3A") (pintype "bidirectional"))
      (node (ref "RGB33") (pin "3B") (pinfunction "BA_3B") (pintype "bidirectional"))
      (node (ref "RGB34") (pin "4") (pinfunction "BC_4") (pintype "bidirectional"))
      (node (ref "RGB34") (pin "4A") (pinfunction "BC_4A") (pintype "bidirectional"))
      (node (ref "RGB34") (pin "4B") (pinfunction "BC_4B") (pintype "bidirectional"))
    )
    (net (code "432") (name "Net-(RGB33-GA-Pad1)") (class "Default")
      (node (ref "RGB33") (pin "1") (pinfunction "GA_1") (pintype "bidirectional"))
      (node (ref "RGB33") (pin "1A") (pinfunction "GA_1A") (pintype "bidirectional"))
      (node (ref "RGB33") (pin "1B") (pinfunction "GA_1B") (pintype "bidirectional"))
      (node (ref "RGB34") (pin "6") (pinfunction "GC_6") (pintype "bidirectional"))
      (node (ref "RGB34") (pin "6A") (pinfunction "GC_6A") (pintype "bidirectional"))
      (node (ref "RGB34") (pin "6B") (pinfunction "GC_6B") (pintype "bidirectional"))
    )
    (net (code "433") (name "Net-(RGB33-RA-Pad2)") (class "Default")
      (node (ref "RGB33") (pin "2") (pinfunction "RA_2") (pintype "bidirectional"))
      (node (ref "RGB33") (pin "2A") (pinfunction "RA_2A") (pintype "bidirectional"))
      (node (ref "RGB33") (pin "2B") (pinfunction "RA_2B") (pintype "bidirectional"))
      (node (ref "RGB34") (pin "5") (pinfunction "RC_5") (pintype "bidirectional"))
      (node (ref "RGB34") (pin "5A") (pinfunction "RC_5A") (pintype "bidirectional"))
      (node (ref "RGB34") (pin "5B") (pinfunction "RC_5B") (pintype "bidirectional"))
    )
    (net (code "434") (name "Net-(RGB34-BA-Pad3)") (class "Default")
      (node (ref "RGB34") (pin "3") (pinfunction "BA_3") (pintype "bidirectional"))
      (node (ref "RGB34") (pin "3A") (pinfunction "BA_3A") (pintype "bidirectional"))
      (node (ref "RGB34") (pin "3B") (pinfunction "BA_3B") (pintype "bidirectional"))
      (node (ref "RGB35") (pin "4") (pinfunction "BC_4") (pintype "bidirectional"))
      (node (ref "RGB35") (pin "4A") (pinfunction "BC_4A") (pintype "bidirectional"))
      (node (ref "RGB35") (pin "4B") (pinfunction "BC_4B") (pintype "bidirectional"))
    )
    (net (code "435") (name "Net-(RGB34-GA-Pad1)") (class "Default")
      (node (ref "RGB34") (pin "1") (pinfunction "GA_1") (pintype "bidirectional"))
      (node (ref "RGB34") (pin "1A") (pinfunction "GA_1A") (pintype "bidirectional"))
      (node (ref "RGB34") (pin "1B") (pinfunction "GA_1B") (pintype "bidirectional"))
      (node (ref "RGB35") (pin "6") (pinfunction "GC_6") (pintype "bidirectional"))
      (node (ref "RGB35") (pin "6A") (pinfunction "GC_6A") (pintype "bidirectional"))
      (node (ref "RGB35") (pin "6B") (pinfunction "GC_6B") (pintype "bidirectional"))
    )
    (net (code "436") (name "Net-(RGB34-RA-Pad2)") (class "Default")
      (node (ref "RGB34") (pin "2") (pinfunction "RA_2") (pintype "bidirectional"))
      (node (ref "RGB34") (pin "2A") (pinfunction "RA_2A") (pintype "bidirectional"))
      (node (ref "RGB34") (pin "2B") (pinfunction "RA_2B") (pintype "bidirectional"))
      (node (ref "RGB35") (pin "5") (pinfunction "RC_5") (pintype "bidirectional"))
      (node (ref "RGB35") (pin "5A") (pinfunction "RC_5A") (pintype "bidirectional"))
      (node (ref "RGB35") (pin "5B") (pinfunction "RC_5B") (pintype "bidirectional"))
    )
    (net (code "437") (name "Net-(RGB35-BA-Pad3)") (class "Default")
      (node (ref "RGB35") (pin "3") (pinfunction "BA_3") (pintype "bidirectional"))
      (node (ref "RGB35") (pin "3A") (pinfunction "BA_3A") (pintype "bidirectional"))
      (node (ref "RGB35") (pin "3B") (pinfunction "BA_3B") (pintype "bidirectional"))
      (node (ref "RGB36") (pin "4") (pinfunction "BC_4") (pintype "bidirectional"))
      (node (ref "RGB36") (pin "4A") (pinfunction "BC_4A") (pintype "bidirectional"))
      (node (ref "RGB36") (pin "4B") (pinfunction "BC_4B") (pintype "bidirectional"))
    )
    (net (code "438") (name "Net-(RGB35-GA-Pad1)") (class "Default")
      (node (ref "RGB35") (pin "1") (pinfunction "GA_1") (pintype "bidirectional"))
      (node (ref "RGB35") (pin "1A") (pinfunction "GA_1A") (pintype "bidirectional"))
      (node (ref "RGB35") (pin "1B") (pinfunction "GA_1B") (pintype "bidirectional"))
      (node (ref "RGB36") (pin "6") (pinfunction "GC_6") (pintype "bidirectional"))
      (node (ref "RGB36") (pin "6A") (pinfunction "GC_6A") (pintype "bidirectional"))
      (node (ref "RGB36") (pin "6B") (pinfunction "GC_6B") (pintype "bidirectional"))
    )
    (net (code "439") (name "Net-(RGB35-RA-Pad2)") (class "Default")
      (node (ref "RGB35") (pin "2") (pinfunction "RA_2") (pintype "bidirectional"))
      (node (ref "RGB35") (pin "2A") (pinfunction "RA_2A") (pintype "bidirectional"))
      (node (ref "RGB35") (pin "2B") (pinfunction "RA_2B") (pintype "bidirectional"))
      (node (ref "RGB36") (pin "5") (pinfunction "RC_5") (pintype "bidirectional"))
      (node (ref "RGB36") (pin "5A") (pinfunction "RC_5A") (pintype "bidirectional"))
      (node (ref "RGB36") (pin "5B") (pinfunction "RC_5B") (pintype "bidirectional"))
    )
    (net (code "440") (name "Net-(RGB36-BA-Pad3)") (class "Default")
      (node (ref "RGB36") (pin "3") (pinfunction "BA_3") (pintype "bidirectional"))
      (node (ref "RGB36") (pin "3A") (pinfunction "BA_3A") (pintype "bidirectional"))
      (node (ref "RGB36") (pin "3B") (pinfunction "BA_3B") (pintype "bidirectional"))
      (node (ref "RGB44") (pin "4") (pinfunction "BC_4") (pintype "bidirectional"))
      (node (ref "RGB44") (pin "4A") (pinfunction "BC_4A") (pintype "bidirectional"))
      (node (ref "RGB44") (pin "4B") (pinfunction "BC_4B") (pintype "bidirectional"))
    )
    (net (code "441") (name "Net-(RGB36-GA-Pad1)") (class "Default")
      (node (ref "RGB36") (pin "1") (pinfunction "GA_1") (pintype "bidirectional"))
      (node (ref "RGB36") (pin "1A") (pinfunction "GA_1A") (pintype "bidirectional"))
      (node (ref "RGB36") (pin "1B") (pinfunction "GA_1B") (pintype "bidirectional"))
      (node (ref "RGB44") (pin "6") (pinfunction "GC_6") (pintype "bidirectional"))
      (node (ref "RGB44") (pin "6A") (pinfunction "GC_6A") (pintype "bidirectional"))
      (node (ref "RGB44") (pin "6B") (pinfunction "GC_6B") (pintype "bidirectional"))
    )
    (net (code "442") (name "Net-(RGB36-RA-Pad2)") (class "Default")
      (node (ref "RGB36") (pin "2") (pinfunction "RA_2") (pintype "bidirectional"))
      (node (ref "RGB36") (pin "2A") (pinfunction "RA_2A") (pintype "bidirectional"))
      (node (ref "RGB36") (pin "2B") (pinfunction "RA_2B") (pintype "bidirectional"))
      (node (ref "RGB44") (pin "5") (pinfunction "RC_5") (pintype "bidirectional"))
      (node (ref "RGB44") (pin "5A") (pinfunction "RC_5A") (pintype "bidirectional"))
      (node (ref "RGB44") (pin "5B") (pinfunction "RC_5B") (pintype "bidirectional"))
    )
    (net (code "443") (name "Net-(RGB37-BA-Pad3)") (class "Default")
      (node (ref "RGB37") (pin "3") (pinfunction "BA_3") (pintype "bidirectional"))
      (node (ref "RGB37") (pin "3A") (pinfunction "BA_3A") (pintype "bidirectional"))
      (node (ref "RGB37") (pin "3B") (pinfunction "BA_3B") (pintype "bidirectional"))
      (node (ref "RGB38") (pin "4") (pinfunction "BC_4") (pintype "bidirectional"))
      (node (ref "RGB38") (pin "4A") (pinfunction "BC_4A") (pintype "bidirectional"))
      (node (ref "RGB38") (pin "4B") (pinfunction "BC_4B") (pintype "bidirectional"))
    )
    (net (code "444") (name "Net-(RGB37-GA-Pad1)") (class "Default")
      (node (ref "RGB37") (pin "1") (pinfunction "GA_1") (pintype "bidirectional"))
      (node (ref "RGB37") (pin "1A") (pinfunction "GA_1A") (pintype "bidirectional"))
      (node (ref "RGB37") (pin "1B") (pinfunction "GA_1B") (pintype "bidirectional"))
      (node (ref "RGB38") (pin "6") (pinfunction "GC_6") (pintype "bidirectional"))
      (node (ref "RGB38") (pin "6A") (pinfunction "GC_6A") (pintype "bidirectional"))
      (node (ref "RGB38") (pin "6B") (pinfunction "GC_6B") (pintype "bidirectional"))
    )
    (net (code "445") (name "Net-(RGB37-RA-Pad2)") (class "Default")
      (node (ref "RGB37") (pin "2") (pinfunction "RA_2") (pintype "bidirectional"))
      (node (ref "RGB37") (pin "2A") (pinfunction "RA_2A") (pintype "bidirectional"))
      (node (ref "RGB37") (pin "2B") (pinfunction "RA_2B") (pintype "bidirectional"))
      (node (ref "RGB38") (pin "5") (pinfunction "RC_5") (pintype "bidirectional"))
      (node (ref "RGB38") (pin "5A") (pinfunction "RC_5A") (pintype "bidirectional"))
      (node (ref "RGB38") (pin "5B") (pinfunction "RC_5B") (pintype "bidirectional"))
    )
    (net (code "446") (name "Net-(RGB38-BA-Pad3)") (class "Default")
      (node (ref "RGB38") (pin "3") (pinfunction "BA_3") (pintype "bidirectional"))
      (node (ref "RGB38") (pin "3A") (pinfunction "BA_3A") (pintype "bidirectional"))
      (node (ref "RGB38") (pin "3B") (pinfunction "BA_3B") (pintype "bidirectional"))
      (node (ref "RGB39") (pin "4") (pinfunction "BC_4") (pintype "bidirectional"))
      (node (ref "RGB39") (pin "4A") (pinfunction "BC_4A") (pintype "bidirectional"))
      (node (ref "RGB39") (pin "4B") (pinfunction "BC_4B") (pintype "bidirectional"))
    )
    (net (code "447") (name "Net-(RGB38-GA-Pad1)") (class "Default")
      (node (ref "RGB38") (pin "1") (pinfunction "GA_1") (pintype "bidirectional"))
      (node (ref "RGB38") (pin "1A") (pinfunction "GA_1A") (pintype "bidirectional"))
      (node (ref "RGB38") (pin "1B") (pinfunction "GA_1B") (pintype "bidirectional"))
      (node (ref "RGB39") (pin "6") (pinfunction "GC_6") (pintype "bidirectional"))
      (node (ref "RGB39") (pin "6A") (pinfunction "GC_6A") (pintype "bidirectional"))
      (node (ref "RGB39") (pin "6B") (pinfunction "GC_6B") (pintype "bidirectional"))
    )
    (net (code "448") (name "Net-(RGB38-RA-Pad2)") (class "Default")
      (node (ref "RGB38") (pin "2") (pinfunction "RA_2") (pintype "bidirectional"))
      (node (ref "RGB38") (pin "2A") (pinfunction "RA_2A") (pintype "bidirectional"))
      (node (ref "RGB38") (pin "2B") (pinfunction "RA_2B") (pintype "bidirectional"))
      (node (ref "RGB39") (pin "5") (pinfunction "RC_5") (pintype "bidirectional"))
      (node (ref "RGB39") (pin "5A") (pinfunction "RC_5A") (pintype "bidirectional"))
      (node (ref "RGB39") (pin "5B") (pinfunction "RC_5B") (pintype "bidirectional"))
    )
    (net (code "449") (name "Net-(RGB39-BA-Pad3)") (class "Default")
      (node (ref "RGB39") (pin "3") (pinfunction "BA_3") (pintype "bidirectional"))
      (node (ref "RGB39") (pin "3A") (pinfunction "BA_3A") (pintype "bidirectional"))
      (node (ref "RGB39") (pin "3B") (pinfunction "BA_3B") (pintype "bidirectional"))
      (node (ref "RGB40") (pin "4") (pinfunction "BC_4") (pintype "bidirectional"))
      (node (ref "RGB40") (pin "4A") (pinfunction "BC_4A") (pintype "bidirectional"))
      (node (ref "RGB40") (pin "4B") (pinfunction "BC_4B") (pintype "bidirectional"))
    )
    (net (code "450") (name "Net-(RGB39-GA-Pad1)") (class "Default")
      (node (ref "RGB39") (pin "1") (pinfunction "GA_1") (pintype "bidirectional"))
      (node (ref "RGB39") (pin "1A") (pinfunction "GA_1A") (pintype "bidirectional"))
      (node (ref "RGB39") (pin "1B") (pinfunction "GA_1B") (pintype "bidirectional"))
      (node (ref "RGB40") (pin "6") (pinfunction "GC_6") (pintype "bidirectional"))
      (node (ref "RGB40") (pin "6A") (pinfunction "GC_6A") (pintype "bidirectional"))
      (node (ref "RGB40") (pin "6B") (pinfunction "GC_6B") (pintype "bidirectional"))
    )
    (net (code "451") (name "Net-(RGB39-RA-Pad2)") (class "Default")
      (node (ref "RGB39") (pin "2") (pinfunction "RA_2") (pintype "bidirectional"))
      (node (ref "RGB39") (pin "2A") (pinfunction "RA_2A") (pintype "bidirectional"))
      (node (ref "RGB39") (pin "2B") (pinfunction "RA_2B") (pintype "bidirectional"))
      (node (ref "RGB40") (pin "5") (pinfunction "RC_5") (pintype "bidirectional"))
      (node (ref "RGB40") (pin "5A") (pinfunction "RC_5A") (pintype "bidirectional"))
      (node (ref "RGB40") (pin "5B") (pinfunction "RC_5B") (pintype "bidirectional"))
    )
    (net (code "452") (name "Net-(RGB40-BA-Pad3)") (class "Default")
      (node (ref "RGB40") (pin "3") (pinfunction "BA_3") (pintype "bidirectional"))
      (node (ref "RGB40") (pin "3A") (pinfunction "BA_3A") (pintype "bidirectional"))
      (node (ref "RGB40") (pin "3B") (pinfunction "BA_3B") (pintype "bidirectional"))
      (node (ref "RGB48") (pin "4") (pinfunction "BC_4") (pintype "bidirectional"))
      (node (ref "RGB48") (pin "4A") (pinfunction "BC_4A") (pintype "bidirectional"))
      (node (ref "RGB48") (pin "4B") (pinfunction "BC_4B") (pintype "bidirectional"))
    )
    (net (code "453") (name "Net-(RGB40-GA-Pad1)") (class "Default")
      (node (ref "RGB40") (pin "1") (pinfunction "GA_1") (pintype "bidirectional"))
      (node (ref "RGB40") (pin "1A") (pinfunction "GA_1A") (pintype "bidirectional"))
      (node (ref "RGB40") (pin "1B") (pinfunction "GA_1B") (pintype "bidirectional"))
      (node (ref "RGB48") (pin "6") (pinfunction "GC_6") (pintype "bidirectional"))
      (node (ref "RGB48") (pin "6A") (pinfunction "GC_6A") (pintype "bidirectional"))
      (node (ref "RGB48") (pin "6B") (pinfunction "GC_6B") (pintype "bidirectional"))
    )
    (net (code "454") (name "Net-(RGB40-RA-Pad2)") (class "Default")
      (node (ref "RGB40") (pin "2") (pinfunction "RA_2") (pintype "bidirectional"))
      (node (ref "RGB40") (pin "2A") (pinfunction "RA_2A") (pintype "bidirectional"))
      (node (ref "RGB40") (pin "2B") (pinfunction "RA_2B") (pintype "bidirectional"))
      (node (ref "RGB48") (pin "5") (pinfunction "RC_5") (pintype "bidirectional"))
      (node (ref "RGB48") (pin "5A") (pinfunction "RC_5A") (pintype "bidirectional"))
      (node (ref "RGB48") (pin "5B") (pinfunction "RC_5B") (pintype "bidirectional"))
    )
    (net (code "455") (name "Net-(RGB41-BC-Pad4)") (class "Default")
      (node (ref "RGB41") (pin "4") (pinfunction "BC_4") (pintype "bidirectional"))
      (node (ref "RGB41") (pin "4A") (pinfunction "BC_4A") (pintype "bidirectional"))
      (node (ref "RGB41") (pin "4B") (pinfunction "BC_4B") (pintype "bidirectional"))
      (node (ref "RGB42") (pin "3") (pinfunction "BA_3") (pintype "bidirectional"))
      (node (ref "RGB42") (pin "3A") (pinfunction "BA_3A") (pintype "bidirectional"))
      (node (ref "RGB42") (pin "3B") (pinfunction "BA_3B") (pintype "bidirectional"))
    )
    (net (code "456") (name "Net-(RGB41-GC-Pad6)") (class "Default")
      (node (ref "RGB41") (pin "6") (pinfunction "GC_6") (pintype "bidirectional"))
      (node (ref "RGB41") (pin "6A") (pinfunction "GC_6A") (pintype "bidirectional"))
      (node (ref "RGB41") (pin "6B") (pinfunction "GC_6B") (pintype "bidirectional"))
      (node (ref "RGB42") (pin "1") (pinfunction "GA_1") (pintype "bidirectional"))
      (node (ref "RGB42") (pin "1A") (pinfunction "GA_1A") (pintype "bidirectional"))
      (node (ref "RGB42") (pin "1B") (pinfunction "GA_1B") (pintype "bidirectional"))
    )
    (net (code "457") (name "Net-(RGB41-RC-Pad5)") (class "Default")
      (node (ref "RGB41") (pin "5") (pinfunction "RC_5") (pintype "bidirectional"))
      (node (ref "RGB41") (pin "5A") (pinfunction "RC_5A") (pintype "bidirectional"))
      (node (ref "RGB41") (pin "5B") (pinfunction "RC_5B") (pintype "bidirectional"))
      (node (ref "RGB42") (pin "2") (pinfunction "RA_2") (pintype "bidirectional"))
      (node (ref "RGB42") (pin "2A") (pinfunction "RA_2A") (pintype "bidirectional"))
      (node (ref "RGB42") (pin "2B") (pinfunction "RA_2B") (pintype "bidirectional"))
    )
    (net (code "458") (name "Net-(RGB42-BC-Pad4)") (class "Default")
      (node (ref "RGB42") (pin "4") (pinfunction "BC_4") (pintype "bidirectional"))
      (node (ref "RGB42") (pin "4A") (pinfunction "BC_4A") (pintype "bidirectional"))
      (node (ref "RGB42") (pin "4B") (pinfunction "BC_4B") (pintype "bidirectional"))
      (node (ref "RGB43") (pin "3") (pinfunction "BA_3") (pintype "bidirectional"))
      (node (ref "RGB43") (pin "3A") (pinfunction "BA_3A") (pintype "bidirectional"))
      (node (ref "RGB43") (pin "3B") (pinfunction "BA_3B") (pintype "bidirectional"))
    )
    (net (code "459") (name "Net-(RGB42-GC-Pad6)") (class "Default")
      (node (ref "RGB42") (pin "6") (pinfunction "GC_6") (pintype "bidirectional"))
      (node (ref "RGB42") (pin "6A") (pinfunction "GC_6A") (pintype "bidirectional"))
      (node (ref "RGB42") (pin "6B") (pinfunction "GC_6B") (pintype "bidirectional"))
      (node (ref "RGB43") (pin "1") (pinfunction "GA_1") (pintype "bidirectional"))
      (node (ref "RGB43") (pin "1A") (pinfunction "GA_1A") (pintype "bidirectional"))
      (node (ref "RGB43") (pin "1B") (pinfunction "GA_1B") (pintype "bidirectional"))
    )
    (net (code "460") (name "Net-(RGB42-RC-Pad5)") (class "Default")
      (node (ref "RGB42") (pin "5") (pinfunction "RC_5") (pintype "bidirectional"))
      (node (ref "RGB42") (pin "5A") (pinfunction "RC_5A") (pintype "bidirectional"))
      (node (ref "RGB42") (pin "5B") (pinfunction "RC_5B") (pintype "bidirectional"))
      (node (ref "RGB43") (pin "2") (pinfunction "RA_2") (pintype "bidirectional"))
      (node (ref "RGB43") (pin "2A") (pinfunction "RA_2A") (pintype "bidirectional"))
      (node (ref "RGB43") (pin "2B") (pinfunction "RA_2B") (pintype "bidirectional"))
    )
    (net (code "461") (name "Net-(RGB43-BC-Pad4)") (class "Default")
      (node (ref "RGB43") (pin "4") (pinfunction "BC_4") (pintype "bidirectional"))
      (node (ref "RGB43") (pin "4A") (pinfunction "BC_4A") (pintype "bidirectional"))
      (node (ref "RGB43") (pin "4B") (pinfunction "BC_4B") (pintype "bidirectional"))
      (node (ref "RGB44") (pin "3") (pinfunction "BA_3") (pintype "bidirectional"))
      (node (ref "RGB44") (pin "3A") (pinfunction "BA_3A") (pintype "bidirectional"))
      (node (ref "RGB44") (pin "3B") (pinfunction "BA_3B") (pintype "bidirectional"))
    )
    (net (code "462") (name "Net-(RGB43-GC-Pad6)") (class "Default")
      (node (ref "RGB43") (pin "6") (pinfunction "GC_6") (pintype "bidirectional"))
      (node (ref "RGB43") (pin "6A") (pinfunction "GC_6A") (pintype "bidirectional"))
      (node (ref "RGB43") (pin "6B") (pinfunction "GC_6B") (pintype "bidirectional"))
      (node (ref "RGB44") (pin "1") (pinfunction "GA_1") (pintype "bidirectional"))
      (node (ref "RGB44") (pin "1A") (pinfunction "GA_1A") (pintype "bidirectional"))
      (node (ref "RGB44") (pin "1B") (pinfunction "GA_1B") (pintype "bidirectional"))
    )
    (net (code "463") (name "Net-(RGB43-RC-Pad5)") (class "Default")
      (node (ref "RGB43") (pin "5") (pinfunction "RC_5") (pintype "bidirectional"))
      (node (ref "RGB43") (pin "5A") (pinfunction "RC_5A") (pintype "bidirectional"))
      (node (ref "RGB43") (pin "5B") (pinfunction "RC_5B") (pintype "bidirectional"))
      (node (ref "RGB44") (pin "2") (pinfunction "RA_2") (pintype "bidirectional"))
      (node (ref "RGB44") (pin "2A") (pinfunction "RA_2A") (pintype "bidirectional"))
      (node (ref "RGB44") (pin "2B") (pinfunction "RA_2B") (pintype "bidirectional"))
    )
    (net (code "464") (name "Net-(RGB45-BC-Pad4)") (class "Default")
      (node (ref "RGB45") (pin "4") (pinfunction "BC_4") (pintype "bidirectional"))
      (node (ref "RGB45") (pin "4A") (pinfunction "BC_4A") (pintype "bidirectional"))
      (node (ref "RGB45") (pin "4B") (pinfunction "BC_4B") (pintype "bidirectional"))
      (node (ref "RGB46") (pin "3") (pinfunction "BA_3") (pintype "bidirectional"))
      (node (ref "RGB46") (pin "3A") (pinfunction "BA_3A") (pintype "bidirectional"))
      (node (ref "RGB46") (pin "3B") (pinfunction "BA_3B") (pintype "bidirectional"))
    )
    (net (code "465") (name "Net-(RGB45-GC-Pad6)") (class "Default")
      (node (ref "RGB45") (pin "6") (pinfunction "GC_6") (pintype "bidirectional"))
      (node (ref "RGB45") (pin "6A") (pinfunction "GC_6A") (pintype "bidirectional"))
      (node (ref "RGB45") (pin "6B") (pinfunction "GC_6B") (pintype "bidirectional"))
      (node (ref "RGB46") (pin "1") (pinfunction "GA_1") (pintype "bidirectional"))
      (node (ref "RGB46") (pin "1A") (pinfunction "GA_1A") (pintype "bidirectional"))
      (node (ref "RGB46") (pin "1B") (pinfunction "GA_1B") (pintype "bidirectional"))
    )
    (net (code "466") (name "Net-(RGB45-RC-Pad5)") (class "Default")
      (node (ref "RGB45") (pin "5") (pinfunction "RC_5") (pintype "bidirectional"))
      (node (ref "RGB45") (pin "5A") (pinfunction "RC_5A") (pintype "bidirectional"))
      (node (ref "RGB45") (pin "5B") (pinfunction "RC_5B") (pintype "bidirectional"))
      (node (ref "RGB46") (pin "2") (pinfunction "RA_2") (pintype "bidirectional"))
      (node (ref "RGB46") (pin "2A") (pinfunction "RA_2A") (pintype "bidirectional"))
      (node (ref "RGB46") (pin "2B") (pinfunction "RA_2B") (pintype "bidirectional"))
    )
    (net (code "467") (name "Net-(RGB46-BC-Pad4)") (class "Default")
      (node (ref "RGB46") (pin "4") (pinfunction "BC_4") (pintype "bidirectional"))
      (node (ref "RGB46") (pin "4A") (pinfunction "BC_4A") (pintype "bidirectional"))
      (node (ref "RGB46") (pin "4B") (pinfunction "BC_4B") (pintype "bidirectional"))
      (node (ref "RGB47") (pin "3") (pinfunction "BA_3") (pintype "bidirectional"))
      (node (ref "RGB47") (pin "3A") (pinfunction "BA_3A") (pintype "bidirectional"))
      (node (ref "RGB47") (pin "3B") (pinfunction "BA_3B") (pintype "bidirectional"))
    )
    (net (code "468") (name "Net-(RGB46-GC-Pad6)") (class "Default")
      (node (ref "RGB46") (pin "6") (pinfunction "GC_6") (pintype "bidirectional"))
      (node (ref "RGB46") (pin "6A") (pinfunction "GC_6A") (pintype "bidirectional"))
      (node (ref "RGB46") (pin "6B") (pinfunction "GC_6B") (pintype "bidirectional"))
      (node (ref "RGB47") (pin "1") (pinfunction "GA_1") (pintype "bidirectional"))
      (node (ref "RGB47") (pin "1A") (pinfunction "GA_1A") (pintype "bidirectional"))
      (node (ref "RGB47") (pin "1B") (pinfunction "GA_1B") (pintype "bidirectional"))
    )
    (net (code "469") (name "Net-(RGB46-RC-Pad5)") (class "Default")
      (node (ref "RGB46") (pin "5") (pinfunction "RC_5") (pintype "bidirectional"))
      (node (ref "RGB46") (pin "5A") (pinfunction "RC_5A") (pintype "bidirectional"))
      (node (ref "RGB46") (pin "5B") (pinfunction "RC_5B") (pintype "bidirectional"))
      (node (ref "RGB47") (pin "2") (pinfunction "RA_2") (pintype "bidirectional"))
      (node (ref "RGB47") (pin "2A") (pinfunction "RA_2A") (pintype "bidirectional"))
      (node (ref "RGB47") (pin "2B") (pinfunction "RA_2B") (pintype "bidirectional"))
    )
    (net (code "470") (name "Net-(RGB47-BC-Pad4)") (class "Default")
      (node (ref "RGB47") (pin "4") (pinfunction "BC_4") (pintype "bidirectional"))
      (node (ref "RGB47") (pin "4A") (pinfunction "BC_4A") (pintype "bidirectional"))
      (node (ref "RGB47") (pin "4B") (pinfunction "BC_4B") (pintype "bidirectional"))
      (node (ref "RGB48") (pin "3") (pinfunction "BA_3") (pintype "bidirectional"))
      (node (ref "RGB48") (pin "3A") (pinfunction "BA_3A") (pintype "bidirectional"))
      (node (ref "RGB48") (pin "3B") (pinfunction "BA_3B") (pintype "bidirectional"))
    )
    (net (code "471") (name "Net-(RGB47-GC-Pad6)") (class "Default")
      (node (ref "RGB47") (pin "6") (pinfunction "GC_6") (pintype "bidirectional"))
      (node (ref "RGB47") (pin "6A") (pinfunction "GC_6A") (pintype "bidirectional"))
      (node (ref "RGB47") (pin "6B") (pinfunction "GC_6B") (pintype "bidirectional"))
      (node (ref "RGB48") (pin "1") (pinfunction "GA_1") (pintype "bidirectional"))
      (node (ref "RGB48") (pin "1A") (pinfunction "GA_1A") (pintype "bidirectional"))
      (node (ref "RGB48") (pin "1B") (pinfunction "GA_1B") (pintype "bidirectional"))
    )
    (net (code "472") (name "Net-(RGB47-RC-Pad5)") (class "Default")
      (node (ref "RGB47") (pin "5") (pinfunction "RC_5") (pintype "bidirectional"))
      (node (ref "RGB47") (pin "5A") (pinfunction "RC_5A") (pintype "bidirectional"))
      (node (ref "RGB47") (pin "5B") (pinfunction "RC_5B") (pintype "bidirectional"))
      (node (ref "RGB48") (pin "2") (pinfunction "RA_2") (pintype "bidirectional"))
      (node (ref "RGB48") (pin "2A") (pinfunction "RA_2A") (pintype "bidirectional"))
      (node (ref "RGB48") (pin "2B") (pinfunction "RA_2B") (pintype "bidirectional"))
    )
    (net (code "473") (name "Net-(RGB49-BA-Pad3)") (class "Default")
      (node (ref "RGB49") (pin "3") (pinfunction "BA_3") (pintype "bidirectional"))
      (node (ref "RGB49") (pin "3A") (pinfunction "BA_3A") (pintype "bidirectional"))
      (node (ref "RGB49") (pin "3B") (pinfunction "BA_3B") (pintype "bidirectional"))
      (node (ref "RGB50") (pin "4") (pinfunction "BC_4") (pintype "bidirectional"))
      (node (ref "RGB50") (pin "4A") (pinfunction "BC_4A") (pintype "bidirectional"))
      (node (ref "RGB50") (pin "4B") (pinfunction "BC_4B") (pintype "bidirectional"))
    )
    (net (code "474") (name "Net-(RGB49-GA-Pad1)") (class "Default")
      (node (ref "RGB49") (pin "1") (pinfunction "GA_1") (pintype "bidirectional"))
      (node (ref "RGB49") (pin "1A") (pinfunction "GA_1A") (pintype "bidirectional"))
      (node (ref "RGB49") (pin "1B") (pinfunction "GA_1B") (pintype "bidirectional"))
      (node (ref "RGB50") (pin "6") (pinfunction "GC_6") (pintype "bidirectional"))
      (node (ref "RGB50") (pin "6A") (pinfunction "GC_6A") (pintype "bidirectional"))
      (node (ref "RGB50") (pin "6B") (pinfunction "GC_6B") (pintype "bidirectional"))
    )
    (net (code "475") (name "Net-(RGB49-RA-Pad2)") (class "Default")
      (node (ref "RGB49") (pin "2") (pinfunction "RA_2") (pintype "bidirectional"))
      (node (ref "RGB49") (pin "2A") (pinfunction "RA_2A") (pintype "bidirectional"))
      (node (ref "RGB49") (pin "2B") (pinfunction "RA_2B") (pintype "bidirectional"))
      (node (ref "RGB50") (pin "5") (pinfunction "RC_5") (pintype "bidirectional"))
      (node (ref "RGB50") (pin "5A") (pinfunction "RC_5A") (pintype "bidirectional"))
      (node (ref "RGB50") (pin "5B") (pinfunction "RC_5B") (pintype "bidirectional"))
    )
    (net (code "476") (name "Net-(RGB50-BA-Pad3)") (class "Default")
      (node (ref "RGB50") (pin "3") (pinfunction "BA_3") (pintype "bidirectional"))
      (node (ref "RGB50") (pin "3A") (pinfunction "BA_3A") (pintype "bidirectional"))
      (node (ref "RGB50") (pin "3B") (pinfunction "BA_3B") (pintype "bidirectional"))
      (node (ref "RGB51") (pin "4") (pinfunction "BC_4") (pintype "bidirectional"))
      (node (ref "RGB51") (pin "4A") (pinfunction "BC_4A") (pintype "bidirectional"))
      (node (ref "RGB51") (pin "4B") (pinfunction "BC_4B") (pintype "bidirectional"))
    )
    (net (code "477") (name "Net-(RGB50-GA-Pad1)") (class "Default")
      (node (ref "RGB50") (pin "1") (pinfunction "GA_1") (pintype "bidirectional"))
      (node (ref "RGB50") (pin "1A") (pinfunction "GA_1A") (pintype "bidirectional"))
      (node (ref "RGB50") (pin "1B") (pinfunction "GA_1B") (pintype "bidirectional"))
      (node (ref "RGB51") (pin "6") (pinfunction "GC_6") (pintype "bidirectional"))
      (node (ref "RGB51") (pin "6A") (pinfunction "GC_6A") (pintype "bidirectional"))
      (node (ref "RGB51") (pin "6B") (pinfunction "GC_6B") (pintype "bidirectional"))
    )
    (net (code "478") (name "Net-(RGB50-RA-Pad2)") (class "Default")
      (node (ref "RGB50") (pin "2") (pinfunction "RA_2") (pintype "bidirectional"))
      (node (ref "RGB50") (pin "2A") (pinfunction "RA_2A") (pintype "bidirectional"))
      (node (ref "RGB50") (pin "2B") (pinfunction "RA_2B") (pintype "bidirectional"))
      (node (ref "RGB51") (pin "5") (pinfunction "RC_5") (pintype "bidirectional"))
      (node (ref "RGB51") (pin "5A") (pinfunction "RC_5A") (pintype "bidirectional"))
      (node (ref "RGB51") (pin "5B") (pinfunction "RC_5B") (pintype "bidirectional"))
    )
    (net (code "479") (name "Net-(RGB51-BA-Pad3)") (class "Default")
      (node (ref "RGB51") (pin "3") (pinfunction "BA_3") (pintype "bidirectional"))
      (node (ref "RGB51") (pin "3A") (pinfunction "BA_3A") (pintype "bidirectional"))
      (node (ref "RGB51") (pin "3B") (pinfunction "BA_3B") (pintype "bidirectional"))
      (node (ref "RGB52") (pin "4") (pinfunction "BC_4") (pintype "bidirectional"))
      (node (ref "RGB52") (pin "4A") (pinfunction "BC_4A") (pintype "bidirectional"))
      (node (ref "RGB52") (pin "4B") (pinfunction "BC_4B") (pintype "bidirectional"))
    )
    (net (code "480") (name "Net-(RGB51-GA-Pad1)") (class "Default")
      (node (ref "RGB51") (pin "1") (pinfunction "GA_1") (pintype "bidirectional"))
      (node (ref "RGB51") (pin "1A") (pinfunction "GA_1A") (pintype "bidirectional"))
      (node (ref "RGB51") (pin "1B") (pinfunction "GA_1B") (pintype "bidirectional"))
      (node (ref "RGB52") (pin "6") (pinfunction "GC_6") (pintype "bidirectional"))
      (node (ref "RGB52") (pin "6A") (pinfunction "GC_6A") (pintype "bidirectional"))
      (node (ref "RGB52") (pin "6B") (pinfunction "GC_6B") (pintype "bidirectional"))
    )
    (net (code "481") (name "Net-(RGB51-RA-Pad2)") (class "Default")
      (node (ref "RGB51") (pin "2") (pinfunction "RA_2") (pintype "bidirectional"))
      (node (ref "RGB51") (pin "2A") (pinfunction "RA_2A") (pintype "bidirectional"))
      (node (ref "RGB51") (pin "2B") (pinfunction "RA_2B") (pintype "bidirectional"))
      (node (ref "RGB52") (pin "5") (pinfunction "RC_5") (pintype "bidirectional"))
      (node (ref "RGB52") (pin "5A") (pinfunction "RC_5A") (pintype "bidirectional"))
      (node (ref "RGB52") (pin "5B") (pinfunction "RC_5B") (pintype "bidirectional"))
    )
    (net (code "482") (name "Net-(RGB52-BA-Pad3)") (class "Default")
      (node (ref "RGB52") (pin "3") (pinfunction "BA_3") (pintype "bidirectional"))
      (node (ref "RGB52") (pin "3A") (pinfunction "BA_3A") (pintype "bidirectional"))
      (node (ref "RGB52") (pin "3B") (pinfunction "BA_3B") (pintype "bidirectional"))
      (node (ref "RGB60") (pin "4") (pinfunction "BC_4") (pintype "bidirectional"))
      (node (ref "RGB60") (pin "4A") (pinfunction "BC_4A") (pintype "bidirectional"))
      (node (ref "RGB60") (pin "4B") (pinfunction "BC_4B") (pintype "bidirectional"))
    )
    (net (code "483") (name "Net-(RGB52-GA-Pad1)") (class "Default")
      (node (ref "RGB52") (pin "1") (pinfunction "GA_1") (pintype "bidirectional"))
      (node (ref "RGB52") (pin "1A") (pinfunction "GA_1A") (pintype "bidirectional"))
      (node (ref "RGB52") (pin "1B") (pinfunction "GA_1B") (pintype "bidirectional"))
      (node (ref "RGB60") (pin "6") (pinfunction "GC_6") (pintype "bidirectional"))
      (node (ref "RGB60") (pin "6A") (pinfunction "GC_6A") (pintype "bidirectional"))
      (node (ref "RGB60") (pin "6B") (pinfunction "GC_6B") (pintype "bidirectional"))
    )
    (net (code "484") (name "Net-(RGB52-RA-Pad2)") (class "Default")
      (node (ref "RGB52") (pin "2") (pinfunction "RA_2") (pintype "bidirectional"))
      (node (ref "RGB52") (pin "2A") (pinfunction "RA_2A") (pintype "bidirectional"))
      (node (ref "RGB52") (pin "2B") (pinfunction "RA_2B") (pintype "bidirectional"))
      (node (ref "RGB60") (pin "5") (pinfunction "RC_5") (pintype "bidirectional"))
      (node (ref "RGB60") (pin "5A") (pinfunction "RC_5A") (pintype "bidirectional"))
      (node (ref "RGB60") (pin "5B") (pinfunction "RC_5B") (pintype "bidirectional"))
    )
    (net (code "485") (name "Net-(RGB53-BA-Pad3)") (class "Default")
      (node (ref "RGB53") (pin "3") (pinfunction "BA_3") (pintype "bidirectional"))
      (node (ref "RGB53") (pin "3A") (pinfunction "BA_3A") (pintype "bidirectional"))
      (node (ref "RGB53") (pin "3B") (pinfunction "BA_3B") (pintype "bidirectional"))
      (node (ref "RGB54") (pin "4") (pinfunction "BC_4") (pintype "bidirectional"))
      (node (ref "RGB54") (pin "4A") (pinfunction "BC_4A") (pintype "bidirectional"))
      (node (ref "RGB54") (pin "4B") (pinfunction "BC_4B") (pintype "bidirectional"))
    )
    (net (code "486") (name "Net-(RGB53-GA-Pad1)") (class "Default")
      (node (ref "RGB53") (pin "1") (pinfunction "GA_1") (pintype "bidirectional"))
      (node (ref "RGB53") (pin "1A") (pinfunction "GA_1A") (pintype "bidirectional"))
      (node (ref "RGB53") (pin "1B") (pinfunction "GA_1B") (pintype "bidirectional"))
      (node (ref "RGB54") (pin "6") (pinfunction "GC_6") (pintype "bidirectional"))
      (node (ref "RGB54") (pin "6A") (pinfunction "GC_6A") (pintype "bidirectional"))
      (node (ref "RGB54") (pin "6B") (pinfunction "GC_6B") (pintype "bidirectional"))
    )
    (net (code "487") (name "Net-(RGB53-RA-Pad2)") (class "Default")
      (node (ref "RGB53") (pin "2") (pinfunction "RA_2") (pintype "bidirectional"))
      (node (ref "RGB53") (pin "2A") (pinfunction "RA_2A") (pintype "bidirectional"))
      (node (ref "RGB53") (pin "2B") (pinfunction "RA_2B") (pintype "bidirectional"))
      (node (ref "RGB54") (pin "5") (pinfunction "RC_5") (pintype "bidirectional"))
      (node (ref "RGB54") (pin "5A") (pinfunction "RC_5A") (pintype "bidirectional"))
      (node (ref "RGB54") (pin "5B") (pinfunction "RC_5B") (pintype "bidirectional"))
    )
    (net (code "488") (name "Net-(RGB54-BA-Pad3)") (class "Default")
      (node (ref "RGB54") (pin "3") (pinfunction "BA_3") (pintype "bidirectional"))
      (node (ref "RGB54") (pin "3A") (pinfunction "BA_3A") (pintype "bidirectional"))
      (node (ref "RGB54") (pin "3B") (pinfunction "BA_3B") (pintype "bidirectional"))
      (node (ref "RGB55") (pin "4") (pinfunction "BC_4") (pintype "bidirectional"))
      (node (ref "RGB55") (pin "4A") (pinfunction "BC_4A") (pintype "bidirectional"))
      (node (ref "RGB55") (pin "4B") (pinfunction "BC_4B") (pintype "bidirectional"))
    )
    (net (code "489") (name "Net-(RGB54-GA-Pad1)") (class "Default")
      (node (ref "RGB54") (pin "1") (pinfunction "GA_1") (pintype "bidirectional"))
      (node (ref "RGB54") (pin "1A") (pinfunction "GA_1A") (pintype "bidirectional"))
      (node (ref "RGB54") (pin "1B") (pinfunction "GA_1B") (pintype "bidirectional"))
      (node (ref "RGB55") (pin "6") (pinfunction "GC_6") (pintype "bidirectional"))
      (node (ref "RGB55") (pin "6A") (pinfunction "GC_6A") (pintype "bidirectional"))
      (node (ref "RGB55") (pin "6B") (pinfunction "GC_6B") (pintype "bidirectional"))
    )
    (net (code "490") (name "Net-(RGB54-RA-Pad2)") (class "Default")
      (node (ref "RGB54") (pin "2") (pinfunction "RA_2") (pintype "bidirectional"))
      (node (ref "RGB54") (pin "2A") (pinfunction "RA_2A") (pintype "bidirectional"))
      (node (ref "RGB54") (pin "2B") (pinfunction "RA_2B") (pintype "bidirectional"))
      (node (ref "RGB55") (pin "5") (pinfunction "RC_5") (pintype "bidirectional"))
      (node (ref "RGB55") (pin "5A") (pinfunction "RC_5A") (pintype "bidirectional"))
      (node (ref "RGB55") (pin "5B") (pinfunction "RC_5B") (pintype "bidirectional"))
    )
    (net (code "491") (name "Net-(RGB55-BA-Pad3)") (class "Default")
      (node (ref "RGB55") (pin "3") (pinfunction "BA_3") (pintype "bidirectional"))
      (node (ref "RGB55") (pin "3A") (pinfunction "BA_3A") (pintype "bidirectional"))
      (node (ref "RGB55") (pin "3B") (pinfunction "BA_3B") (pintype "bidirectional"))
      (node (ref "RGB56") (pin "4") (pinfunction "BC_4") (pintype "bidirectional"))
      (node (ref "RGB56") (pin "4A") (pinfunction "BC_4A") (pintype "bidirectional"))
      (node (ref "RGB56") (pin "4B") (pinfunction "BC_4B") (pintype "bidirectional"))
    )
    (net (code "492") (name "Net-(RGB55-GA-Pad1)") (class "Default")
      (node (ref "RGB55") (pin "1") (pinfunction "GA_1") (pintype "bidirectional"))
      (node (ref "RGB55") (pin "1A") (pinfunction "GA_1A") (pintype "bidirectional"))
      (node (ref "RGB55") (pin "1B") (pinfunction "GA_1B") (pintype "bidirectional"))
      (node (ref "RGB56") (pin "6") (pinfunction "GC_6") (pintype "bidirectional"))
      (node (ref "RGB56") (pin "6A") (pinfunction "GC_6A") (pintype "bidirectional"))
      (node (ref "RGB56") (pin "6B") (pinfunction "GC_6B") (pintype "bidirectional"))
    )
    (net (code "493") (name "Net-(RGB55-RA-Pad2)") (class "Default")
      (node (ref "RGB55") (pin "2") (pinfunction "RA_2") (pintype "bidirectional"))
      (node (ref "RGB55") (pin "2A") (pinfunction "RA_2A") (pintype "bidirectional"))
      (node (ref "RGB55") (pin "2B") (pinfunction "RA_2B") (pintype "bidirectional"))
      (node (ref "RGB56") (pin "5") (pinfunction "RC_5") (pintype "bidirectional"))
      (node (ref "RGB56") (pin "5A") (pinfunction "RC_5A") (pintype "bidirectional"))
      (node (ref "RGB56") (pin "5B") (pinfunction "RC_5B") (pintype "bidirectional"))
    )
    (net (code "494") (name "Net-(RGB56-BA-Pad3)") (class "Default")
      (node (ref "RGB56") (pin "3") (pinfunction "BA_3") (pintype "bidirectional"))
      (node (ref "RGB56") (pin "3A") (pinfunction "BA_3A") (pintype "bidirectional"))
      (node (ref "RGB56") (pin "3B") (pinfunction "BA_3B") (pintype "bidirectional"))
      (node (ref "RGB64") (pin "4") (pinfunction "BC_4") (pintype "bidirectional"))
      (node (ref "RGB64") (pin "4A") (pinfunction "BC_4A") (pintype "bidirectional"))
      (node (ref "RGB64") (pin "4B") (pinfunction "BC_4B") (pintype "bidirectional"))
    )
    (net (code "495") (name "Net-(RGB56-GA-Pad1)") (class "Default")
      (node (ref "RGB56") (pin "1") (pinfunction "GA_1") (pintype "bidirectional"))
      (node (ref "RGB56") (pin "1A") (pinfunction "GA_1A") (pintype "bidirectional"))
      (node (ref "RGB56") (pin "1B") (pinfunction "GA_1B") (pintype "bidirectional"))
      (node (ref "RGB64") (pin "6") (pinfunction "GC_6") (pintype "bidirectional"))
      (node (ref "RGB64") (pin "6A") (pinfunction "GC_6A") (pintype "bidirectional"))
      (node (ref "RGB64") (pin "6B") (pinfunction "GC_6B") (pintype "bidirectional"))
    )
    (net (code "496") (name "Net-(RGB56-RA-Pad2)") (class "Default")
      (node (ref "RGB56") (pin "2") (pinfunction "RA_2") (pintype "bidirectional"))
      (node (ref "RGB56") (pin "2A") (pinfunction "RA_2A") (pintype "bidirectional"))
      (node (ref "RGB56") (pin "2B") (pinfunction "RA_2B") (pintype "bidirectional"))
      (node (ref "RGB64") (pin "5") (pinfunction "RC_5") (pintype "bidirectional"))
      (node (ref "RGB64") (pin "5A") (pinfunction "RC_5A") (pintype "bidirectional"))
      (node (ref "RGB64") (pin "5B") (pinfunction "RC_5B") (pintype "bidirectional"))
    )
    (net (code "497") (name "Net-(RGB57-BC-Pad4)") (class "Default")
      (node (ref "RGB57") (pin "4") (pinfunction "BC_4") (pintype "bidirectional"))
      (node (ref "RGB57") (pin "4A") (pinfunction "BC_4A") (pintype "bidirectional"))
      (node (ref "RGB57") (pin "4B") (pinfunction "BC_4B") (pintype "bidirectional"))
      (node (ref "RGB58") (pin "3") (pinfunction "BA_3") (pintype "bidirectional"))
      (node (ref "RGB58") (pin "3A") (pinfunction "BA_3A") (pintype "bidirectional"))
      (node (ref "RGB58") (pin "3B") (pinfunction "BA_3B") (pintype "bidirectional"))
    )
    (net (code "498") (name "Net-(RGB57-GC-Pad6)") (class "Default")
      (node (ref "RGB57") (pin "6") (pinfunction "GC_6") (pintype "bidirectional"))
      (node (ref "RGB57") (pin "6A") (pinfunction "GC_6A") (pintype "bidirectional"))
      (node (ref "RGB57") (pin "6B") (pinfunction "GC_6B") (pintype "bidirectional"))
      (node (ref "RGB58") (pin "1") (pinfunction "GA_1") (pintype "bidirectional"))
      (node (ref "RGB58") (pin "1A") (pinfunction "GA_1A") (pintype "bidirectional"))
      (node (ref "RGB58") (pin "1B") (pinfunction "GA_1B") (pintype "bidirectional"))
    )
    (net (code "499") (name "Net-(RGB57-RC-Pad5)") (class "Default")
      (node (ref "RGB57") (pin "5") (pinfunction "RC_5") (pintype "bidirectional"))
      (node (ref "RGB57") (pin "5A") (pinfunction "RC_5A") (pintype "bidirectional"))
      (node (ref "RGB57") (pin "5B") (pinfunction "RC_5B") (pintype "bidirectional"))
      (node (ref "RGB58") (pin "2") (pinfunction "RA_2") (pintype "bidirectional"))
      (node (ref "RGB58") (pin "2A") (pinfunction "RA_2A") (pintype "bidirectional"))
      (node (ref "RGB58") (pin "2B") (pinfunction "RA_2B") (pintype "bidirectional"))
    )
    (net (code "500") (name "Net-(RGB58-BC-Pad4)") (class "Default")
      (node (ref "RGB58") (pin "4") (pinfunction "BC_4") (pintype "bidirectional"))
      (node (ref "RGB58") (pin "4A") (pinfunction "BC_4A") (pintype "bidirectional"))
      (node (ref "RGB58") (pin "4B") (pinfunction "BC_4B") (pintype "bidirectional"))
      (node (ref "RGB59") (pin "3") (pinfunction "BA_3") (pintype "bidirectional"))
      (node (ref "RGB59") (pin "3A") (pinfunction "BA_3A") (pintype "bidirectional"))
      (node (ref "RGB59") (pin "3B") (pinfunction "BA_3B") (pintype "bidirectional"))
    )
    (net (code "501") (name "Net-(RGB58-GC-Pad6)") (class "Default")
      (node (ref "RGB58") (pin "6") (pinfunction "GC_6") (pintype "bidirectional"))
      (node (ref "RGB58") (pin "6A") (pinfunction "GC_6A") (pintype "bidirectional"))
      (node (ref "RGB58") (pin "6B") (pinfunction "GC_6B") (pintype "bidirectional"))
      (node (ref "RGB59") (pin "1") (pinfunction "GA_1") (pintype "bidirectional"))
      (node (ref "RGB59") (pin "1A") (pinfunction "GA_1A") (pintype "bidirectional"))
      (node (ref "RGB59") (pin "1B") (pinfunction "GA_1B") (pintype "bidirectional"))
    )
    (net (code "502") (name "Net-(RGB58-RC-Pad5)") (class "Default")
      (node (ref "RGB58") (pin "5") (pinfunction "RC_5") (pintype "bidirectional"))
      (node (ref "RGB58") (pin "5A") (pinfunction "RC_5A") (pintype "bidirectional"))
      (node (ref "RGB58") (pin "5B") (pinfunction "RC_5B") (pintype "bidirectional"))
      (node (ref "RGB59") (pin "2") (pinfunction "RA_2") (pintype "bidirectional"))
      (node (ref "RGB59") (pin "2A") (pinfunction "RA_2A") (pintype "bidirectional"))
      (node (ref "RGB59") (pin "2B") (pinfunction "RA_2B") (pintype "bidirectional"))
    )
    (net (code "503") (name "Net-(RGB59-BC-Pad4)") (class "Default")
      (node (ref "RGB59") (pin "4") (pinfunction "BC_4") (pintype "bidirectional"))
      (node (ref "RGB59") (pin "4A") (pinfunction "BC_4A") (pintype "bidirectional"))
      (node (ref "RGB59") (pin "4B") (pinfunction "BC_4B") (pintype "bidirectional"))
      (node (ref "RGB60") (pin "3") (pinfunction "BA_3") (pintype "bidirectional"))
      (node (ref "RGB60") (pin "3A") (pinfunction "BA_3A") (pintype "bidirectional"))
      (node (ref "RGB60") (pin "3B") (pinfunction "BA_3B") (pintype "bidirectional"))
    )
    (net (code "504") (name "Net-(RGB59-GC-Pad6)") (class "Default")
      (node (ref "RGB59") (pin "6") (pinfunction "GC_6") (pintype "bidirectional"))
      (node (ref "RGB59") (pin "6A") (pinfunction "GC_6A") (pintype "bidirectional"))
      (node (ref "RGB59") (pin "6B") (pinfunction "GC_6B") (pintype "bidirectional"))
      (node (ref "RGB60") (pin "1") (pinfunction "GA_1") (pintype "bidirectional"))
      (node (ref "RGB60") (pin "1A") (pinfunction "GA_1A") (pintype "bidirectional"))
      (node (ref "RGB60") (pin "1B") (pinfunction "GA_1B") (pintype "bidirectional"))
    )
    (net (code "505") (name "Net-(RGB59-RC-Pad5)") (class "Default")
      (node (ref "RGB59") (pin "5") (pinfunction "RC_5") (pintype "bidirectional"))
      (node (ref "RGB59") (pin "5A") (pinfunction "RC_5A") (pintype "bidirectional"))
      (node (ref "RGB59") (pin "5B") (pinfunction "RC_5B") (pintype "bidirectional"))
      (node (ref "RGB60") (pin "2") (pinfunction "RA_2") (pintype "bidirectional"))
      (node (ref "RGB60") (pin "2A") (pinfunction "RA_2A") (pintype "bidirectional"))
      (node (ref "RGB60") (pin "2B") (pinfunction "RA_2B") (pintype "bidirectional"))
    )
    (net (code "506") (name "Net-(RGB61-BC-Pad4)") (class "Default")
      (node (ref "RGB61") (pin "4") (pinfunction "BC_4") (pintype "bidirectional"))
      (node (ref "RGB61") (pin "4A") (pinfunction "BC_4A") (pintype "bidirectional"))
      (node (ref "RGB61") (pin "4B") (pinfunction "BC_4B") (pintype "bidirectional"))
      (node (ref "RGB62") (pin "3") (pinfunction "BA_3") (pintype "bidirectional"))
      (node (ref "RGB62") (pin "3A") (pinfunction "BA_3A") (pintype "bidirectional"))
      (node (ref "RGB62") (pin "3B") (pinfunction "BA_3B") (pintype "bidirectional"))
    )
    (net (code "507") (name "Net-(RGB61-GC-Pad6)") (class "Default")
      (node (ref "RGB61") (pin "6") (pinfunction "GC_6") (pintype "bidirectional"))
      (node (ref "RGB61") (pin "6A") (pinfunction "GC_6A") (pintype "bidirectional"))
      (node (ref "RGB61") (pin "6B") (pinfunction "GC_6B") (pintype "bidirectional"))
      (node (ref "RGB62") (pin "1") (pinfunction "GA_1") (pintype "bidirectional"))
      (node (ref "RGB62") (pin "1A") (pinfunction "GA_1A") (pintype "bidirectional"))
      (node (ref "RGB62") (pin "1B") (pinfunction "GA_1B") (pintype "bidirectional"))
    )
    (net (code "508") (name "Net-(RGB61-RC-Pad5)") (class "Default")
      (node (ref "RGB61") (pin "5") (pinfunction "RC_5") (pintype "bidirectional"))
      (node (ref "RGB61") (pin "5A") (pinfunction "RC_5A") (pintype "bidirectional"))
      (node (ref "RGB61") (pin "5B") (pinfunction "RC_5B") (pintype "bidirectional"))
      (node (ref "RGB62") (pin "2") (pinfunction "RA_2") (pintype "bidirectional"))
      (node (ref "RGB62") (pin "2A") (pinfunction "RA_2A") (pintype "bidirectional"))
      (node (ref "RGB62") (pin "2B") (pinfunction "RA_2B") (pintype "bidirectional"))
    )
    (net (code "509") (name "Net-(RGB62-BC-Pad4)") (class "Default")
      (node (ref "RGB62") (pin "4") (pinfunction "BC_4") (pintype "bidirectional"))
      (node (ref "RGB62") (pin "4A") (pinfunction "BC_4A") (pintype "bidirectional"))
      (node (ref "RGB62") (pin "4B") (pinfunction "BC_4B") (pintype "bidirectional"))
      (node (ref "RGB63") (pin "3") (pinfunction "BA_3") (pintype "bidirectional"))
      (node (ref "RGB63") (pin "3A") (pinfunction "BA_3A") (pintype "bidirectional"))
      (node (ref "RGB63") (pin "3B") (pinfunction "BA_3B") (pintype "bidirectional"))
    )
    (net (code "510") (name "Net-(RGB62-GC-Pad6)") (class "Default")
      (node (ref "RGB62") (pin "6") (pinfunction "GC_6") (pintype "bidirectional"))
      (node (ref "RGB62") (pin "6A") (pinfunction "GC_6A") (pintype "bidirectional"))
      (node (ref "RGB62") (pin "6B") (pinfunction "GC_6B") (pintype "bidirectional"))
      (node (ref "RGB63") (pin "1") (pinfunction "GA_1") (pintype "bidirectional"))
      (node (ref "RGB63") (pin "1A") (pinfunction "GA_1A") (pintype "bidirectional"))
      (node (ref "RGB63") (pin "1B") (pinfunction "GA_1B") (pintype "bidirectional"))
    )
    (net (code "511") (name "Net-(RGB62-RC-Pad5)") (class "Default")
      (node (ref "RGB62") (pin "5") (pinfunction "RC_5") (pintype "bidirectional"))
      (node (ref "RGB62") (pin "5A") (pinfunction "RC_5A") (pintype "bidirectional"))
      (node (ref "RGB62") (pin "5B") (pinfunction "RC_5B") (pintype "bidirectional"))
      (node (ref "RGB63") (pin "2") (pinfunction "RA_2") (pintype "bidirectional"))
      (node (ref "RGB63") (pin "2A") (pinfunction "RA_2A") (pintype "bidirectional"))
      (node (ref "RGB63") (pin "2B") (pinfunction "RA_2B") (pintype "bidirectional"))
    )
    (net (code "512") (name "Net-(RGB63-BC-Pad4)") (class "Default")
      (node (ref "RGB63") (pin "4") (pinfunction "BC_4") (pintype "bidirectional"))
      (node (ref "RGB63") (pin "4A") (pinfunction "BC_4A") (pintype "bidirectional"))
      (node (ref "RGB63") (pin "4B") (pinfunction "BC_4B") (pintype "bidirectional"))
      (node (ref "RGB64") (pin "3") (pinfunction "BA_3") (pintype "bidirectional"))
      (node (ref "RGB64") (pin "3A") (pinfunction "BA_3A") (pintype "bidirectional"))
      (node (ref "RGB64") (pin "3B") (pinfunction "BA_3B") (pintype "bidirectional"))
    )
    (net (code "513") (name "Net-(RGB63-GC-Pad6)") (class "Default")
      (node (ref "RGB63") (pin "6") (pinfunction "GC_6") (pintype "bidirectional"))
      (node (ref "RGB63") (pin "6A") (pinfunction "GC_6A") (pintype "bidirectional"))
      (node (ref "RGB63") (pin "6B") (pinfunction "GC_6B") (pintype "bidirectional"))
      (node (ref "RGB64") (pin "1") (pinfunction "GA_1") (pintype "bidirectional"))
      (node (ref "RGB64") (pin "1A") (pinfunction "GA_1A") (pintype "bidirectional"))
      (node (ref "RGB64") (pin "1B") (pinfunction "GA_1B") (pintype "bidirectional"))
    )
    (net (code "514") (name "Net-(RGB63-RC-Pad5)") (class "Default")
      (node (ref "RGB63") (pin "5") (pinfunction "RC_5") (pintype "bidirectional"))
      (node (ref "RGB63") (pin "5A") (pinfunction "RC_5A") (pintype "bidirectional"))
      (node (ref "RGB63") (pin "5B") (pinfunction "RC_5B") (pintype "bidirectional"))
      (node (ref "RGB64") (pin "2") (pinfunction "RA_2") (pintype "bidirectional"))
      (node (ref "RGB64") (pin "2A") (pinfunction "RA_2A") (pintype "bidirectional"))
      (node (ref "RGB64") (pin "2B") (pinfunction "RA_2B") (pintype "bidirectional"))
    )
    (net (code "515") (name "Net-(U7-SW)") (class "Default")
      (node (ref "D1") (pin "A") (pinfunction "A_A") (pintype "bidirectional"))
      (node (ref "L1") (pin "2") (pinfunction "2_2") (pintype "passive"))
      (node (ref "U7") (pin "5") (pinfunction "SW_5") (pintype "bidirectional"))
      (node (ref "U7") (pin "6") (pinfunction "SW1_6") (pintype "bidirectional"))
    )
    (net (code "516") (name "Net-(U8-REFIO)") (class "Default")
      (node (ref "C21") (pin "1") (pinfunction "1_1") (pintype "passive"))
      (node (ref "U8") (pin "10") (pinfunction "REFIO_10") (pintype "bidirectional"))
    )
    (net (code "517") (name "Net-(U9-REFIO)") (class "Default")
      (node (ref "C16") (pin "1") (pinfunction "1_1") (pintype "passive"))
      (node (ref "U9") (pin "10") (pinfunction "REFIO_10") (pintype "bidirectional"))
    )
    (net (code "518") (name "Net-(U10-SW)") (class "Default")
      (node (ref "D2") (pin "A") (pinfunction "A_A") (pintype "bidirectional"))
      (node (ref "L2") (pin "2") (pinfunction "2_2") (pintype "passive"))
      (node (ref "U10") (pin "5") (pinfunction "SW_5") (pintype "bidirectional"))
      (node (ref "U10") (pin "6") (pinfunction "SW1_6") (pintype "bidirectional"))
    )
    (net (code "519") (name "Net-(U15-REFIO)") (class "Default")
      (node (ref "C30") (pin "1") (pinfunction "1_1") (pintype "passive"))
      (node (ref "U15") (pin "10") (pinfunction "REFIO_10") (pintype "bidirectional"))
    )
    (net (code "520") (name "Net-(U17-SW)") (class "Default")
      (node (ref "D3") (pin "A") (pinfunction "A_A") (pintype "bidirectional"))
      (node (ref "L3") (pin "2") (pinfunction "2_2") (pintype "passive"))
      (node (ref "U17") (pin "5") (pinfunction "SW_5") (pintype "bidirectional"))
      (node (ref "U17") (pin "6") (pinfunction "SW1_6") (pintype "bidirectional"))
    )
    (net (code "521") (name "Net-(U19-REFIO)") (class "Default")
      (node (ref "C40") (pin "1") (pinfunction "1_1") (pintype "passive"))
      (node (ref "U19") (pin "10") (pinfunction "REFIO_10") (pintype "bidirectional"))
    )
    (net (code "522") (name "Net-(U22-SW)") (class "Default")
      (node (ref "D5") (pin "A") (pinfunction "A_A") (pintype "bidirectional"))
      (node (ref "L4") (pin "2") (pinfunction "2_2") (pintype "passive"))
      (node (ref "U22") (pin "5") (pinfunction "SW_5") (pintype "bidirectional"))
      (node (ref "U22") (pin "6") (pinfunction "SW1_6") (pintype "bidirectional"))
    )
    (net (code "523") (name "OTMP") (class "Default")
      (node (ref "M1") (pin "16") (pinfunction "14/A0_16") (pintype "bidirectional"))
      (node (ref "U12") (pin "5") (pinfunction "OS_5") (pintype "bidirectional"))
    )
    (net (code "524") (name "R1A") (class "Default")
      (node (ref "Q4") (pin "5") (pinfunction "C2_5") (pintype "bidirectional"))
      (node (ref "Q4") (pin "56") (pinfunction "C2_56") (pintype "bidirectional"))
      (node (ref "Q4") (pin "56A") (pinfunction "C2_56A") (pintype "bidirectional"))
      (node (ref "Q4") (pin "56B") (pinfunction "C2_56B") (pintype "bidirectional"))
      (node (ref "Q4") (pin "5A") (pinfunction "C2_5A") (pintype "bidirectional"))
      (node (ref "Q4") (pin "5A1") (pinfunction "C2_5A1") (pintype "bidirectional"))
      (node (ref "Q4") (pin "5B") (pinfunction "C2_5B") (pintype "bidirectional"))
      (node (ref "Q4") (pin "5C") (pinfunction "C2_5C") (pintype "bidirectional"))
      (node (ref "Q4") (pin "5C1") (pinfunction "C2_5C1") (pintype "bidirectional"))
      (node (ref "Q4") (pin "5C2") (pinfunction "C2_5C2") (pintype "bidirectional"))
      (node (ref "Q4") (pin "6") (pinfunction "C2_6") (pintype "bidirectional"))
      (node (ref "RGB53") (pin "5") (pinfunction "RC_5") (pintype "bidirectional"))
      (node (ref "RGB53") (pin "5A") (pinfunction "RC_5A") (pintype "bidirectional"))
      (node (ref "RGB53") (pin "5B") (pinfunction "RC_5B") (pintype "bidirectional"))
    )
    (net (code "525") (name "R1B") (class "Default")
      (node (ref "Q4") (pin "7") (pinfunction "C1_7") (pintype "bidirectional"))
      (node (ref "Q4") (pin "78") (pinfunction "C1_78") (pintype "bidirectional"))
      (node (ref "Q4") (pin "78A") (pinfunction "C1_78A") (pintype "bidirectional"))
      (node (ref "Q4") (pin "78B") (pinfunction "C1_78B") (pintype "bidirectional"))
      (node (ref "Q4") (pin "8") (pinfunction "C1_8") (pintype "bidirectional"))
      (node (ref "Q4") (pin "8A") (pinfunction "C1_8A") (pintype "bidirectional"))
      (node (ref "Q4") (pin "8B") (pinfunction "C1_8B") (pintype "bidirectional"))
      (node (ref "Q4") (pin "8C") (pinfunction "C1_8C") (pintype "bidirectional"))
      (node (ref "Q4") (pin "8C1") (pinfunction "C1_8C1") (pintype "bidirectional"))
      (node (ref "Q4") (pin "8C2") (pinfunction "C1_8C2") (pintype "bidirectional"))
      (node (ref "Q4") (pin "8C3") (pinfunction "C1_8C3") (pintype "bidirectional"))
      (node (ref "RGB37") (pin "5") (pinfunction "RC_5") (pintype "bidirectional"))
      (node (ref "RGB37") (pin "5A") (pinfunction "RC_5A") (pintype "bidirectional"))
      (node (ref "RGB37") (pin "5B") (pinfunction "RC_5B") (pintype "bidirectional"))
    )
    (net (code "526") (name "RED_LL") (class "Default")
      (node (ref "U19") (pin "4") (pinfunction "VO_C_4") (pintype "bidirectional"))
      (node (ref "U20") (pin "3") (pinfunction "IN+_3") (pintype "input"))
    )
    (net (code "527") (name "RED_LR") (class "Default")
      (node (ref "U5") (pin "3") (pinfunction "IN+_3") (pintype "input"))
      (node (ref "U9") (pin "4") (pinfunction "VO_C_4") (pintype "bidirectional"))
    )
    (net (code "528") (name "RED_UL") (class "Default")
      (node (ref "U14") (pin "3") (pinfunction "IN+_3") (pintype "input"))
      (node (ref "U15") (pin "4") (pinfunction "VO_C_4") (pintype "bidirectional"))
    )
    (net (code "529") (name "RED_UR") (class "Default")
      (node (ref "U6") (pin "3") (pinfunction "IN+_3") (pintype "input"))
      (node (ref "U8") (pin "4") (pinfunction "VO_C_4") (pintype "bidirectional"))
    )
    (net (code "530") (name "RULA_1") (class "Default")
      (node (ref "Q8") (pin "5") (pinfunction "C2_5") (pintype "bidirectional"))
      (node (ref "Q8") (pin "56") (pinfunction "C2_56") (pintype "bidirectional"))
      (node (ref "Q8") (pin "56A") (pinfunction "C2_56A") (pintype "bidirectional"))
      (node (ref "Q8") (pin "56B") (pinfunction "C2_56B") (pintype "bidirectional"))
      (node (ref "Q8") (pin "5A") (pinfunction "C2_5A") (pintype "bidirectional"))
      (node (ref "Q8") (pin "5A1") (pinfunction "C2_5A1") (pintype "bidirectional"))
      (node (ref "Q8") (pin "5B") (pinfunction "C2_5B") (pintype "bidirectional"))
      (node (ref "Q8") (pin "5C") (pinfunction "C2_5C") (pintype "bidirectional"))
      (node (ref "Q8") (pin "5C1") (pinfunction "C2_5C1") (pintype "bidirectional"))
      (node (ref "Q8") (pin "5C2") (pinfunction "C2_5C2") (pintype "bidirectional"))
      (node (ref "Q8") (pin "6") (pinfunction "C2_6") (pintype "bidirectional"))
      (node (ref "RGB17") (pin "5") (pinfunction "RC_5") (pintype "bidirectional"))
      (node (ref "RGB17") (pin "5A") (pinfunction "RC_5A") (pintype "bidirectional"))
      (node (ref "RGB17") (pin "5B") (pinfunction "RC_5B") (pintype "bidirectional"))
    )
    (net (code "531") (name "RULB_1") (class "Default")
      (node (ref "Q8") (pin "7") (pinfunction "C1_7") (pintype "bidirectional"))
      (node (ref "Q8") (pin "78") (pinfunction "C1_78") (pintype "bidirectional"))
      (node (ref "Q8") (pin "78A") (pinfunction "C1_78A") (pintype "bidirectional"))
      (node (ref "Q8") (pin "78B") (pinfunction "C1_78B") (pintype "bidirectional"))
      (node (ref "Q8") (pin "8") (pinfunction "C1_8") (pintype "bidirectional"))
      (node (ref "Q8") (pin "8A") (pinfunction "C1_8A") (pintype "bidirectional"))
      (node (ref "Q8") (pin "8B") (pinfunction "C1_8B") (pintype "bidirectional"))
      (node (ref "Q8") (pin "8C") (pinfunction "C1_8C") (pintype "bidirectional"))
      (node (ref "Q8") (pin "8C1") (pinfunction "C1_8C1") (pintype "bidirectional"))
      (node (ref "Q8") (pin "8C2") (pinfunction "C1_8C2") (pintype "bidirectional"))
      (node (ref "Q8") (pin "8C3") (pinfunction "C1_8C3") (pintype "bidirectional"))
      (node (ref "RGB1") (pin "5") (pinfunction "RC_5") (pintype "bidirectional"))
      (node (ref "RGB1") (pin "5A") (pinfunction "RC_5A") (pintype "bidirectional"))
      (node (ref "RGB1") (pin "5B") (pinfunction "RC_5B") (pintype "bidirectional"))
    )
    (net (code "532") (name "RX") (class "Default")
      (node (ref "J6") (pin "2") (pinfunction "P$2_2") (pintype "bidirectional"))
      (node (ref "M1") (pin "2") (pinfunction "0/RX1/T_2") (pintype "bidirectional"))
      (node (ref "U11") (pin "3") (pinfunction "A_3") (pintype "bidirectional"))
    )
    (net (code "533") (name "RX2") (class "Default")
      (node (ref "J1") (pin "1") (pinfunction "P$1_1") (pintype "bidirectional"))
      (node (ref "J3") (pin "1") (pinfunction "P$1_1") (pintype "bidirectional"))
      (node (ref "M1") (pin "11") (pinfunction "9/RX2/PWM_11") (pintype "bidirectional"))
    )
    (net (code "534") (name "SCLK") (class "Default")
      (node (ref "M1") (pin "15") (pinfunction "13/SCK/LED_15") (pintype "bidirectional"))
      (node (ref "U15") (pin "7") (pinfunction "SCLK_7") (pintype "bidirectional"))
      (node (ref "U19") (pin "7") (pinfunction "SCLK_7") (pintype "bidirectional"))
      (node (ref "U8") (pin "7") (pinfunction "SCLK_7") (pintype "bidirectional"))
      (node (ref "U9") (pin "7") (pinfunction "SCLK_7") (pintype "bidirectional"))
    )
    (net (code "535") (name "SYNC") (class "Default")
      (node (ref "J5") (pin "P$1") (pinfunction "P$1_P$1") (pintype "bidirectional"))
      (node (ref "R62") (pin "1") (pinfunction "1_1") (pintype "passive"))
    )
    (net (code "536") (name "SYNCIN") (class "Default")
      (node (ref "M1") (pin "21") (pinfunction "19/A5/T/SCL0_21") (pintype "bidirectional"))
      (node (ref "R62") (pin "2") (pinfunction "2_2") (pintype "passive"))
    )
    (net (code "537") (name "TX") (class "Default")
      (node (ref "M1") (pin "3") (pinfunction "1/TX1/T_3") (pintype "bidirectional"))
      (node (ref "U11") (pin "1") (pinfunction "B_1") (pintype "bidirectional"))
    )
    (net (code "538") (name "TX2") (class "Default")
      (node (ref "J1") (pin "3") (pinfunction "P$3_3") (pintype "bidirectional"))
      (node (ref "J3") (pin "3") (pinfunction "P$3_3") (pintype "bidirectional"))
      (node (ref "M1") (pin "12") (pinfunction "10/TX2/PWM_12") (pintype "bidirectional"))
    )
    (net (code "539") (name "TXRX") (class "Default")
      (node (ref "J4") (pin "2") (pinfunction "P$2_2") (pintype "bidirectional"))
      (node (ref "U11") (pin "4") (pinfunction "X_4") (pintype "bidirectional"))
    )
    (net (code "540") (name "UL_EN") (class "Default")
      (node (ref "M1") (pin "20") (pinfunction "18/A4/T/SDA0_20") (pintype "bidirectional"))
      (node (ref "U15") (pin "6") (pinfunction "~{SYNC}_6") (pintype "bidirectional"))
    )
    (net (code "541") (name "UR_EN") (class "Default")
      (node (ref "M1") (pin "18") (pinfunction "16/A2/T_18") (pintype "bidirectional"))
      (node (ref "U8") (pin "6") (pinfunction "~{SYNC}_6") (pintype "bidirectional"))
    )
    (net (code "542") (name "V_IR") (class "Default")
      (node (ref "C11") (pin "1") (pinfunction "1_1") (pintype "passive"))
      (node (ref "C15") (pin "1") (pinfunction "1_1") (pintype "passive"))
      (node (ref "C34") (pin "1") (pinfunction "1_1") (pintype "passive"))
      (node (ref "C46") (pin "1") (pinfunction "1_1") (pintype "passive"))
      (node (ref "D1") (pin "K") (pinfunction "K_K") (pintype "bidirectional"))
      (node (ref "D2") (pin "K") (pinfunction "K_K") (pintype "bidirectional"))
      (node (ref "D3") (pin "K") (pinfunction "K_K") (pintype "bidirectional"))
      (node (ref "D5") (pin "K") (pinfunction "K_K") (pintype "bidirectional"))
      (node (ref "R20") (pin "2") (pinfunction "2_2") (pintype "passive"))
      (node (ref "R22") (pin "2") (pinfunction "2_2") (pintype "passive"))
      (node (ref "R42") (pin "2") (pinfunction "2_2") (pintype "passive"))
      (node (ref "R61") (pin "2") (pinfunction "2_2") (pintype "passive"))
      (node (ref "SH1") (pin "1") (pinfunction "1_1") (pintype "bidirectional"))
      (node (ref "U10") (pin "4") (pinfunction "VIN_4") (pintype "bidirectional"))
      (node (ref "U17") (pin "4") (pinfunction "VIN_4") (pintype "bidirectional"))
      (node (ref "U22") (pin "4") (pinfunction "VIN_4") (pintype "bidirectional"))
      (node (ref "U7") (pin "4") (pinfunction "VIN_4") (pintype "bidirectional"))
    )
    (net (code "543") (name "V_RGB") (class "Default")
      (node (ref "C1") (pin "1") (pinfunction "1_1") (pintype "passive"))
      (node (ref "C12") (pin "1") (pinfunction "1_1") (pintype "passive"))
      (node (ref "C14") (pin "1") (pinfunction "1_1") (pintype "passive"))
      (node (ref "C17") (pin "+") (pinfunction "+_+") (pintype "passive"))
      (node (ref "C18") (pin "+") (pinfunction "+_+") (pintype "passive"))
      (node (ref "C2") (pin "1") (pinfunction "1_1") (pintype "passive"))
      (node (ref "C27") (pin "1") (pinfunction "1_1") (pintype "passive"))
      (node (ref "C29") (pin "1") (pinfunction "1_1") (pintype "passive"))
      (node (ref "C3") (pin "1") (pinfunction "1_1") (pintype "passive"))
      (node (ref "C33") (pin "1") (pinfunction "1_1") (pintype "passive"))
      (node (ref "C36") (pin "1") (pinfunction "1_1") (pintype "passive"))
      (node (ref "C37") (pin "+") (pinfunction "+_+") (pintype "passive"))
      (node (ref "C4") (pin "1") (pinfunction "1_1") (pintype "passive"))
      (node (ref "C41") (pin "1") (pinfunction "1_1") (pintype "passive"))
      (node (ref "C43") (pin "1") (pinfunction "1_1") (pintype "passive"))
      (node (ref "J2") (pin "1A") (pinfunction "P$1_1A") (pintype "bidirectional"))
      (node (ref "J2") (pin "1B") (pinfunction "P$1_1B") (pintype "bidirectional"))
      (node (ref "R13") (pin "2") (pinfunction "2_2") (pintype "passive"))
      (node (ref "R14") (pin "2") (pinfunction "2_2") (pintype "passive"))
      (node (ref "R15") (pin "2") (pinfunction "2_2") (pintype "passive"))
      (node (ref "R16") (pin "2") (pinfunction "2_2") (pintype "passive"))
      (node (ref "R18") (pin "2") (pinfunction "2_2") (pintype "passive"))
      (node (ref "R19") (pin "2") (pinfunction "2_2") (pintype "passive"))
      (node (ref "R28") (pin "2") (pinfunction "2_2") (pintype "passive"))
      (node (ref "R31") (pin "2") (pinfunction "2_2") (pintype "passive"))
      (node (ref "R40") (pin "2") (pinfunction "2_2") (pintype "passive"))
      (node (ref "R46") (pin "2") (pinfunction "2_2") (pintype "passive"))
      (node (ref "R50") (pin "2") (pinfunction "2_2") (pintype "passive"))
      (node (ref "R59") (pin "2") (pinfunction "2_2") (pintype "passive"))
      (node (ref "RGB13") (pin "1") (pinfunction "GA_1") (pintype "bidirectional"))
      (node (ref "RGB13") (pin "1A") (pinfunction "GA_1A") (pintype "bidirectional"))
      (node (ref "RGB13") (pin "1B") (pinfunction "GA_1B") (pintype "bidirectional"))
      (node (ref "RGB13") (pin "2") (pinfunction "RA_2") (pintype "bidirectional"))
      (node (ref "RGB13") (pin "2A") (pinfunction "RA_2A") (pintype "bidirectional"))
      (node (ref "RGB13") (pin "2B") (pinfunction "RA_2B") (pintype "bidirectional"))
      (node (ref "RGB13") (pin "3") (pinfunction "BA_3") (pintype "bidirectional"))
      (node (ref "RGB13") (pin "3A") (pinfunction "BA_3A") (pintype "bidirectional"))
      (node (ref "RGB13") (pin "3B") (pinfunction "BA_3B") (pintype "bidirectional"))
      (node (ref "RGB25") (pin "1") (pinfunction "GA_1") (pintype "bidirectional"))
      (node (ref "RGB25") (pin "1A") (pinfunction "GA_1A") (pintype "bidirectional"))
      (node (ref "RGB25") (pin "1B") (pinfunction "GA_1B") (pintype "bidirectional"))
      (node (ref "RGB25") (pin "2") (pinfunction "RA_2") (pintype "bidirectional"))
      (node (ref "RGB25") (pin "2A") (pinfunction "RA_2A") (pintype "bidirectional"))
      (node (ref "RGB25") (pin "2B") (pinfunction "RA_2B") (pintype "bidirectional"))
      (node (ref "RGB25") (pin "3") (pinfunction "BA_3") (pintype "bidirectional"))
      (node (ref "RGB25") (pin "3A") (pinfunction "BA_3A") (pintype "bidirectional"))
      (node (ref "RGB25") (pin "3B") (pinfunction "BA_3B") (pintype "bidirectional"))
      (node (ref "RGB29") (pin "1") (pinfunction "GA_1") (pintype "bidirectional"))
      (node (ref "RGB29") (pin "1A") (pinfunction "GA_1A") (pintype "bidirectional"))
      (node (ref "RGB29") (pin "1B") (pinfunction "GA_1B") (pintype "bidirectional"))
      (node (ref "RGB29") (pin "2") (pinfunction "RA_2") (pintype "bidirectional"))
      (node (ref "RGB29") (pin "2A") (pinfunction "RA_2A") (pintype "bidirectional"))
      (node (ref "RGB29") (pin "2B") (pinfunction "RA_2B") (pintype "bidirectional"))
      (node (ref "RGB29") (pin "3") (pinfunction "BA_3") (pintype "bidirectional"))
      (node (ref "RGB29") (pin "3A") (pinfunction "BA_3A") (pintype "bidirectional"))
      (node (ref "RGB29") (pin "3B") (pinfunction "BA_3B") (pintype "bidirectional"))
      (node (ref "RGB41") (pin "1") (pinfunction "GA_1") (pintype "bidirectional"))
      (node (ref "RGB41") (pin "1A") (pinfunction "GA_1A") (pintype "bidirectional"))
      (node (ref "RGB41") (pin "1B") (pinfunction "GA_1B") (pintype "bidirectional"))
      (node (ref "RGB41") (pin "2") (pinfunction "RA_2") (pintype "bidirectional"))
      (node (ref "RGB41") (pin "2A") (pinfunction "RA_2A") (pintype "bidirectional"))
      (node (ref "RGB41") (pin "2B") (pinfunction "RA_2B") (pintype "bidirectional"))
      (node (ref "RGB41") (pin "3") (pinfunction "BA_3") (pintype "bidirectional"))
      (node (ref "RGB41") (pin "3A") (pinfunction "BA_3A") (pintype "bidirectional"))
      (node (ref "RGB41") (pin "3B") (pinfunction "BA_3B") (pintype "bidirectional"))
      (node (ref "RGB45") (pin "1") (pinfunction "GA_1") (pintype "bidirectional"))
      (node (ref "RGB45") (pin "1A") (pinfunction "GA_1A") (pintype "bidirectional"))
      (node (ref "RGB45") (pin "1B") (pinfunction "GA_1B") (pintype "bidirectional"))
      (node (ref "RGB45") (pin "2") (pinfunction "RA_2") (pintype "bidirectional"))
      (node (ref "RGB45") (pin "2A") (pinfunction "RA_2A") (pintype "bidirectional"))
      (node (ref "RGB45") (pin "2B") (pinfunction "RA_2B") (pintype "bidirectional"))
      (node (ref "RGB45") (pin "3") (pinfunction "BA_3") (pintype "bidirectional"))
      (node (ref "RGB45") (pin "3A") (pinfunction "BA_3A") (pintype "bidirectional"))
      (node (ref "RGB45") (pin "3B") (pinfunction "BA_3B") (pintype "bidirectional"))
      (node (ref "RGB57") (pin "1") (pinfunction "GA_1") (pintype "bidirectional"))
      (node (ref "RGB57") (pin "1A") (pinfunction "GA_1A") (pintype "bidirectional"))
      (node (ref "RGB57") (pin "1B") (pinfunction "GA_1B") (pintype "bidirectional"))
      (node (ref "RGB57") (pin "2") (pinfunction "RA_2") (pintype "bidirectional"))
      (node (ref "RGB57") (pin "2A") (pinfunction "RA_2A") (pintype "bidirectional"))
      (node (ref "RGB57") (pin "2B") (pinfunction "RA_2B") (pintype "bidirectional"))
      (node (ref "RGB57") (pin "3") (pinfunction "BA_3") (pintype "bidirectional"))
      (node (ref "RGB57") (pin "3A") (pinfunction "BA_3A") (pintype "bidirectional"))
      (node (ref "RGB57") (pin "3B") (pinfunction "BA_3B") (pintype "bidirectional"))
      (node (ref "RGB61") (pin "1") (pinfunction "GA_1") (pintype "bidirectional"))
      (node (ref "RGB61") (pin "1A") (pinfunction "GA_1A") (pintype "bidirectional"))
      (node (ref "RGB61") (pin "1B") (pinfunction "GA_1B") (pintype "bidirectional"))
      (node (ref "RGB61") (pin "2") (pinfunction "RA_2") (pintype "bidirectional"))
      (node (ref "RGB61") (pin "2A") (pinfunction "RA_2A") (pintype "bidirectional"))
      (node (ref "RGB61") (pin "2B") (pinfunction "RA_2B") (pintype "bidirectional"))
      (node (ref "RGB61") (pin "3") (pinfunction "BA_3") (pintype "bidirectional"))
      (node (ref "RGB61") (pin "3A") (pinfunction "BA_3A") (pintype "bidirectional"))
      (node (ref "RGB61") (pin "3B") (pinfunction "BA_3B") (pintype "bidirectional"))
      (node (ref "RGB9") (pin "1") (pinfunction "GA_1") (pintype "bidirectional"))
      (node (ref "RGB9") (pin "1A") (pinfunction "GA_1A") (pintype "bidirectional"))
      (node (ref "RGB9") (pin "1B") (pinfunction "GA_1B") (pintype "bidirectional"))
      (node (ref "RGB9") (pin "2") (pinfunction "RA_2") (pintype "bidirectional"))
      (node (ref "RGB9") (pin "2A") (pinfunction "RA_2A") (pintype "bidirectional"))
      (node (ref "RGB9") (pin "2B") (pinfunction "RA_2B") (pintype "bidirectional"))
      (node (ref "RGB9") (pin "3") (pinfunction "BA_3") (pintype "bidirectional"))
      (node (ref "RGB9") (pin "3A") (pinfunction "BA_3A") (pintype "bidirectional"))
      (node (ref "RGB9") (pin "3B") (pinfunction "BA_3B") (pintype "bidirectional"))
      (node (ref "SH1") (pin "2") (pinfunction "2_2") (pintype "bidirectional"))
    )
    (net (code "544") (name "unconnected-(J2-P$2-Pad3)") (class "Default")
      (node (ref "J2") (pin "3") (pinfunction "P$2_3") (pintype "bidirectional"))
    )
    (net (code "545") (name "unconnected-(M1-3{slash}CAN-TX{slash}PWM-Pad5)") (class "Default")
      (node (ref "M1") (pin "5") (pinfunction "3/CAN-TX/PWM_5") (pintype "bidirectional"))
    )
    (net (code "546") (name "unconnected-(M1-4{slash}CAN-RX-PWM-Pad6)") (class "Default")
      (node (ref "M1") (pin "6") (pinfunction "4/CAN-RX-PWM_6") (pintype "bidirectional"))
    )
    (net (code "547") (name "unconnected-(M1-5{slash}PWM-Pad7)") (class "Default")
      (node (ref "M1") (pin "7") (pinfunction "5/PWM_7") (pintype "bidirectional"))
    )
    (net (code "548") (name "unconnected-(M1-6{slash}PWM-Pad8)") (class "Default")
      (node (ref "M1") (pin "8") (pinfunction "6/PWM_8") (pintype "bidirectional"))
    )
    (net (code "549") (name "unconnected-(M1-7{slash}RX3-Pad9)") (class "Default")
      (node (ref "M1") (pin "9") (pinfunction "7/RX3_9") (pintype "bidirectional"))
    )
    (net (code "550") (name "unconnected-(M1-8{slash}TX3-Pad10)") (class "Default")
      (node (ref "M1") (pin "10") (pinfunction "8/TX3_10") (pintype "bidirectional"))
    )
    (net (code "551") (name "unconnected-(M1-12{slash}MISO-Pad14)") (class "Default")
      (node (ref "M1") (pin "14") (pinfunction "12/MISO_14") (pintype "bidirectional"))
    )
    (net (code "552") (name "unconnected-(M1-21{slash}A7{slash}PWM-Pad23)") (class "Default")
      (node (ref "M1") (pin "23") (pinfunction "21/A7/PWM_23") (pintype "bidirectional"))
    )
    (net (code "553") (name "unconnected-(M1-22{slash}A8{slash}T{slash}PWM-Pad24)") (class "Default")
      (node (ref "M1") (pin "24") (pinfunction "22/A8/T/PWM_24") (pintype "bidirectional"))
    )
    (net (code "554") (name "unconnected-(M1-23{slash}A9{slash}T{slash}PWM-Pad25)") (class "Default")
      (node (ref "M1") (pin "25") (pinfunction "23/A9/T/PWM_25") (pintype "bidirectional"))
    )
    (net (code "555") (name "unconnected-(U7-N{slash}C-Pad3)") (class "Default")
      (node (ref "U7") (pin "3") (pinfunction "N/C_3") (pintype "bidirectional"))
    )
    (net (code "556") (name "unconnected-(U10-N{slash}C-Pad3)") (class "Default")
      (node (ref "U10") (pin "3") (pinfunction "N/C_3") (pintype "bidirectional"))
    )
    (net (code "557") (name "unconnected-(U12-VTMP-Pad3)") (class "Default")
      (node (ref "U12") (pin "3") (pinfunction "VTMP_3") (pintype "bidirectional"))
    )
    (net (code "558") (name "unconnected-(U17-N{slash}C-Pad3)") (class "Default")
      (node (ref "U17") (pin "3") (pinfunction "N/C_3") (pintype "bidirectional"))
    )
    (net (code "559") (name "unconnected-(U22-N{slash}C-Pad3)") (class "Default")
      (node (ref "U22") (pin "3") (pinfunction "N/C_3") (pintype "bidirectional"))
    )
  )
)
